# BoardSchem.net
KiCad netlist of a schematic drawn in EAGLE
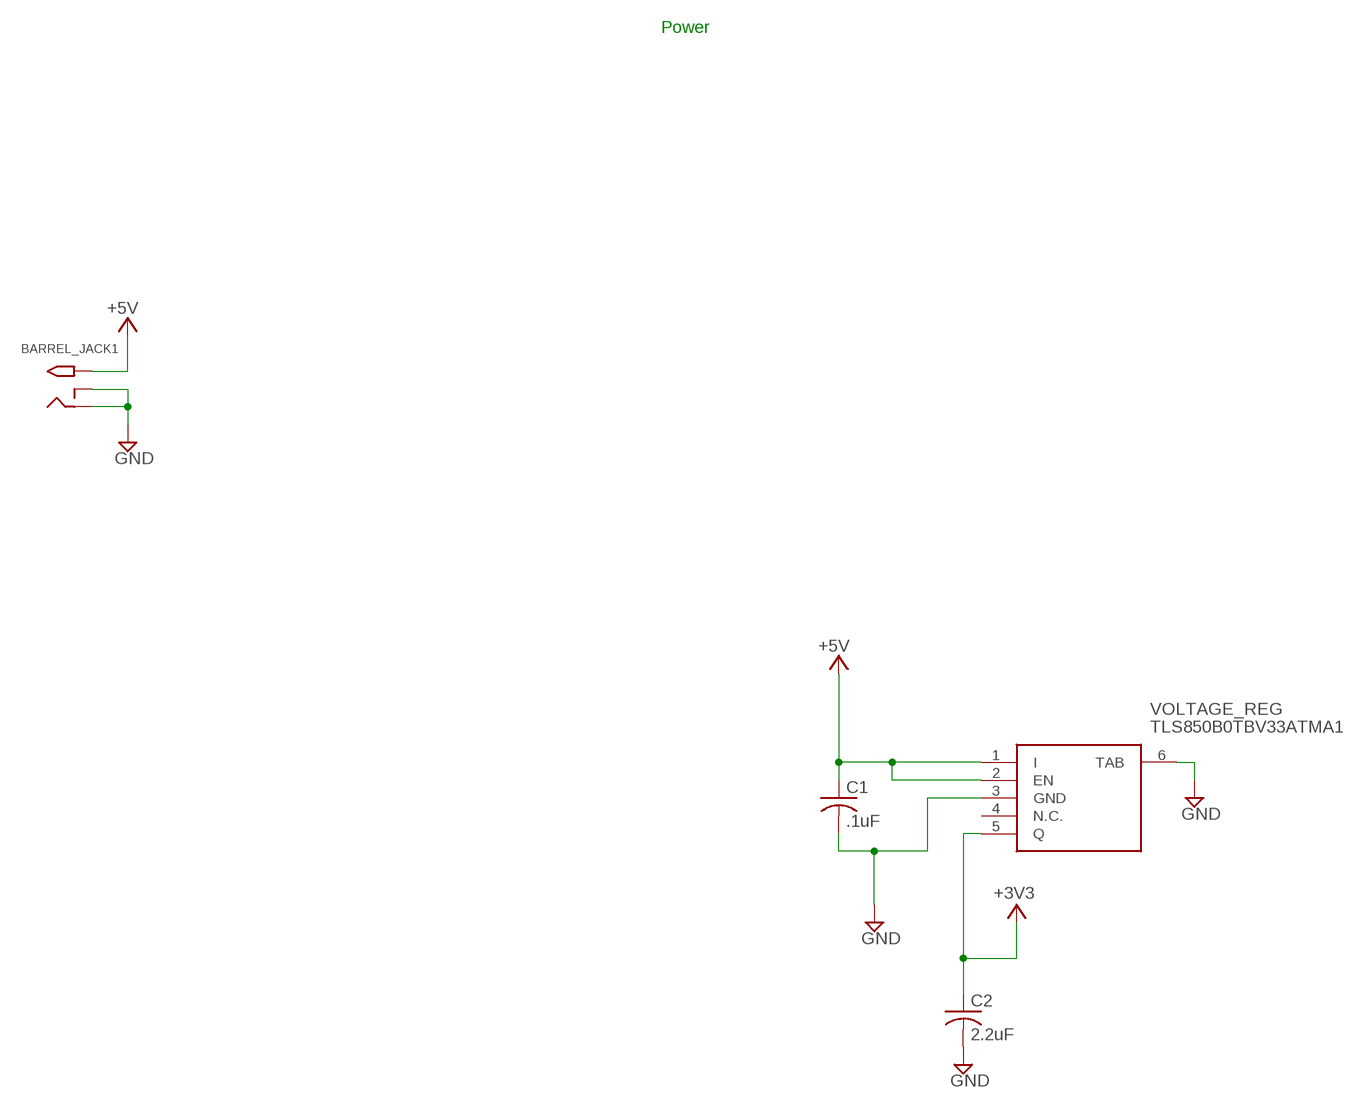
[diagram p0: schematic, sheet 1]
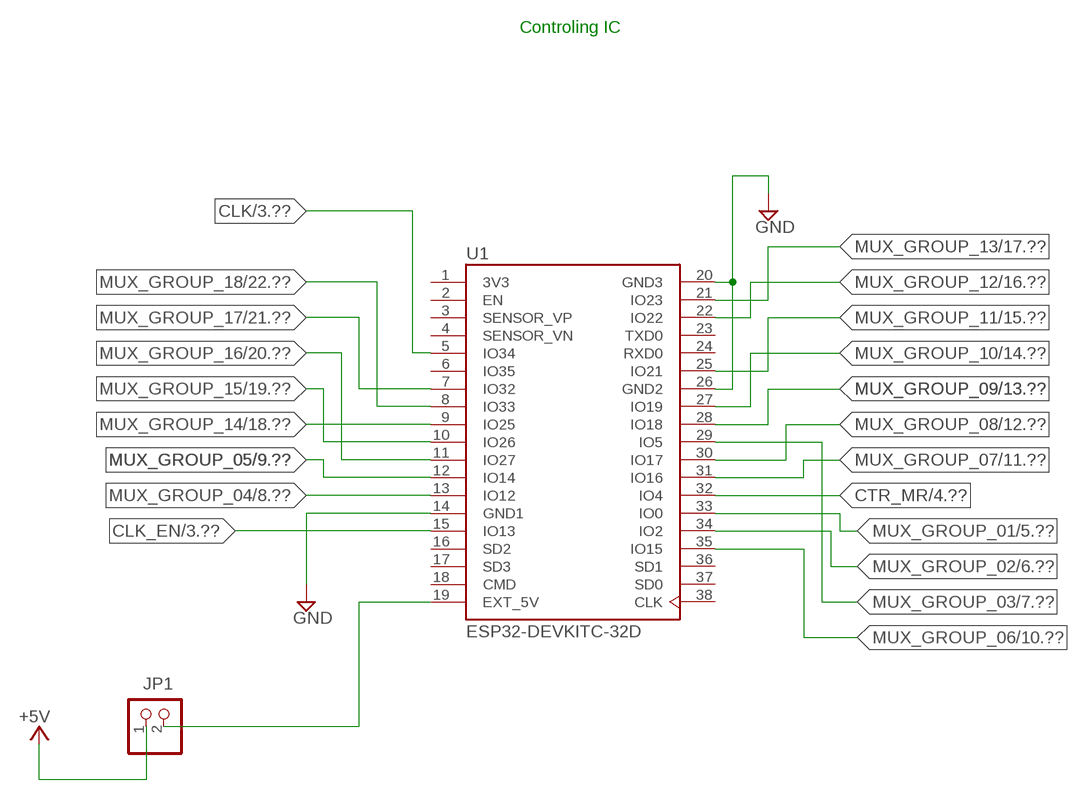
[diagram p1: schematic, sheet 2]
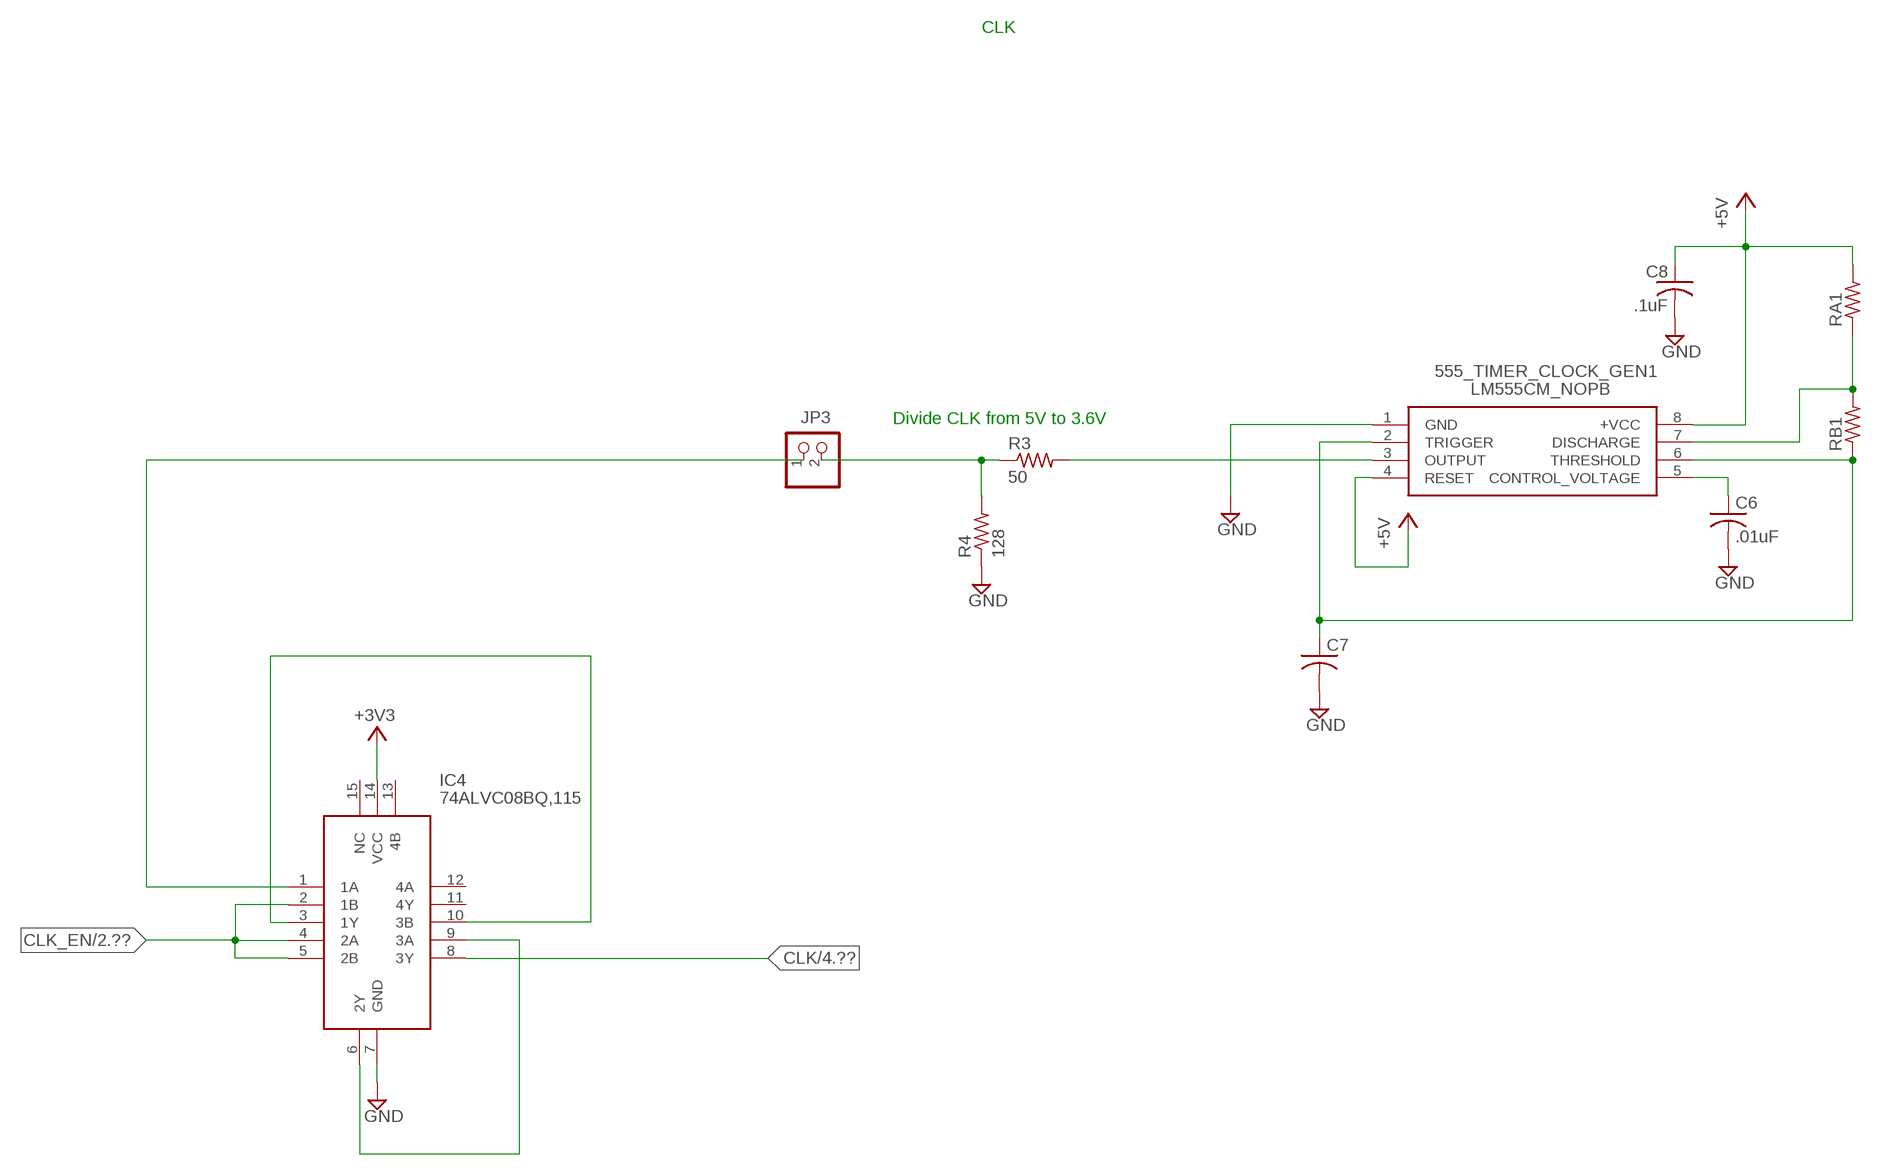
[diagram p2: schematic, sheet 3]
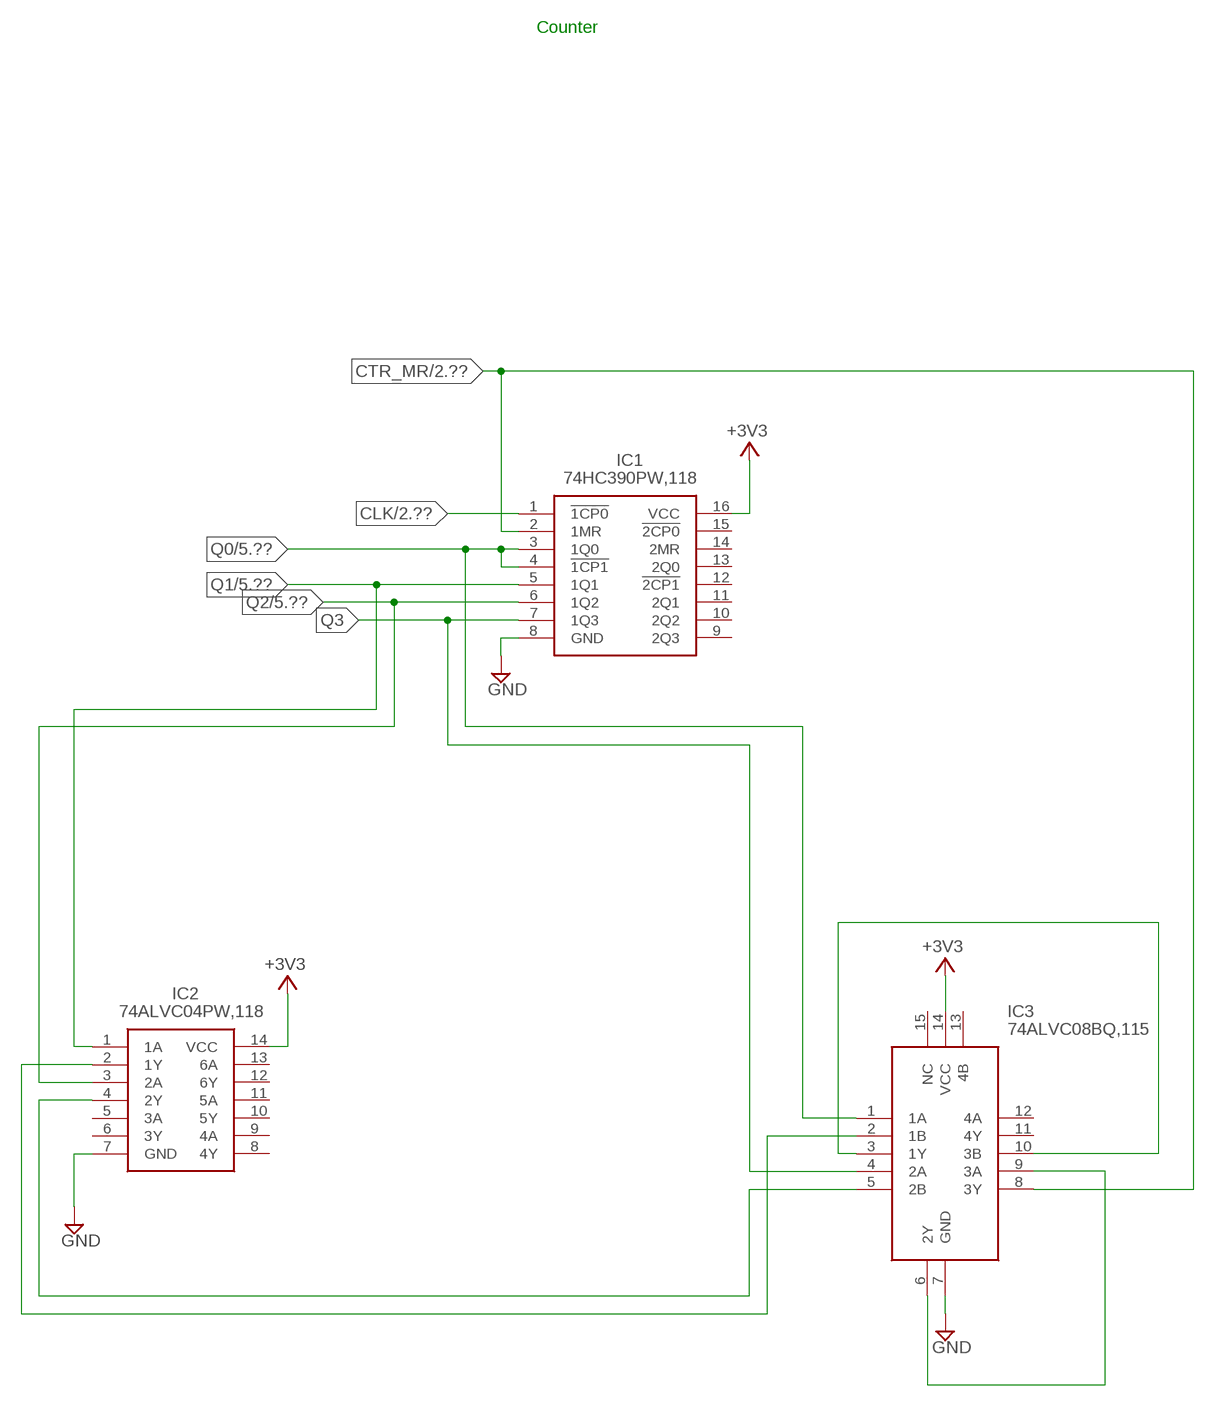
[diagram p3: schematic, sheet 4]
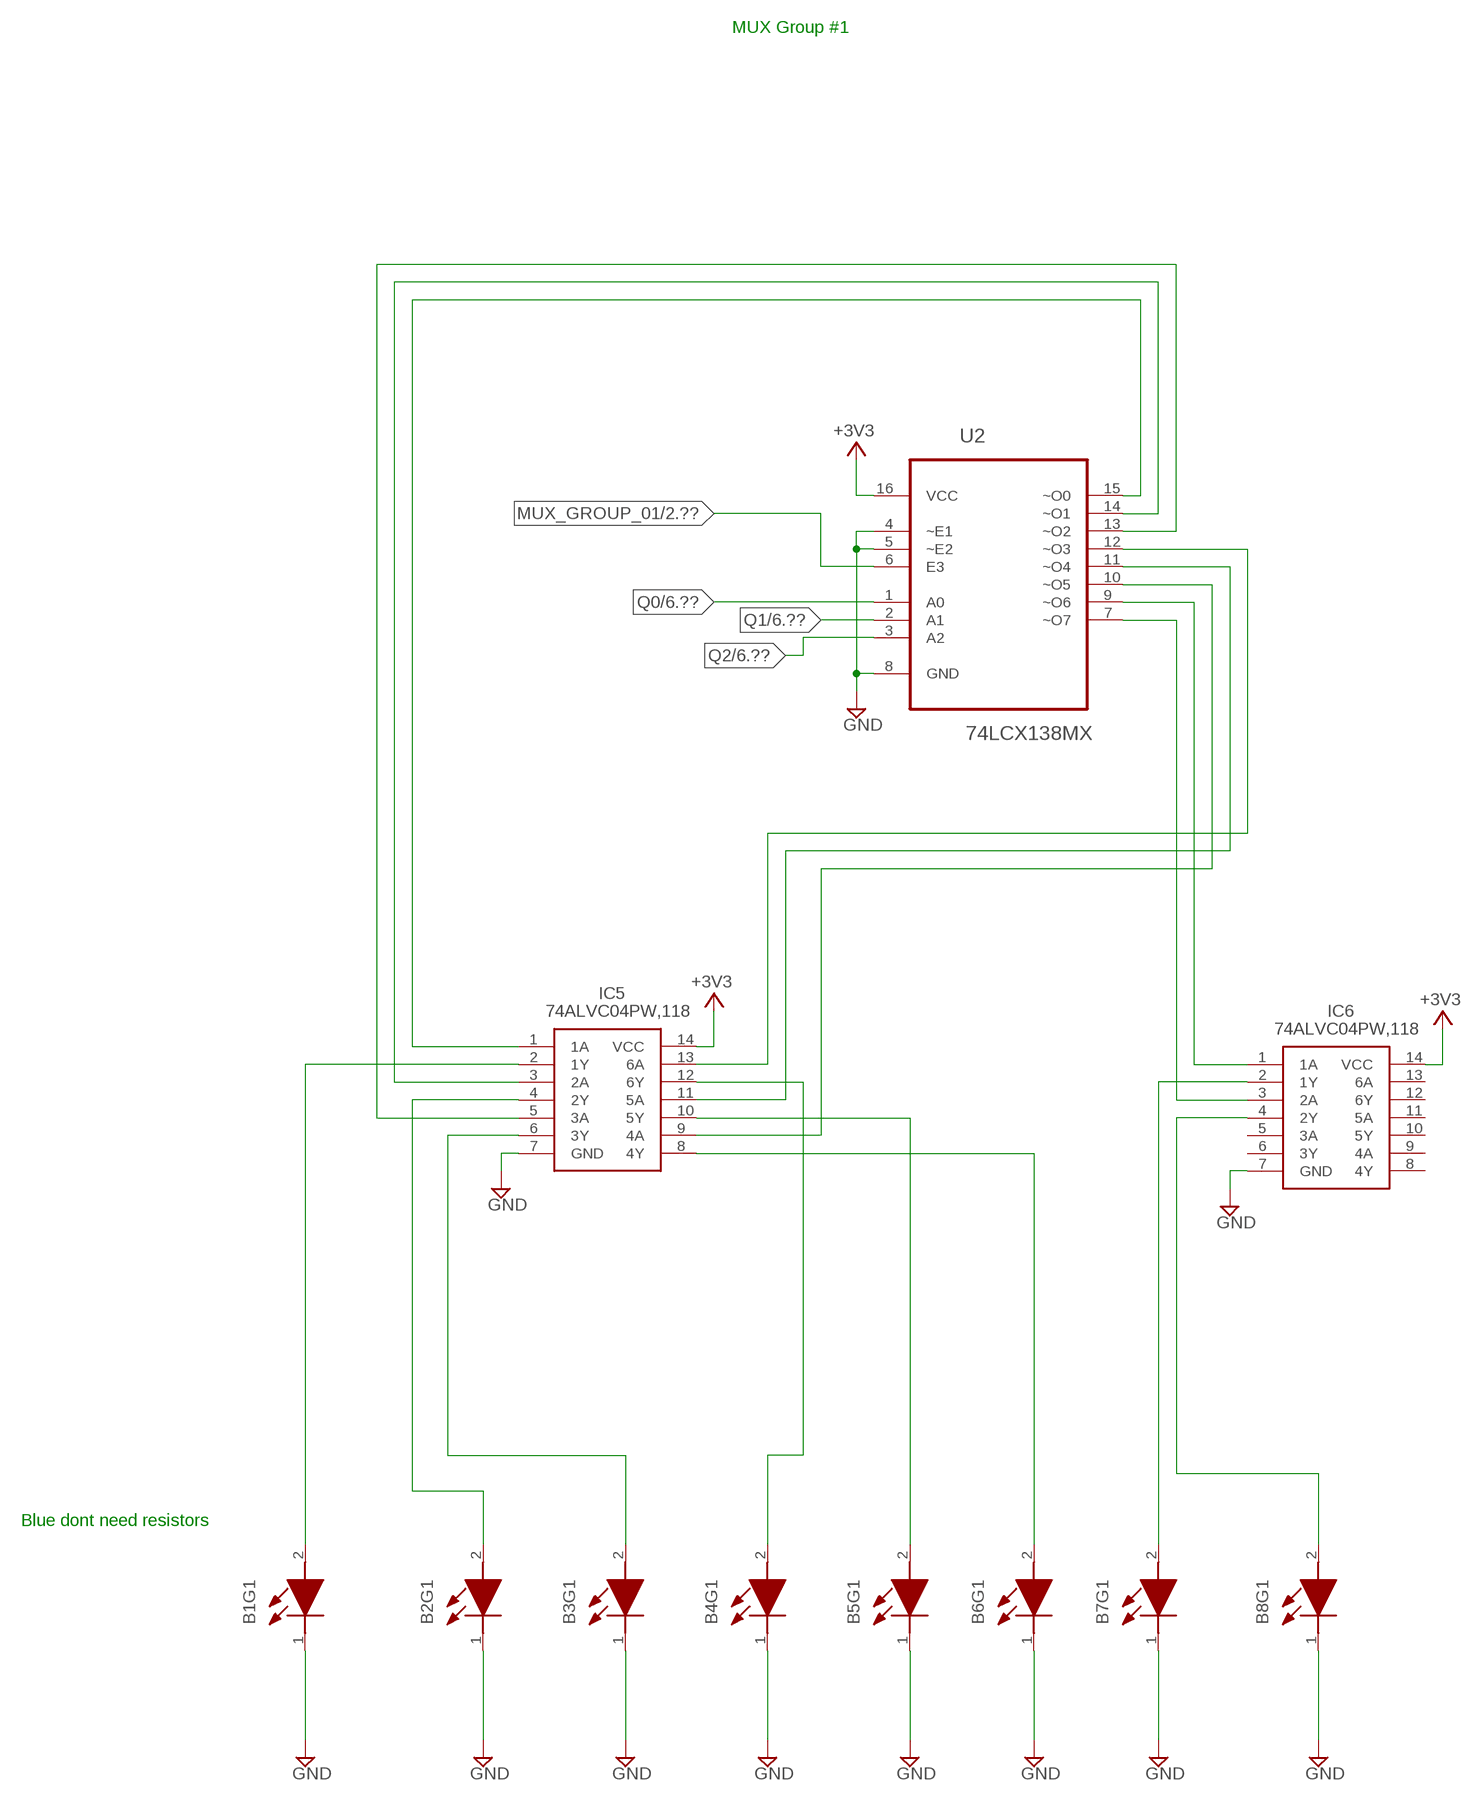
[diagram p4: schematic, sheet 5]
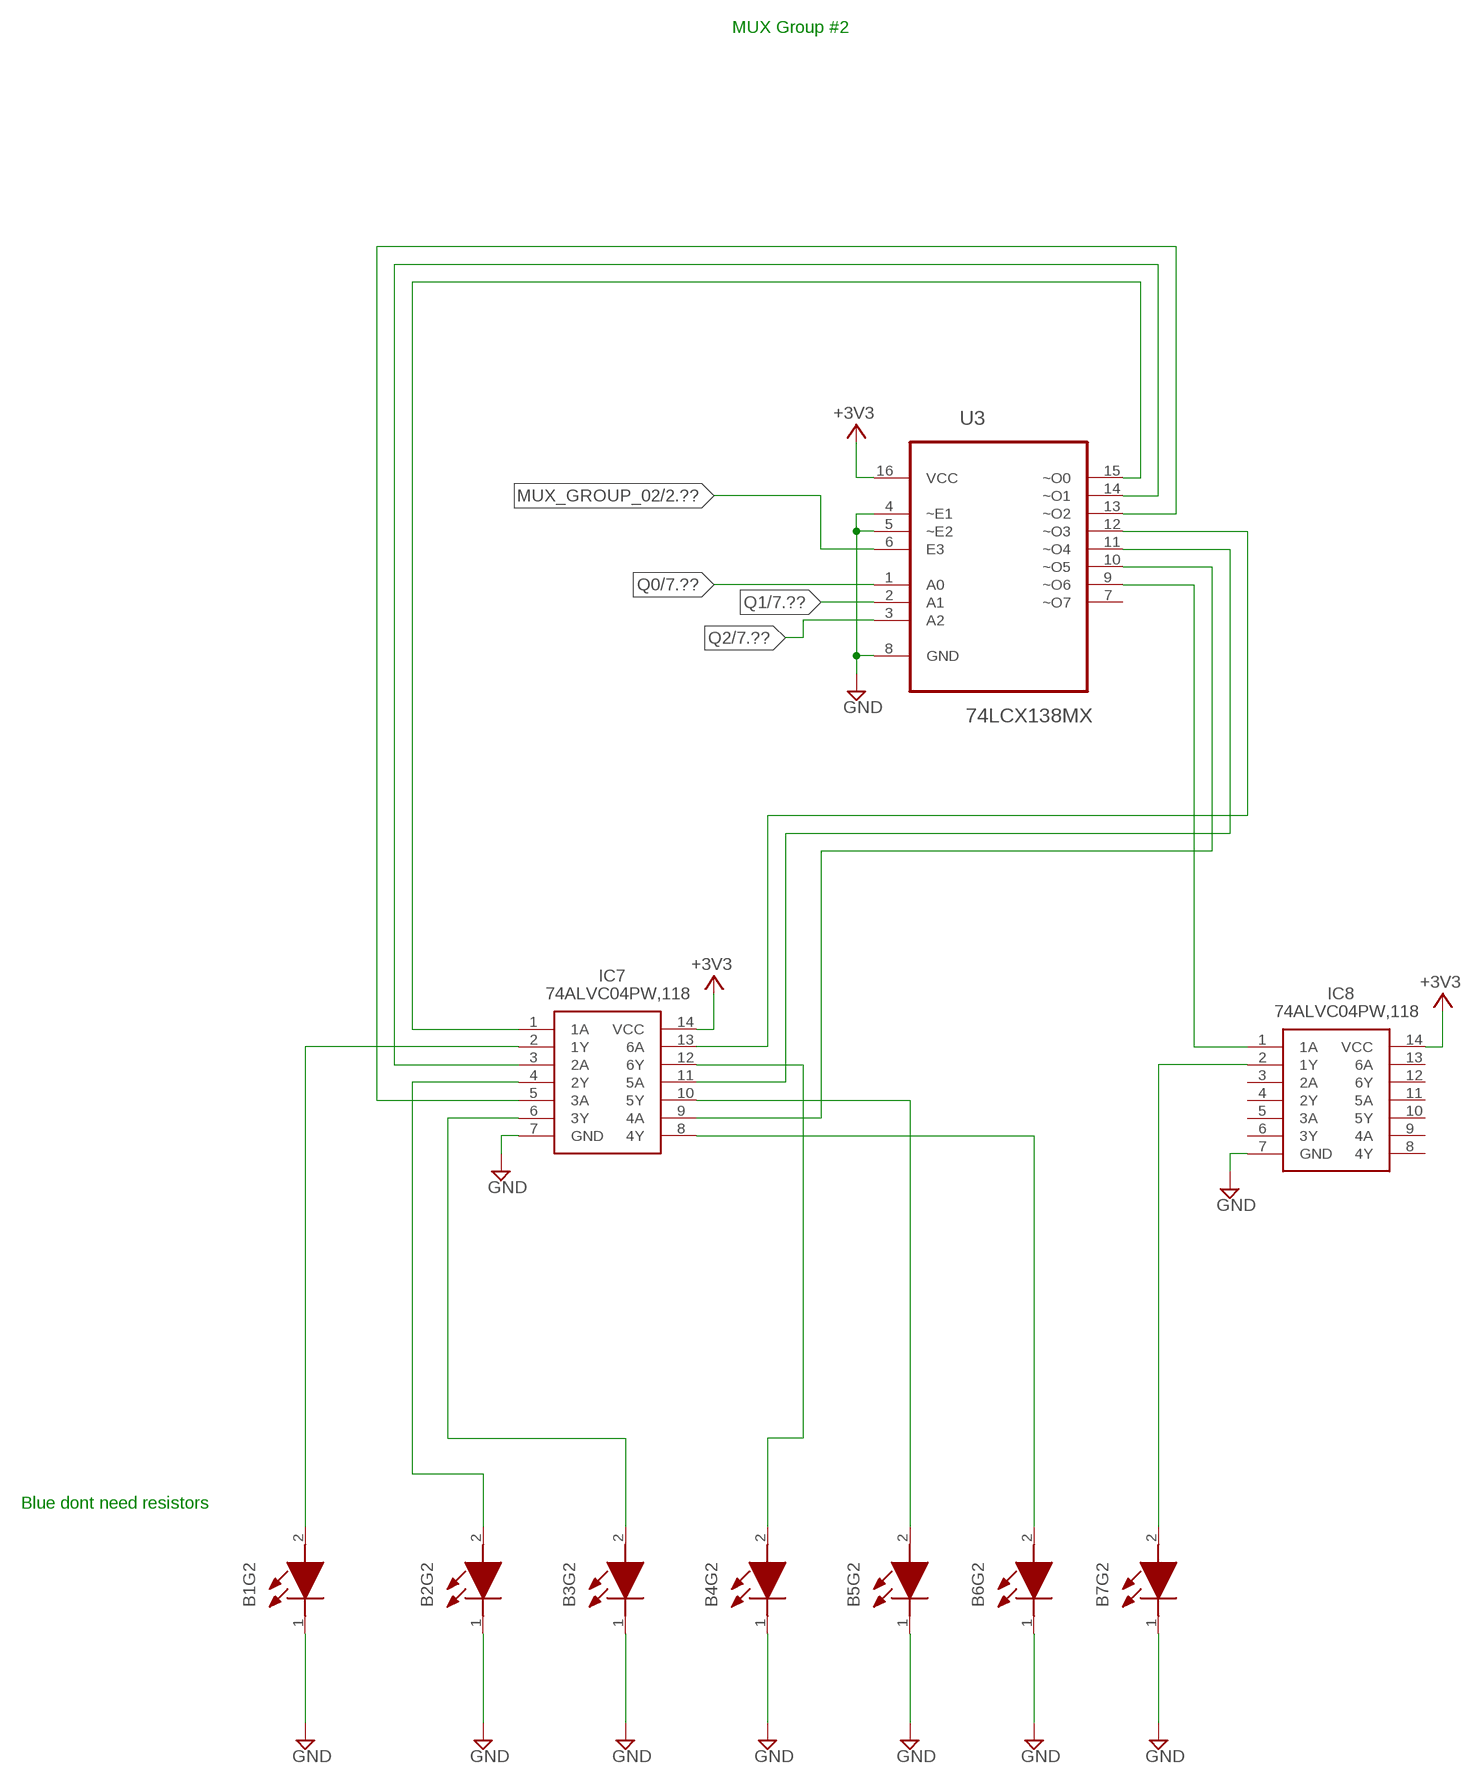
[diagram p5: schematic, sheet 6]
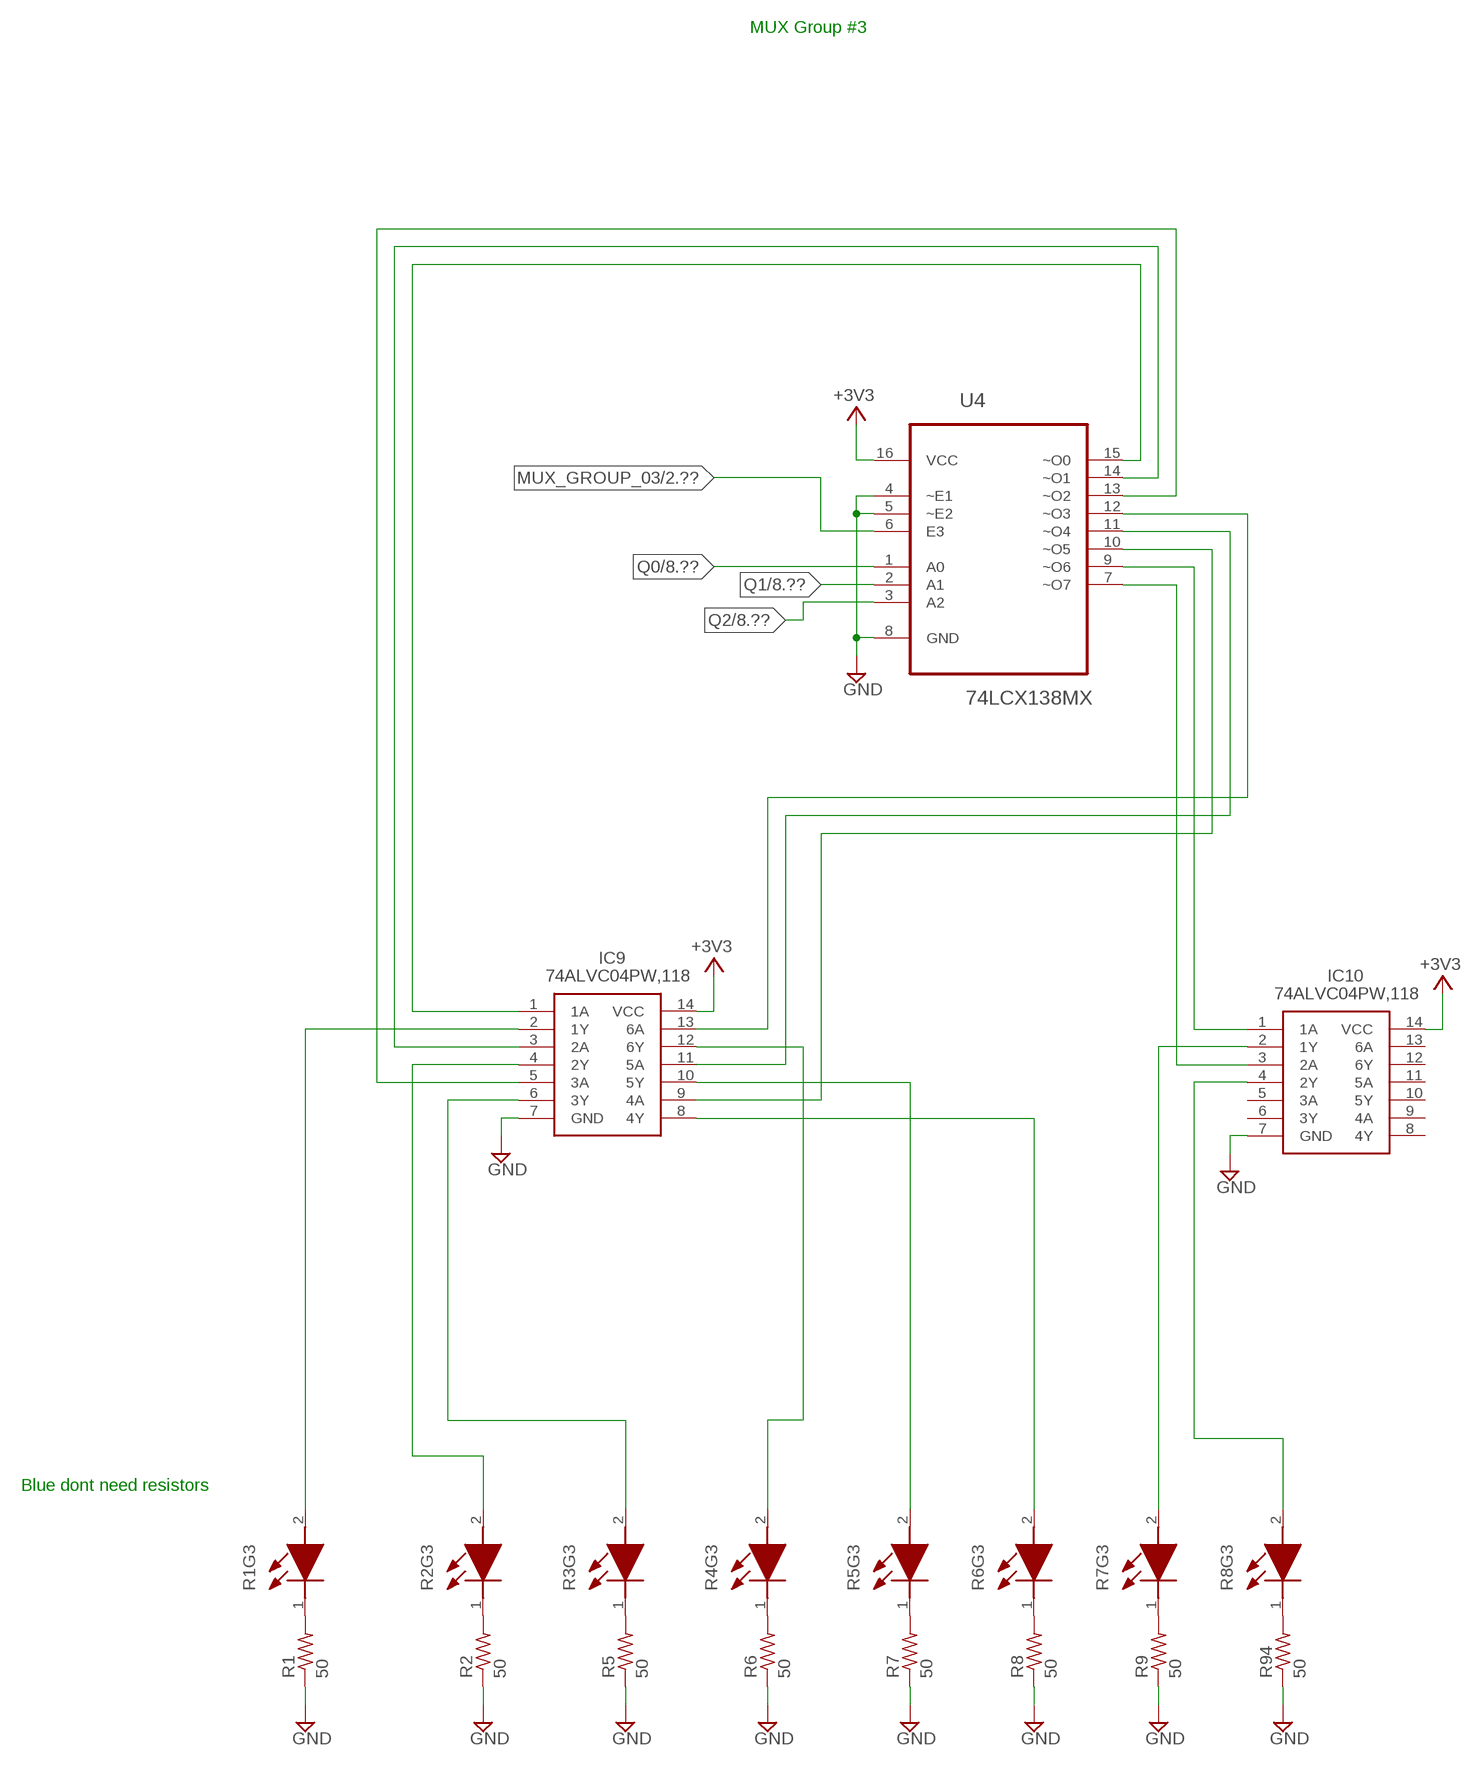
[diagram p6: schematic, sheet 7]
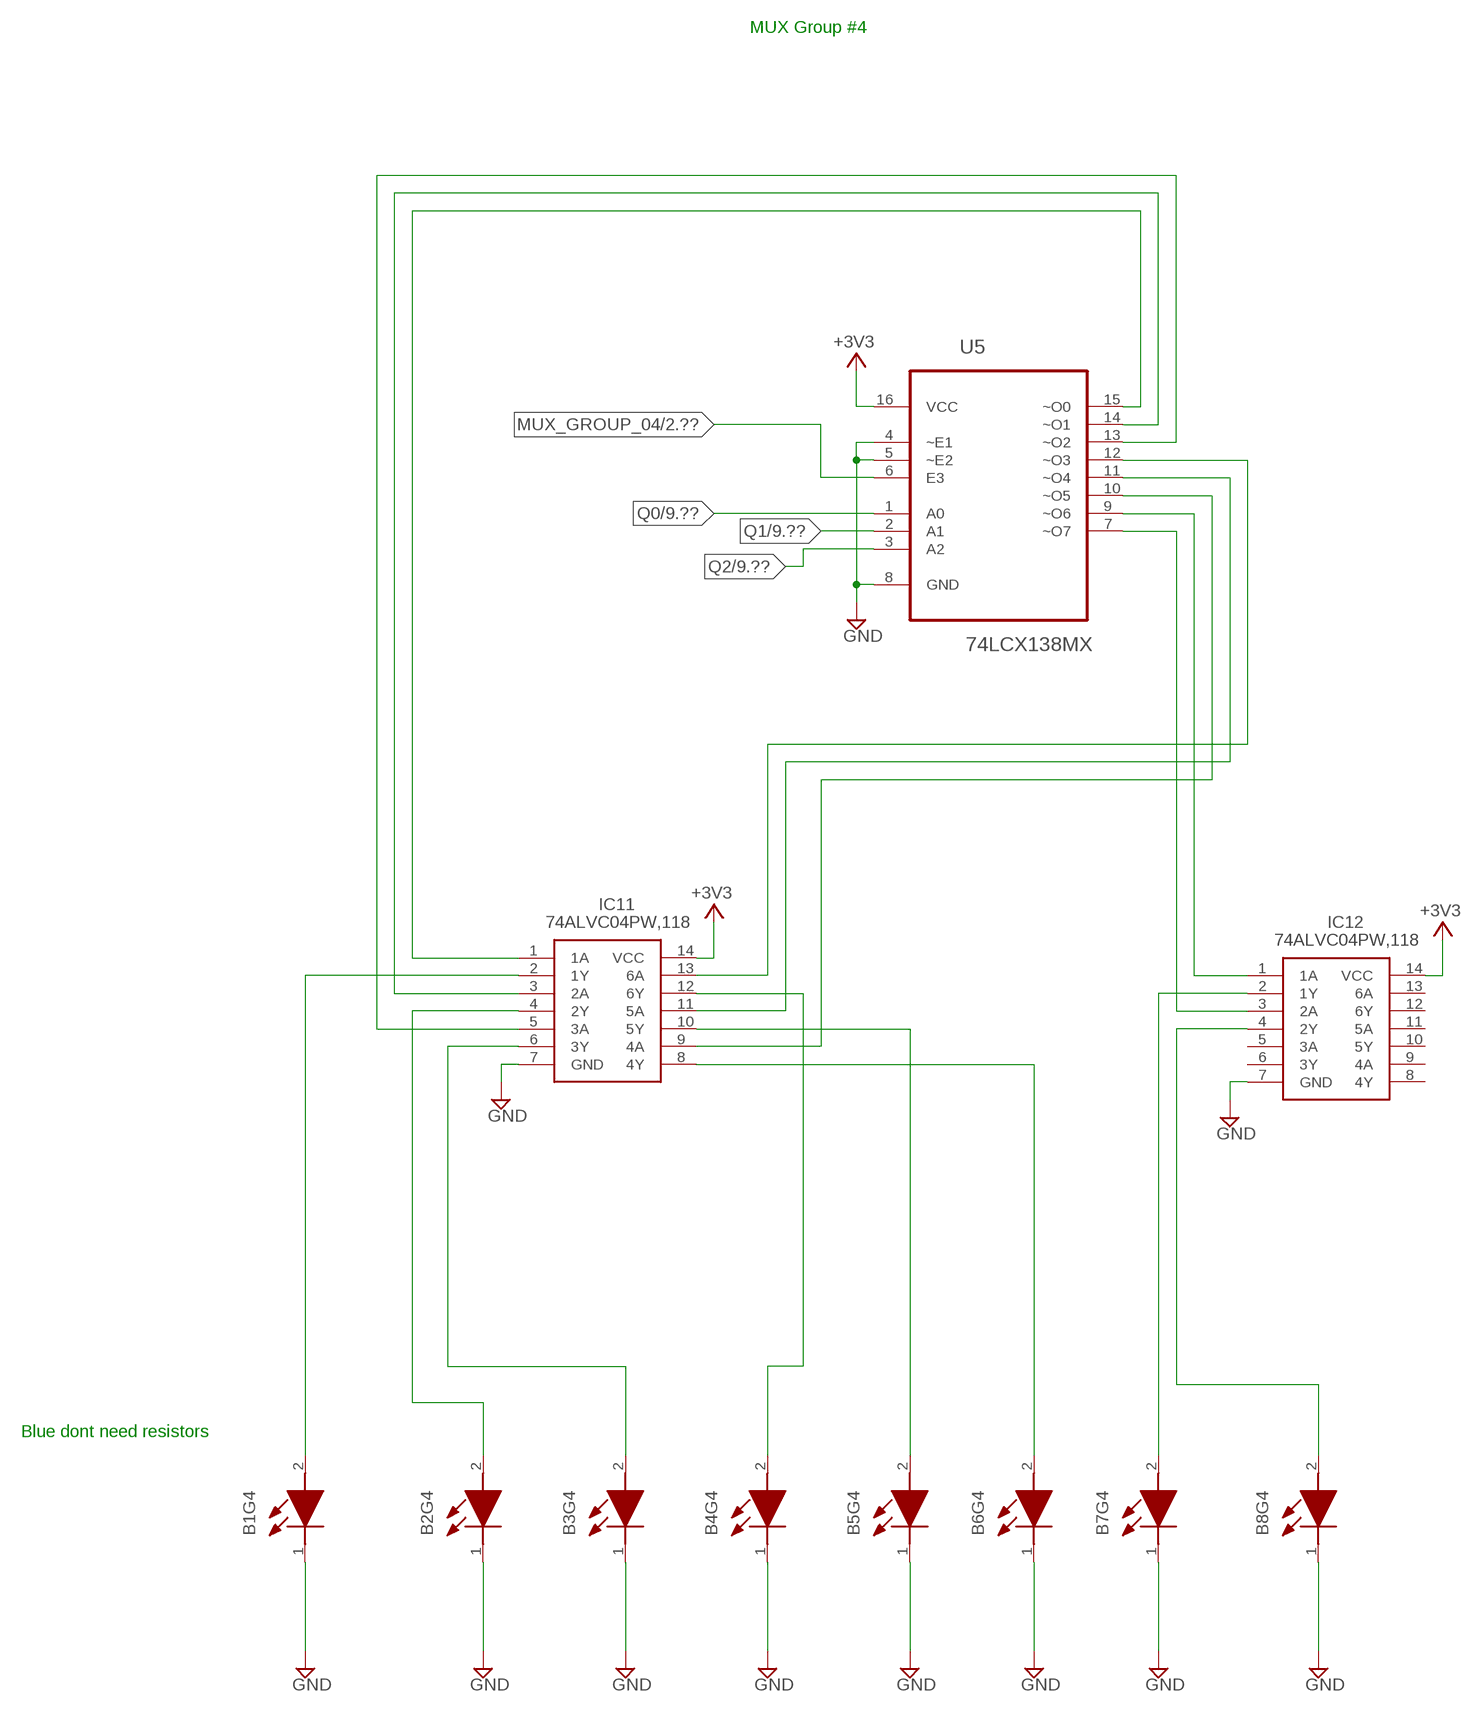
[diagram p7: schematic, sheet 8]
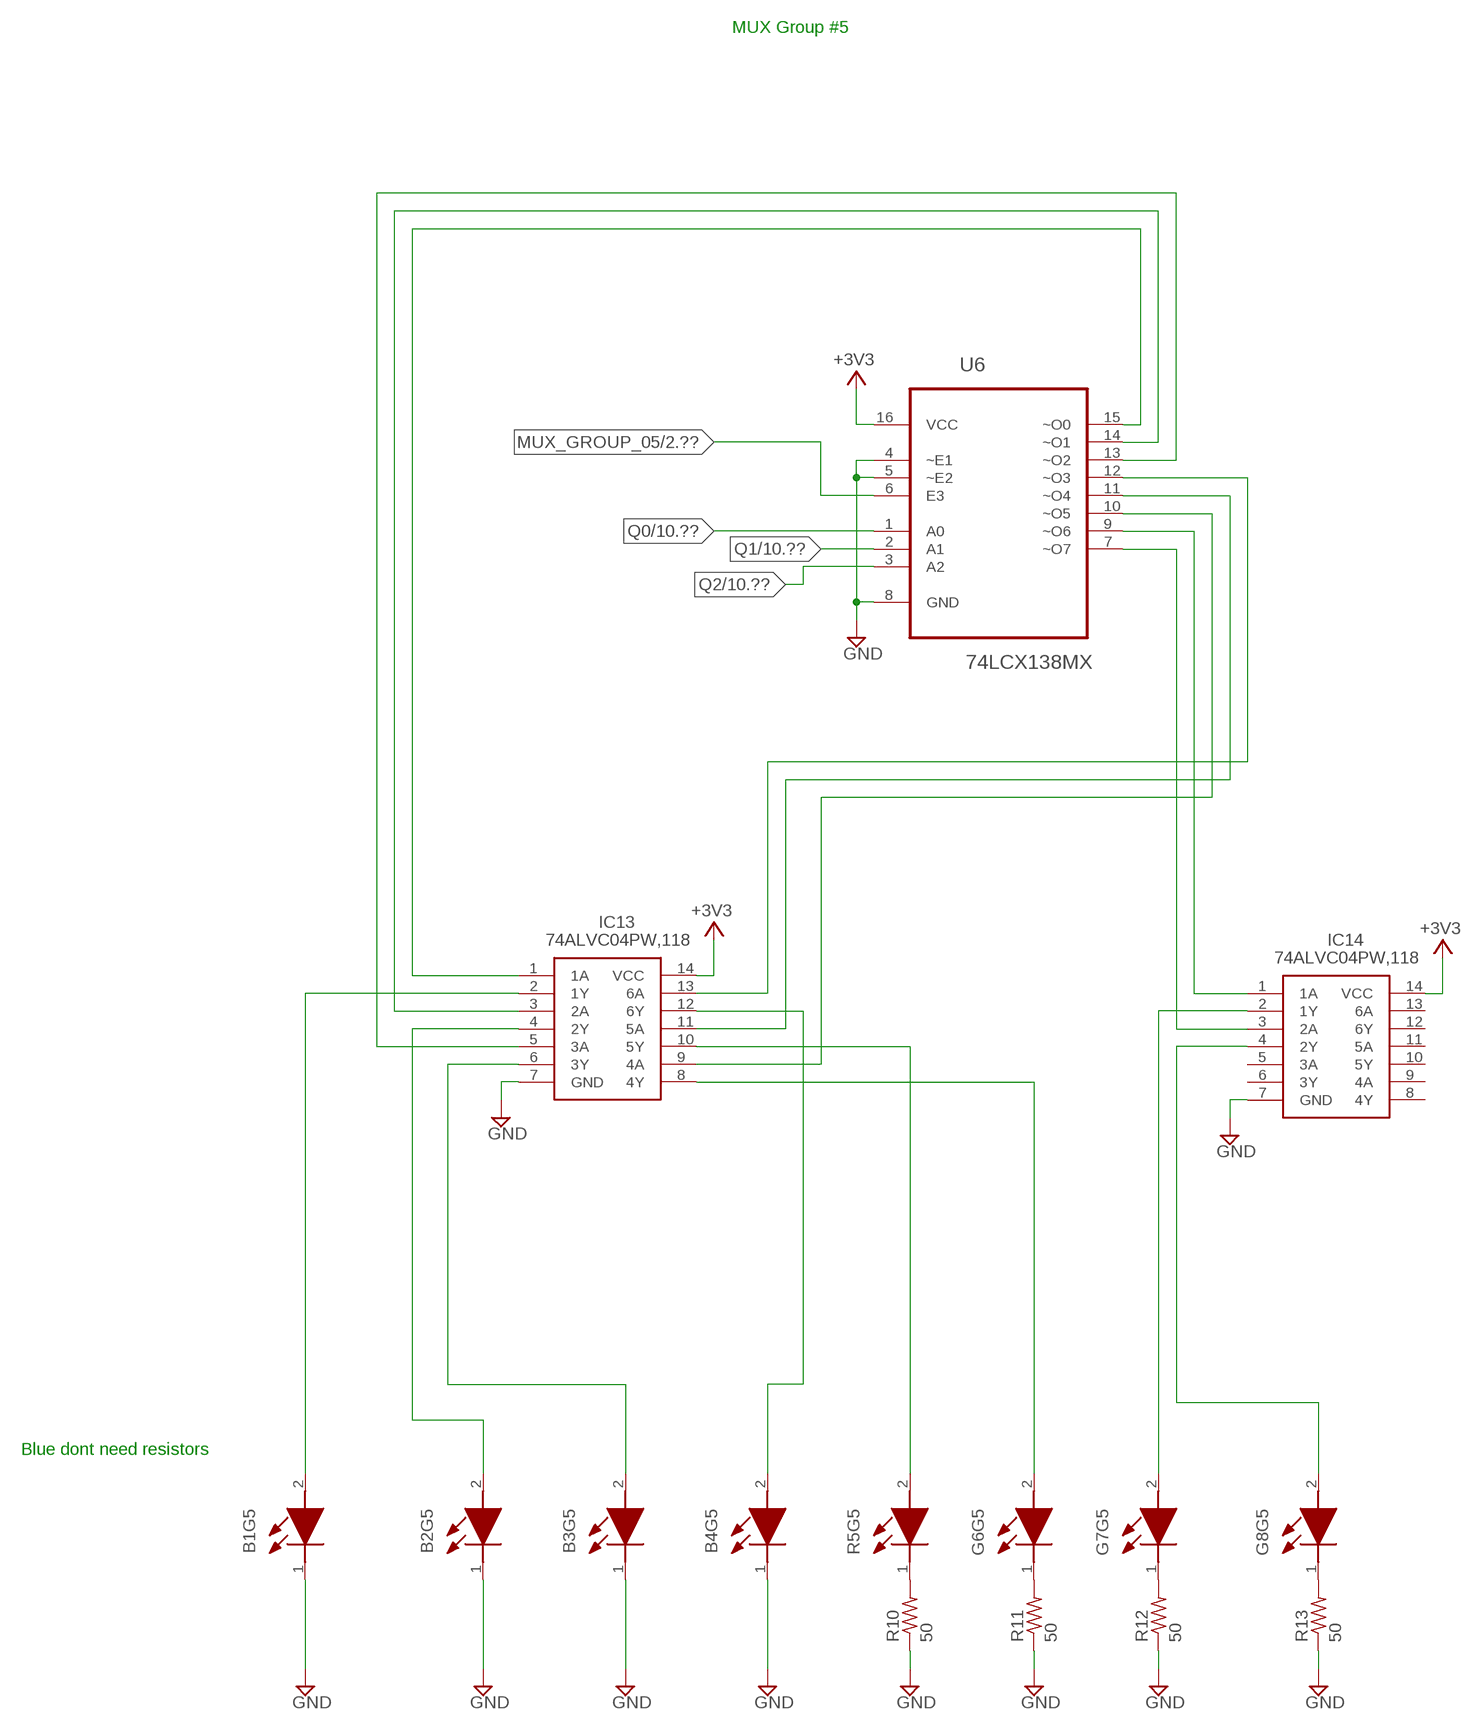
[diagram p8: schematic, sheet 9]
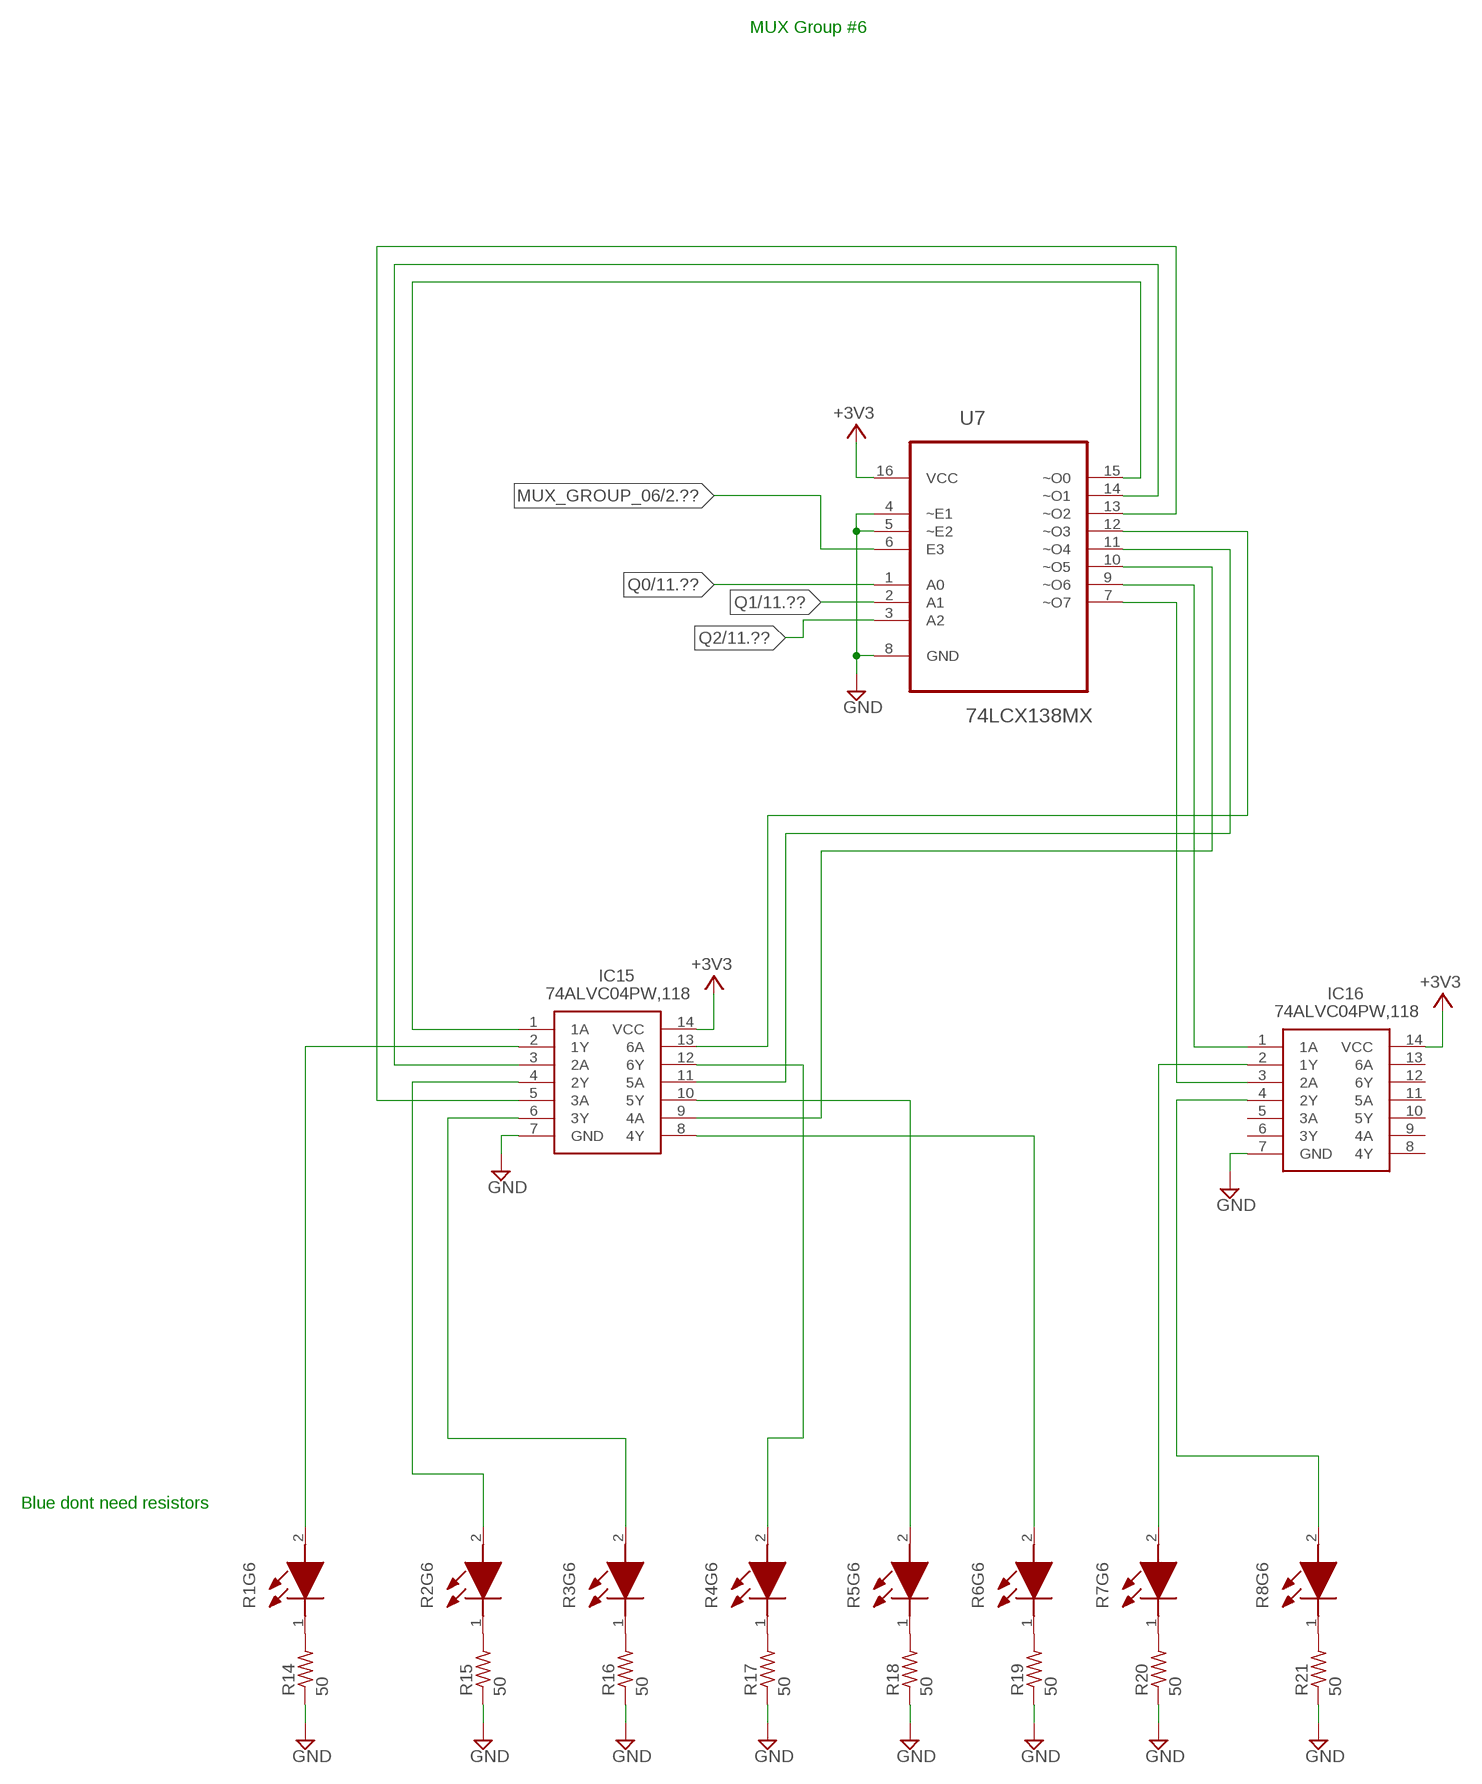
[diagram p9: schematic, sheet 10]
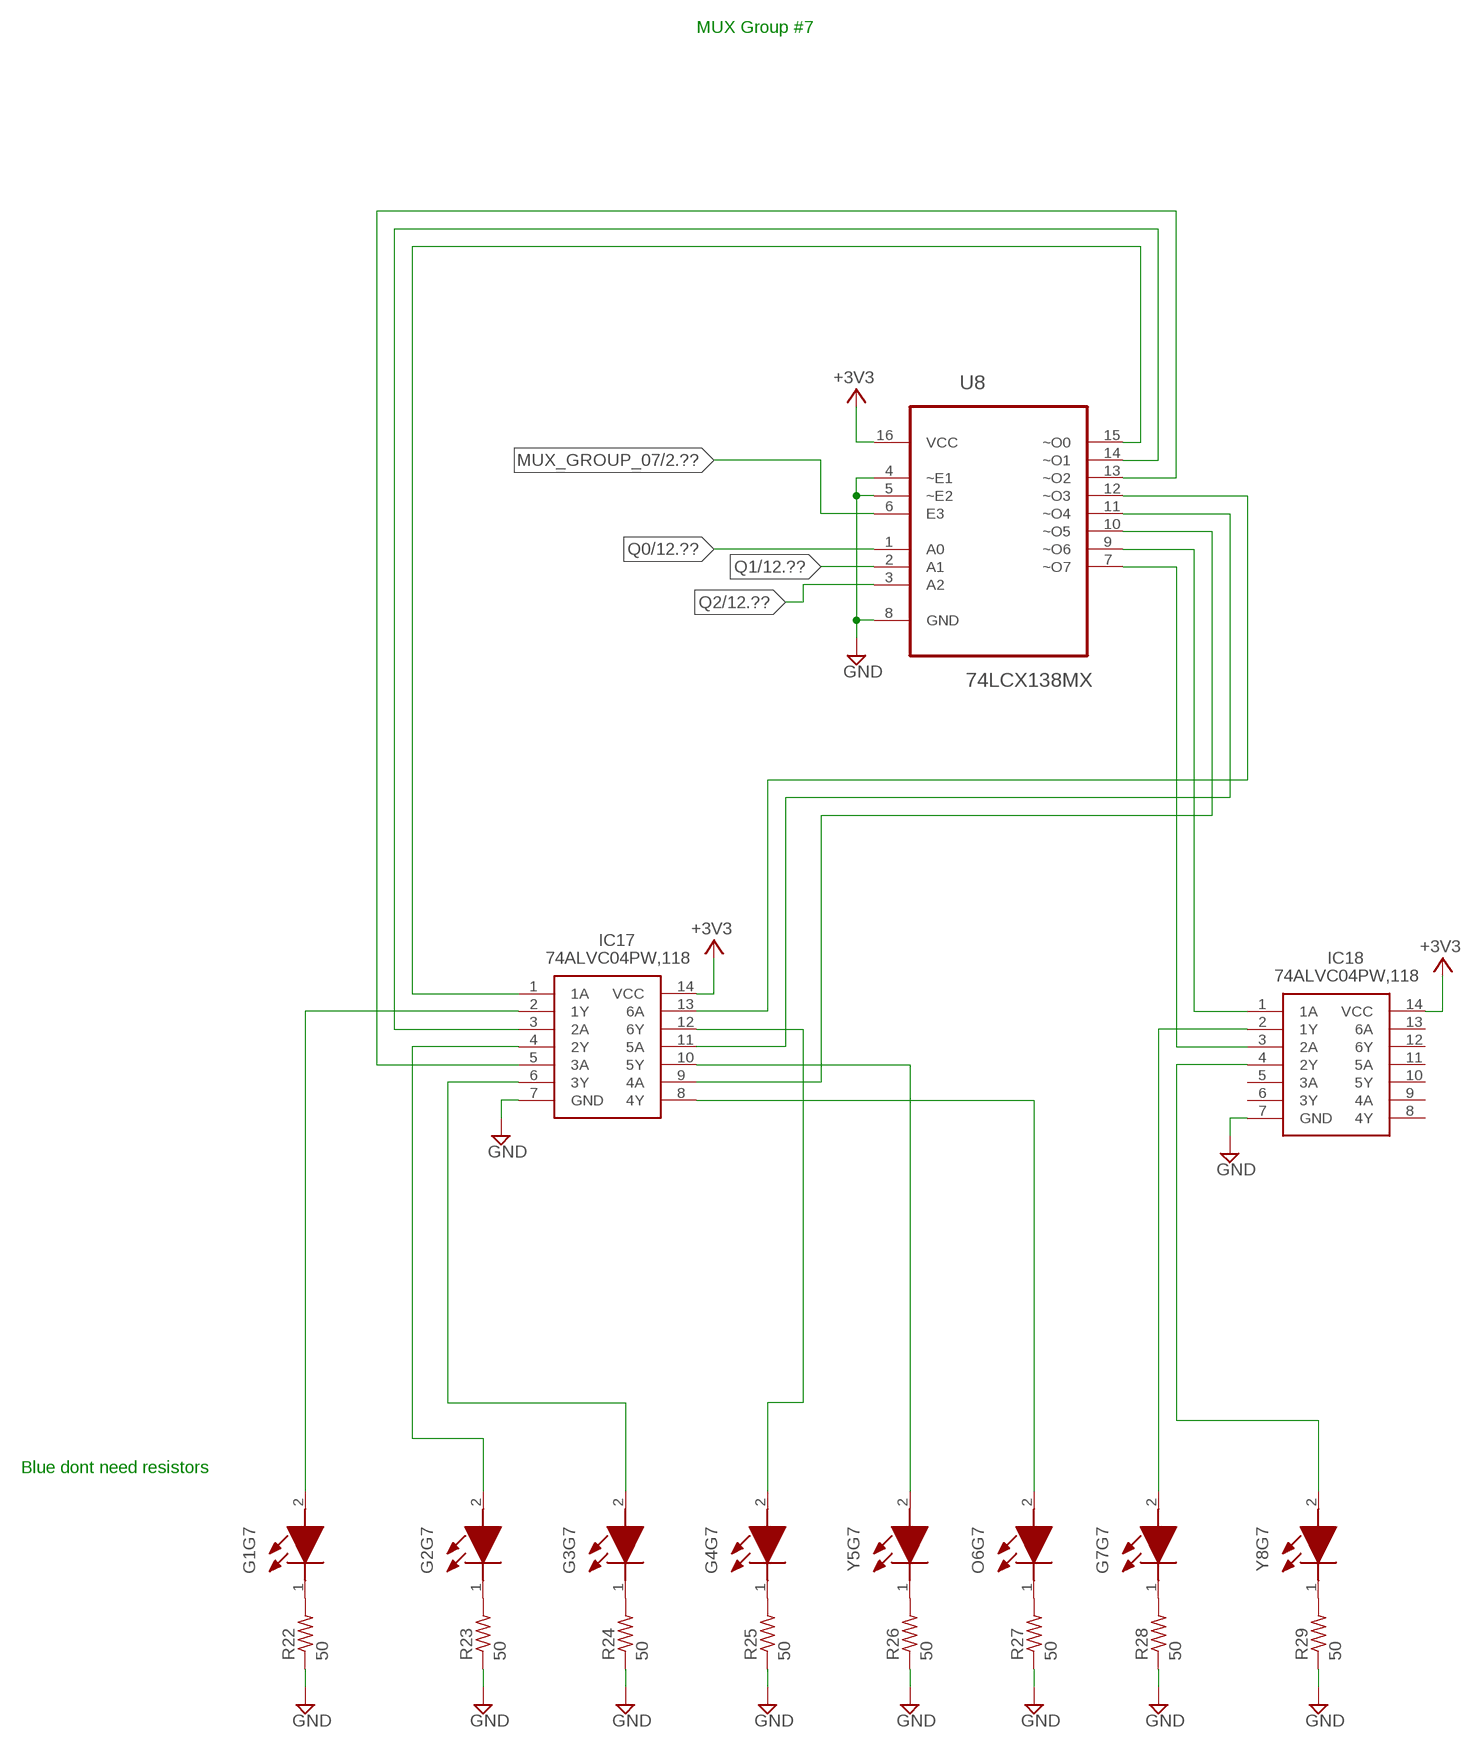
[diagram p10: schematic, sheet 11]
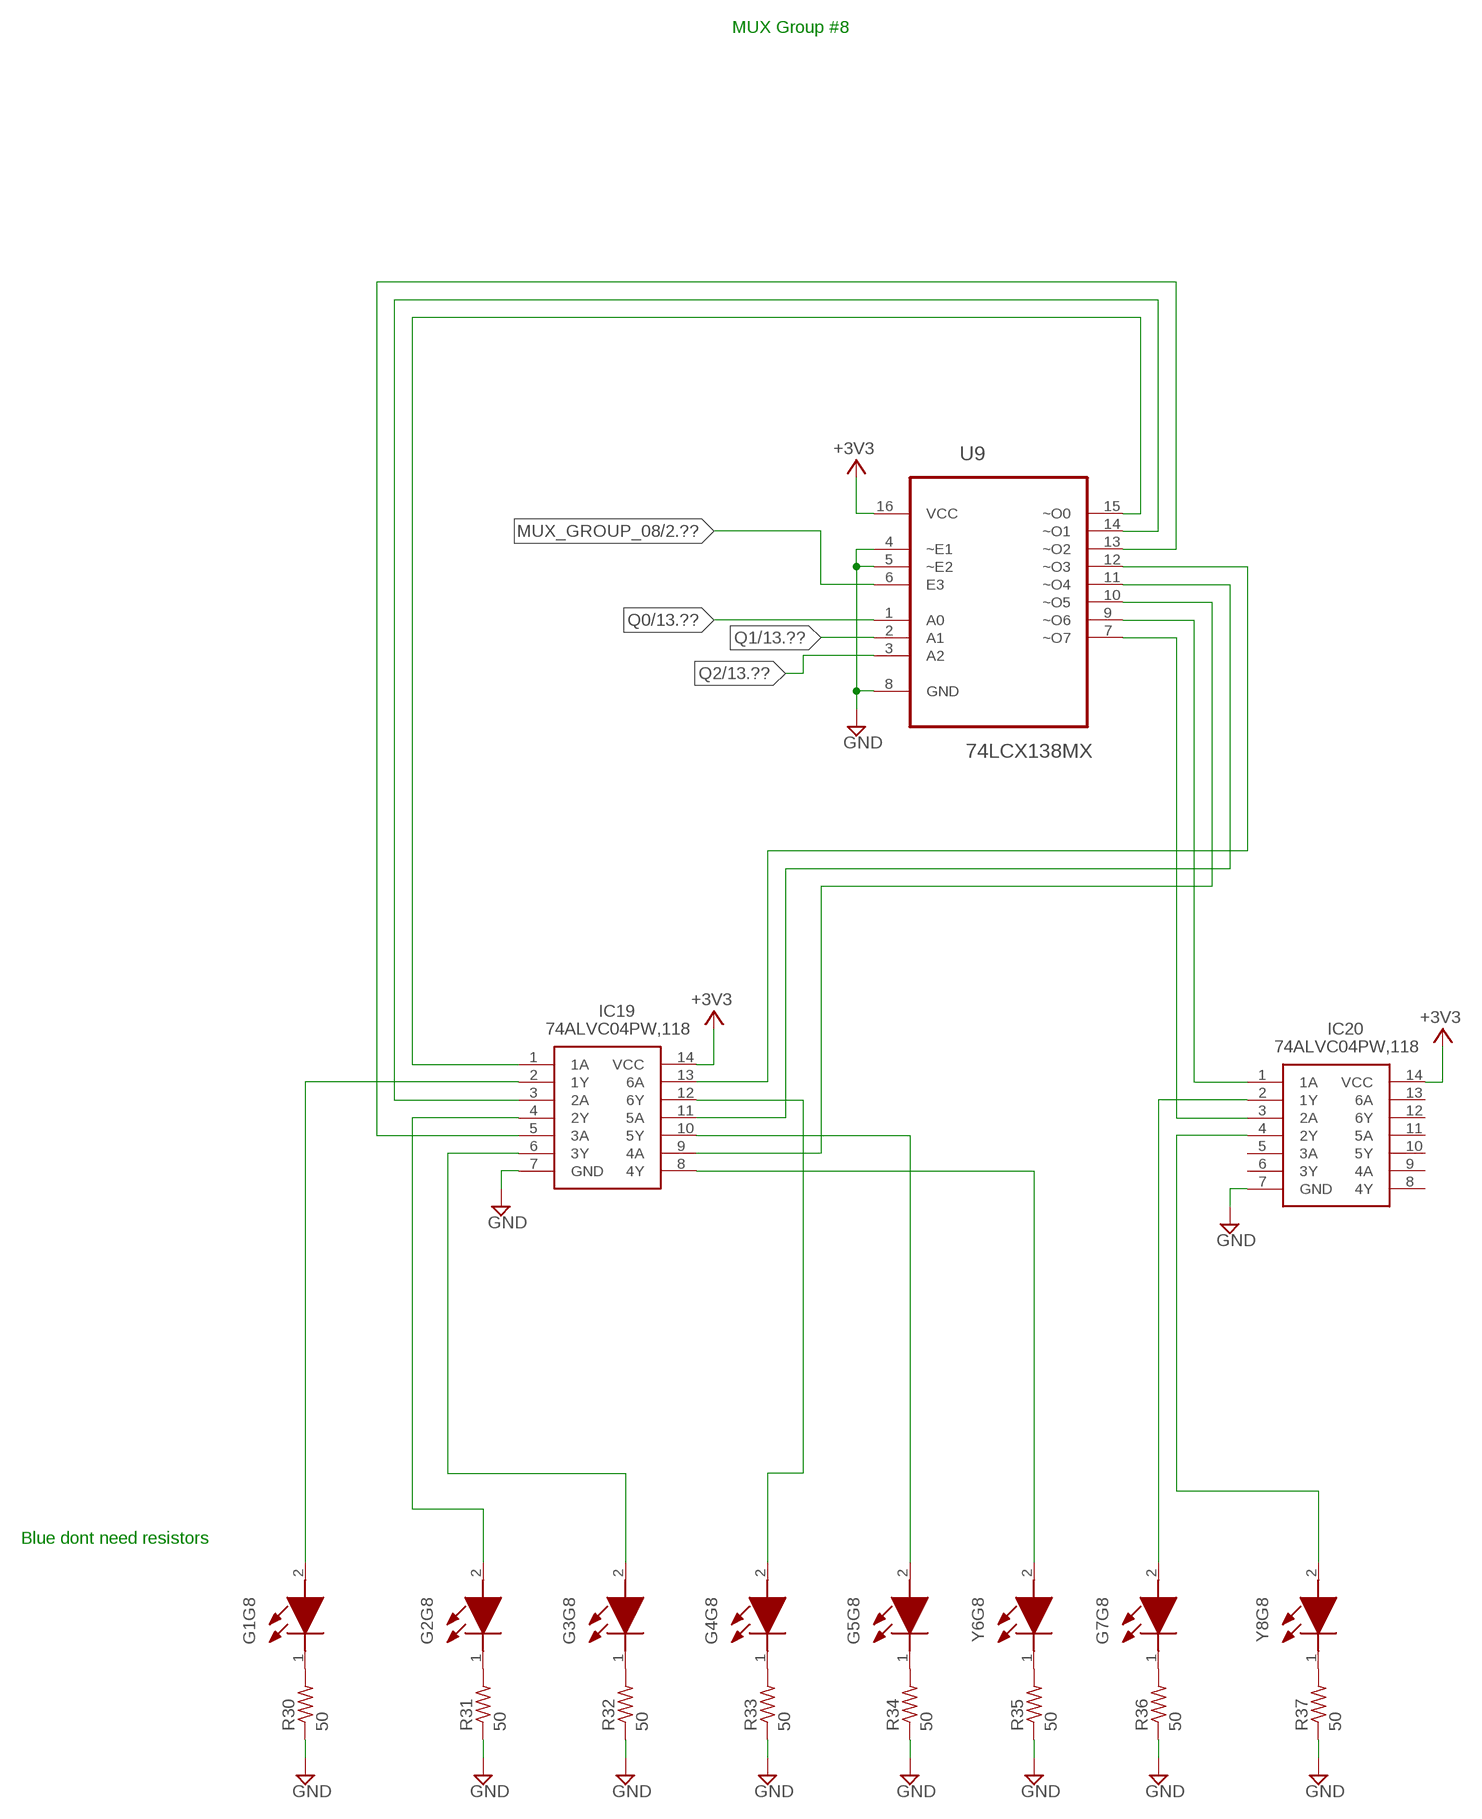
[diagram p11: schematic, sheet 12]
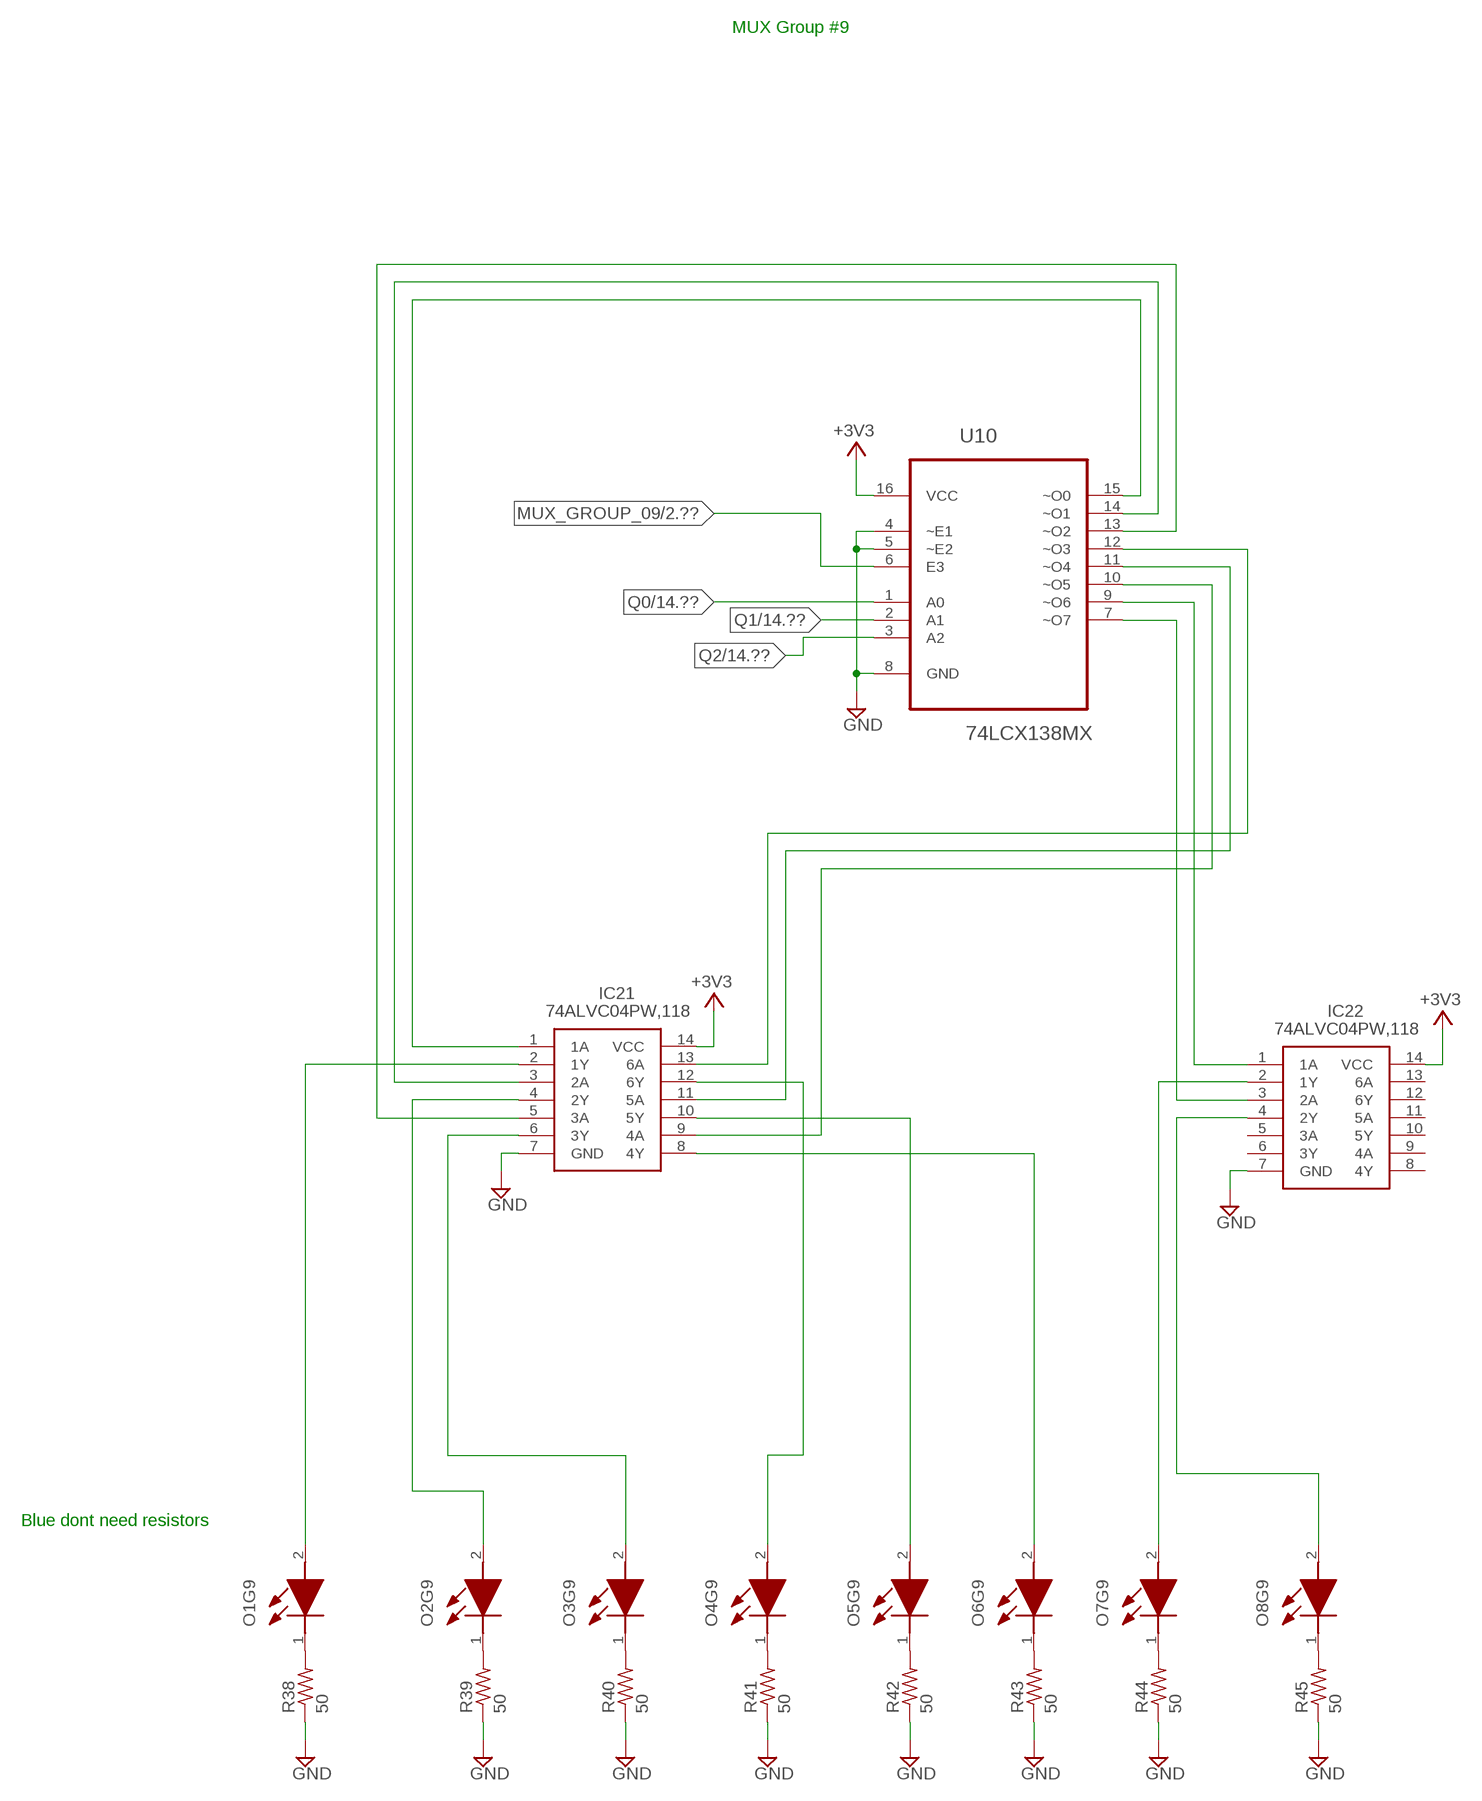
[diagram p12: schematic, sheet 13]
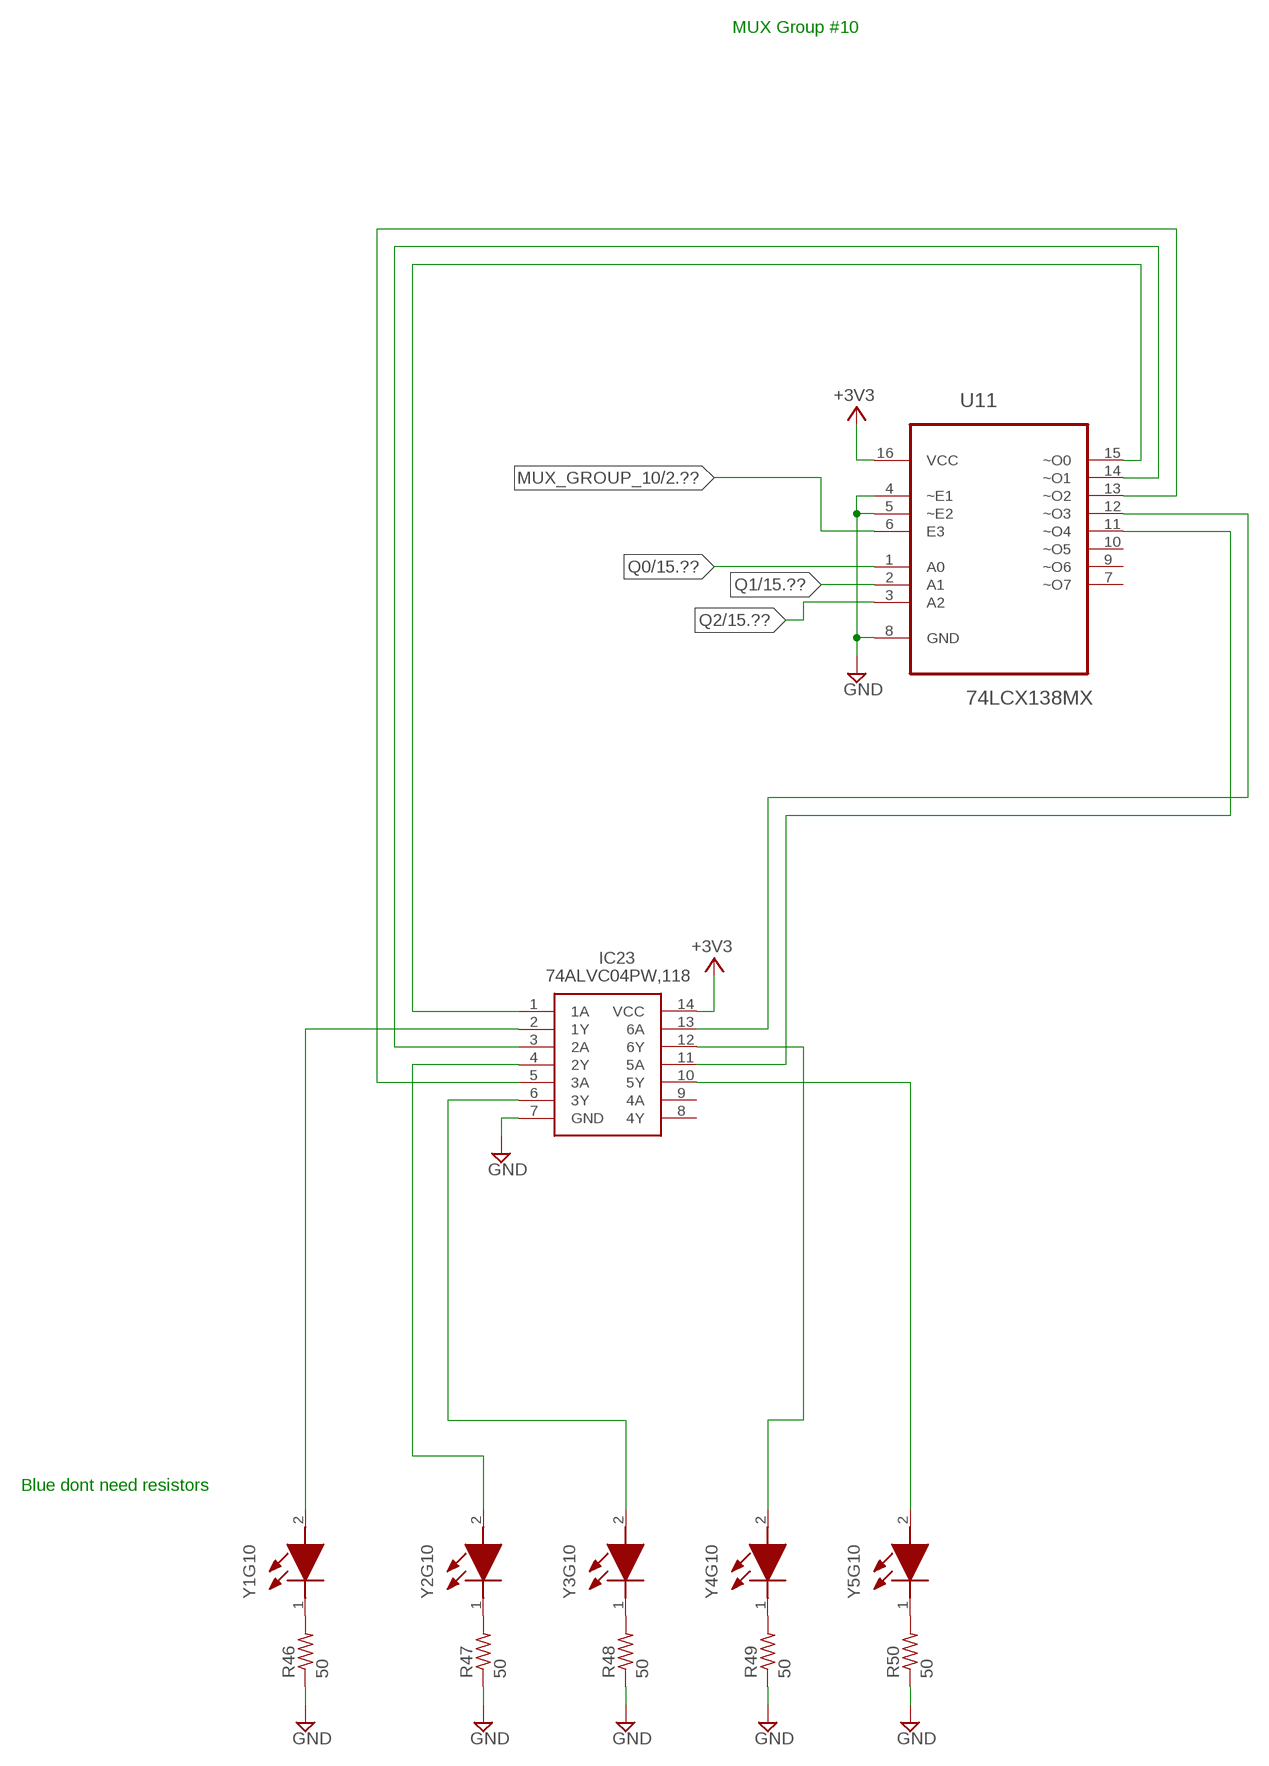
[diagram p13: schematic, sheet 14]
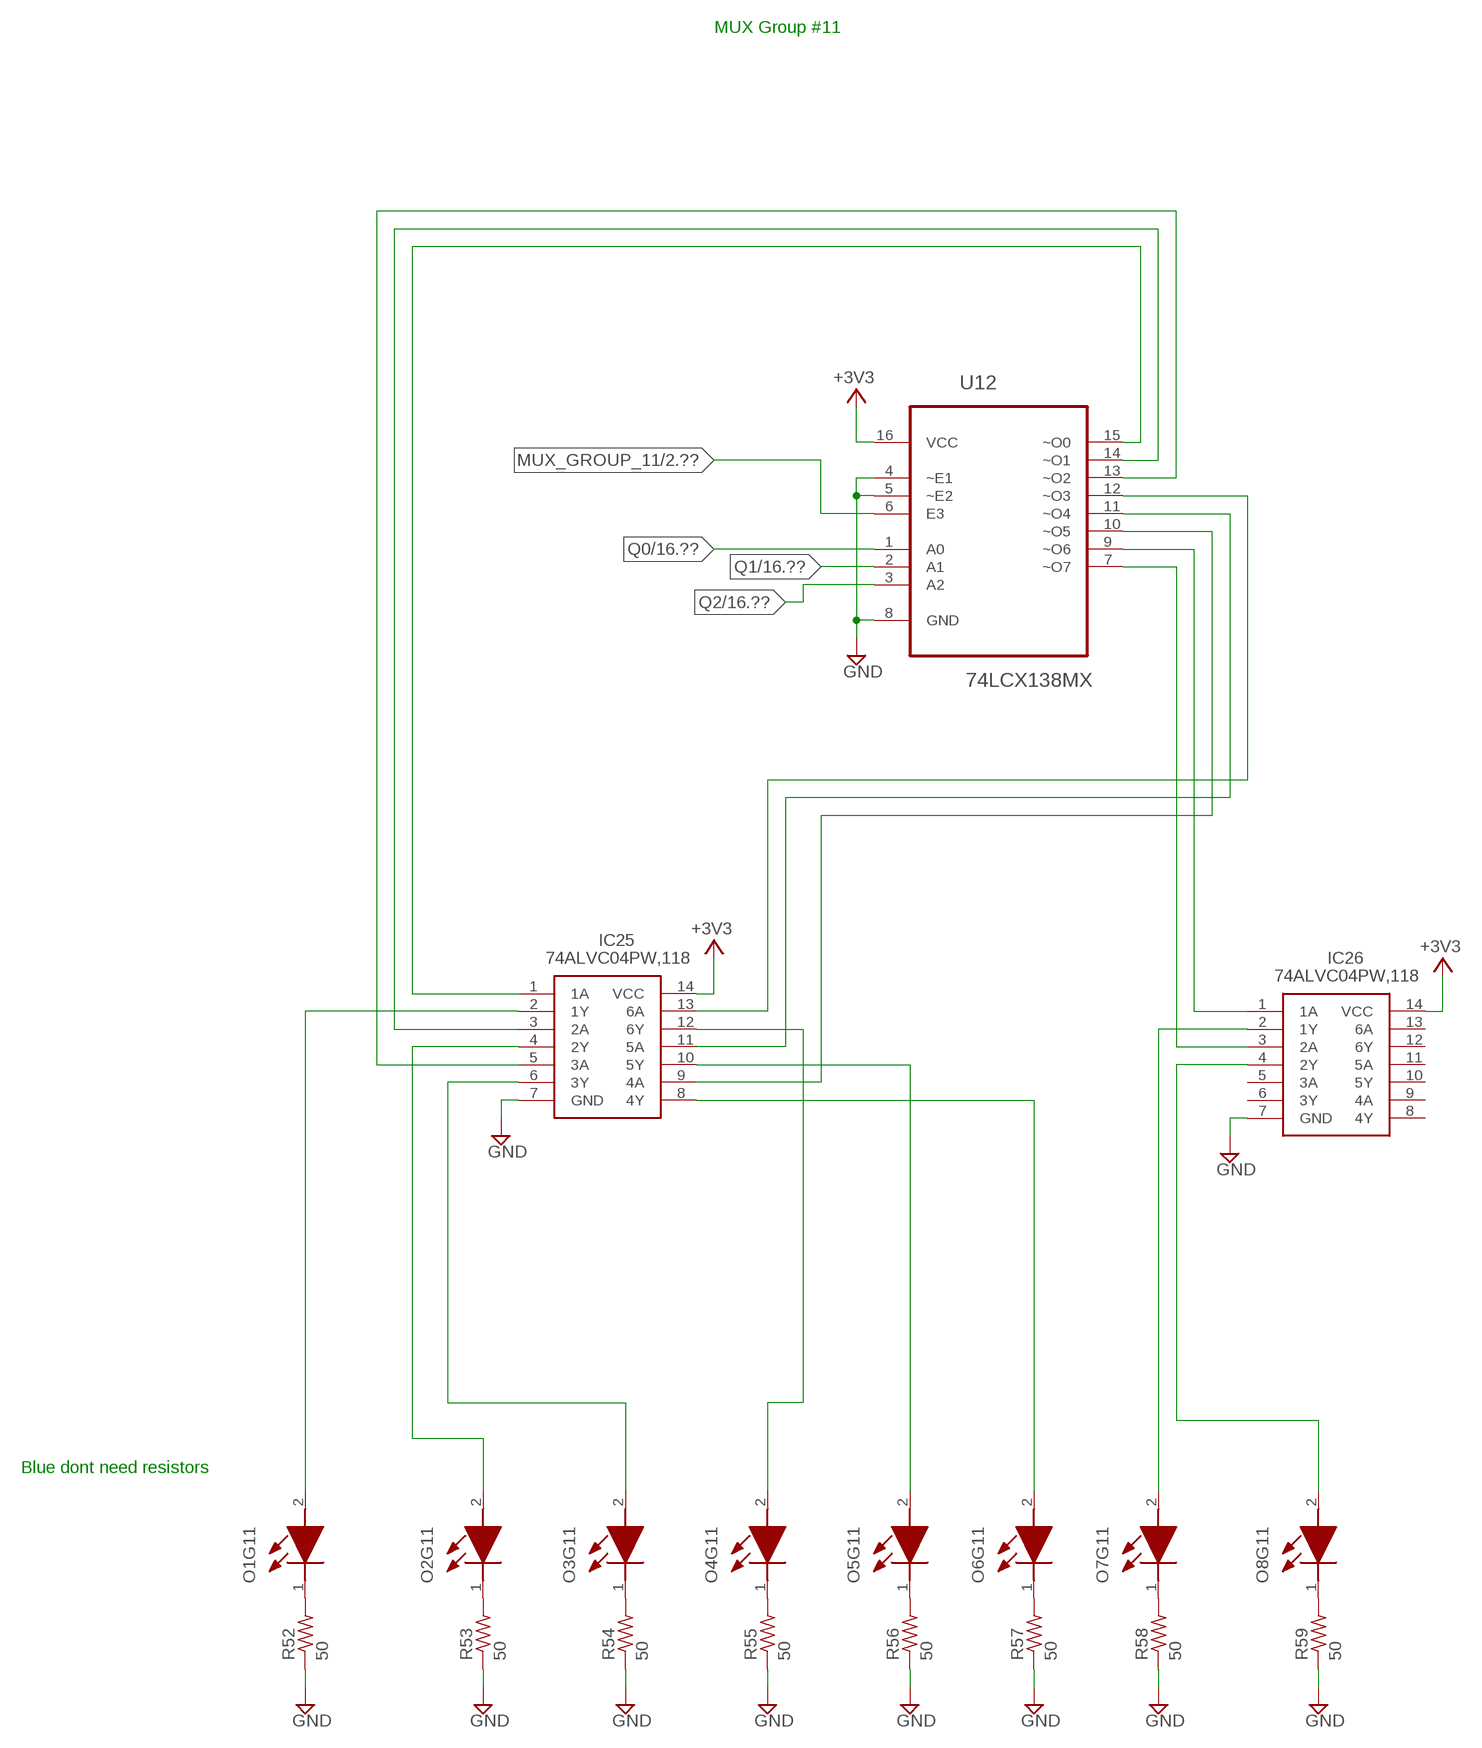
[diagram p14: schematic, sheet 15]
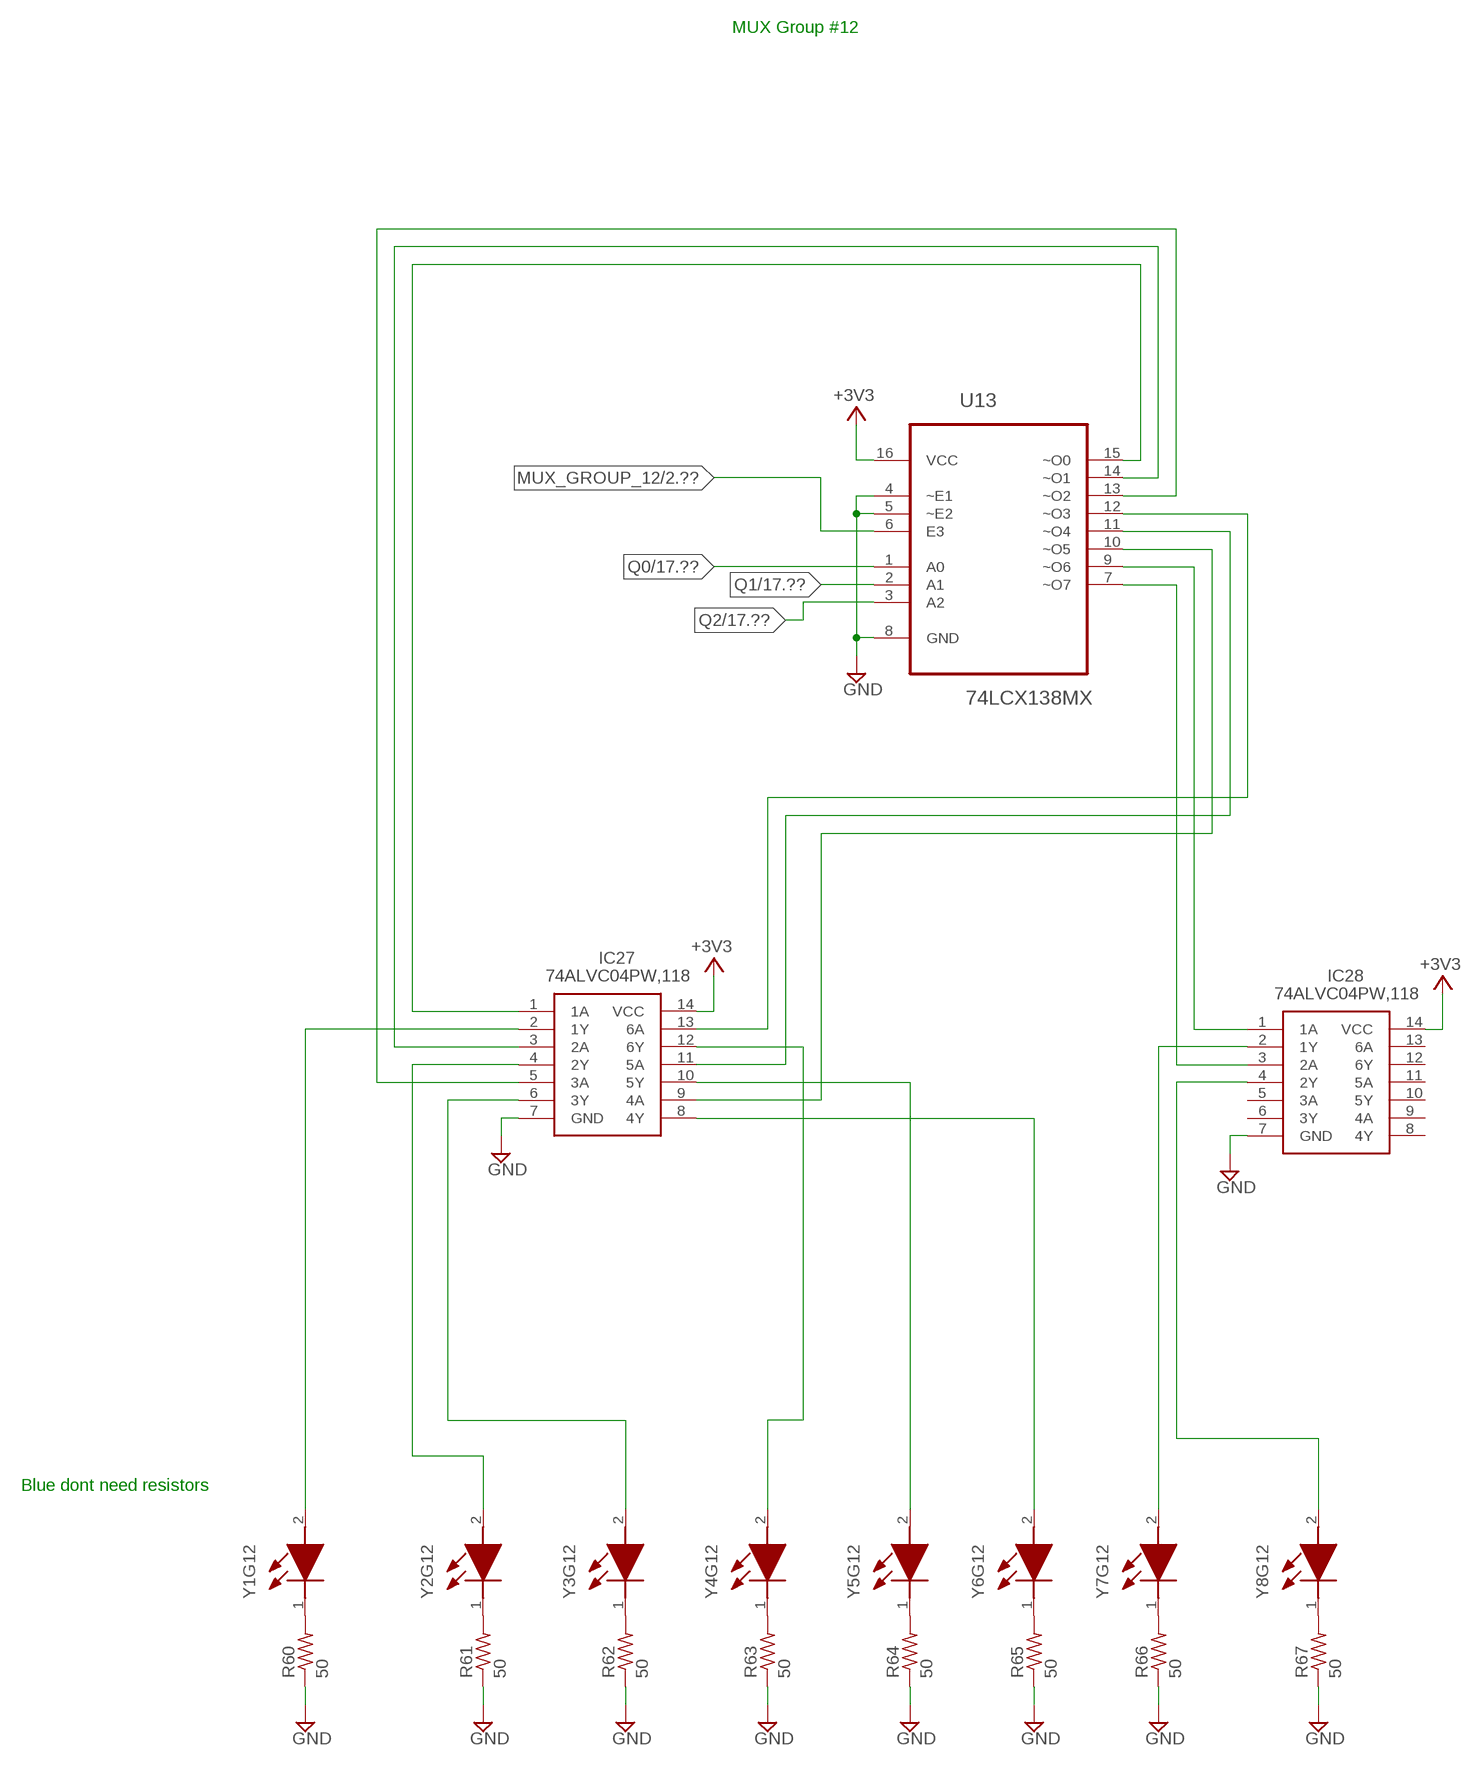
[diagram p15: schematic, sheet 16]
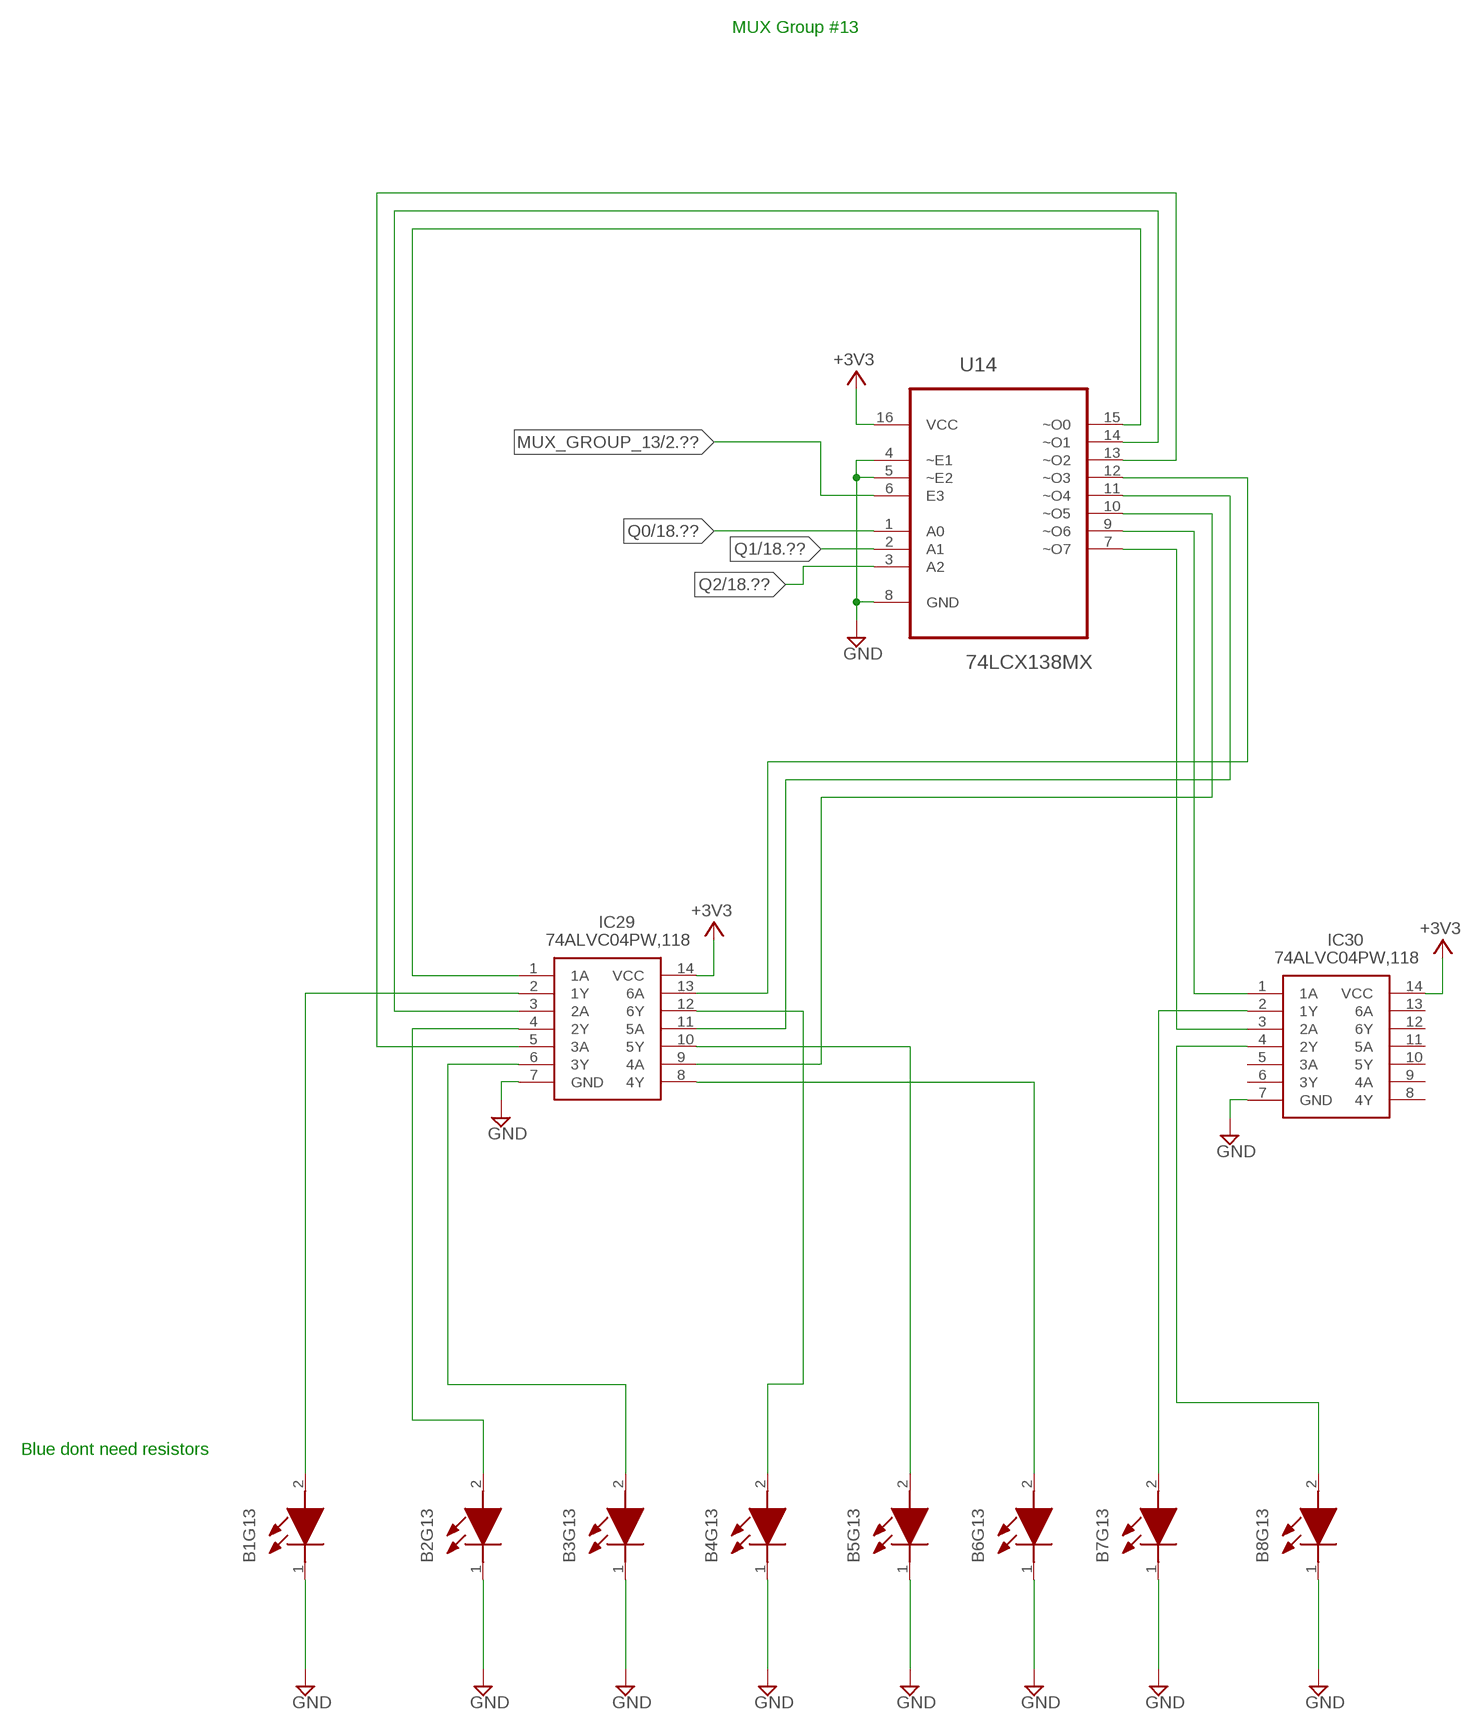
[diagram p16: schematic, sheet 17]
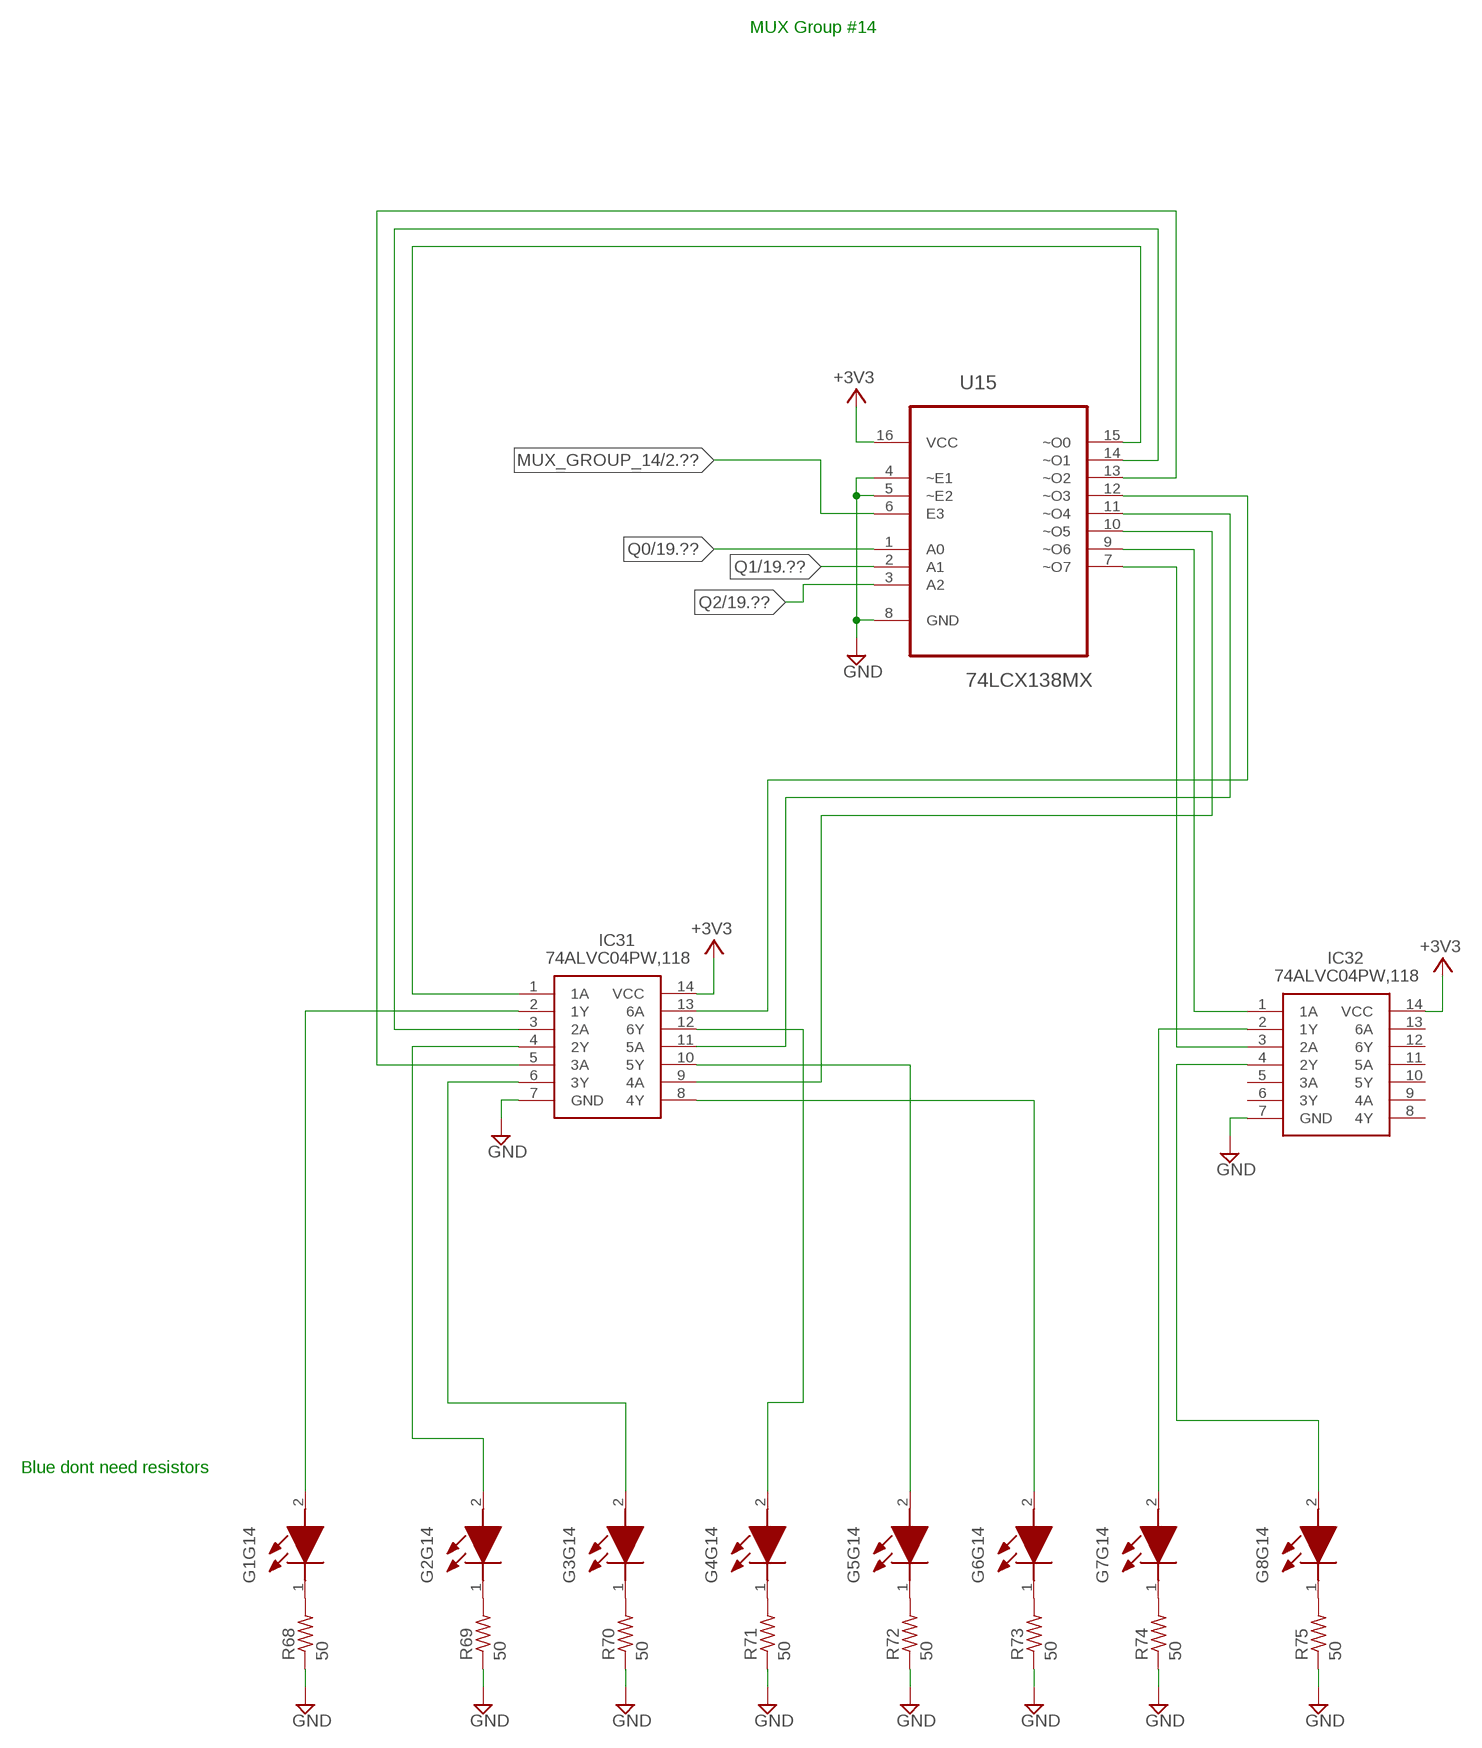
[diagram p17: schematic, sheet 18]
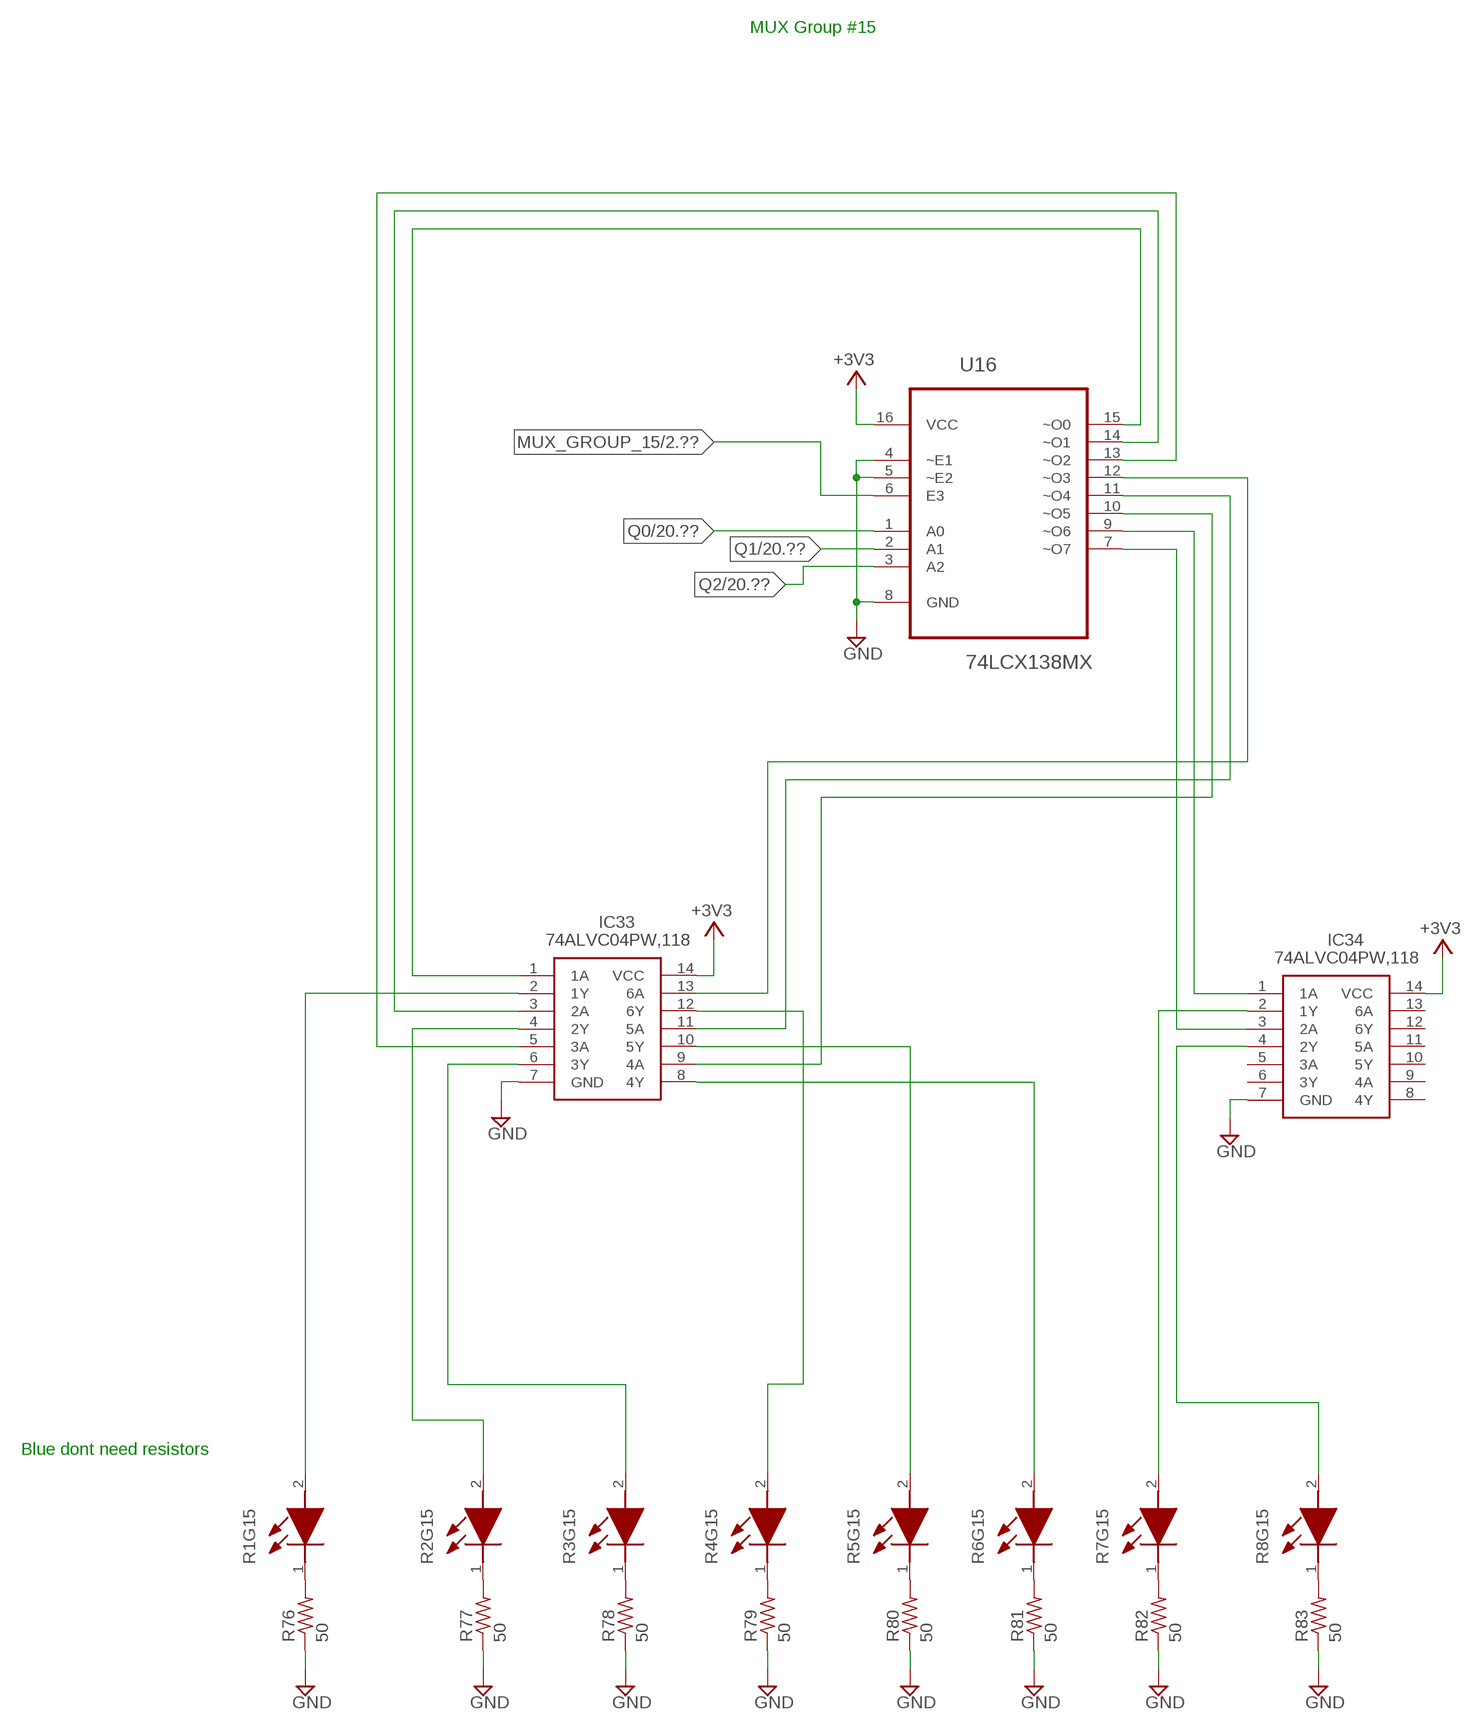
[diagram p18: schematic, sheet 19]
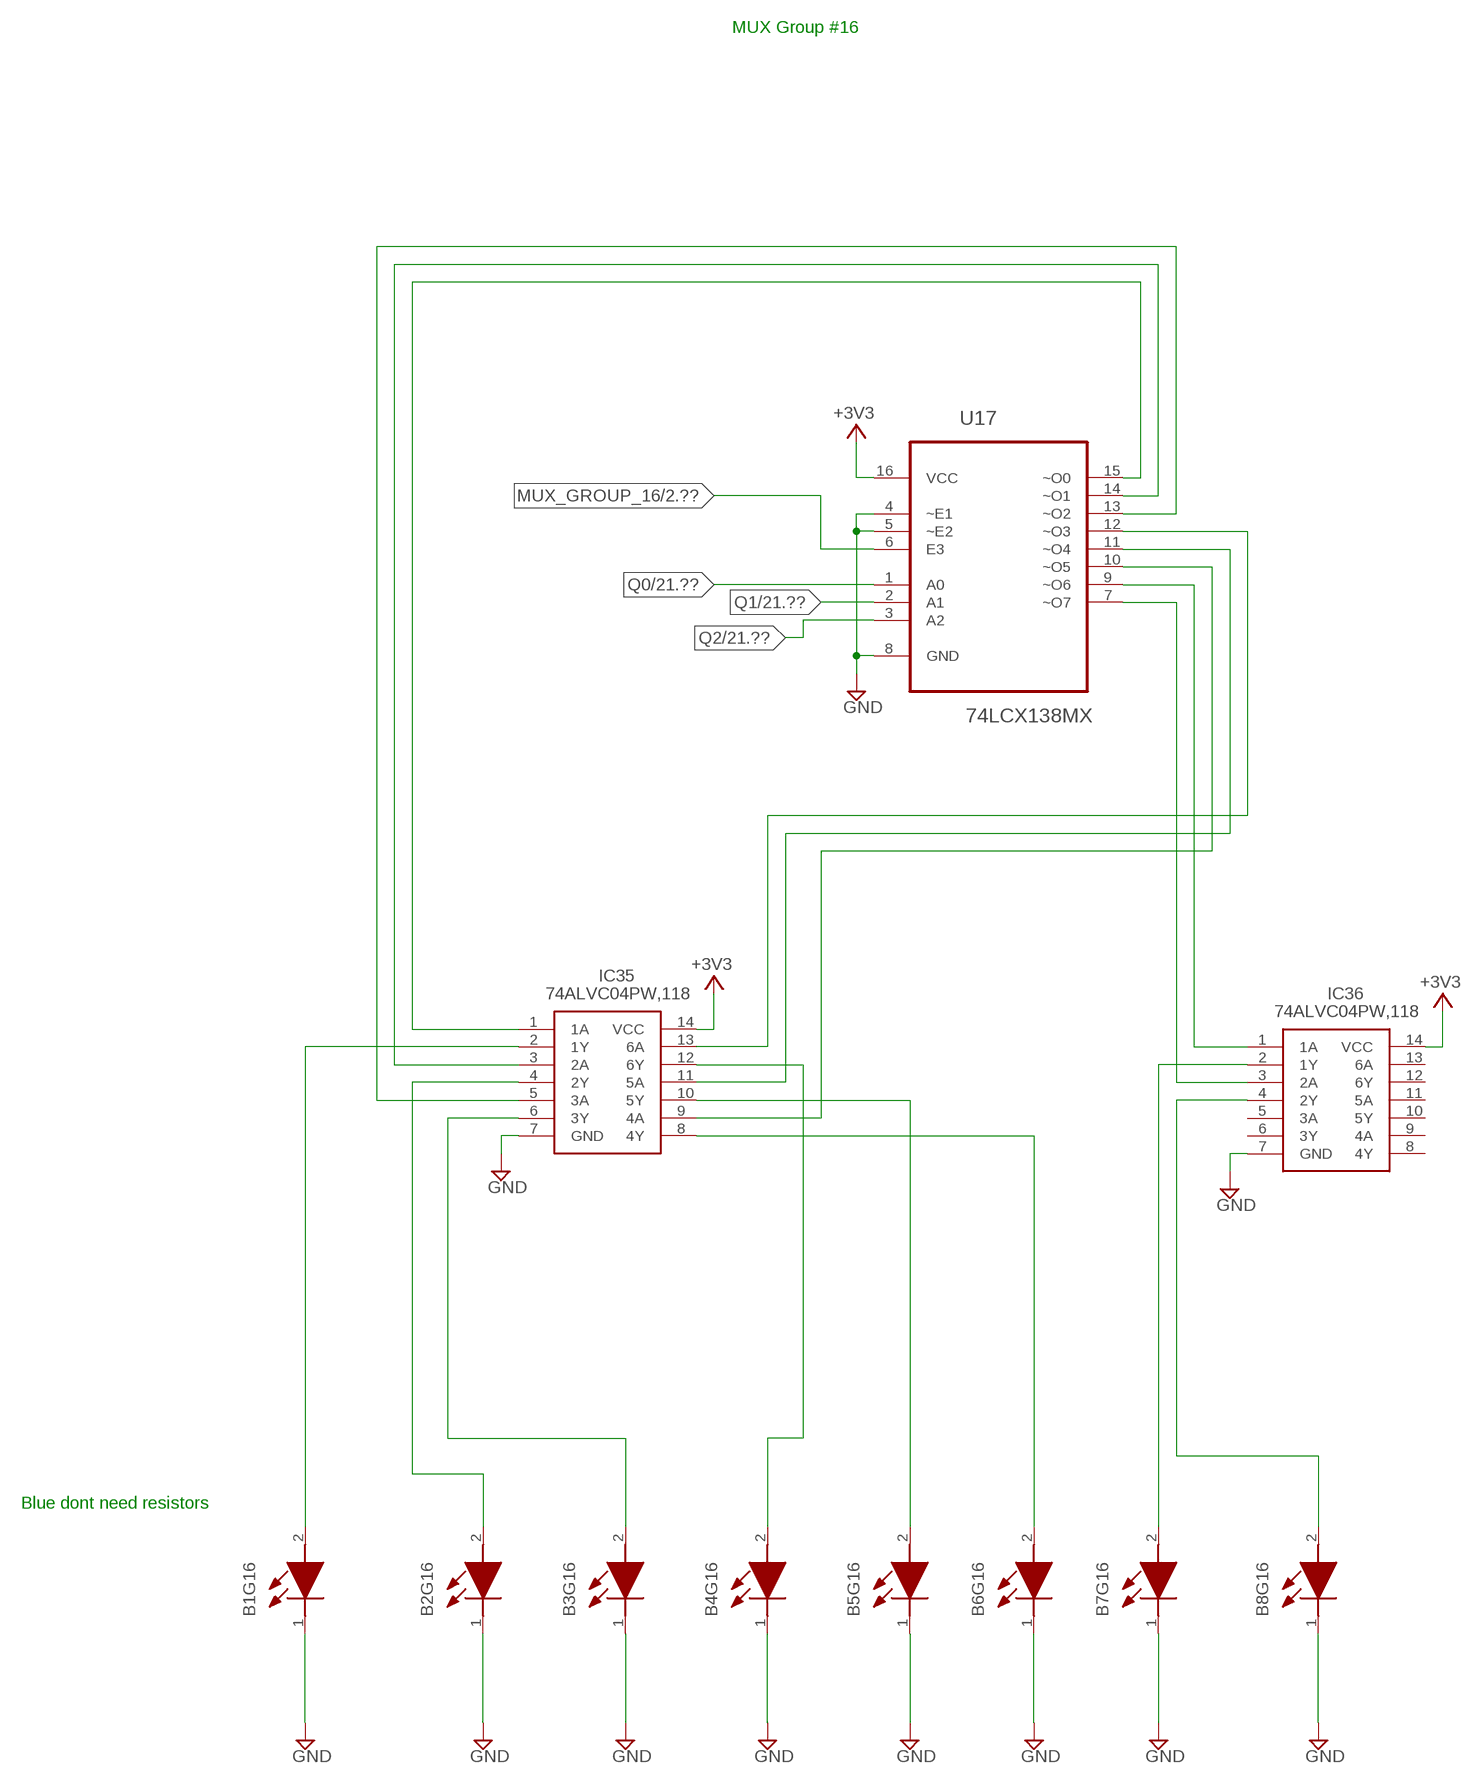
[diagram p19: schematic, sheet 20]
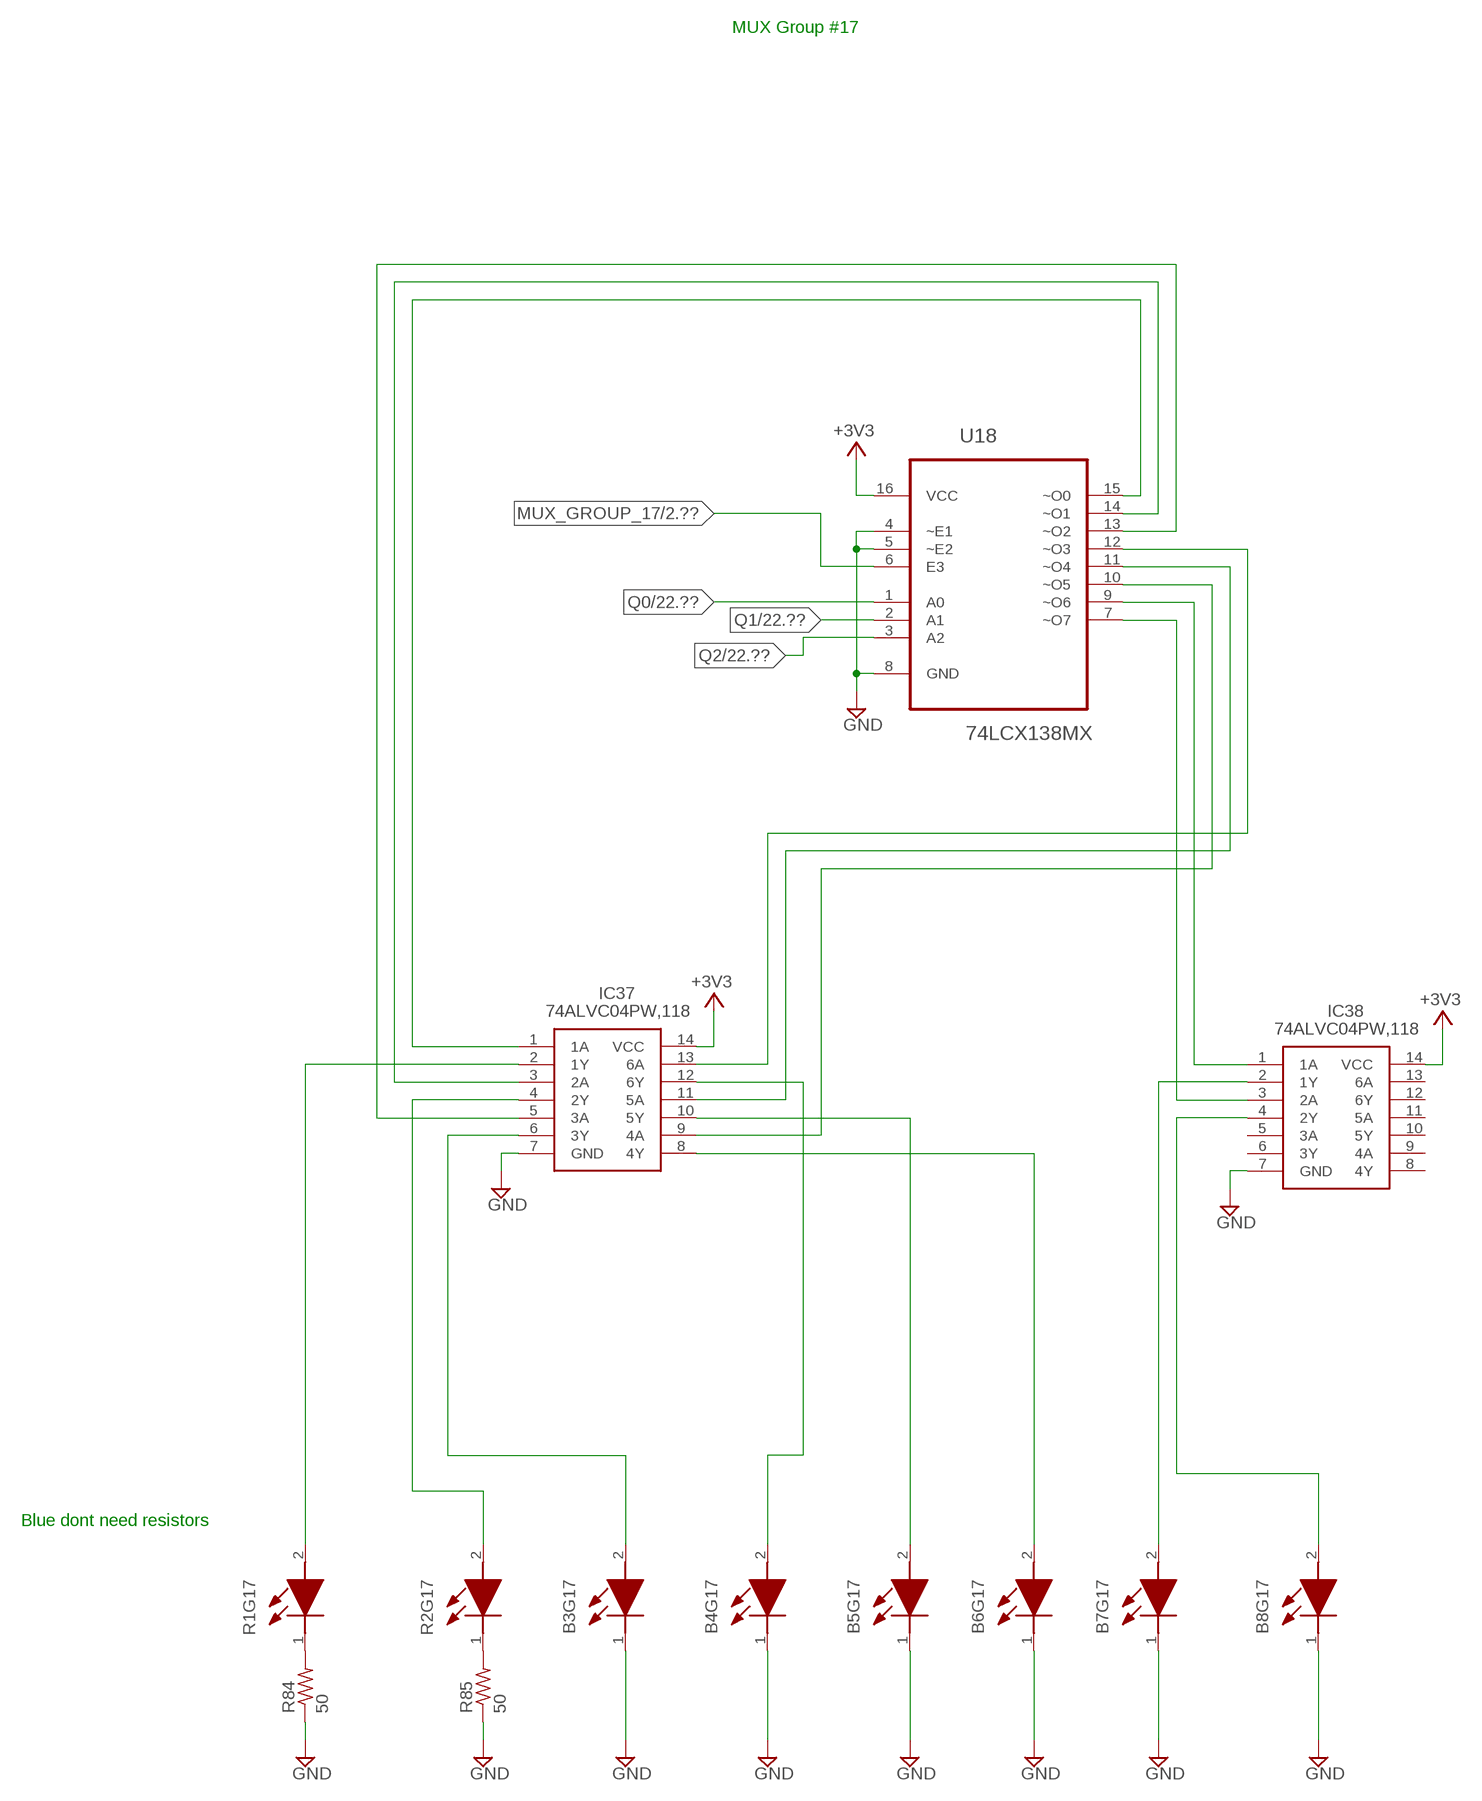
[diagram p20: schematic, sheet 21]
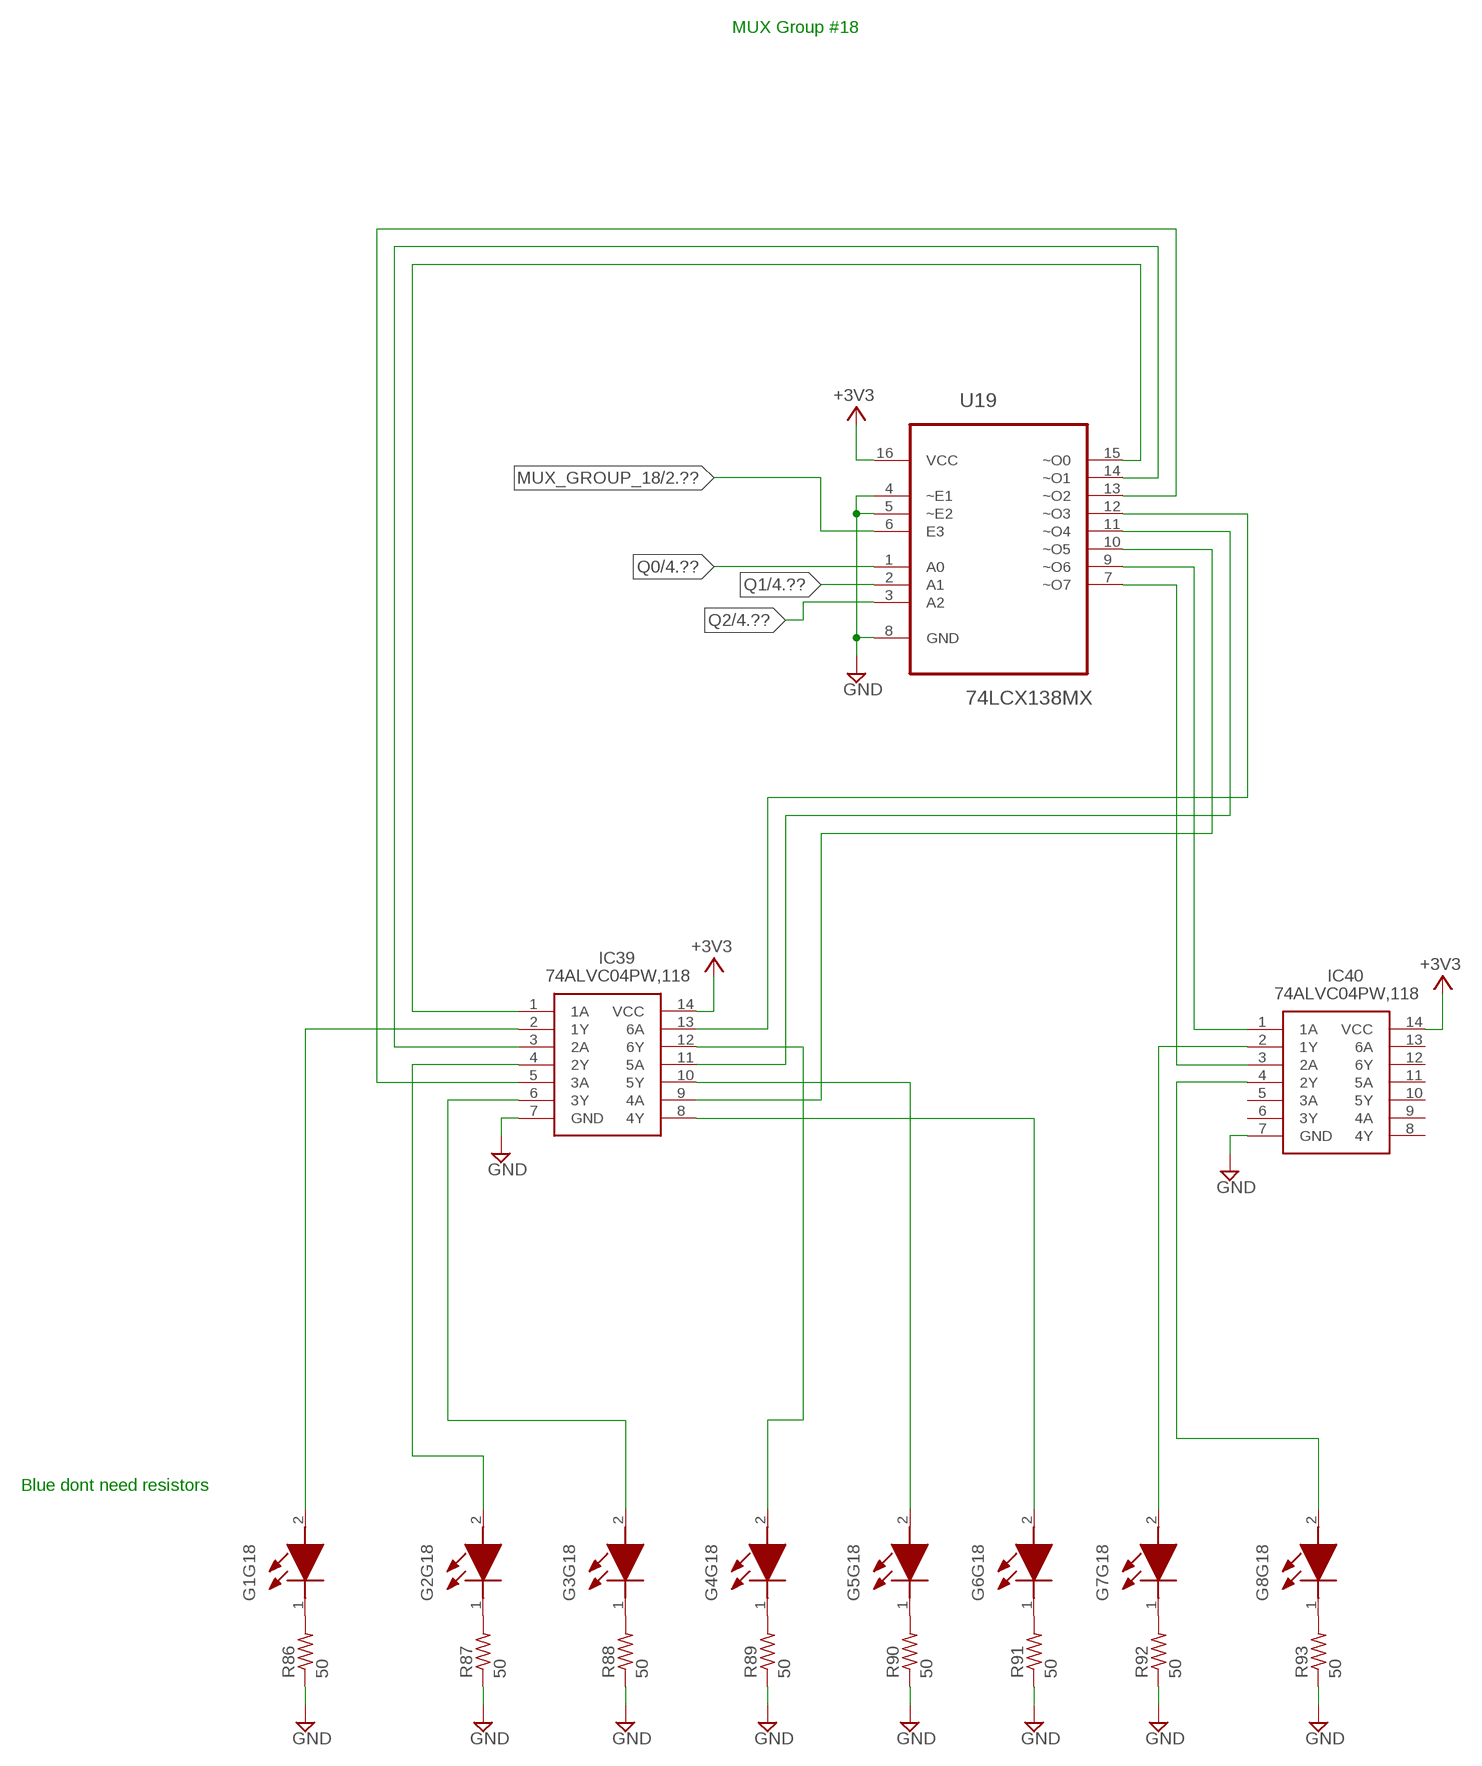
[diagram p21: schematic, sheet 22]

(export (version "E")
  (design (tool "Eeschema 10.0.6"))
  (components
    (comp (ref "B3G17")
      (value "LTST-C170TBKT")
      (footprint "eagle-import:LEDC2012X120N")
      (fields (field (name "MOUSER_PART_NUMBER") "859-LTST-C170TBKT"))
      (libsource (lib "eagle-import") (part "LTST-C170TBKT"))
    )
    (comp (ref "B4G17")
      (value "LTST-C170TBKT")
      (footprint "eagle-import:LEDC2012X120N")
      (fields (field (name "MOUSER_PART_NUMBER") "859-LTST-C170TBKT"))
      (libsource (lib "eagle-import") (part "LTST-C170TBKT"))
    )
    (comp (ref "B5G17")
      (value "LTST-C170TBKT")
      (footprint "eagle-import:LEDC2012X120N")
      (fields (field (name "MOUSER_PART_NUMBER") "859-LTST-C170TBKT"))
      (libsource (lib "eagle-import") (part "LTST-C170TBKT"))
    )
    (comp (ref "B6G17")
      (value "LTST-C170TBKT")
      (footprint "eagle-import:LEDC2012X120N")
      (fields (field (name "MOUSER_PART_NUMBER") "859-LTST-C170TBKT"))
      (libsource (lib "eagle-import") (part "LTST-C170TBKT"))
    )
    (comp (ref "B7G17")
      (value "LTST-C170TBKT")
      (footprint "eagle-import:LEDC2012X120N")
      (fields (field (name "MOUSER_PART_NUMBER") "859-LTST-C170TBKT"))
      (libsource (lib "eagle-import") (part "LTST-C170TBKT"))
    )
    (comp (ref "B8G17")
      (value "LTST-C170TBKT")
      (footprint "eagle-import:LEDC2012X120N")
      (fields (field (name "MOUSER_PART_NUMBER") "859-LTST-C170TBKT"))
      (libsource (lib "eagle-import") (part "LTST-C170TBKT"))
    )
    (comp (ref "IC37")
      (value "74ALVC04PW,118")
      (footprint "eagle-import:SOP65P640X110-14N")
      (fields (field (name "MOUSER_PART_NUMBER") "771-ALVC04PW118"))
      (libsource (lib "eagle-import") (part "74ALVC04PW,118"))
    )
    (comp (ref "IC38")
      (value "74ALVC04PW,118")
      (footprint "eagle-import:SOP65P640X110-14N")
      (fields (field (name "MOUSER_PART_NUMBER") "771-ALVC04PW118"))
      (libsource (lib "eagle-import") (part "74ALVC04PW,118"))
    )
    (comp (ref "R1G17")
      (value "LTST-C170TBKT")
      (footprint "eagle-import:LEDC2012X120N")
      (fields (field (name "MOUSER_PART_NUMBER") "859-LTST-C170TBKT"))
      (libsource (lib "eagle-import") (part "LTST-C170TBKT"))
    )
    (comp (ref "R2G17")
      (value "LTST-C170TBKT")
      (footprint "eagle-import:LEDC2012X120N")
      (fields (field (name "MOUSER_PART_NUMBER") "859-LTST-C170TBKT"))
      (libsource (lib "eagle-import") (part "LTST-C170TBKT"))
    )
    (comp (ref "R84")
      (value "50")
      (footprint "eagle-import:R0805")
      (libsource (lib "eagle-import") (part "R-US_R0805"))
    )
    (comp (ref "R85")
      (value "50")
      (footprint "eagle-import:R0805")
      (libsource (lib "eagle-import") (part "R-US_R0805"))
    )
    (comp (ref "U18")
      (value "74LCX138MX")
      (footprint "eagle-import:SOIC127P600X175-16N")
      (fields (field (name "DIGI-KEY_PART_NUMBER") "74LCX138MXCT-ND") (field (name "MF") "ON"))
      (libsource (lib "eagle-import") (part "74LCX138MX"))
    )
    (comp (ref "B1G2")
      (value "LTST-C170TBKT")
      (footprint "eagle-import:LEDC2012X120N")
      (fields (field (name "MOUSER_PART_NUMBER") "859-LTST-C170TBKT"))
      (libsource (lib "eagle-import") (part "LTST-C170TBKT"))
    )
    (comp (ref "B2G2")
      (value "LTST-C170TBKT")
      (footprint "eagle-import:LEDC2012X120N")
      (fields (field (name "MOUSER_PART_NUMBER") "859-LTST-C170TBKT"))
      (libsource (lib "eagle-import") (part "LTST-C170TBKT"))
    )
    (comp (ref "B3G2")
      (value "LTST-C170TBKT")
      (footprint "eagle-import:LEDC2012X120N")
      (fields (field (name "MOUSER_PART_NUMBER") "859-LTST-C170TBKT"))
      (libsource (lib "eagle-import") (part "LTST-C170TBKT"))
    )
    (comp (ref "B4G2")
      (value "LTST-C170TBKT")
      (footprint "eagle-import:LEDC2012X120N")
      (fields (field (name "MOUSER_PART_NUMBER") "859-LTST-C170TBKT"))
      (libsource (lib "eagle-import") (part "LTST-C170TBKT"))
    )
    (comp (ref "B5G2")
      (value "LTST-C170TBKT")
      (footprint "eagle-import:LEDC2012X120N")
      (fields (field (name "MOUSER_PART_NUMBER") "859-LTST-C170TBKT"))
      (libsource (lib "eagle-import") (part "LTST-C170TBKT"))
    )
    (comp (ref "B6G2")
      (value "LTST-C170TBKT")
      (footprint "eagle-import:LEDC2012X120N")
      (fields (field (name "MOUSER_PART_NUMBER") "859-LTST-C170TBKT"))
      (libsource (lib "eagle-import") (part "LTST-C170TBKT"))
    )
    (comp (ref "B7G2")
      (value "LTST-C170TBKT")
      (footprint "eagle-import:LEDC2012X120N")
      (fields (field (name "MOUSER_PART_NUMBER") "859-LTST-C170TBKT"))
      (libsource (lib "eagle-import") (part "LTST-C170TBKT"))
    )
    (comp (ref "IC7")
      (value "74ALVC04PW,118")
      (footprint "eagle-import:SOP65P640X110-14N")
      (fields (field (name "MOUSER_PART_NUMBER") "771-ALVC04PW118"))
      (libsource (lib "eagle-import") (part "74ALVC04PW,118"))
    )
    (comp (ref "IC8")
      (value "74ALVC04PW,118")
      (footprint "eagle-import:SOP65P640X110-14N")
      (fields (field (name "MOUSER_PART_NUMBER") "771-ALVC04PW118"))
      (libsource (lib "eagle-import") (part "74ALVC04PW,118"))
    )
    (comp (ref "U3")
      (value "74LCX138MX")
      (footprint "eagle-import:SOIC127P600X175-16N")
      (fields (field (name "DIGI-KEY_PART_NUMBER") "74LCX138MXCT-ND") (field (name "MF") "ON"))
      (libsource (lib "eagle-import") (part "74LCX138MX"))
    )
    (comp (ref "IC23")
      (value "74ALVC04PW,118")
      (footprint "eagle-import:SOP65P640X110-14N")
      (fields (field (name "MOUSER_PART_NUMBER") "771-ALVC04PW118"))
      (libsource (lib "eagle-import") (part "74ALVC04PW,118"))
    )
    (comp (ref "R46")
      (value "50")
      (footprint "eagle-import:R0805")
      (libsource (lib "eagle-import") (part "R-US_R0805"))
    )
    (comp (ref "R47")
      (value "50")
      (footprint "eagle-import:R0805")
      (libsource (lib "eagle-import") (part "R-US_R0805"))
    )
    (comp (ref "R48")
      (value "50")
      (footprint "eagle-import:R0805")
      (libsource (lib "eagle-import") (part "R-US_R0805"))
    )
    (comp (ref "R49")
      (value "50")
      (footprint "eagle-import:R0805")
      (libsource (lib "eagle-import") (part "R-US_R0805"))
    )
    (comp (ref "R50")
      (value "50")
      (footprint "eagle-import:R0805")
      (libsource (lib "eagle-import") (part "R-US_R0805"))
    )
    (comp (ref "U11")
      (value "74LCX138MX")
      (footprint "eagle-import:SOIC127P600X175-16N")
      (fields (field (name "DIGI-KEY_PART_NUMBER") "74LCX138MXCT-ND") (field (name "MF") "ON"))
      (libsource (lib "eagle-import") (part "74LCX138MX"))
    )
    (comp (ref "Y1G10")
      (value "LTST-C170TBKT")
      (footprint "eagle-import:LEDC2012X120N")
      (fields (field (name "MOUSER_PART_NUMBER") "859-LTST-C170TBKT"))
      (libsource (lib "eagle-import") (part "LTST-C170TBKT"))
    )
    (comp (ref "Y2G10")
      (value "LTST-C170TBKT")
      (footprint "eagle-import:LEDC2012X120N")
      (fields (field (name "MOUSER_PART_NUMBER") "859-LTST-C170TBKT"))
      (libsource (lib "eagle-import") (part "LTST-C170TBKT"))
    )
    (comp (ref "Y3G10")
      (value "LTST-C170TBKT")
      (footprint "eagle-import:LEDC2012X120N")
      (fields (field (name "MOUSER_PART_NUMBER") "859-LTST-C170TBKT"))
      (libsource (lib "eagle-import") (part "LTST-C170TBKT"))
    )
    (comp (ref "Y4G10")
      (value "LTST-C170TBKT")
      (footprint "eagle-import:LEDC2012X120N")
      (fields (field (name "MOUSER_PART_NUMBER") "859-LTST-C170TBKT"))
      (libsource (lib "eagle-import") (part "LTST-C170TBKT"))
    )
    (comp (ref "Y5G10")
      (value "LTST-C170TBKT")
      (footprint "eagle-import:LEDC2012X120N")
      (fields (field (name "MOUSER_PART_NUMBER") "859-LTST-C170TBKT"))
      (libsource (lib "eagle-import") (part "LTST-C170TBKT"))
    )
    (comp (ref "B1G4")
      (value "LTST-C170TBKT")
      (footprint "eagle-import:LEDC2012X120N")
      (fields (field (name "MOUSER_PART_NUMBER") "859-LTST-C170TBKT"))
      (libsource (lib "eagle-import") (part "LTST-C170TBKT"))
    )
    (comp (ref "B2G4")
      (value "LTST-C170TBKT")
      (footprint "eagle-import:LEDC2012X120N")
      (fields (field (name "MOUSER_PART_NUMBER") "859-LTST-C170TBKT"))
      (libsource (lib "eagle-import") (part "LTST-C170TBKT"))
    )
    (comp (ref "B3G4")
      (value "LTST-C170TBKT")
      (footprint "eagle-import:LEDC2012X120N")
      (fields (field (name "MOUSER_PART_NUMBER") "859-LTST-C170TBKT"))
      (libsource (lib "eagle-import") (part "LTST-C170TBKT"))
    )
    (comp (ref "B4G4")
      (value "LTST-C170TBKT")
      (footprint "eagle-import:LEDC2012X120N")
      (fields (field (name "MOUSER_PART_NUMBER") "859-LTST-C170TBKT"))
      (libsource (lib "eagle-import") (part "LTST-C170TBKT"))
    )
    (comp (ref "B5G4")
      (value "LTST-C170TBKT")
      (footprint "eagle-import:LEDC2012X120N")
      (fields (field (name "MOUSER_PART_NUMBER") "859-LTST-C170TBKT"))
      (libsource (lib "eagle-import") (part "LTST-C170TBKT"))
    )
    (comp (ref "B6G4")
      (value "LTST-C170TBKT")
      (footprint "eagle-import:LEDC2012X120N")
      (fields (field (name "MOUSER_PART_NUMBER") "859-LTST-C170TBKT"))
      (libsource (lib "eagle-import") (part "LTST-C170TBKT"))
    )
    (comp (ref "B7G4")
      (value "LTST-C170TBKT")
      (footprint "eagle-import:LEDC2012X120N")
      (fields (field (name "MOUSER_PART_NUMBER") "859-LTST-C170TBKT"))
      (libsource (lib "eagle-import") (part "LTST-C170TBKT"))
    )
    (comp (ref "B8G4")
      (value "LTST-C170TBKT")
      (footprint "eagle-import:LEDC2012X120N")
      (fields (field (name "MOUSER_PART_NUMBER") "859-LTST-C170TBKT"))
      (libsource (lib "eagle-import") (part "LTST-C170TBKT"))
    )
    (comp (ref "IC11")
      (value "74ALVC04PW,118")
      (footprint "eagle-import:SOP65P640X110-14N")
      (fields (field (name "MOUSER_PART_NUMBER") "771-ALVC04PW118"))
      (libsource (lib "eagle-import") (part "74ALVC04PW,118"))
    )
    (comp (ref "IC12")
      (value "74ALVC04PW,118")
      (footprint "eagle-import:SOP65P640X110-14N")
      (fields (field (name "MOUSER_PART_NUMBER") "771-ALVC04PW118"))
      (libsource (lib "eagle-import") (part "74ALVC04PW,118"))
    )
    (comp (ref "U5")
      (value "74LCX138MX")
      (footprint "eagle-import:SOIC127P600X175-16N")
      (fields (field (name "DIGI-KEY_PART_NUMBER") "74LCX138MXCT-ND") (field (name "MF") "ON"))
      (libsource (lib "eagle-import") (part "74LCX138MX"))
    )
    (comp (ref "G1G18")
      (value "LTST-C170TBKT")
      (footprint "eagle-import:LEDC2012X120N")
      (fields (field (name "MOUSER_PART_NUMBER") "859-LTST-C170TBKT"))
      (libsource (lib "eagle-import") (part "LTST-C170TBKT"))
    )
    (comp (ref "G2G18")
      (value "LTST-C170TBKT")
      (footprint "eagle-import:LEDC2012X120N")
      (fields (field (name "MOUSER_PART_NUMBER") "859-LTST-C170TBKT"))
      (libsource (lib "eagle-import") (part "LTST-C170TBKT"))
    )
    (comp (ref "G3G18")
      (value "LTST-C170TBKT")
      (footprint "eagle-import:LEDC2012X120N")
      (fields (field (name "MOUSER_PART_NUMBER") "859-LTST-C170TBKT"))
      (libsource (lib "eagle-import") (part "LTST-C170TBKT"))
    )
    (comp (ref "G4G18")
      (value "LTST-C170TBKT")
      (footprint "eagle-import:LEDC2012X120N")
      (fields (field (name "MOUSER_PART_NUMBER") "859-LTST-C170TBKT"))
      (libsource (lib "eagle-import") (part "LTST-C170TBKT"))
    )
    (comp (ref "G5G18")
      (value "LTST-C170TBKT")
      (footprint "eagle-import:LEDC2012X120N")
      (fields (field (name "MOUSER_PART_NUMBER") "859-LTST-C170TBKT"))
      (libsource (lib "eagle-import") (part "LTST-C170TBKT"))
    )
    (comp (ref "G6G18")
      (value "LTST-C170TBKT")
      (footprint "eagle-import:LEDC2012X120N")
      (fields (field (name "MOUSER_PART_NUMBER") "859-LTST-C170TBKT"))
      (libsource (lib "eagle-import") (part "LTST-C170TBKT"))
    )
    (comp (ref "G7G18")
      (value "LTST-C170TBKT")
      (footprint "eagle-import:LEDC2012X120N")
      (fields (field (name "MOUSER_PART_NUMBER") "859-LTST-C170TBKT"))
      (libsource (lib "eagle-import") (part "LTST-C170TBKT"))
    )
    (comp (ref "G8G18")
      (value "LTST-C170TBKT")
      (footprint "eagle-import:LEDC2012X120N")
      (fields (field (name "MOUSER_PART_NUMBER") "859-LTST-C170TBKT"))
      (libsource (lib "eagle-import") (part "LTST-C170TBKT"))
    )
    (comp (ref "IC39")
      (value "74ALVC04PW,118")
      (footprint "eagle-import:SOP65P640X110-14N")
      (fields (field (name "MOUSER_PART_NUMBER") "771-ALVC04PW118"))
      (libsource (lib "eagle-import") (part "74ALVC04PW,118"))
    )
    (comp (ref "IC40")
      (value "74ALVC04PW,118")
      (footprint "eagle-import:SOP65P640X110-14N")
      (fields (field (name "MOUSER_PART_NUMBER") "771-ALVC04PW118"))
      (libsource (lib "eagle-import") (part "74ALVC04PW,118"))
    )
    (comp (ref "R86")
      (value "50")
      (footprint "eagle-import:R0805")
      (libsource (lib "eagle-import") (part "R-US_R0805"))
    )
    (comp (ref "R87")
      (value "50")
      (footprint "eagle-import:R0805")
      (libsource (lib "eagle-import") (part "R-US_R0805"))
    )
    (comp (ref "R88")
      (value "50")
      (footprint "eagle-import:R0805")
      (libsource (lib "eagle-import") (part "R-US_R0805"))
    )
    (comp (ref "R89")
      (value "50")
      (footprint "eagle-import:R0805")
      (libsource (lib "eagle-import") (part "R-US_R0805"))
    )
    (comp (ref "R90")
      (value "50")
      (footprint "eagle-import:R0805")
      (libsource (lib "eagle-import") (part "R-US_R0805"))
    )
    (comp (ref "R91")
      (value "50")
      (footprint "eagle-import:R0805")
      (libsource (lib "eagle-import") (part "R-US_R0805"))
    )
    (comp (ref "R92")
      (value "50")
      (footprint "eagle-import:R0805")
      (libsource (lib "eagle-import") (part "R-US_R0805"))
    )
    (comp (ref "R93")
      (value "50")
      (footprint "eagle-import:R0805")
      (libsource (lib "eagle-import") (part "R-US_R0805"))
    )
    (comp (ref "U19")
      (value "74LCX138MX")
      (footprint "eagle-import:SOIC127P600X175-16N")
      (fields (field (name "DIGI-KEY_PART_NUMBER") "74LCX138MXCT-ND") (field (name "MF") "ON"))
      (libsource (lib "eagle-import") (part "74LCX138MX"))
    )
    (comp (ref "G1G7")
      (value "LTST-C170TBKT")
      (footprint "eagle-import:LEDC2012X120N")
      (fields (field (name "MOUSER_PART_NUMBER") "859-LTST-C170TBKT"))
      (libsource (lib "eagle-import") (part "LTST-C170TBKT"))
    )
    (comp (ref "G2G7")
      (value "LTST-C170TBKT")
      (footprint "eagle-import:LEDC2012X120N")
      (fields (field (name "MOUSER_PART_NUMBER") "859-LTST-C170TBKT"))
      (libsource (lib "eagle-import") (part "LTST-C170TBKT"))
    )
    (comp (ref "G3G7")
      (value "LTST-C170TBKT")
      (footprint "eagle-import:LEDC2012X120N")
      (fields (field (name "MOUSER_PART_NUMBER") "859-LTST-C170TBKT"))
      (libsource (lib "eagle-import") (part "LTST-C170TBKT"))
    )
    (comp (ref "G4G7")
      (value "LTST-C170TBKT")
      (footprint "eagle-import:LEDC2012X120N")
      (fields (field (name "MOUSER_PART_NUMBER") "859-LTST-C170TBKT"))
      (libsource (lib "eagle-import") (part "LTST-C170TBKT"))
    )
    (comp (ref "G7G7")
      (value "LTST-C170TBKT")
      (footprint "eagle-import:LEDC2012X120N")
      (fields (field (name "MOUSER_PART_NUMBER") "859-LTST-C170TBKT"))
      (libsource (lib "eagle-import") (part "LTST-C170TBKT"))
    )
    (comp (ref "IC17")
      (value "74ALVC04PW,118")
      (footprint "eagle-import:SOP65P640X110-14N")
      (fields (field (name "MOUSER_PART_NUMBER") "771-ALVC04PW118"))
      (libsource (lib "eagle-import") (part "74ALVC04PW,118"))
    )
    (comp (ref "IC18")
      (value "74ALVC04PW,118")
      (footprint "eagle-import:SOP65P640X110-14N")
      (fields (field (name "MOUSER_PART_NUMBER") "771-ALVC04PW118"))
      (libsource (lib "eagle-import") (part "74ALVC04PW,118"))
    )
    (comp (ref "O6G7")
      (value "LTST-C170TBKT")
      (footprint "eagle-import:LEDC2012X120N")
      (fields (field (name "MOUSER_PART_NUMBER") "859-LTST-C170TBKT"))
      (libsource (lib "eagle-import") (part "LTST-C170TBKT"))
    )
    (comp (ref "R22")
      (value "50")
      (footprint "eagle-import:R0805")
      (libsource (lib "eagle-import") (part "R-US_R0805"))
    )
    (comp (ref "R23")
      (value "50")
      (footprint "eagle-import:R0805")
      (libsource (lib "eagle-import") (part "R-US_R0805"))
    )
    (comp (ref "R24")
      (value "50")
      (footprint "eagle-import:R0805")
      (libsource (lib "eagle-import") (part "R-US_R0805"))
    )
    (comp (ref "R25")
      (value "50")
      (footprint "eagle-import:R0805")
      (libsource (lib "eagle-import") (part "R-US_R0805"))
    )
    (comp (ref "R26")
      (value "50")
      (footprint "eagle-import:R0805")
      (libsource (lib "eagle-import") (part "R-US_R0805"))
    )
    (comp (ref "R27")
      (value "50")
      (footprint "eagle-import:R0805")
      (libsource (lib "eagle-import") (part "R-US_R0805"))
    )
    (comp (ref "R28")
      (value "50")
      (footprint "eagle-import:R0805")
      (libsource (lib "eagle-import") (part "R-US_R0805"))
    )
    (comp (ref "R29")
      (value "50")
      (footprint "eagle-import:R0805")
      (libsource (lib "eagle-import") (part "R-US_R0805"))
    )
    (comp (ref "U8")
      (value "74LCX138MX")
      (footprint "eagle-import:SOIC127P600X175-16N")
      (fields (field (name "DIGI-KEY_PART_NUMBER") "74LCX138MXCT-ND") (field (name "MF") "ON"))
      (libsource (lib "eagle-import") (part "74LCX138MX"))
    )
    (comp (ref "Y5G7")
      (value "LTST-C170TBKT")
      (footprint "eagle-import:LEDC2012X120N")
      (fields (field (name "MOUSER_PART_NUMBER") "859-LTST-C170TBKT"))
      (libsource (lib "eagle-import") (part "LTST-C170TBKT"))
    )
    (comp (ref "Y8G7")
      (value "LTST-C170TBKT")
      (footprint "eagle-import:LEDC2012X120N")
      (fields (field (name "MOUSER_PART_NUMBER") "859-LTST-C170TBKT"))
      (libsource (lib "eagle-import") (part "LTST-C170TBKT"))
    )
    (comp (ref "IC27")
      (value "74ALVC04PW,118")
      (footprint "eagle-import:SOP65P640X110-14N")
      (fields (field (name "MOUSER_PART_NUMBER") "771-ALVC04PW118"))
      (libsource (lib "eagle-import") (part "74ALVC04PW,118"))
    )
    (comp (ref "IC28")
      (value "74ALVC04PW,118")
      (footprint "eagle-import:SOP65P640X110-14N")
      (fields (field (name "MOUSER_PART_NUMBER") "771-ALVC04PW118"))
      (libsource (lib "eagle-import") (part "74ALVC04PW,118"))
    )
    (comp (ref "R60")
      (value "50")
      (footprint "eagle-import:R0805")
      (libsource (lib "eagle-import") (part "R-US_R0805"))
    )
    (comp (ref "R61")
      (value "50")
      (footprint "eagle-import:R0805")
      (libsource (lib "eagle-import") (part "R-US_R0805"))
    )
    (comp (ref "R62")
      (value "50")
      (footprint "eagle-import:R0805")
      (libsource (lib "eagle-import") (part "R-US_R0805"))
    )
    (comp (ref "R63")
      (value "50")
      (footprint "eagle-import:R0805")
      (libsource (lib "eagle-import") (part "R-US_R0805"))
    )
    (comp (ref "R64")
      (value "50")
      (footprint "eagle-import:R0805")
      (libsource (lib "eagle-import") (part "R-US_R0805"))
    )
    (comp (ref "R65")
      (value "50")
      (footprint "eagle-import:R0805")
      (libsource (lib "eagle-import") (part "R-US_R0805"))
    )
    (comp (ref "R66")
      (value "50")
      (footprint "eagle-import:R0805")
      (libsource (lib "eagle-import") (part "R-US_R0805"))
    )
    (comp (ref "R67")
      (value "50")
      (footprint "eagle-import:R0805")
      (libsource (lib "eagle-import") (part "R-US_R0805"))
    )
    (comp (ref "U13")
      (value "74LCX138MX")
      (footprint "eagle-import:SOIC127P600X175-16N")
      (fields (field (name "DIGI-KEY_PART_NUMBER") "74LCX138MXCT-ND") (field (name "MF") "ON"))
      (libsource (lib "eagle-import") (part "74LCX138MX"))
    )
    (comp (ref "Y1G12")
      (value "LTST-C170TBKT")
      (footprint "eagle-import:LEDC2012X120N")
      (fields (field (name "MOUSER_PART_NUMBER") "859-LTST-C170TBKT"))
      (libsource (lib "eagle-import") (part "LTST-C170TBKT"))
    )
    (comp (ref "Y2G12")
      (value "LTST-C170TBKT")
      (footprint "eagle-import:LEDC2012X120N")
      (fields (field (name "MOUSER_PART_NUMBER") "859-LTST-C170TBKT"))
      (libsource (lib "eagle-import") (part "LTST-C170TBKT"))
    )
    (comp (ref "Y3G12")
      (value "LTST-C170TBKT")
      (footprint "eagle-import:LEDC2012X120N")
      (fields (field (name "MOUSER_PART_NUMBER") "859-LTST-C170TBKT"))
      (libsource (lib "eagle-import") (part "LTST-C170TBKT"))
    )
    (comp (ref "Y4G12")
      (value "LTST-C170TBKT")
      (footprint "eagle-import:LEDC2012X120N")
      (fields (field (name "MOUSER_PART_NUMBER") "859-LTST-C170TBKT"))
      (libsource (lib "eagle-import") (part "LTST-C170TBKT"))
    )
    (comp (ref "Y5G12")
      (value "LTST-C170TBKT")
      (footprint "eagle-import:LEDC2012X120N")
      (fields (field (name "MOUSER_PART_NUMBER") "859-LTST-C170TBKT"))
      (libsource (lib "eagle-import") (part "LTST-C170TBKT"))
    )
    (comp (ref "Y6G12")
      (value "LTST-C170TBKT")
      (footprint "eagle-import:LEDC2012X120N")
      (fields (field (name "MOUSER_PART_NUMBER") "859-LTST-C170TBKT"))
      (libsource (lib "eagle-import") (part "LTST-C170TBKT"))
    )
    (comp (ref "Y7G12")
      (value "LTST-C170TBKT")
      (footprint "eagle-import:LEDC2012X120N")
      (fields (field (name "MOUSER_PART_NUMBER") "859-LTST-C170TBKT"))
      (libsource (lib "eagle-import") (part "LTST-C170TBKT"))
    )
    (comp (ref "Y8G12")
      (value "LTST-C170TBKT")
      (footprint "eagle-import:LEDC2012X120N")
      (fields (field (name "MOUSER_PART_NUMBER") "859-LTST-C170TBKT"))
      (libsource (lib "eagle-import") (part "LTST-C170TBKT"))
    )
    (comp (ref "B1G1")
      (value "LTST-C170TBKT")
      (footprint "eagle-import:LEDC2012X120N")
      (fields (field (name "MOUSER_PART_NUMBER") "859-LTST-C170TBKT"))
      (libsource (lib "eagle-import") (part "LTST-C170TBKT"))
    )
    (comp (ref "B2G1")
      (value "LTST-C170TBKT")
      (footprint "eagle-import:LEDC2012X120N")
      (fields (field (name "MOUSER_PART_NUMBER") "859-LTST-C170TBKT"))
      (libsource (lib "eagle-import") (part "LTST-C170TBKT"))
    )
    (comp (ref "B3G1")
      (value "LTST-C170TBKT")
      (footprint "eagle-import:LEDC2012X120N")
      (fields (field (name "MOUSER_PART_NUMBER") "859-LTST-C170TBKT"))
      (libsource (lib "eagle-import") (part "LTST-C170TBKT"))
    )
    (comp (ref "B4G1")
      (value "LTST-C170TBKT")
      (footprint "eagle-import:LEDC2012X120N")
      (fields (field (name "MOUSER_PART_NUMBER") "859-LTST-C170TBKT"))
      (libsource (lib "eagle-import") (part "LTST-C170TBKT"))
    )
    (comp (ref "B5G1")
      (value "LTST-C170TBKT")
      (footprint "eagle-import:LEDC2012X120N")
      (fields (field (name "MOUSER_PART_NUMBER") "859-LTST-C170TBKT"))
      (libsource (lib "eagle-import") (part "LTST-C170TBKT"))
    )
    (comp (ref "B6G1")
      (value "LTST-C170TBKT")
      (footprint "eagle-import:LEDC2012X120N")
      (fields (field (name "MOUSER_PART_NUMBER") "859-LTST-C170TBKT"))
      (libsource (lib "eagle-import") (part "LTST-C170TBKT"))
    )
    (comp (ref "B7G1")
      (value "LTST-C170TBKT")
      (footprint "eagle-import:LEDC2012X120N")
      (fields (field (name "MOUSER_PART_NUMBER") "859-LTST-C170TBKT"))
      (libsource (lib "eagle-import") (part "LTST-C170TBKT"))
    )
    (comp (ref "B8G1")
      (value "LTST-C170TBKT")
      (footprint "eagle-import:LEDC2012X120N")
      (fields (field (name "MOUSER_PART_NUMBER") "859-LTST-C170TBKT"))
      (libsource (lib "eagle-import") (part "LTST-C170TBKT"))
    )
    (comp (ref "IC5")
      (value "74ALVC04PW,118")
      (footprint "eagle-import:SOP65P640X110-14N")
      (fields (field (name "MOUSER_PART_NUMBER") "771-ALVC04PW118"))
      (libsource (lib "eagle-import") (part "74ALVC04PW,118"))
    )
    (comp (ref "IC6")
      (value "74ALVC04PW,118")
      (footprint "eagle-import:SOP65P640X110-14N")
      (fields (field (name "MOUSER_PART_NUMBER") "771-ALVC04PW118"))
      (libsource (lib "eagle-import") (part "74ALVC04PW,118"))
    )
    (comp (ref "U2")
      (value "74LCX138MX")
      (footprint "eagle-import:SOIC127P600X175-16N")
      (fields (field (name "DIGI-KEY_PART_NUMBER") "74LCX138MXCT-ND") (field (name "MF") "ON"))
      (libsource (lib "eagle-import") (part "74LCX138MX"))
    )
    (comp (ref "B1G16")
      (value "LTST-C170TBKT")
      (footprint "eagle-import:LEDC2012X120N")
      (fields (field (name "MOUSER_PART_NUMBER") "859-LTST-C170TBKT"))
      (libsource (lib "eagle-import") (part "LTST-C170TBKT"))
    )
    (comp (ref "B2G16")
      (value "LTST-C170TBKT")
      (footprint "eagle-import:LEDC2012X120N")
      (fields (field (name "MOUSER_PART_NUMBER") "859-LTST-C170TBKT"))
      (libsource (lib "eagle-import") (part "LTST-C170TBKT"))
    )
    (comp (ref "B3G16")
      (value "LTST-C170TBKT")
      (footprint "eagle-import:LEDC2012X120N")
      (fields (field (name "MOUSER_PART_NUMBER") "859-LTST-C170TBKT"))
      (libsource (lib "eagle-import") (part "LTST-C170TBKT"))
    )
    (comp (ref "B4G16")
      (value "LTST-C170TBKT")
      (footprint "eagle-import:LEDC2012X120N")
      (fields (field (name "MOUSER_PART_NUMBER") "859-LTST-C170TBKT"))
      (libsource (lib "eagle-import") (part "LTST-C170TBKT"))
    )
    (comp (ref "B5G16")
      (value "LTST-C170TBKT")
      (footprint "eagle-import:LEDC2012X120N")
      (fields (field (name "MOUSER_PART_NUMBER") "859-LTST-C170TBKT"))
      (libsource (lib "eagle-import") (part "LTST-C170TBKT"))
    )
    (comp (ref "B6G16")
      (value "LTST-C170TBKT")
      (footprint "eagle-import:LEDC2012X120N")
      (fields (field (name "MOUSER_PART_NUMBER") "859-LTST-C170TBKT"))
      (libsource (lib "eagle-import") (part "LTST-C170TBKT"))
    )
    (comp (ref "B7G16")
      (value "LTST-C170TBKT")
      (footprint "eagle-import:LEDC2012X120N")
      (fields (field (name "MOUSER_PART_NUMBER") "859-LTST-C170TBKT"))
      (libsource (lib "eagle-import") (part "LTST-C170TBKT"))
    )
    (comp (ref "B8G16")
      (value "LTST-C170TBKT")
      (footprint "eagle-import:LEDC2012X120N")
      (fields (field (name "MOUSER_PART_NUMBER") "859-LTST-C170TBKT"))
      (libsource (lib "eagle-import") (part "LTST-C170TBKT"))
    )
    (comp (ref "IC35")
      (value "74ALVC04PW,118")
      (footprint "eagle-import:SOP65P640X110-14N")
      (fields (field (name "MOUSER_PART_NUMBER") "771-ALVC04PW118"))
      (libsource (lib "eagle-import") (part "74ALVC04PW,118"))
    )
    (comp (ref "IC36")
      (value "74ALVC04PW,118")
      (footprint "eagle-import:SOP65P640X110-14N")
      (fields (field (name "MOUSER_PART_NUMBER") "771-ALVC04PW118"))
      (libsource (lib "eagle-import") (part "74ALVC04PW,118"))
    )
    (comp (ref "U17")
      (value "74LCX138MX")
      (footprint "eagle-import:SOIC127P600X175-16N")
      (fields (field (name "DIGI-KEY_PART_NUMBER") "74LCX138MXCT-ND") (field (name "MF") "ON"))
      (libsource (lib "eagle-import") (part "74LCX138MX"))
    )
    (comp (ref "G1G8")
      (value "LTST-C170TBKT")
      (footprint "eagle-import:LEDC2012X120N")
      (fields (field (name "MOUSER_PART_NUMBER") "859-LTST-C170TBKT"))
      (libsource (lib "eagle-import") (part "LTST-C170TBKT"))
    )
    (comp (ref "G2G8")
      (value "LTST-C170TBKT")
      (footprint "eagle-import:LEDC2012X120N")
      (fields (field (name "MOUSER_PART_NUMBER") "859-LTST-C170TBKT"))
      (libsource (lib "eagle-import") (part "LTST-C170TBKT"))
    )
    (comp (ref "G3G8")
      (value "LTST-C170TBKT")
      (footprint "eagle-import:LEDC2012X120N")
      (fields (field (name "MOUSER_PART_NUMBER") "859-LTST-C170TBKT"))
      (libsource (lib "eagle-import") (part "LTST-C170TBKT"))
    )
    (comp (ref "G4G8")
      (value "LTST-C170TBKT")
      (footprint "eagle-import:LEDC2012X120N")
      (fields (field (name "MOUSER_PART_NUMBER") "859-LTST-C170TBKT"))
      (libsource (lib "eagle-import") (part "LTST-C170TBKT"))
    )
    (comp (ref "G5G8")
      (value "LTST-C170TBKT")
      (footprint "eagle-import:LEDC2012X120N")
      (fields (field (name "MOUSER_PART_NUMBER") "859-LTST-C170TBKT"))
      (libsource (lib "eagle-import") (part "LTST-C170TBKT"))
    )
    (comp (ref "G7G8")
      (value "LTST-C170TBKT")
      (footprint "eagle-import:LEDC2012X120N")
      (fields (field (name "MOUSER_PART_NUMBER") "859-LTST-C170TBKT"))
      (libsource (lib "eagle-import") (part "LTST-C170TBKT"))
    )
    (comp (ref "IC19")
      (value "74ALVC04PW,118")
      (footprint "eagle-import:SOP65P640X110-14N")
      (fields (field (name "MOUSER_PART_NUMBER") "771-ALVC04PW118"))
      (libsource (lib "eagle-import") (part "74ALVC04PW,118"))
    )
    (comp (ref "IC20")
      (value "74ALVC04PW,118")
      (footprint "eagle-import:SOP65P640X110-14N")
      (fields (field (name "MOUSER_PART_NUMBER") "771-ALVC04PW118"))
      (libsource (lib "eagle-import") (part "74ALVC04PW,118"))
    )
    (comp (ref "R30")
      (value "50")
      (footprint "eagle-import:R0805")
      (libsource (lib "eagle-import") (part "R-US_R0805"))
    )
    (comp (ref "R31")
      (value "50")
      (footprint "eagle-import:R0805")
      (libsource (lib "eagle-import") (part "R-US_R0805"))
    )
    (comp (ref "R32")
      (value "50")
      (footprint "eagle-import:R0805")
      (libsource (lib "eagle-import") (part "R-US_R0805"))
    )
    (comp (ref "R33")
      (value "50")
      (footprint "eagle-import:R0805")
      (libsource (lib "eagle-import") (part "R-US_R0805"))
    )
    (comp (ref "R34")
      (value "50")
      (footprint "eagle-import:R0805")
      (libsource (lib "eagle-import") (part "R-US_R0805"))
    )
    (comp (ref "R35")
      (value "50")
      (footprint "eagle-import:R0805")
      (libsource (lib "eagle-import") (part "R-US_R0805"))
    )
    (comp (ref "R36")
      (value "50")
      (footprint "eagle-import:R0805")
      (libsource (lib "eagle-import") (part "R-US_R0805"))
    )
    (comp (ref "R37")
      (value "50")
      (footprint "eagle-import:R0805")
      (libsource (lib "eagle-import") (part "R-US_R0805"))
    )
    (comp (ref "U9")
      (value "74LCX138MX")
      (footprint "eagle-import:SOIC127P600X175-16N")
      (fields (field (name "DIGI-KEY_PART_NUMBER") "74LCX138MXCT-ND") (field (name "MF") "ON"))
      (libsource (lib "eagle-import") (part "74LCX138MX"))
    )
    (comp (ref "Y6G8")
      (value "LTST-C170TBKT")
      (footprint "eagle-import:LEDC2012X120N")
      (fields (field (name "MOUSER_PART_NUMBER") "859-LTST-C170TBKT"))
      (libsource (lib "eagle-import") (part "LTST-C170TBKT"))
    )
    (comp (ref "Y8G8")
      (value "LTST-C170TBKT")
      (footprint "eagle-import:LEDC2012X120N")
      (fields (field (name "MOUSER_PART_NUMBER") "859-LTST-C170TBKT"))
      (libsource (lib "eagle-import") (part "LTST-C170TBKT"))
    )
    (comp (ref "B1G5")
      (value "LTST-C170TBKT")
      (footprint "eagle-import:LEDC2012X120N")
      (fields (field (name "MOUSER_PART_NUMBER") "859-LTST-C170TBKT"))
      (libsource (lib "eagle-import") (part "LTST-C170TBKT"))
    )
    (comp (ref "B2G5")
      (value "LTST-C170TBKT")
      (footprint "eagle-import:LEDC2012X120N")
      (fields (field (name "MOUSER_PART_NUMBER") "859-LTST-C170TBKT"))
      (libsource (lib "eagle-import") (part "LTST-C170TBKT"))
    )
    (comp (ref "B3G5")
      (value "LTST-C170TBKT")
      (footprint "eagle-import:LEDC2012X120N")
      (fields (field (name "MOUSER_PART_NUMBER") "859-LTST-C170TBKT"))
      (libsource (lib "eagle-import") (part "LTST-C170TBKT"))
    )
    (comp (ref "B4G5")
      (value "LTST-C170TBKT")
      (footprint "eagle-import:LEDC2012X120N")
      (fields (field (name "MOUSER_PART_NUMBER") "859-LTST-C170TBKT"))
      (libsource (lib "eagle-import") (part "LTST-C170TBKT"))
    )
    (comp (ref "G6G5")
      (value "LTST-C170TBKT")
      (footprint "eagle-import:LEDC2012X120N")
      (fields (field (name "MOUSER_PART_NUMBER") "859-LTST-C170TBKT"))
      (libsource (lib "eagle-import") (part "LTST-C170TBKT"))
    )
    (comp (ref "G7G5")
      (value "LTST-C170TBKT")
      (footprint "eagle-import:LEDC2012X120N")
      (fields (field (name "MOUSER_PART_NUMBER") "859-LTST-C170TBKT"))
      (libsource (lib "eagle-import") (part "LTST-C170TBKT"))
    )
    (comp (ref "G8G5")
      (value "LTST-C170TBKT")
      (footprint "eagle-import:LEDC2012X120N")
      (fields (field (name "MOUSER_PART_NUMBER") "859-LTST-C170TBKT"))
      (libsource (lib "eagle-import") (part "LTST-C170TBKT"))
    )
    (comp (ref "IC13")
      (value "74ALVC04PW,118")
      (footprint "eagle-import:SOP65P640X110-14N")
      (fields (field (name "MOUSER_PART_NUMBER") "771-ALVC04PW118"))
      (libsource (lib "eagle-import") (part "74ALVC04PW,118"))
    )
    (comp (ref "IC14")
      (value "74ALVC04PW,118")
      (footprint "eagle-import:SOP65P640X110-14N")
      (fields (field (name "MOUSER_PART_NUMBER") "771-ALVC04PW118"))
      (libsource (lib "eagle-import") (part "74ALVC04PW,118"))
    )
    (comp (ref "R5G5")
      (value "LTST-C170TBKT")
      (footprint "eagle-import:LEDC2012X120N")
      (fields (field (name "MOUSER_PART_NUMBER") "859-LTST-C170TBKT"))
      (libsource (lib "eagle-import") (part "LTST-C170TBKT"))
    )
    (comp (ref "R10")
      (value "50")
      (footprint "eagle-import:R0805")
      (libsource (lib "eagle-import") (part "R-US_R0805"))
    )
    (comp (ref "R11")
      (value "50")
      (footprint "eagle-import:R0805")
      (libsource (lib "eagle-import") (part "R-US_R0805"))
    )
    (comp (ref "R12")
      (value "50")
      (footprint "eagle-import:R0805")
      (libsource (lib "eagle-import") (part "R-US_R0805"))
    )
    (comp (ref "R13")
      (value "50")
      (footprint "eagle-import:R0805")
      (libsource (lib "eagle-import") (part "R-US_R0805"))
    )
    (comp (ref "U6")
      (value "74LCX138MX")
      (footprint "eagle-import:SOIC127P600X175-16N")
      (fields (field (name "DIGI-KEY_PART_NUMBER") "74LCX138MXCT-ND") (field (name "MF") "ON"))
      (libsource (lib "eagle-import") (part "74LCX138MX"))
    )
    (comp (ref "BARREL_JACK1")
      (value "2.1MMJACKTHM")
      (footprint "eagle-import:PJ-102A")
      (libsource (lib "eagle-import") (part "2.1MMJACKTHM"))
    )
    (comp (ref "C1")
      (value ".1uF")
      (footprint "eagle-import:C0805")
      (libsource (lib "eagle-import") (part "C-USC0805"))
    )
    (comp (ref "C2")
      (value "2.2uF")
      (footprint "eagle-import:C0805")
      (libsource (lib "eagle-import") (part "C-USC0805"))
    )
    (comp (ref "VOLTAGE_REG")
      (value "TLS850B0TBV33ATMA1")
      (footprint "eagle-import:TLS850B0TBV33ATMA1")
      (fields (field (name "MOUSER_PART_NUMBER") "726-TLS850B0TBV33ATM"))
      (libsource (lib "eagle-import") (part "TLS850B0TBV33ATMA1"))
    )
    (comp (ref "IC9")
      (value "74ALVC04PW,118")
      (footprint "eagle-import:SOP65P640X110-14N")
      (fields (field (name "MOUSER_PART_NUMBER") "771-ALVC04PW118"))
      (libsource (lib "eagle-import") (part "74ALVC04PW,118"))
    )
    (comp (ref "IC10")
      (value "74ALVC04PW,118")
      (footprint "eagle-import:SOP65P640X110-14N")
      (fields (field (name "MOUSER_PART_NUMBER") "771-ALVC04PW118"))
      (libsource (lib "eagle-import") (part "74ALVC04PW,118"))
    )
    (comp (ref "R1")
      (value "50")
      (footprint "eagle-import:R0805")
      (libsource (lib "eagle-import") (part "R-US_R0805"))
    )
    (comp (ref "R1G3")
      (value "LTST-C170TBKT")
      (footprint "eagle-import:LEDC2012X120N")
      (fields (field (name "MOUSER_PART_NUMBER") "859-LTST-C170TBKT"))
      (libsource (lib "eagle-import") (part "LTST-C170TBKT"))
    )
    (comp (ref "R2")
      (value "50")
      (footprint "eagle-import:R0805")
      (libsource (lib "eagle-import") (part "R-US_R0805"))
    )
    (comp (ref "R2G3")
      (value "LTST-C170TBKT")
      (footprint "eagle-import:LEDC2012X120N")
      (fields (field (name "MOUSER_PART_NUMBER") "859-LTST-C170TBKT"))
      (libsource (lib "eagle-import") (part "LTST-C170TBKT"))
    )
    (comp (ref "R3G3")
      (value "LTST-C170TBKT")
      (footprint "eagle-import:LEDC2012X120N")
      (fields (field (name "MOUSER_PART_NUMBER") "859-LTST-C170TBKT"))
      (libsource (lib "eagle-import") (part "LTST-C170TBKT"))
    )
    (comp (ref "R4G3")
      (value "LTST-C170TBKT")
      (footprint "eagle-import:LEDC2012X120N")
      (fields (field (name "MOUSER_PART_NUMBER") "859-LTST-C170TBKT"))
      (libsource (lib "eagle-import") (part "LTST-C170TBKT"))
    )
    (comp (ref "R5")
      (value "50")
      (footprint "eagle-import:R0805")
      (libsource (lib "eagle-import") (part "R-US_R0805"))
    )
    (comp (ref "R5G3")
      (value "LTST-C170TBKT")
      (footprint "eagle-import:LEDC2012X120N")
      (fields (field (name "MOUSER_PART_NUMBER") "859-LTST-C170TBKT"))
      (libsource (lib "eagle-import") (part "LTST-C170TBKT"))
    )
    (comp (ref "R6")
      (value "50")
      (footprint "eagle-import:R0805")
      (libsource (lib "eagle-import") (part "R-US_R0805"))
    )
    (comp (ref "R6G3")
      (value "LTST-C170TBKT")
      (footprint "eagle-import:LEDC2012X120N")
      (fields (field (name "MOUSER_PART_NUMBER") "859-LTST-C170TBKT"))
      (libsource (lib "eagle-import") (part "LTST-C170TBKT"))
    )
    (comp (ref "R7")
      (value "50")
      (footprint "eagle-import:R0805")
      (libsource (lib "eagle-import") (part "R-US_R0805"))
    )
    (comp (ref "R7G3")
      (value "LTST-C170TBKT")
      (footprint "eagle-import:LEDC2012X120N")
      (fields (field (name "MOUSER_PART_NUMBER") "859-LTST-C170TBKT"))
      (libsource (lib "eagle-import") (part "LTST-C170TBKT"))
    )
    (comp (ref "R8")
      (value "50")
      (footprint "eagle-import:R0805")
      (libsource (lib "eagle-import") (part "R-US_R0805"))
    )
    (comp (ref "R8G3")
      (value "LTST-C170TBKT")
      (footprint "eagle-import:LEDC2012X120N")
      (fields (field (name "MOUSER_PART_NUMBER") "859-LTST-C170TBKT"))
      (libsource (lib "eagle-import") (part "LTST-C170TBKT"))
    )
    (comp (ref "R9")
      (value "50")
      (footprint "eagle-import:R0805")
      (libsource (lib "eagle-import") (part "R-US_R0805"))
    )
    (comp (ref "R94")
      (value "50")
      (footprint "eagle-import:R0805")
      (libsource (lib "eagle-import") (part "R-US_R0805"))
    )
    (comp (ref "U4")
      (value "74LCX138MX")
      (footprint "eagle-import:SOIC127P600X175-16N")
      (fields (field (name "DIGI-KEY_PART_NUMBER") "74LCX138MXCT-ND") (field (name "MF") "ON"))
      (libsource (lib "eagle-import") (part "74LCX138MX"))
    )
    (comp (ref "IC1")
      (value "74HC390PW,118")
      (footprint "eagle-import:SOP65P640X110-16N")
      (fields (field (name "MOUSER_PART_NUMBER") "771-HC390PW118"))
      (libsource (lib "eagle-import") (part "74HC390PW,118"))
    )
    (comp (ref "IC2")
      (value "74ALVC04PW,118")
      (footprint "eagle-import:SOP65P640X110-14N")
      (fields (field (name "MOUSER_PART_NUMBER") "771-ALVC04PW118"))
      (libsource (lib "eagle-import") (part "74ALVC04PW,118"))
    )
    (comp (ref "IC3")
      (value "74ALVC08BQ,115")
      (footprint "eagle-import:QFN50P250X300X100-15N")
      (fields (field (name "MOUSER_PART_NUMBER") "771-ALVC08BQ115"))
      (libsource (lib "eagle-import") (part "74ALVC08BQ,115"))
    )
    (comp (ref "555_TIMER_CLOCK_GEN1")
      (value "LM555CM_NOPB")
      (footprint "eagle-import:SOIC127P600X175-8N")
      (fields
        (field (name "MANUFACTURER_PART_NUMBER") "LM555CM/NOPB")
        (field (name "MOUSER_PART_NUMBER") "926-LM555CM/NOPB")
      )
      (libsource (lib "eagle-import") (part "LM555CM_NOPB"))
    )
    (comp (ref "C6")
      (value ".01uF")
      (footprint "eagle-import:C0805")
      (libsource (lib "eagle-import") (part "C-USC0805"))
    )
    (comp (ref "C7")
      (value "C-USC0805")
      (footprint "eagle-import:C0805")
      (libsource (lib "eagle-import") (part "C-USC0805"))
    )
    (comp (ref "C8")
      (value ".1uF")
      (footprint "eagle-import:C0805")
      (libsource (lib "eagle-import") (part "C-USC0805"))
    )
    (comp (ref "IC4")
      (value "74ALVC08BQ,115")
      (footprint "eagle-import:QFN50P250X300X100-15N")
      (fields (field (name "MOUSER_PART_NUMBER") "771-ALVC08BQ115"))
      (libsource (lib "eagle-import") (part "74ALVC08BQ,115"))
    )
    (comp (ref "JP3")
      (value "PINHD-1X2")
      (footprint "eagle-import:1X02")
      (libsource (lib "eagle-import") (part "PINHD-1X2"))
    )
    (comp (ref "R3")
      (value "50")
      (footprint "eagle-import:R0805")
      (libsource (lib "eagle-import") (part "R-US_R0805"))
    )
    (comp (ref "R4")
      (value "128")
      (footprint "eagle-import:R0805")
      (libsource (lib "eagle-import") (part "R-US_R0805"))
    )
    (comp (ref "RA1")
      (value "R-US_R0805")
      (footprint "eagle-import:R0805")
      (libsource (lib "eagle-import") (part "R-US_R0805"))
    )
    (comp (ref "RB1")
      (value "R-US_R0805")
      (footprint "eagle-import:R0805")
      (libsource (lib "eagle-import") (part "R-US_R0805"))
    )
    (comp (ref "JP1")
      (value "PINHD-1X2")
      (footprint "eagle-import:1X02")
      (libsource (lib "eagle-import") (part "PINHD-1X2"))
    )
    (comp (ref "U1")
      (value "ESP32-DEVKITC-32D")
      (footprint "eagle-import:MODULE_ESP32-DEVKITC-32D")
      (fields (field (name "MF") "Espressif Systems"))
      (libsource (lib "eagle-import") (part "ESP32-DEVKITC-32D"))
    )
    (comp (ref "IC21")
      (value "74ALVC04PW,118")
      (footprint "eagle-import:SOP65P640X110-14N")
      (fields (field (name "MOUSER_PART_NUMBER") "771-ALVC04PW118"))
      (libsource (lib "eagle-import") (part "74ALVC04PW,118"))
    )
    (comp (ref "IC22")
      (value "74ALVC04PW,118")
      (footprint "eagle-import:SOP65P640X110-14N")
      (fields (field (name "MOUSER_PART_NUMBER") "771-ALVC04PW118"))
      (libsource (lib "eagle-import") (part "74ALVC04PW,118"))
    )
    (comp (ref "O1G9")
      (value "LTST-C170TBKT")
      (footprint "eagle-import:LEDC2012X120N")
      (fields (field (name "MOUSER_PART_NUMBER") "859-LTST-C170TBKT"))
      (libsource (lib "eagle-import") (part "LTST-C170TBKT"))
    )
    (comp (ref "O2G9")
      (value "LTST-C170TBKT")
      (footprint "eagle-import:LEDC2012X120N")
      (fields (field (name "MOUSER_PART_NUMBER") "859-LTST-C170TBKT"))
      (libsource (lib "eagle-import") (part "LTST-C170TBKT"))
    )
    (comp (ref "O3G9")
      (value "LTST-C170TBKT")
      (footprint "eagle-import:LEDC2012X120N")
      (fields (field (name "MOUSER_PART_NUMBER") "859-LTST-C170TBKT"))
      (libsource (lib "eagle-import") (part "LTST-C170TBKT"))
    )
    (comp (ref "O4G9")
      (value "LTST-C170TBKT")
      (footprint "eagle-import:LEDC2012X120N")
      (fields (field (name "MOUSER_PART_NUMBER") "859-LTST-C170TBKT"))
      (libsource (lib "eagle-import") (part "LTST-C170TBKT"))
    )
    (comp (ref "O5G9")
      (value "LTST-C170TBKT")
      (footprint "eagle-import:LEDC2012X120N")
      (fields (field (name "MOUSER_PART_NUMBER") "859-LTST-C170TBKT"))
      (libsource (lib "eagle-import") (part "LTST-C170TBKT"))
    )
    (comp (ref "O6G9")
      (value "LTST-C170TBKT")
      (footprint "eagle-import:LEDC2012X120N")
      (fields (field (name "MOUSER_PART_NUMBER") "859-LTST-C170TBKT"))
      (libsource (lib "eagle-import") (part "LTST-C170TBKT"))
    )
    (comp (ref "O7G9")
      (value "LTST-C170TBKT")
      (footprint "eagle-import:LEDC2012X120N")
      (fields (field (name "MOUSER_PART_NUMBER") "859-LTST-C170TBKT"))
      (libsource (lib "eagle-import") (part "LTST-C170TBKT"))
    )
    (comp (ref "O8G9")
      (value "LTST-C170TBKT")
      (footprint "eagle-import:LEDC2012X120N")
      (fields (field (name "MOUSER_PART_NUMBER") "859-LTST-C170TBKT"))
      (libsource (lib "eagle-import") (part "LTST-C170TBKT"))
    )
    (comp (ref "R38")
      (value "50")
      (footprint "eagle-import:R0805")
      (libsource (lib "eagle-import") (part "R-US_R0805"))
    )
    (comp (ref "R39")
      (value "50")
      (footprint "eagle-import:R0805")
      (libsource (lib "eagle-import") (part "R-US_R0805"))
    )
    (comp (ref "R40")
      (value "50")
      (footprint "eagle-import:R0805")
      (libsource (lib "eagle-import") (part "R-US_R0805"))
    )
    (comp (ref "R41")
      (value "50")
      (footprint "eagle-import:R0805")
      (libsource (lib "eagle-import") (part "R-US_R0805"))
    )
    (comp (ref "R42")
      (value "50")
      (footprint "eagle-import:R0805")
      (libsource (lib "eagle-import") (part "R-US_R0805"))
    )
    (comp (ref "R43")
      (value "50")
      (footprint "eagle-import:R0805")
      (libsource (lib "eagle-import") (part "R-US_R0805"))
    )
    (comp (ref "R44")
      (value "50")
      (footprint "eagle-import:R0805")
      (libsource (lib "eagle-import") (part "R-US_R0805"))
    )
    (comp (ref "R45")
      (value "50")
      (footprint "eagle-import:R0805")
      (libsource (lib "eagle-import") (part "R-US_R0805"))
    )
    (comp (ref "U10")
      (value "74LCX138MX")
      (footprint "eagle-import:SOIC127P600X175-16N")
      (fields (field (name "DIGI-KEY_PART_NUMBER") "74LCX138MXCT-ND") (field (name "MF") "ON"))
      (libsource (lib "eagle-import") (part "74LCX138MX"))
    )
    (comp (ref "B1G13")
      (value "LTST-C170TBKT")
      (footprint "eagle-import:LEDC2012X120N")
      (fields (field (name "MOUSER_PART_NUMBER") "859-LTST-C170TBKT"))
      (libsource (lib "eagle-import") (part "LTST-C170TBKT"))
    )
    (comp (ref "B2G13")
      (value "LTST-C170TBKT")
      (footprint "eagle-import:LEDC2012X120N")
      (fields (field (name "MOUSER_PART_NUMBER") "859-LTST-C170TBKT"))
      (libsource (lib "eagle-import") (part "LTST-C170TBKT"))
    )
    (comp (ref "B3G13")
      (value "LTST-C170TBKT")
      (footprint "eagle-import:LEDC2012X120N")
      (fields (field (name "MOUSER_PART_NUMBER") "859-LTST-C170TBKT"))
      (libsource (lib "eagle-import") (part "LTST-C170TBKT"))
    )
    (comp (ref "B4G13")
      (value "LTST-C170TBKT")
      (footprint "eagle-import:LEDC2012X120N")
      (fields (field (name "MOUSER_PART_NUMBER") "859-LTST-C170TBKT"))
      (libsource (lib "eagle-import") (part "LTST-C170TBKT"))
    )
    (comp (ref "B5G13")
      (value "LTST-C170TBKT")
      (footprint "eagle-import:LEDC2012X120N")
      (fields (field (name "MOUSER_PART_NUMBER") "859-LTST-C170TBKT"))
      (libsource (lib "eagle-import") (part "LTST-C170TBKT"))
    )
    (comp (ref "B6G13")
      (value "LTST-C170TBKT")
      (footprint "eagle-import:LEDC2012X120N")
      (fields (field (name "MOUSER_PART_NUMBER") "859-LTST-C170TBKT"))
      (libsource (lib "eagle-import") (part "LTST-C170TBKT"))
    )
    (comp (ref "B7G13")
      (value "LTST-C170TBKT")
      (footprint "eagle-import:LEDC2012X120N")
      (fields (field (name "MOUSER_PART_NUMBER") "859-LTST-C170TBKT"))
      (libsource (lib "eagle-import") (part "LTST-C170TBKT"))
    )
    (comp (ref "B8G13")
      (value "LTST-C170TBKT")
      (footprint "eagle-import:LEDC2012X120N")
      (fields (field (name "MOUSER_PART_NUMBER") "859-LTST-C170TBKT"))
      (libsource (lib "eagle-import") (part "LTST-C170TBKT"))
    )
    (comp (ref "IC29")
      (value "74ALVC04PW,118")
      (footprint "eagle-import:SOP65P640X110-14N")
      (fields (field (name "MOUSER_PART_NUMBER") "771-ALVC04PW118"))
      (libsource (lib "eagle-import") (part "74ALVC04PW,118"))
    )
    (comp (ref "IC30")
      (value "74ALVC04PW,118")
      (footprint "eagle-import:SOP65P640X110-14N")
      (fields (field (name "MOUSER_PART_NUMBER") "771-ALVC04PW118"))
      (libsource (lib "eagle-import") (part "74ALVC04PW,118"))
    )
    (comp (ref "U14")
      (value "74LCX138MX")
      (footprint "eagle-import:SOIC127P600X175-16N")
      (fields (field (name "DIGI-KEY_PART_NUMBER") "74LCX138MXCT-ND") (field (name "MF") "ON"))
      (libsource (lib "eagle-import") (part "74LCX138MX"))
    )
    (comp (ref "G1G14")
      (value "LTST-C170TBKT")
      (footprint "eagle-import:LEDC2012X120N")
      (fields (field (name "MOUSER_PART_NUMBER") "859-LTST-C170TBKT"))
      (libsource (lib "eagle-import") (part "LTST-C170TBKT"))
    )
    (comp (ref "G2G14")
      (value "LTST-C170TBKT")
      (footprint "eagle-import:LEDC2012X120N")
      (fields (field (name "MOUSER_PART_NUMBER") "859-LTST-C170TBKT"))
      (libsource (lib "eagle-import") (part "LTST-C170TBKT"))
    )
    (comp (ref "G3G14")
      (value "LTST-C170TBKT")
      (footprint "eagle-import:LEDC2012X120N")
      (fields (field (name "MOUSER_PART_NUMBER") "859-LTST-C170TBKT"))
      (libsource (lib "eagle-import") (part "LTST-C170TBKT"))
    )
    (comp (ref "G4G14")
      (value "LTST-C170TBKT")
      (footprint "eagle-import:LEDC2012X120N")
      (fields (field (name "MOUSER_PART_NUMBER") "859-LTST-C170TBKT"))
      (libsource (lib "eagle-import") (part "LTST-C170TBKT"))
    )
    (comp (ref "G5G14")
      (value "LTST-C170TBKT")
      (footprint "eagle-import:LEDC2012X120N")
      (fields (field (name "MOUSER_PART_NUMBER") "859-LTST-C170TBKT"))
      (libsource (lib "eagle-import") (part "LTST-C170TBKT"))
    )
    (comp (ref "G6G14")
      (value "LTST-C170TBKT")
      (footprint "eagle-import:LEDC2012X120N")
      (fields (field (name "MOUSER_PART_NUMBER") "859-LTST-C170TBKT"))
      (libsource (lib "eagle-import") (part "LTST-C170TBKT"))
    )
    (comp (ref "G7G14")
      (value "LTST-C170TBKT")
      (footprint "eagle-import:LEDC2012X120N")
      (fields (field (name "MOUSER_PART_NUMBER") "859-LTST-C170TBKT"))
      (libsource (lib "eagle-import") (part "LTST-C170TBKT"))
    )
    (comp (ref "G8G14")
      (value "LTST-C170TBKT")
      (footprint "eagle-import:LEDC2012X120N")
      (fields (field (name "MOUSER_PART_NUMBER") "859-LTST-C170TBKT"))
      (libsource (lib "eagle-import") (part "LTST-C170TBKT"))
    )
    (comp (ref "IC31")
      (value "74ALVC04PW,118")
      (footprint "eagle-import:SOP65P640X110-14N")
      (fields (field (name "MOUSER_PART_NUMBER") "771-ALVC04PW118"))
      (libsource (lib "eagle-import") (part "74ALVC04PW,118"))
    )
    (comp (ref "IC32")
      (value "74ALVC04PW,118")
      (footprint "eagle-import:SOP65P640X110-14N")
      (fields (field (name "MOUSER_PART_NUMBER") "771-ALVC04PW118"))
      (libsource (lib "eagle-import") (part "74ALVC04PW,118"))
    )
    (comp (ref "R68")
      (value "50")
      (footprint "eagle-import:R0805")
      (libsource (lib "eagle-import") (part "R-US_R0805"))
    )
    (comp (ref "R69")
      (value "50")
      (footprint "eagle-import:R0805")
      (libsource (lib "eagle-import") (part "R-US_R0805"))
    )
    (comp (ref "R70")
      (value "50")
      (footprint "eagle-import:R0805")
      (libsource (lib "eagle-import") (part "R-US_R0805"))
    )
    (comp (ref "R71")
      (value "50")
      (footprint "eagle-import:R0805")
      (libsource (lib "eagle-import") (part "R-US_R0805"))
    )
    (comp (ref "R72")
      (value "50")
      (footprint "eagle-import:R0805")
      (libsource (lib "eagle-import") (part "R-US_R0805"))
    )
    (comp (ref "R73")
      (value "50")
      (footprint "eagle-import:R0805")
      (libsource (lib "eagle-import") (part "R-US_R0805"))
    )
    (comp (ref "R74")
      (value "50")
      (footprint "eagle-import:R0805")
      (libsource (lib "eagle-import") (part "R-US_R0805"))
    )
    (comp (ref "R75")
      (value "50")
      (footprint "eagle-import:R0805")
      (libsource (lib "eagle-import") (part "R-US_R0805"))
    )
    (comp (ref "U15")
      (value "74LCX138MX")
      (footprint "eagle-import:SOIC127P600X175-16N")
      (fields (field (name "DIGI-KEY_PART_NUMBER") "74LCX138MXCT-ND") (field (name "MF") "ON"))
      (libsource (lib "eagle-import") (part "74LCX138MX"))
    )
    (comp (ref "IC33")
      (value "74ALVC04PW,118")
      (footprint "eagle-import:SOP65P640X110-14N")
      (fields (field (name "MOUSER_PART_NUMBER") "771-ALVC04PW118"))
      (libsource (lib "eagle-import") (part "74ALVC04PW,118"))
    )
    (comp (ref "IC34")
      (value "74ALVC04PW,118")
      (footprint "eagle-import:SOP65P640X110-14N")
      (fields (field (name "MOUSER_PART_NUMBER") "771-ALVC04PW118"))
      (libsource (lib "eagle-import") (part "74ALVC04PW,118"))
    )
    (comp (ref "R1G15")
      (value "LTST-C170TBKT")
      (footprint "eagle-import:LEDC2012X120N")
      (fields (field (name "MOUSER_PART_NUMBER") "859-LTST-C170TBKT"))
      (libsource (lib "eagle-import") (part "LTST-C170TBKT"))
    )
    (comp (ref "R2G15")
      (value "LTST-C170TBKT")
      (footprint "eagle-import:LEDC2012X120N")
      (fields (field (name "MOUSER_PART_NUMBER") "859-LTST-C170TBKT"))
      (libsource (lib "eagle-import") (part "LTST-C170TBKT"))
    )
    (comp (ref "R3G15")
      (value "LTST-C170TBKT")
      (footprint "eagle-import:LEDC2012X120N")
      (fields (field (name "MOUSER_PART_NUMBER") "859-LTST-C170TBKT"))
      (libsource (lib "eagle-import") (part "LTST-C170TBKT"))
    )
    (comp (ref "R4G15")
      (value "LTST-C170TBKT")
      (footprint "eagle-import:LEDC2012X120N")
      (fields (field (name "MOUSER_PART_NUMBER") "859-LTST-C170TBKT"))
      (libsource (lib "eagle-import") (part "LTST-C170TBKT"))
    )
    (comp (ref "R5G15")
      (value "LTST-C170TBKT")
      (footprint "eagle-import:LEDC2012X120N")
      (fields (field (name "MOUSER_PART_NUMBER") "859-LTST-C170TBKT"))
      (libsource (lib "eagle-import") (part "LTST-C170TBKT"))
    )
    (comp (ref "R6G15")
      (value "LTST-C170TBKT")
      (footprint "eagle-import:LEDC2012X120N")
      (fields (field (name "MOUSER_PART_NUMBER") "859-LTST-C170TBKT"))
      (libsource (lib "eagle-import") (part "LTST-C170TBKT"))
    )
    (comp (ref "R7G15")
      (value "LTST-C170TBKT")
      (footprint "eagle-import:LEDC2012X120N")
      (fields (field (name "MOUSER_PART_NUMBER") "859-LTST-C170TBKT"))
      (libsource (lib "eagle-import") (part "LTST-C170TBKT"))
    )
    (comp (ref "R8G15")
      (value "LTST-C170TBKT")
      (footprint "eagle-import:LEDC2012X120N")
      (fields (field (name "MOUSER_PART_NUMBER") "859-LTST-C170TBKT"))
      (libsource (lib "eagle-import") (part "LTST-C170TBKT"))
    )
    (comp (ref "R76")
      (value "50")
      (footprint "eagle-import:R0805")
      (libsource (lib "eagle-import") (part "R-US_R0805"))
    )
    (comp (ref "R77")
      (value "50")
      (footprint "eagle-import:R0805")
      (libsource (lib "eagle-import") (part "R-US_R0805"))
    )
    (comp (ref "R78")
      (value "50")
      (footprint "eagle-import:R0805")
      (libsource (lib "eagle-import") (part "R-US_R0805"))
    )
    (comp (ref "R79")
      (value "50")
      (footprint "eagle-import:R0805")
      (libsource (lib "eagle-import") (part "R-US_R0805"))
    )
    (comp (ref "R80")
      (value "50")
      (footprint "eagle-import:R0805")
      (libsource (lib "eagle-import") (part "R-US_R0805"))
    )
    (comp (ref "R81")
      (value "50")
      (footprint "eagle-import:R0805")
      (libsource (lib "eagle-import") (part "R-US_R0805"))
    )
    (comp (ref "R82")
      (value "50")
      (footprint "eagle-import:R0805")
      (libsource (lib "eagle-import") (part "R-US_R0805"))
    )
    (comp (ref "R83")
      (value "50")
      (footprint "eagle-import:R0805")
      (libsource (lib "eagle-import") (part "R-US_R0805"))
    )
    (comp (ref "U16")
      (value "74LCX138MX")
      (footprint "eagle-import:SOIC127P600X175-16N")
      (fields (field (name "DIGI-KEY_PART_NUMBER") "74LCX138MXCT-ND") (field (name "MF") "ON"))
      (libsource (lib "eagle-import") (part "74LCX138MX"))
    )
    (comp (ref "IC15")
      (value "74ALVC04PW,118")
      (footprint "eagle-import:SOP65P640X110-14N")
      (fields (field (name "MOUSER_PART_NUMBER") "771-ALVC04PW118"))
      (libsource (lib "eagle-import") (part "74ALVC04PW,118"))
    )
    (comp (ref "IC16")
      (value "74ALVC04PW,118")
      (footprint "eagle-import:SOP65P640X110-14N")
      (fields (field (name "MOUSER_PART_NUMBER") "771-ALVC04PW118"))
      (libsource (lib "eagle-import") (part "74ALVC04PW,118"))
    )
    (comp (ref "R1G6")
      (value "LTST-C170TBKT")
      (footprint "eagle-import:LEDC2012X120N")
      (fields (field (name "MOUSER_PART_NUMBER") "859-LTST-C170TBKT"))
      (libsource (lib "eagle-import") (part "LTST-C170TBKT"))
    )
    (comp (ref "R2G6")
      (value "LTST-C170TBKT")
      (footprint "eagle-import:LEDC2012X120N")
      (fields (field (name "MOUSER_PART_NUMBER") "859-LTST-C170TBKT"))
      (libsource (lib "eagle-import") (part "LTST-C170TBKT"))
    )
    (comp (ref "R3G6")
      (value "LTST-C170TBKT")
      (footprint "eagle-import:LEDC2012X120N")
      (fields (field (name "MOUSER_PART_NUMBER") "859-LTST-C170TBKT"))
      (libsource (lib "eagle-import") (part "LTST-C170TBKT"))
    )
    (comp (ref "R4G6")
      (value "LTST-C170TBKT")
      (footprint "eagle-import:LEDC2012X120N")
      (fields (field (name "MOUSER_PART_NUMBER") "859-LTST-C170TBKT"))
      (libsource (lib "eagle-import") (part "LTST-C170TBKT"))
    )
    (comp (ref "R5G6")
      (value "LTST-C170TBKT")
      (footprint "eagle-import:LEDC2012X120N")
      (fields (field (name "MOUSER_PART_NUMBER") "859-LTST-C170TBKT"))
      (libsource (lib "eagle-import") (part "LTST-C170TBKT"))
    )
    (comp (ref "R6G6")
      (value "LTST-C170TBKT")
      (footprint "eagle-import:LEDC2012X120N")
      (fields (field (name "MOUSER_PART_NUMBER") "859-LTST-C170TBKT"))
      (libsource (lib "eagle-import") (part "LTST-C170TBKT"))
    )
    (comp (ref "R7G6")
      (value "LTST-C170TBKT")
      (footprint "eagle-import:LEDC2012X120N")
      (fields (field (name "MOUSER_PART_NUMBER") "859-LTST-C170TBKT"))
      (libsource (lib "eagle-import") (part "LTST-C170TBKT"))
    )
    (comp (ref "R8G6")
      (value "LTST-C170TBKT")
      (footprint "eagle-import:LEDC2012X120N")
      (fields (field (name "MOUSER_PART_NUMBER") "859-LTST-C170TBKT"))
      (libsource (lib "eagle-import") (part "LTST-C170TBKT"))
    )
    (comp (ref "R14")
      (value "50")
      (footprint "eagle-import:R0805")
      (libsource (lib "eagle-import") (part "R-US_R0805"))
    )
    (comp (ref "R15")
      (value "50")
      (footprint "eagle-import:R0805")
      (libsource (lib "eagle-import") (part "R-US_R0805"))
    )
    (comp (ref "R16")
      (value "50")
      (footprint "eagle-import:R0805")
      (libsource (lib "eagle-import") (part "R-US_R0805"))
    )
    (comp (ref "R17")
      (value "50")
      (footprint "eagle-import:R0805")
      (libsource (lib "eagle-import") (part "R-US_R0805"))
    )
    (comp (ref "R18")
      (value "50")
      (footprint "eagle-import:R0805")
      (libsource (lib "eagle-import") (part "R-US_R0805"))
    )
    (comp (ref "R19")
      (value "50")
      (footprint "eagle-import:R0805")
      (libsource (lib "eagle-import") (part "R-US_R0805"))
    )
    (comp (ref "R20")
      (value "50")
      (footprint "eagle-import:R0805")
      (libsource (lib "eagle-import") (part "R-US_R0805"))
    )
    (comp (ref "R21")
      (value "50")
      (footprint "eagle-import:R0805")
      (libsource (lib "eagle-import") (part "R-US_R0805"))
    )
    (comp (ref "U7")
      (value "74LCX138MX")
      (footprint "eagle-import:SOIC127P600X175-16N")
      (fields (field (name "DIGI-KEY_PART_NUMBER") "74LCX138MXCT-ND") (field (name "MF") "ON"))
      (libsource (lib "eagle-import") (part "74LCX138MX"))
    )
    (comp (ref "IC25")
      (value "74ALVC04PW,118")
      (footprint "eagle-import:SOP65P640X110-14N")
      (fields (field (name "MOUSER_PART_NUMBER") "771-ALVC04PW118"))
      (libsource (lib "eagle-import") (part "74ALVC04PW,118"))
    )
    (comp (ref "IC26")
      (value "74ALVC04PW,118")
      (footprint "eagle-import:SOP65P640X110-14N")
      (fields (field (name "MOUSER_PART_NUMBER") "771-ALVC04PW118"))
      (libsource (lib "eagle-import") (part "74ALVC04PW,118"))
    )
    (comp (ref "O1G11")
      (value "LTST-C170TBKT")
      (footprint "eagle-import:LEDC2012X120N")
      (fields (field (name "MOUSER_PART_NUMBER") "859-LTST-C170TBKT"))
      (libsource (lib "eagle-import") (part "LTST-C170TBKT"))
    )
    (comp (ref "O2G11")
      (value "LTST-C170TBKT")
      (footprint "eagle-import:LEDC2012X120N")
      (fields (field (name "MOUSER_PART_NUMBER") "859-LTST-C170TBKT"))
      (libsource (lib "eagle-import") (part "LTST-C170TBKT"))
    )
    (comp (ref "O3G11")
      (value "LTST-C170TBKT")
      (footprint "eagle-import:LEDC2012X120N")
      (fields (field (name "MOUSER_PART_NUMBER") "859-LTST-C170TBKT"))
      (libsource (lib "eagle-import") (part "LTST-C170TBKT"))
    )
    (comp (ref "O4G11")
      (value "LTST-C170TBKT")
      (footprint "eagle-import:LEDC2012X120N")
      (fields (field (name "MOUSER_PART_NUMBER") "859-LTST-C170TBKT"))
      (libsource (lib "eagle-import") (part "LTST-C170TBKT"))
    )
    (comp (ref "O5G11")
      (value "LTST-C170TBKT")
      (footprint "eagle-import:LEDC2012X120N")
      (fields (field (name "MOUSER_PART_NUMBER") "859-LTST-C170TBKT"))
      (libsource (lib "eagle-import") (part "LTST-C170TBKT"))
    )
    (comp (ref "O6G11")
      (value "LTST-C170TBKT")
      (footprint "eagle-import:LEDC2012X120N")
      (fields (field (name "MOUSER_PART_NUMBER") "859-LTST-C170TBKT"))
      (libsource (lib "eagle-import") (part "LTST-C170TBKT"))
    )
    (comp (ref "O7G11")
      (value "LTST-C170TBKT")
      (footprint "eagle-import:LEDC2012X120N")
      (fields (field (name "MOUSER_PART_NUMBER") "859-LTST-C170TBKT"))
      (libsource (lib "eagle-import") (part "LTST-C170TBKT"))
    )
    (comp (ref "O8G11")
      (value "LTST-C170TBKT")
      (footprint "eagle-import:LEDC2012X120N")
      (fields (field (name "MOUSER_PART_NUMBER") "859-LTST-C170TBKT"))
      (libsource (lib "eagle-import") (part "LTST-C170TBKT"))
    )
    (comp (ref "R52")
      (value "50")
      (footprint "eagle-import:R0805")
      (libsource (lib "eagle-import") (part "R-US_R0805"))
    )
    (comp (ref "R53")
      (value "50")
      (footprint "eagle-import:R0805")
      (libsource (lib "eagle-import") (part "R-US_R0805"))
    )
    (comp (ref "R54")
      (value "50")
      (footprint "eagle-import:R0805")
      (libsource (lib "eagle-import") (part "R-US_R0805"))
    )
    (comp (ref "R55")
      (value "50")
      (footprint "eagle-import:R0805")
      (libsource (lib "eagle-import") (part "R-US_R0805"))
    )
    (comp (ref "R56")
      (value "50")
      (footprint "eagle-import:R0805")
      (libsource (lib "eagle-import") (part "R-US_R0805"))
    )
    (comp (ref "R57")
      (value "50")
      (footprint "eagle-import:R0805")
      (libsource (lib "eagle-import") (part "R-US_R0805"))
    )
    (comp (ref "R58")
      (value "50")
      (footprint "eagle-import:R0805")
      (libsource (lib "eagle-import") (part "R-US_R0805"))
    )
    (comp (ref "R59")
      (value "50")
      (footprint "eagle-import:R0805")
      (libsource (lib "eagle-import") (part "R-US_R0805"))
    )
    (comp (ref "U12")
      (value "74LCX138MX")
      (footprint "eagle-import:SOIC127P600X175-16N")
      (fields (field (name "DIGI-KEY_PART_NUMBER") "74LCX138MXCT-ND") (field (name "MF") "ON"))
      (libsource (lib "eagle-import") (part "74LCX138MX"))
    )
  )
  (nets
    (net (code "1") (name "+3V3") (class "Default")
      (node (ref "C2") (pin "1") (pinfunction "1_1") (pintype "passive"))
      (node (ref "IC1") (pin "16") (pinfunction "VCC_16") (pintype "bidirectional"))
      (node (ref "IC10") (pin "14") (pinfunction "VCC_14") (pintype "bidirectional"))
      (node (ref "IC11") (pin "14") (pinfunction "VCC_14") (pintype "bidirectional"))
      (node (ref "IC12") (pin "14") (pinfunction "VCC_14") (pintype "bidirectional"))
      (node (ref "IC13") (pin "14") (pinfunction "VCC_14") (pintype "bidirectional"))
      (node (ref "IC14") (pin "14") (pinfunction "VCC_14") (pintype "bidirectional"))
      (node (ref "IC15") (pin "14") (pinfunction "VCC_14") (pintype "bidirectional"))
      (node (ref "IC16") (pin "14") (pinfunction "VCC_14") (pintype "bidirectional"))
      (node (ref "IC17") (pin "14") (pinfunction "VCC_14") (pintype "bidirectional"))
      (node (ref "IC18") (pin "14") (pinfunction "VCC_14") (pintype "bidirectional"))
      (node (ref "IC19") (pin "14") (pinfunction "VCC_14") (pintype "bidirectional"))
      (node (ref "IC2") (pin "14") (pinfunction "VCC_14") (pintype "bidirectional"))
      (node (ref "IC20") (pin "14") (pinfunction "VCC_14") (pintype "bidirectional"))
      (node (ref "IC21") (pin "14") (pinfunction "VCC_14") (pintype "bidirectional"))
      (node (ref "IC22") (pin "14") (pinfunction "VCC_14") (pintype "bidirectional"))
      (node (ref "IC23") (pin "14") (pinfunction "VCC_14") (pintype "bidirectional"))
      (node (ref "IC25") (pin "14") (pinfunction "VCC_14") (pintype "bidirectional"))
      (node (ref "IC26") (pin "14") (pinfunction "VCC_14") (pintype "bidirectional"))
      (node (ref "IC27") (pin "14") (pinfunction "VCC_14") (pintype "bidirectional"))
      (node (ref "IC28") (pin "14") (pinfunction "VCC_14") (pintype "bidirectional"))
      (node (ref "IC29") (pin "14") (pinfunction "VCC_14") (pintype "bidirectional"))
      (node (ref "IC3") (pin "14") (pinfunction "VCC_14") (pintype "bidirectional"))
      (node (ref "IC30") (pin "14") (pinfunction "VCC_14") (pintype "bidirectional"))
      (node (ref "IC31") (pin "14") (pinfunction "VCC_14") (pintype "bidirectional"))
      (node (ref "IC32") (pin "14") (pinfunction "VCC_14") (pintype "bidirectional"))
      (node (ref "IC33") (pin "14") (pinfunction "VCC_14") (pintype "bidirectional"))
      (node (ref "IC34") (pin "14") (pinfunction "VCC_14") (pintype "bidirectional"))
      (node (ref "IC35") (pin "14") (pinfunction "VCC_14") (pintype "bidirectional"))
      (node (ref "IC36") (pin "14") (pinfunction "VCC_14") (pintype "bidirectional"))
      (node (ref "IC37") (pin "14") (pinfunction "VCC_14") (pintype "bidirectional"))
      (node (ref "IC38") (pin "14") (pinfunction "VCC_14") (pintype "bidirectional"))
      (node (ref "IC39") (pin "14") (pinfunction "VCC_14") (pintype "bidirectional"))
      (node (ref "IC4") (pin "14") (pinfunction "VCC_14") (pintype "bidirectional"))
      (node (ref "IC40") (pin "14") (pinfunction "VCC_14") (pintype "bidirectional"))
      (node (ref "IC5") (pin "14") (pinfunction "VCC_14") (pintype "bidirectional"))
      (node (ref "IC6") (pin "14") (pinfunction "VCC_14") (pintype "bidirectional"))
      (node (ref "IC7") (pin "14") (pinfunction "VCC_14") (pintype "bidirectional"))
      (node (ref "IC8") (pin "14") (pinfunction "VCC_14") (pintype "bidirectional"))
      (node (ref "IC9") (pin "14") (pinfunction "VCC_14") (pintype "bidirectional"))
      (node (ref "U10") (pin "16") (pinfunction "VCC_16") (pintype "power_in"))
      (node (ref "U11") (pin "16") (pinfunction "VCC_16") (pintype "power_in"))
      (node (ref "U12") (pin "16") (pinfunction "VCC_16") (pintype "power_in"))
      (node (ref "U13") (pin "16") (pinfunction "VCC_16") (pintype "power_in"))
      (node (ref "U14") (pin "16") (pinfunction "VCC_16") (pintype "power_in"))
      (node (ref "U15") (pin "16") (pinfunction "VCC_16") (pintype "power_in"))
      (node (ref "U16") (pin "16") (pinfunction "VCC_16") (pintype "power_in"))
      (node (ref "U17") (pin "16") (pinfunction "VCC_16") (pintype "power_in"))
      (node (ref "U18") (pin "16") (pinfunction "VCC_16") (pintype "power_in"))
      (node (ref "U19") (pin "16") (pinfunction "VCC_16") (pintype "power_in"))
      (node (ref "U2") (pin "16") (pinfunction "VCC_16") (pintype "power_in"))
      (node (ref "U3") (pin "16") (pinfunction "VCC_16") (pintype "power_in"))
      (node (ref "U4") (pin "16") (pinfunction "VCC_16") (pintype "power_in"))
      (node (ref "U5") (pin "16") (pinfunction "VCC_16") (pintype "power_in"))
      (node (ref "U6") (pin "16") (pinfunction "VCC_16") (pintype "power_in"))
      (node (ref "U7") (pin "16") (pinfunction "VCC_16") (pintype "power_in"))
      (node (ref "U8") (pin "16") (pinfunction "VCC_16") (pintype "power_in"))
      (node (ref "U9") (pin "16") (pinfunction "VCC_16") (pintype "power_in"))
      (node (ref "VOLTAGE_REG") (pin "5") (pinfunction "Q_5") (pintype "bidirectional"))
    )
    (net (code "2") (name "+5V") (class "Default")
      (node (ref "555_TIMER_CLOCK_GEN1") (pin "4") (pinfunction "RESET_4") (pintype "bidirectional"))
      (node (ref "555_TIMER_CLOCK_GEN1") (pin "8") (pinfunction "+VCC_8") (pintype "bidirectional"))
      (node (ref "BARREL_JACK1") (pin "TIP") (pinfunction "TIP_TIP") (pintype "bidirectional"))
      (node (ref "C1") (pin "1") (pinfunction "1_1") (pintype "passive"))
      (node (ref "C8") (pin "1") (pinfunction "1_1") (pintype "passive"))
      (node (ref "JP1") (pin "1") (pinfunction "1_1") (pintype "passive"))
      (node (ref "RA1") (pin "2") (pinfunction "2_2") (pintype "passive"))
      (node (ref "VOLTAGE_REG") (pin "1") (pinfunction "I_1") (pintype "bidirectional"))
      (node (ref "VOLTAGE_REG") (pin "2") (pinfunction "EN_2") (pintype "bidirectional"))
    )
    (net (code "3") (name "3V3") (class "Default")
      (node (ref "U1") (pin "1") (pinfunction "3V3_1") (pintype "power_in"))
    )
    (net (code "4") (name "CLK") (class "Default")
      (node (ref "IC1") (pin "1") (pinfunction "~{1CP0}_1") (pintype "bidirectional"))
      (node (ref "IC4") (pin "8") (pinfunction "3Y_8") (pintype "bidirectional"))
      (node (ref "U1") (pin "5") (pinfunction "IO34_5") (pintype "bidirectional"))
    )
    (net (code "5") (name "CLK_EN") (class "Default")
      (node (ref "IC4") (pin "2") (pinfunction "1B_2") (pintype "bidirectional"))
      (node (ref "IC4") (pin "4") (pinfunction "2A_4") (pintype "bidirectional"))
      (node (ref "IC4") (pin "5") (pinfunction "2B_5") (pintype "bidirectional"))
      (node (ref "U1") (pin "15") (pinfunction "IO13_15") (pintype "bidirectional"))
    )
    (net (code "6") (name "CTR_MR") (class "Default")
      (node (ref "IC1") (pin "2") (pinfunction "1MR_2") (pintype "bidirectional"))
      (node (ref "IC3") (pin "8") (pinfunction "3Y_8") (pintype "bidirectional"))
      (node (ref "U1") (pin "32") (pinfunction "IO4_32") (pintype "bidirectional"))
    )
    (net (code "7") (name "GND") (class "Default")
      (node (ref "555_TIMER_CLOCK_GEN1") (pin "1") (pinfunction "GND_1") (pintype "bidirectional"))
      (node (ref "B1G1") (pin "1") (pinfunction "K_1") (pintype "bidirectional"))
      (node (ref "B1G13") (pin "1") (pinfunction "K_1") (pintype "bidirectional"))
      (node (ref "B1G16") (pin "1") (pinfunction "K_1") (pintype "bidirectional"))
      (node (ref "B1G2") (pin "1") (pinfunction "K_1") (pintype "bidirectional"))
      (node (ref "B1G4") (pin "1") (pinfunction "K_1") (pintype "bidirectional"))
      (node (ref "B1G5") (pin "1") (pinfunction "K_1") (pintype "bidirectional"))
      (node (ref "B2G1") (pin "1") (pinfunction "K_1") (pintype "bidirectional"))
      (node (ref "B2G13") (pin "1") (pinfunction "K_1") (pintype "bidirectional"))
      (node (ref "B2G16") (pin "1") (pinfunction "K_1") (pintype "bidirectional"))
      (node (ref "B2G2") (pin "1") (pinfunction "K_1") (pintype "bidirectional"))
      (node (ref "B2G4") (pin "1") (pinfunction "K_1") (pintype "bidirectional"))
      (node (ref "B2G5") (pin "1") (pinfunction "K_1") (pintype "bidirectional"))
      (node (ref "B3G1") (pin "1") (pinfunction "K_1") (pintype "bidirectional"))
      (node (ref "B3G13") (pin "1") (pinfunction "K_1") (pintype "bidirectional"))
      (node (ref "B3G16") (pin "1") (pinfunction "K_1") (pintype "bidirectional"))
      (node (ref "B3G17") (pin "1") (pinfunction "K_1") (pintype "bidirectional"))
      (node (ref "B3G2") (pin "1") (pinfunction "K_1") (pintype "bidirectional"))
      (node (ref "B3G4") (pin "1") (pinfunction "K_1") (pintype "bidirectional"))
      (node (ref "B3G5") (pin "1") (pinfunction "K_1") (pintype "bidirectional"))
      (node (ref "B4G1") (pin "1") (pinfunction "K_1") (pintype "bidirectional"))
      (node (ref "B4G13") (pin "1") (pinfunction "K_1") (pintype "bidirectional"))
      (node (ref "B4G16") (pin "1") (pinfunction "K_1") (pintype "bidirectional"))
      (node (ref "B4G17") (pin "1") (pinfunction "K_1") (pintype "bidirectional"))
      (node (ref "B4G2") (pin "1") (pinfunction "K_1") (pintype "bidirectional"))
      (node (ref "B4G4") (pin "1") (pinfunction "K_1") (pintype "bidirectional"))
      (node (ref "B4G5") (pin "1") (pinfunction "K_1") (pintype "bidirectional"))
      (node (ref "B5G1") (pin "1") (pinfunction "K_1") (pintype "bidirectional"))
      (node (ref "B5G13") (pin "1") (pinfunction "K_1") (pintype "bidirectional"))
      (node (ref "B5G16") (pin "1") (pinfunction "K_1") (pintype "bidirectional"))
      (node (ref "B5G17") (pin "1") (pinfunction "K_1") (pintype "bidirectional"))
      (node (ref "B5G2") (pin "1") (pinfunction "K_1") (pintype "bidirectional"))
      (node (ref "B5G4") (pin "1") (pinfunction "K_1") (pintype "bidirectional"))
      (node (ref "B6G1") (pin "1") (pinfunction "K_1") (pintype "bidirectional"))
      (node (ref "B6G13") (pin "1") (pinfunction "K_1") (pintype "bidirectional"))
      (node (ref "B6G16") (pin "1") (pinfunction "K_1") (pintype "bidirectional"))
      (node (ref "B6G17") (pin "1") (pinfunction "K_1") (pintype "bidirectional"))
      (node (ref "B6G2") (pin "1") (pinfunction "K_1") (pintype "bidirectional"))
      (node (ref "B6G4") (pin "1") (pinfunction "K_1") (pintype "bidirectional"))
      (node (ref "B7G1") (pin "1") (pinfunction "K_1") (pintype "bidirectional"))
      (node (ref "B7G13") (pin "1") (pinfunction "K_1") (pintype "bidirectional"))
      (node (ref "B7G16") (pin "1") (pinfunction "K_1") (pintype "bidirectional"))
      (node (ref "B7G17") (pin "1") (pinfunction "K_1") (pintype "bidirectional"))
      (node (ref "B7G2") (pin "1") (pinfunction "K_1") (pintype "bidirectional"))
      (node (ref "B7G4") (pin "1") (pinfunction "K_1") (pintype "bidirectional"))
      (node (ref "B8G1") (pin "1") (pinfunction "K_1") (pintype "bidirectional"))
      (node (ref "B8G13") (pin "1") (pinfunction "K_1") (pintype "bidirectional"))
      (node (ref "B8G16") (pin "1") (pinfunction "K_1") (pintype "bidirectional"))
      (node (ref "B8G17") (pin "1") (pinfunction "K_1") (pintype "bidirectional"))
      (node (ref "B8G4") (pin "1") (pinfunction "K_1") (pintype "bidirectional"))
      (node (ref "BARREL_JACK1") (pin "RING") (pinfunction "RING_RING") (pintype "bidirectional"))
      (node (ref "BARREL_JACK1") (pin "RING_SW") (pinfunction "RING_SW_RING_SW") (pintype "bidirectional"))
      (node (ref "C1") (pin "2") (pinfunction "2_2") (pintype "passive"))
      (node (ref "C2") (pin "2") (pinfunction "2_2") (pintype "passive"))
      (node (ref "C6") (pin "2") (pinfunction "2_2") (pintype "passive"))
      (node (ref "C7") (pin "2") (pinfunction "2_2") (pintype "passive"))
      (node (ref "C8") (pin "2") (pinfunction "2_2") (pintype "passive"))
      (node (ref "IC1") (pin "8") (pinfunction "GND_8") (pintype "bidirectional"))
      (node (ref "IC10") (pin "7") (pinfunction "GND_7") (pintype "bidirectional"))
      (node (ref "IC11") (pin "7") (pinfunction "GND_7") (pintype "bidirectional"))
      (node (ref "IC12") (pin "7") (pinfunction "GND_7") (pintype "bidirectional"))
      (node (ref "IC13") (pin "7") (pinfunction "GND_7") (pintype "bidirectional"))
      (node (ref "IC14") (pin "7") (pinfunction "GND_7") (pintype "bidirectional"))
      (node (ref "IC15") (pin "7") (pinfunction "GND_7") (pintype "bidirectional"))
      (node (ref "IC16") (pin "7") (pinfunction "GND_7") (pintype "bidirectional"))
      (node (ref "IC17") (pin "7") (pinfunction "GND_7") (pintype "bidirectional"))
      (node (ref "IC18") (pin "7") (pinfunction "GND_7") (pintype "bidirectional"))
      (node (ref "IC19") (pin "7") (pinfunction "GND_7") (pintype "bidirectional"))
      (node (ref "IC2") (pin "7") (pinfunction "GND_7") (pintype "bidirectional"))
      (node (ref "IC20") (pin "7") (pinfunction "GND_7") (pintype "bidirectional"))
      (node (ref "IC21") (pin "7") (pinfunction "GND_7") (pintype "bidirectional"))
      (node (ref "IC22") (pin "7") (pinfunction "GND_7") (pintype "bidirectional"))
      (node (ref "IC23") (pin "7") (pinfunction "GND_7") (pintype "bidirectional"))
      (node (ref "IC25") (pin "7") (pinfunction "GND_7") (pintype "bidirectional"))
      (node (ref "IC26") (pin "7") (pinfunction "GND_7") (pintype "bidirectional"))
      (node (ref "IC27") (pin "7") (pinfunction "GND_7") (pintype "bidirectional"))
      (node (ref "IC28") (pin "7") (pinfunction "GND_7") (pintype "bidirectional"))
      (node (ref "IC29") (pin "7") (pinfunction "GND_7") (pintype "bidirectional"))
      (node (ref "IC3") (pin "7") (pinfunction "GND_7") (pintype "bidirectional"))
      (node (ref "IC30") (pin "7") (pinfunction "GND_7") (pintype "bidirectional"))
      (node (ref "IC31") (pin "7") (pinfunction "GND_7") (pintype "bidirectional"))
      (node (ref "IC32") (pin "7") (pinfunction "GND_7") (pintype "bidirectional"))
      (node (ref "IC33") (pin "7") (pinfunction "GND_7") (pintype "bidirectional"))
      (node (ref "IC34") (pin "7") (pinfunction "GND_7") (pintype "bidirectional"))
      (node (ref "IC35") (pin "7") (pinfunction "GND_7") (pintype "bidirectional"))
      (node (ref "IC36") (pin "7") (pinfunction "GND_7") (pintype "bidirectional"))
      (node (ref "IC37") (pin "7") (pinfunction "GND_7") (pintype "bidirectional"))
      (node (ref "IC38") (pin "7") (pinfunction "GND_7") (pintype "bidirectional"))
      (node (ref "IC39") (pin "7") (pinfunction "GND_7") (pintype "bidirectional"))
      (node (ref "IC4") (pin "7") (pinfunction "GND_7") (pintype "bidirectional"))
      (node (ref "IC40") (pin "7") (pinfunction "GND_7") (pintype "bidirectional"))
      (node (ref "IC5") (pin "7") (pinfunction "GND_7") (pintype "bidirectional"))
      (node (ref "IC6") (pin "7") (pinfunction "GND_7") (pintype "bidirectional"))
      (node (ref "IC7") (pin "7") (pinfunction "GND_7") (pintype "bidirectional"))
      (node (ref "IC8") (pin "7") (pinfunction "GND_7") (pintype "bidirectional"))
      (node (ref "IC9") (pin "7") (pinfunction "GND_7") (pintype "bidirectional"))
      (node (ref "R1") (pin "1") (pinfunction "1_1") (pintype "passive"))
      (node (ref "R10") (pin "1") (pinfunction "1_1") (pintype "passive"))
      (node (ref "R11") (pin "1") (pinfunction "1_1") (pintype "passive"))
      (node (ref "R12") (pin "1") (pinfunction "1_1") (pintype "passive"))
      (node (ref "R13") (pin "1") (pinfunction "1_1") (pintype "passive"))
      (node (ref "R14") (pin "1") (pinfunction "1_1") (pintype "passive"))
      (node (ref "R15") (pin "1") (pinfunction "1_1") (pintype "passive"))
      (node (ref "R16") (pin "1") (pinfunction "1_1") (pintype "passive"))
      (node (ref "R17") (pin "1") (pinfunction "1_1") (pintype "passive"))
      (node (ref "R18") (pin "1") (pinfunction "1_1") (pintype "passive"))
      (node (ref "R19") (pin "1") (pinfunction "1_1") (pintype "passive"))
      (node (ref "R2") (pin "1") (pinfunction "1_1") (pintype "passive"))
      (node (ref "R20") (pin "1") (pinfunction "1_1") (pintype "passive"))
      (node (ref "R21") (pin "1") (pinfunction "1_1") (pintype "passive"))
      (node (ref "R22") (pin "1") (pinfunction "1_1") (pintype "passive"))
      (node (ref "R23") (pin "1") (pinfunction "1_1") (pintype "passive"))
      (node (ref "R24") (pin "1") (pinfunction "1_1") (pintype "passive"))
      (node (ref "R25") (pin "1") (pinfunction "1_1") (pintype "passive"))
      (node (ref "R26") (pin "1") (pinfunction "1_1") (pintype "passive"))
      (node (ref "R27") (pin "1") (pinfunction "1_1") (pintype "passive"))
      (node (ref "R28") (pin "1") (pinfunction "1_1") (pintype "passive"))
      (node (ref "R29") (pin "1") (pinfunction "1_1") (pintype "passive"))
      (node (ref "R30") (pin "1") (pinfunction "1_1") (pintype "passive"))
      (node (ref "R31") (pin "1") (pinfunction "1_1") (pintype "passive"))
      (node (ref "R32") (pin "1") (pinfunction "1_1") (pintype "passive"))
      (node (ref "R33") (pin "1") (pinfunction "1_1") (pintype "passive"))
      (node (ref "R34") (pin "1") (pinfunction "1_1") (pintype "passive"))
      (node (ref "R35") (pin "1") (pinfunction "1_1") (pintype "passive"))
      (node (ref "R36") (pin "1") (pinfunction "1_1") (pintype "passive"))
      (node (ref "R37") (pin "1") (pinfunction "1_1") (pintype "passive"))
      (node (ref "R38") (pin "1") (pinfunction "1_1") (pintype "passive"))
      (node (ref "R39") (pin "1") (pinfunction "1_1") (pintype "passive"))
      (node (ref "R4") (pin "1") (pinfunction "1_1") (pintype "passive"))
      (node (ref "R40") (pin "1") (pinfunction "1_1") (pintype "passive"))
      (node (ref "R41") (pin "1") (pinfunction "1_1") (pintype "passive"))
      (node (ref "R42") (pin "1") (pinfunction "1_1") (pintype "passive"))
      (node (ref "R43") (pin "1") (pinfunction "1_1") (pintype "passive"))
      (node (ref "R44") (pin "1") (pinfunction "1_1") (pintype "passive"))
      (node (ref "R45") (pin "1") (pinfunction "1_1") (pintype "passive"))
      (node (ref "R46") (pin "1") (pinfunction "1_1") (pintype "passive"))
      (node (ref "R47") (pin "1") (pinfunction "1_1") (pintype "passive"))
      (node (ref "R48") (pin "1") (pinfunction "1_1") (pintype "passive"))
      (node (ref "R49") (pin "1") (pinfunction "1_1") (pintype "passive"))
      (node (ref "R5") (pin "1") (pinfunction "1_1") (pintype "passive"))
      (node (ref "R50") (pin "1") (pinfunction "1_1") (pintype "passive"))
      (node (ref "R52") (pin "1") (pinfunction "1_1") (pintype "passive"))
      (node (ref "R53") (pin "1") (pinfunction "1_1") (pintype "passive"))
      (node (ref "R54") (pin "1") (pinfunction "1_1") (pintype "passive"))
      (node (ref "R55") (pin "1") (pinfunction "1_1") (pintype "passive"))
      (node (ref "R56") (pin "1") (pinfunction "1_1") (pintype "passive"))
      (node (ref "R57") (pin "1") (pinfunction "1_1") (pintype "passive"))
      (node (ref "R58") (pin "1") (pinfunction "1_1") (pintype "passive"))
      (node (ref "R59") (pin "1") (pinfunction "1_1") (pintype "passive"))
      (node (ref "R6") (pin "1") (pinfunction "1_1") (pintype "passive"))
      (node (ref "R60") (pin "1") (pinfunction "1_1") (pintype "passive"))
      (node (ref "R61") (pin "1") (pinfunction "1_1") (pintype "passive"))
      (node (ref "R62") (pin "1") (pinfunction "1_1") (pintype "passive"))
      (node (ref "R63") (pin "1") (pinfunction "1_1") (pintype "passive"))
      (node (ref "R64") (pin "1") (pinfunction "1_1") (pintype "passive"))
      (node (ref "R65") (pin "1") (pinfunction "1_1") (pintype "passive"))
      (node (ref "R66") (pin "1") (pinfunction "1_1") (pintype "passive"))
      (node (ref "R67") (pin "1") (pinfunction "1_1") (pintype "passive"))
      (node (ref "R68") (pin "1") (pinfunction "1_1") (pintype "passive"))
      (node (ref "R69") (pin "1") (pinfunction "1_1") (pintype "passive"))
      (node (ref "R7") (pin "1") (pinfunction "1_1") (pintype "passive"))
      (node (ref "R70") (pin "1") (pinfunction "1_1") (pintype "passive"))
      (node (ref "R71") (pin "1") (pinfunction "1_1") (pintype "passive"))
      (node (ref "R72") (pin "1") (pinfunction "1_1") (pintype "passive"))
      (node (ref "R73") (pin "1") (pinfunction "1_1") (pintype "passive"))
      (node (ref "R74") (pin "1") (pinfunction "1_1") (pintype "passive"))
      (node (ref "R75") (pin "1") (pinfunction "1_1") (pintype "passive"))
      (node (ref "R76") (pin "1") (pinfunction "1_1") (pintype "passive"))
      (node (ref "R77") (pin "1") (pinfunction "1_1") (pintype "passive"))
      (node (ref "R78") (pin "1") (pinfunction "1_1") (pintype "passive"))
      (node (ref "R79") (pin "1") (pinfunction "1_1") (pintype "passive"))
      (node (ref "R8") (pin "1") (pinfunction "1_1") (pintype "passive"))
      (node (ref "R80") (pin "1") (pinfunction "1_1") (pintype "passive"))
      (node (ref "R81") (pin "1") (pinfunction "1_1") (pintype "passive"))
      (node (ref "R82") (pin "1") (pinfunction "1_1") (pintype "passive"))
      (node (ref "R83") (pin "1") (pinfunction "1_1") (pintype "passive"))
      (node (ref "R84") (pin "1") (pinfunction "1_1") (pintype "passive"))
      (node (ref "R85") (pin "1") (pinfunction "1_1") (pintype "passive"))
      (node (ref "R86") (pin "1") (pinfunction "1_1") (pintype "passive"))
      (node (ref "R87") (pin "1") (pinfunction "1_1") (pintype "passive"))
      (node (ref "R88") (pin "1") (pinfunction "1_1") (pintype "passive"))
      (node (ref "R89") (pin "1") (pinfunction "1_1") (pintype "passive"))
      (node (ref "R9") (pin "1") (pinfunction "1_1") (pintype "passive"))
      (node (ref "R90") (pin "1") (pinfunction "1_1") (pintype "passive"))
      (node (ref "R91") (pin "1") (pinfunction "1_1") (pintype "passive"))
      (node (ref "R92") (pin "1") (pinfunction "1_1") (pintype "passive"))
      (node (ref "R93") (pin "1") (pinfunction "1_1") (pintype "passive"))
      (node (ref "R94") (pin "1") (pinfunction "1_1") (pintype "passive"))
      (node (ref "U1") (pin "14") (pinfunction "GND1_14") (pintype "power_in"))
      (node (ref "U1") (pin "20") (pinfunction "GND3_20") (pintype "power_in"))
      (node (ref "U1") (pin "26") (pinfunction "GND2_26") (pintype "power_in"))
      (node (ref "U10") (pin "4") (pinfunction "~{E1}_4") (pintype "input"))
      (node (ref "U10") (pin "5") (pinfunction "~{E2}_5") (pintype "input"))
      (node (ref "U10") (pin "8") (pinfunction "GND_8") (pintype "passive"))
      (node (ref "U11") (pin "4") (pinfunction "~{E1}_4") (pintype "input"))
      (node (ref "U11") (pin "5") (pinfunction "~{E2}_5") (pintype "input"))
      (node (ref "U11") (pin "8") (pinfunction "GND_8") (pintype "passive"))
      (node (ref "U12") (pin "4") (pinfunction "~{E1}_4") (pintype "input"))
      (node (ref "U12") (pin "5") (pinfunction "~{E2}_5") (pintype "input"))
      (node (ref "U12") (pin "8") (pinfunction "GND_8") (pintype "passive"))
      (node (ref "U13") (pin "4") (pinfunction "~{E1}_4") (pintype "input"))
      (node (ref "U13") (pin "5") (pinfunction "~{E2}_5") (pintype "input"))
      (node (ref "U13") (pin "8") (pinfunction "GND_8") (pintype "passive"))
      (node (ref "U14") (pin "4") (pinfunction "~{E1}_4") (pintype "input"))
      (node (ref "U14") (pin "5") (pinfunction "~{E2}_5") (pintype "input"))
      (node (ref "U14") (pin "8") (pinfunction "GND_8") (pintype "passive"))
      (node (ref "U15") (pin "4") (pinfunction "~{E1}_4") (pintype "input"))
      (node (ref "U15") (pin "5") (pinfunction "~{E2}_5") (pintype "input"))
      (node (ref "U15") (pin "8") (pinfunction "GND_8") (pintype "passive"))
      (node (ref "U16") (pin "4") (pinfunction "~{E1}_4") (pintype "input"))
      (node (ref "U16") (pin "5") (pinfunction "~{E2}_5") (pintype "input"))
      (node (ref "U16") (pin "8") (pinfunction "GND_8") (pintype "passive"))
      (node (ref "U17") (pin "4") (pinfunction "~{E1}_4") (pintype "input"))
      (node (ref "U17") (pin "5") (pinfunction "~{E2}_5") (pintype "input"))
      (node (ref "U17") (pin "8") (pinfunction "GND_8") (pintype "passive"))
      (node (ref "U18") (pin "4") (pinfunction "~{E1}_4") (pintype "input"))
      (node (ref "U18") (pin "5") (pinfunction "~{E2}_5") (pintype "input"))
      (node (ref "U18") (pin "8") (pinfunction "GND_8") (pintype "passive"))
      (node (ref "U19") (pin "4") (pinfunction "~{E1}_4") (pintype "input"))
      (node (ref "U19") (pin "5") (pinfunction "~{E2}_5") (pintype "input"))
      (node (ref "U19") (pin "8") (pinfunction "GND_8") (pintype "passive"))
      (node (ref "U2") (pin "4") (pinfunction "~{E1}_4") (pintype "input"))
      (node (ref "U2") (pin "5") (pinfunction "~{E2}_5") (pintype "input"))
      (node (ref "U2") (pin "8") (pinfunction "GND_8") (pintype "passive"))
      (node (ref "U3") (pin "4") (pinfunction "~{E1}_4") (pintype "input"))
      (node (ref "U3") (pin "5") (pinfunction "~{E2}_5") (pintype "input"))
      (node (ref "U3") (pin "8") (pinfunction "GND_8") (pintype "passive"))
      (node (ref "U4") (pin "4") (pinfunction "~{E1}_4") (pintype "input"))
      (node (ref "U4") (pin "5") (pinfunction "~{E2}_5") (pintype "input"))
      (node (ref "U4") (pin "8") (pinfunction "GND_8") (pintype "passive"))
      (node (ref "U5") (pin "4") (pinfunction "~{E1}_4") (pintype "input"))
      (node (ref "U5") (pin "5") (pinfunction "~{E2}_5") (pintype "input"))
      (node (ref "U5") (pin "8") (pinfunction "GND_8") (pintype "passive"))
      (node (ref "U6") (pin "4") (pinfunction "~{E1}_4") (pintype "input"))
      (node (ref "U6") (pin "5") (pinfunction "~{E2}_5") (pintype "input"))
      (node (ref "U6") (pin "8") (pinfunction "GND_8") (pintype "passive"))
      (node (ref "U7") (pin "4") (pinfunction "~{E1}_4") (pintype "input"))
      (node (ref "U7") (pin "5") (pinfunction "~{E2}_5") (pintype "input"))
      (node (ref "U7") (pin "8") (pinfunction "GND_8") (pintype "passive"))
      (node (ref "U8") (pin "4") (pinfunction "~{E1}_4") (pintype "input"))
      (node (ref "U8") (pin "5") (pinfunction "~{E2}_5") (pintype "input"))
      (node (ref "U8") (pin "8") (pinfunction "GND_8") (pintype "passive"))
      (node (ref "U9") (pin "4") (pinfunction "~{E1}_4") (pintype "input"))
      (node (ref "U9") (pin "5") (pinfunction "~{E2}_5") (pintype "input"))
      (node (ref "U9") (pin "8") (pinfunction "GND_8") (pintype "passive"))
      (node (ref "VOLTAGE_REG") (pin "3") (pinfunction "GND_3") (pintype "bidirectional"))
      (node (ref "VOLTAGE_REG") (pin "6") (pinfunction "TAB_6") (pintype "bidirectional"))
    )
    (net (code "8") (name "MUX_GROUP_01") (class "Default")
      (node (ref "U1") (pin "33") (pinfunction "IO0_33") (pintype "bidirectional"))
      (node (ref "U2") (pin "6") (pinfunction "E3_6") (pintype "input"))
    )
    (net (code "9") (name "MUX_GROUP_02") (class "Default")
      (node (ref "U1") (pin "34") (pinfunction "IO2_34") (pintype "bidirectional"))
      (node (ref "U3") (pin "6") (pinfunction "E3_6") (pintype "input"))
    )
    (net (code "10") (name "MUX_GROUP_03") (class "Default")
      (node (ref "U1") (pin "29") (pinfunction "IO5_29") (pintype "bidirectional"))
      (node (ref "U4") (pin "6") (pinfunction "E3_6") (pintype "input"))
    )
    (net (code "11") (name "MUX_GROUP_04") (class "Default")
      (node (ref "U1") (pin "13") (pinfunction "IO12_13") (pintype "bidirectional"))
      (node (ref "U5") (pin "6") (pinfunction "E3_6") (pintype "input"))
    )
    (net (code "12") (name "MUX_GROUP_05") (class "Default")
      (node (ref "U1") (pin "12") (pinfunction "IO14_12") (pintype "bidirectional"))
      (node (ref "U6") (pin "6") (pinfunction "E3_6") (pintype "input"))
    )
    (net (code "13") (name "MUX_GROUP_06") (class "Default")
      (node (ref "U1") (pin "35") (pinfunction "IO15_35") (pintype "bidirectional"))
      (node (ref "U7") (pin "6") (pinfunction "E3_6") (pintype "input"))
    )
    (net (code "14") (name "MUX_GROUP_07") (class "Default")
      (node (ref "U1") (pin "31") (pinfunction "IO16_31") (pintype "bidirectional"))
      (node (ref "U8") (pin "6") (pinfunction "E3_6") (pintype "input"))
    )
    (net (code "15") (name "MUX_GROUP_08") (class "Default")
      (node (ref "U1") (pin "30") (pinfunction "IO17_30") (pintype "bidirectional"))
      (node (ref "U9") (pin "6") (pinfunction "E3_6") (pintype "input"))
    )
    (net (code "16") (name "MUX_GROUP_09") (class "Default")
      (node (ref "U1") (pin "28") (pinfunction "IO18_28") (pintype "bidirectional"))
      (node (ref "U10") (pin "6") (pinfunction "E3_6") (pintype "input"))
    )
    (net (code "17") (name "MUX_GROUP_10") (class "Default")
      (node (ref "U1") (pin "27") (pinfunction "IO19_27") (pintype "bidirectional"))
      (node (ref "U11") (pin "6") (pinfunction "E3_6") (pintype "input"))
    )
    (net (code "18") (name "MUX_GROUP_11") (class "Default")
      (node (ref "U1") (pin "25") (pinfunction "IO21_25") (pintype "bidirectional"))
      (node (ref "U12") (pin "6") (pinfunction "E3_6") (pintype "input"))
    )
    (net (code "19") (name "MUX_GROUP_12") (class "Default")
      (node (ref "U1") (pin "22") (pinfunction "IO22_22") (pintype "bidirectional"))
      (node (ref "U13") (pin "6") (pinfunction "E3_6") (pintype "input"))
    )
    (net (code "20") (name "MUX_GROUP_13") (class "Default")
      (node (ref "U1") (pin "21") (pinfunction "IO23_21") (pintype "bidirectional"))
      (node (ref "U14") (pin "6") (pinfunction "E3_6") (pintype "input"))
    )
    (net (code "21") (name "MUX_GROUP_14") (class "Default")
      (node (ref "U1") (pin "9") (pinfunction "IO25_9") (pintype "bidirectional"))
      (node (ref "U15") (pin "6") (pinfunction "E3_6") (pintype "input"))
    )
    (net (code "22") (name "MUX_GROUP_15") (class "Default")
      (node (ref "U1") (pin "10") (pinfunction "IO26_10") (pintype "bidirectional"))
      (node (ref "U16") (pin "6") (pinfunction "E3_6") (pintype "input"))
    )
    (net (code "23") (name "MUX_GROUP_16") (class "Default")
      (node (ref "U1") (pin "11") (pinfunction "IO27_11") (pintype "bidirectional"))
      (node (ref "U17") (pin "6") (pinfunction "E3_6") (pintype "input"))
    )
    (net (code "24") (name "MUX_GROUP_17") (class "Default")
      (node (ref "U1") (pin "7") (pinfunction "IO32_7") (pintype "bidirectional"))
      (node (ref "U18") (pin "6") (pinfunction "E3_6") (pintype "input"))
    )
    (net (code "25") (name "MUX_GROUP_18") (class "Default")
      (node (ref "U1") (pin "8") (pinfunction "IO33_8") (pintype "bidirectional"))
      (node (ref "U19") (pin "6") (pinfunction "E3_6") (pintype "input"))
    )
    (net (code "26") (name "Net-(555_TIMER_CLOCK_GEN1-CONTROL_VOLTAGE)") (class "Default")
      (node (ref "555_TIMER_CLOCK_GEN1") (pin "5") (pinfunction "CONTROL_VOLTAGE_5") (pintype "bidirectional"))
      (node (ref "C6") (pin "1") (pinfunction "1_1") (pintype "passive"))
    )
    (net (code "27") (name "Net-(555_TIMER_CLOCK_GEN1-DISCHARGE)") (class "Default")
      (node (ref "555_TIMER_CLOCK_GEN1") (pin "7") (pinfunction "DISCHARGE_7") (pintype "bidirectional"))
      (node (ref "RA1") (pin "1") (pinfunction "1_1") (pintype "passive"))
      (node (ref "RB1") (pin "2") (pinfunction "2_2") (pintype "passive"))
    )
    (net (code "28") (name "Net-(555_TIMER_CLOCK_GEN1-OUTPUT)") (class "Default")
      (node (ref "555_TIMER_CLOCK_GEN1") (pin "3") (pinfunction "OUTPUT_3") (pintype "bidirectional"))
      (node (ref "R3") (pin "2") (pinfunction "2_2") (pintype "passive"))
    )
    (net (code "29") (name "Net-(555_TIMER_CLOCK_GEN1-THRESHOLD)") (class "Default")
      (node (ref "555_TIMER_CLOCK_GEN1") (pin "2") (pinfunction "TRIGGER_2") (pintype "bidirectional"))
      (node (ref "555_TIMER_CLOCK_GEN1") (pin "6") (pinfunction "THRESHOLD_6") (pintype "bidirectional"))
      (node (ref "C7") (pin "1") (pinfunction "1_1") (pintype "passive"))
      (node (ref "RB1") (pin "1") (pinfunction "1_1") (pintype "passive"))
    )
    (net (code "30") (name "Net-(B1G1-A)") (class "Default")
      (node (ref "B1G1") (pin "2") (pinfunction "A_2") (pintype "bidirectional"))
      (node (ref "IC5") (pin "2") (pinfunction "1Y_2") (pintype "bidirectional"))
    )
    (net (code "31") (name "Net-(B1G2-A)") (class "Default")
      (node (ref "B1G2") (pin "2") (pinfunction "A_2") (pintype "bidirectional"))
      (node (ref "IC7") (pin "2") (pinfunction "1Y_2") (pintype "bidirectional"))
    )
    (net (code "32") (name "Net-(B1G4-A)") (class "Default")
      (node (ref "B1G4") (pin "2") (pinfunction "A_2") (pintype "bidirectional"))
      (node (ref "IC11") (pin "2") (pinfunction "1Y_2") (pintype "bidirectional"))
    )
    (net (code "33") (name "Net-(B1G5-A)") (class "Default")
      (node (ref "B1G5") (pin "2") (pinfunction "A_2") (pintype "bidirectional"))
      (node (ref "IC13") (pin "2") (pinfunction "1Y_2") (pintype "bidirectional"))
    )
    (net (code "34") (name "Net-(B1G13-A)") (class "Default")
      (node (ref "B1G13") (pin "2") (pinfunction "A_2") (pintype "bidirectional"))
      (node (ref "IC29") (pin "2") (pinfunction "1Y_2") (pintype "bidirectional"))
    )
    (net (code "35") (name "Net-(B1G16-A)") (class "Default")
      (node (ref "B1G16") (pin "2") (pinfunction "A_2") (pintype "bidirectional"))
      (node (ref "IC35") (pin "2") (pinfunction "1Y_2") (pintype "bidirectional"))
    )
    (net (code "36") (name "Net-(B2G1-A)") (class "Default")
      (node (ref "B2G1") (pin "2") (pinfunction "A_2") (pintype "bidirectional"))
      (node (ref "IC5") (pin "4") (pinfunction "2Y_4") (pintype "bidirectional"))
    )
    (net (code "37") (name "Net-(B2G2-A)") (class "Default")
      (node (ref "B2G2") (pin "2") (pinfunction "A_2") (pintype "bidirectional"))
      (node (ref "IC7") (pin "4") (pinfunction "2Y_4") (pintype "bidirectional"))
    )
    (net (code "38") (name "Net-(B2G4-A)") (class "Default")
      (node (ref "B2G4") (pin "2") (pinfunction "A_2") (pintype "bidirectional"))
      (node (ref "IC11") (pin "4") (pinfunction "2Y_4") (pintype "bidirectional"))
    )
    (net (code "39") (name "Net-(B2G5-A)") (class "Default")
      (node (ref "B2G5") (pin "2") (pinfunction "A_2") (pintype "bidirectional"))
      (node (ref "IC13") (pin "4") (pinfunction "2Y_4") (pintype "bidirectional"))
    )
    (net (code "40") (name "Net-(B2G13-A)") (class "Default")
      (node (ref "B2G13") (pin "2") (pinfunction "A_2") (pintype "bidirectional"))
      (node (ref "IC29") (pin "4") (pinfunction "2Y_4") (pintype "bidirectional"))
    )
    (net (code "41") (name "Net-(B2G16-A)") (class "Default")
      (node (ref "B2G16") (pin "2") (pinfunction "A_2") (pintype "bidirectional"))
      (node (ref "IC35") (pin "4") (pinfunction "2Y_4") (pintype "bidirectional"))
    )
    (net (code "42") (name "Net-(B3G1-A)") (class "Default")
      (node (ref "B3G1") (pin "2") (pinfunction "A_2") (pintype "bidirectional"))
      (node (ref "IC5") (pin "6") (pinfunction "3Y_6") (pintype "bidirectional"))
    )
    (net (code "43") (name "Net-(B3G2-A)") (class "Default")
      (node (ref "B3G2") (pin "2") (pinfunction "A_2") (pintype "bidirectional"))
      (node (ref "IC7") (pin "6") (pinfunction "3Y_6") (pintype "bidirectional"))
    )
    (net (code "44") (name "Net-(B3G4-A)") (class "Default")
      (node (ref "B3G4") (pin "2") (pinfunction "A_2") (pintype "bidirectional"))
      (node (ref "IC11") (pin "6") (pinfunction "3Y_6") (pintype "bidirectional"))
    )
    (net (code "45") (name "Net-(B3G5-A)") (class "Default")
      (node (ref "B3G5") (pin "2") (pinfunction "A_2") (pintype "bidirectional"))
      (node (ref "IC13") (pin "6") (pinfunction "3Y_6") (pintype "bidirectional"))
    )
    (net (code "46") (name "Net-(B3G13-A)") (class "Default")
      (node (ref "B3G13") (pin "2") (pinfunction "A_2") (pintype "bidirectional"))
      (node (ref "IC29") (pin "6") (pinfunction "3Y_6") (pintype "bidirectional"))
    )
    (net (code "47") (name "Net-(B3G16-A)") (class "Default")
      (node (ref "B3G16") (pin "2") (pinfunction "A_2") (pintype "bidirectional"))
      (node (ref "IC35") (pin "6") (pinfunction "3Y_6") (pintype "bidirectional"))
    )
    (net (code "48") (name "Net-(B3G17-A)") (class "Default")
      (node (ref "B3G17") (pin "2") (pinfunction "A_2") (pintype "bidirectional"))
      (node (ref "IC37") (pin "6") (pinfunction "3Y_6") (pintype "bidirectional"))
    )
    (net (code "49") (name "Net-(B4G1-A)") (class "Default")
      (node (ref "B4G1") (pin "2") (pinfunction "A_2") (pintype "bidirectional"))
      (node (ref "IC5") (pin "12") (pinfunction "6Y_12") (pintype "bidirectional"))
    )
    (net (code "50") (name "Net-(B4G2-A)") (class "Default")
      (node (ref "B4G2") (pin "2") (pinfunction "A_2") (pintype "bidirectional"))
      (node (ref "IC7") (pin "12") (pinfunction "6Y_12") (pintype "bidirectional"))
    )
    (net (code "51") (name "Net-(B4G4-A)") (class "Default")
      (node (ref "B4G4") (pin "2") (pinfunction "A_2") (pintype "bidirectional"))
      (node (ref "IC11") (pin "12") (pinfunction "6Y_12") (pintype "bidirectional"))
    )
    (net (code "52") (name "Net-(B4G5-A)") (class "Default")
      (node (ref "B4G5") (pin "2") (pinfunction "A_2") (pintype "bidirectional"))
      (node (ref "IC13") (pin "12") (pinfunction "6Y_12") (pintype "bidirectional"))
    )
    (net (code "53") (name "Net-(B4G13-A)") (class "Default")
      (node (ref "B4G13") (pin "2") (pinfunction "A_2") (pintype "bidirectional"))
      (node (ref "IC29") (pin "12") (pinfunction "6Y_12") (pintype "bidirectional"))
    )
    (net (code "54") (name "Net-(B4G16-A)") (class "Default")
      (node (ref "B4G16") (pin "2") (pinfunction "A_2") (pintype "bidirectional"))
      (node (ref "IC35") (pin "12") (pinfunction "6Y_12") (pintype "bidirectional"))
    )
    (net (code "55") (name "Net-(B4G17-A)") (class "Default")
      (node (ref "B4G17") (pin "2") (pinfunction "A_2") (pintype "bidirectional"))
      (node (ref "IC37") (pin "12") (pinfunction "6Y_12") (pintype "bidirectional"))
    )
    (net (code "56") (name "Net-(B5G1-A)") (class "Default")
      (node (ref "B5G1") (pin "2") (pinfunction "A_2") (pintype "bidirectional"))
      (node (ref "IC5") (pin "10") (pinfunction "5Y_10") (pintype "bidirectional"))
    )
    (net (code "57") (name "Net-(B5G2-A)") (class "Default")
      (node (ref "B5G2") (pin "2") (pinfunction "A_2") (pintype "bidirectional"))
      (node (ref "IC7") (pin "10") (pinfunction "5Y_10") (pintype "bidirectional"))
    )
    (net (code "58") (name "Net-(B5G4-A)") (class "Default")
      (node (ref "B5G4") (pin "2") (pinfunction "A_2") (pintype "bidirectional"))
      (node (ref "IC11") (pin "10") (pinfunction "5Y_10") (pintype "bidirectional"))
    )
    (net (code "59") (name "Net-(B5G13-A)") (class "Default")
      (node (ref "B5G13") (pin "2") (pinfunction "A_2") (pintype "bidirectional"))
      (node (ref "IC29") (pin "10") (pinfunction "5Y_10") (pintype "bidirectional"))
    )
    (net (code "60") (name "Net-(B5G16-A)") (class "Default")
      (node (ref "B5G16") (pin "2") (pinfunction "A_2") (pintype "bidirectional"))
      (node (ref "IC35") (pin "10") (pinfunction "5Y_10") (pintype "bidirectional"))
    )
    (net (code "61") (name "Net-(B5G17-A)") (class "Default")
      (node (ref "B5G17") (pin "2") (pinfunction "A_2") (pintype "bidirectional"))
      (node (ref "IC37") (pin "10") (pinfunction "5Y_10") (pintype "bidirectional"))
    )
    (net (code "62") (name "Net-(B6G1-A)") (class "Default")
      (node (ref "B6G1") (pin "2") (pinfunction "A_2") (pintype "bidirectional"))
      (node (ref "IC5") (pin "8") (pinfunction "4Y_8") (pintype "bidirectional"))
    )
    (net (code "63") (name "Net-(B6G2-A)") (class "Default")
      (node (ref "B6G2") (pin "2") (pinfunction "A_2") (pintype "bidirectional"))
      (node (ref "IC7") (pin "8") (pinfunction "4Y_8") (pintype "bidirectional"))
    )
    (net (code "64") (name "Net-(B6G4-A)") (class "Default")
      (node (ref "B6G4") (pin "2") (pinfunction "A_2") (pintype "bidirectional"))
      (node (ref "IC11") (pin "8") (pinfunction "4Y_8") (pintype "bidirectional"))
    )
    (net (code "65") (name "Net-(B6G13-A)") (class "Default")
      (node (ref "B6G13") (pin "2") (pinfunction "A_2") (pintype "bidirectional"))
      (node (ref "IC29") (pin "8") (pinfunction "4Y_8") (pintype "bidirectional"))
    )
    (net (code "66") (name "Net-(B6G16-A)") (class "Default")
      (node (ref "B6G16") (pin "2") (pinfunction "A_2") (pintype "bidirectional"))
      (node (ref "IC35") (pin "8") (pinfunction "4Y_8") (pintype "bidirectional"))
    )
    (net (code "67") (name "Net-(B6G17-A)") (class "Default")
      (node (ref "B6G17") (pin "2") (pinfunction "A_2") (pintype "bidirectional"))
      (node (ref "IC37") (pin "8") (pinfunction "4Y_8") (pintype "bidirectional"))
    )
    (net (code "68") (name "Net-(B7G1-A)") (class "Default")
      (node (ref "B7G1") (pin "2") (pinfunction "A_2") (pintype "bidirectional"))
      (node (ref "IC6") (pin "2") (pinfunction "1Y_2") (pintype "bidirectional"))
    )
    (net (code "69") (name "Net-(B7G2-A)") (class "Default")
      (node (ref "B7G2") (pin "2") (pinfunction "A_2") (pintype "bidirectional"))
      (node (ref "IC8") (pin "2") (pinfunction "1Y_2") (pintype "bidirectional"))
    )
    (net (code "70") (name "Net-(B7G4-A)") (class "Default")
      (node (ref "B7G4") (pin "2") (pinfunction "A_2") (pintype "bidirectional"))
      (node (ref "IC12") (pin "2") (pinfunction "1Y_2") (pintype "bidirectional"))
    )
    (net (code "71") (name "Net-(B7G13-A)") (class "Default")
      (node (ref "B7G13") (pin "2") (pinfunction "A_2") (pintype "bidirectional"))
      (node (ref "IC30") (pin "2") (pinfunction "1Y_2") (pintype "bidirectional"))
    )
    (net (code "72") (name "Net-(B7G16-A)") (class "Default")
      (node (ref "B7G16") (pin "2") (pinfunction "A_2") (pintype "bidirectional"))
      (node (ref "IC36") (pin "2") (pinfunction "1Y_2") (pintype "bidirectional"))
    )
    (net (code "73") (name "Net-(B7G17-A)") (class "Default")
      (node (ref "B7G17") (pin "2") (pinfunction "A_2") (pintype "bidirectional"))
      (node (ref "IC38") (pin "2") (pinfunction "1Y_2") (pintype "bidirectional"))
    )
    (net (code "74") (name "Net-(B8G1-A)") (class "Default")
      (node (ref "B8G1") (pin "2") (pinfunction "A_2") (pintype "bidirectional"))
      (node (ref "IC6") (pin "4") (pinfunction "2Y_4") (pintype "bidirectional"))
    )
    (net (code "75") (name "Net-(B8G4-A)") (class "Default")
      (node (ref "B8G4") (pin "2") (pinfunction "A_2") (pintype "bidirectional"))
      (node (ref "IC12") (pin "4") (pinfunction "2Y_4") (pintype "bidirectional"))
    )
    (net (code "76") (name "Net-(B8G13-A)") (class "Default")
      (node (ref "B8G13") (pin "2") (pinfunction "A_2") (pintype "bidirectional"))
      (node (ref "IC30") (pin "4") (pinfunction "2Y_4") (pintype "bidirectional"))
    )
    (net (code "77") (name "Net-(B8G16-A)") (class "Default")
      (node (ref "B8G16") (pin "2") (pinfunction "A_2") (pintype "bidirectional"))
      (node (ref "IC36") (pin "4") (pinfunction "2Y_4") (pintype "bidirectional"))
    )
    (net (code "78") (name "Net-(B8G17-A)") (class "Default")
      (node (ref "B8G17") (pin "2") (pinfunction "A_2") (pintype "bidirectional"))
      (node (ref "IC38") (pin "4") (pinfunction "2Y_4") (pintype "bidirectional"))
    )
    (net (code "79") (name "Net-(G1G7-A)") (class "Default")
      (node (ref "G1G7") (pin "2") (pinfunction "A_2") (pintype "bidirectional"))
      (node (ref "IC17") (pin "2") (pinfunction "1Y_2") (pintype "bidirectional"))
    )
    (net (code "80") (name "Net-(G1G7-K)") (class "Default")
      (node (ref "G1G7") (pin "1") (pinfunction "K_1") (pintype "bidirectional"))
      (node (ref "R22") (pin "2") (pinfunction "2_2") (pintype "passive"))
    )
    (net (code "81") (name "Net-(G1G8-A)") (class "Default")
      (node (ref "G1G8") (pin "2") (pinfunction "A_2") (pintype "bidirectional"))
      (node (ref "IC19") (pin "2") (pinfunction "1Y_2") (pintype "bidirectional"))
    )
    (net (code "82") (name "Net-(G1G8-K)") (class "Default")
      (node (ref "G1G8") (pin "1") (pinfunction "K_1") (pintype "bidirectional"))
      (node (ref "R30") (pin "2") (pinfunction "2_2") (pintype "passive"))
    )
    (net (code "83") (name "Net-(G1G14-A)") (class "Default")
      (node (ref "G1G14") (pin "2") (pinfunction "A_2") (pintype "bidirectional"))
      (node (ref "IC31") (pin "2") (pinfunction "1Y_2") (pintype "bidirectional"))
    )
    (net (code "84") (name "Net-(G1G14-K)") (class "Default")
      (node (ref "G1G14") (pin "1") (pinfunction "K_1") (pintype "bidirectional"))
      (node (ref "R68") (pin "2") (pinfunction "2_2") (pintype "passive"))
    )
    (net (code "85") (name "Net-(G1G18-A)") (class "Default")
      (node (ref "G1G18") (pin "2") (pinfunction "A_2") (pintype "bidirectional"))
      (node (ref "IC39") (pin "2") (pinfunction "1Y_2") (pintype "bidirectional"))
    )
    (net (code "86") (name "Net-(G1G18-K)") (class "Default")
      (node (ref "G1G18") (pin "1") (pinfunction "K_1") (pintype "bidirectional"))
      (node (ref "R86") (pin "2") (pinfunction "2_2") (pintype "passive"))
    )
    (net (code "87") (name "Net-(G2G7-A)") (class "Default")
      (node (ref "G2G7") (pin "2") (pinfunction "A_2") (pintype "bidirectional"))
      (node (ref "IC17") (pin "4") (pinfunction "2Y_4") (pintype "bidirectional"))
    )
    (net (code "88") (name "Net-(G2G7-K)") (class "Default")
      (node (ref "G2G7") (pin "1") (pinfunction "K_1") (pintype "bidirectional"))
      (node (ref "R23") (pin "2") (pinfunction "2_2") (pintype "passive"))
    )
    (net (code "89") (name "Net-(G2G8-A)") (class "Default")
      (node (ref "G2G8") (pin "2") (pinfunction "A_2") (pintype "bidirectional"))
      (node (ref "IC19") (pin "4") (pinfunction "2Y_4") (pintype "bidirectional"))
    )
    (net (code "90") (name "Net-(G2G8-K)") (class "Default")
      (node (ref "G2G8") (pin "1") (pinfunction "K_1") (pintype "bidirectional"))
      (node (ref "R31") (pin "2") (pinfunction "2_2") (pintype "passive"))
    )
    (net (code "91") (name "Net-(G2G14-A)") (class "Default")
      (node (ref "G2G14") (pin "2") (pinfunction "A_2") (pintype "bidirectional"))
      (node (ref "IC31") (pin "4") (pinfunction "2Y_4") (pintype "bidirectional"))
    )
    (net (code "92") (name "Net-(G2G14-K)") (class "Default")
      (node (ref "G2G14") (pin "1") (pinfunction "K_1") (pintype "bidirectional"))
      (node (ref "R69") (pin "2") (pinfunction "2_2") (pintype "passive"))
    )
    (net (code "93") (name "Net-(G2G18-A)") (class "Default")
      (node (ref "G2G18") (pin "2") (pinfunction "A_2") (pintype "bidirectional"))
      (node (ref "IC39") (pin "4") (pinfunction "2Y_4") (pintype "bidirectional"))
    )
    (net (code "94") (name "Net-(G2G18-K)") (class "Default")
      (node (ref "G2G18") (pin "1") (pinfunction "K_1") (pintype "bidirectional"))
      (node (ref "R87") (pin "2") (pinfunction "2_2") (pintype "passive"))
    )
    (net (code "95") (name "Net-(G3G7-A)") (class "Default")
      (node (ref "G3G7") (pin "2") (pinfunction "A_2") (pintype "bidirectional"))
      (node (ref "IC17") (pin "6") (pinfunction "3Y_6") (pintype "bidirectional"))
    )
    (net (code "96") (name "Net-(G3G7-K)") (class "Default")
      (node (ref "G3G7") (pin "1") (pinfunction "K_1") (pintype "bidirectional"))
      (node (ref "R24") (pin "2") (pinfunction "2_2") (pintype "passive"))
    )
    (net (code "97") (name "Net-(G3G8-A)") (class "Default")
      (node (ref "G3G8") (pin "2") (pinfunction "A_2") (pintype "bidirectional"))
      (node (ref "IC19") (pin "6") (pinfunction "3Y_6") (pintype "bidirectional"))
    )
    (net (code "98") (name "Net-(G3G8-K)") (class "Default")
      (node (ref "G3G8") (pin "1") (pinfunction "K_1") (pintype "bidirectional"))
      (node (ref "R32") (pin "2") (pinfunction "2_2") (pintype "passive"))
    )
    (net (code "99") (name "Net-(G3G14-A)") (class "Default")
      (node (ref "G3G14") (pin "2") (pinfunction "A_2") (pintype "bidirectional"))
      (node (ref "IC31") (pin "6") (pinfunction "3Y_6") (pintype "bidirectional"))
    )
    (net (code "100") (name "Net-(G3G14-K)") (class "Default")
      (node (ref "G3G14") (pin "1") (pinfunction "K_1") (pintype "bidirectional"))
      (node (ref "R70") (pin "2") (pinfunction "2_2") (pintype "passive"))
    )
    (net (code "101") (name "Net-(G3G18-A)") (class "Default")
      (node (ref "G3G18") (pin "2") (pinfunction "A_2") (pintype "bidirectional"))
      (node (ref "IC39") (pin "6") (pinfunction "3Y_6") (pintype "bidirectional"))
    )
    (net (code "102") (name "Net-(G3G18-K)") (class "Default")
      (node (ref "G3G18") (pin "1") (pinfunction "K_1") (pintype "bidirectional"))
      (node (ref "R88") (pin "2") (pinfunction "2_2") (pintype "passive"))
    )
    (net (code "103") (name "Net-(G4G7-A)") (class "Default")
      (node (ref "G4G7") (pin "2") (pinfunction "A_2") (pintype "bidirectional"))
      (node (ref "IC17") (pin "12") (pinfunction "6Y_12") (pintype "bidirectional"))
    )
    (net (code "104") (name "Net-(G4G7-K)") (class "Default")
      (node (ref "G4G7") (pin "1") (pinfunction "K_1") (pintype "bidirectional"))
      (node (ref "R25") (pin "2") (pinfunction "2_2") (pintype "passive"))
    )
    (net (code "105") (name "Net-(G4G8-A)") (class "Default")
      (node (ref "G4G8") (pin "2") (pinfunction "A_2") (pintype "bidirectional"))
      (node (ref "IC19") (pin "12") (pinfunction "6Y_12") (pintype "bidirectional"))
    )
    (net (code "106") (name "Net-(G4G8-K)") (class "Default")
      (node (ref "G4G8") (pin "1") (pinfunction "K_1") (pintype "bidirectional"))
      (node (ref "R33") (pin "2") (pinfunction "2_2") (pintype "passive"))
    )
    (net (code "107") (name "Net-(G4G14-A)") (class "Default")
      (node (ref "G4G14") (pin "2") (pinfunction "A_2") (pintype "bidirectional"))
      (node (ref "IC31") (pin "12") (pinfunction "6Y_12") (pintype "bidirectional"))
    )
    (net (code "108") (name "Net-(G4G14-K)") (class "Default")
      (node (ref "G4G14") (pin "1") (pinfunction "K_1") (pintype "bidirectional"))
      (node (ref "R71") (pin "2") (pinfunction "2_2") (pintype "passive"))
    )
    (net (code "109") (name "Net-(G4G18-A)") (class "Default")
      (node (ref "G4G18") (pin "2") (pinfunction "A_2") (pintype "bidirectional"))
      (node (ref "IC39") (pin "12") (pinfunction "6Y_12") (pintype "bidirectional"))
    )
    (net (code "110") (name "Net-(G4G18-K)") (class "Default")
      (node (ref "G4G18") (pin "1") (pinfunction "K_1") (pintype "bidirectional"))
      (node (ref "R89") (pin "2") (pinfunction "2_2") (pintype "passive"))
    )
    (net (code "111") (name "Net-(G5G8-A)") (class "Default")
      (node (ref "G5G8") (pin "2") (pinfunction "A_2") (pintype "bidirectional"))
      (node (ref "IC19") (pin "10") (pinfunction "5Y_10") (pintype "bidirectional"))
    )
    (net (code "112") (name "Net-(G5G8-K)") (class "Default")
      (node (ref "G5G8") (pin "1") (pinfunction "K_1") (pintype "bidirectional"))
      (node (ref "R34") (pin "2") (pinfunction "2_2") (pintype "passive"))
    )
    (net (code "113") (name "Net-(G5G14-A)") (class "Default")
      (node (ref "G5G14") (pin "2") (pinfunction "A_2") (pintype "bidirectional"))
      (node (ref "IC31") (pin "10") (pinfunction "5Y_10") (pintype "bidirectional"))
    )
    (net (code "114") (name "Net-(G5G14-K)") (class "Default")
      (node (ref "G5G14") (pin "1") (pinfunction "K_1") (pintype "bidirectional"))
      (node (ref "R72") (pin "2") (pinfunction "2_2") (pintype "passive"))
    )
    (net (code "115") (name "Net-(G5G18-A)") (class "Default")
      (node (ref "G5G18") (pin "2") (pinfunction "A_2") (pintype "bidirectional"))
      (node (ref "IC39") (pin "10") (pinfunction "5Y_10") (pintype "bidirectional"))
    )
    (net (code "116") (name "Net-(G5G18-K)") (class "Default")
      (node (ref "G5G18") (pin "1") (pinfunction "K_1") (pintype "bidirectional"))
      (node (ref "R90") (pin "2") (pinfunction "2_2") (pintype "passive"))
    )
    (net (code "117") (name "Net-(G6G5-A)") (class "Default")
      (node (ref "G6G5") (pin "2") (pinfunction "A_2") (pintype "bidirectional"))
      (node (ref "IC13") (pin "8") (pinfunction "4Y_8") (pintype "bidirectional"))
    )
    (net (code "118") (name "Net-(G6G5-K)") (class "Default")
      (node (ref "G6G5") (pin "1") (pinfunction "K_1") (pintype "bidirectional"))
      (node (ref "R11") (pin "2") (pinfunction "2_2") (pintype "passive"))
    )
    (net (code "119") (name "Net-(G6G14-A)") (class "Default")
      (node (ref "G6G14") (pin "2") (pinfunction "A_2") (pintype "bidirectional"))
      (node (ref "IC31") (pin "8") (pinfunction "4Y_8") (pintype "bidirectional"))
    )
    (net (code "120") (name "Net-(G6G14-K)") (class "Default")
      (node (ref "G6G14") (pin "1") (pinfunction "K_1") (pintype "bidirectional"))
      (node (ref "R73") (pin "2") (pinfunction "2_2") (pintype "passive"))
    )
    (net (code "121") (name "Net-(G6G18-A)") (class "Default")
      (node (ref "G6G18") (pin "2") (pinfunction "A_2") (pintype "bidirectional"))
      (node (ref "IC39") (pin "8") (pinfunction "4Y_8") (pintype "bidirectional"))
    )
    (net (code "122") (name "Net-(G6G18-K)") (class "Default")
      (node (ref "G6G18") (pin "1") (pinfunction "K_1") (pintype "bidirectional"))
      (node (ref "R91") (pin "2") (pinfunction "2_2") (pintype "passive"))
    )
    (net (code "123") (name "Net-(G7G5-A)") (class "Default")
      (node (ref "G7G5") (pin "2") (pinfunction "A_2") (pintype "bidirectional"))
      (node (ref "IC14") (pin "2") (pinfunction "1Y_2") (pintype "bidirectional"))
    )
    (net (code "124") (name "Net-(G7G5-K)") (class "Default")
      (node (ref "G7G5") (pin "1") (pinfunction "K_1") (pintype "bidirectional"))
      (node (ref "R12") (pin "2") (pinfunction "2_2") (pintype "passive"))
    )
    (net (code "125") (name "Net-(G7G7-A)") (class "Default")
      (node (ref "G7G7") (pin "2") (pinfunction "A_2") (pintype "bidirectional"))
      (node (ref "IC18") (pin "2") (pinfunction "1Y_2") (pintype "bidirectional"))
    )
    (net (code "126") (name "Net-(G7G7-K)") (class "Default")
      (node (ref "G7G7") (pin "1") (pinfunction "K_1") (pintype "bidirectional"))
      (node (ref "R28") (pin "2") (pinfunction "2_2") (pintype "passive"))
    )
    (net (code "127") (name "Net-(G7G8-A)") (class "Default")
      (node (ref "G7G8") (pin "2") (pinfunction "A_2") (pintype "bidirectional"))
      (node (ref "IC20") (pin "2") (pinfunction "1Y_2") (pintype "bidirectional"))
    )
    (net (code "128") (name "Net-(G7G8-K)") (class "Default")
      (node (ref "G7G8") (pin "1") (pinfunction "K_1") (pintype "bidirectional"))
      (node (ref "R36") (pin "2") (pinfunction "2_2") (pintype "passive"))
    )
    (net (code "129") (name "Net-(G7G14-A)") (class "Default")
      (node (ref "G7G14") (pin "2") (pinfunction "A_2") (pintype "bidirectional"))
      (node (ref "IC32") (pin "2") (pinfunction "1Y_2") (pintype "bidirectional"))
    )
    (net (code "130") (name "Net-(G7G14-K)") (class "Default")
      (node (ref "G7G14") (pin "1") (pinfunction "K_1") (pintype "bidirectional"))
      (node (ref "R74") (pin "2") (pinfunction "2_2") (pintype "passive"))
    )
    (net (code "131") (name "Net-(G7G18-A)") (class "Default")
      (node (ref "G7G18") (pin "2") (pinfunction "A_2") (pintype "bidirectional"))
      (node (ref "IC40") (pin "2") (pinfunction "1Y_2") (pintype "bidirectional"))
    )
    (net (code "132") (name "Net-(G7G18-K)") (class "Default")
      (node (ref "G7G18") (pin "1") (pinfunction "K_1") (pintype "bidirectional"))
      (node (ref "R92") (pin "2") (pinfunction "2_2") (pintype "passive"))
    )
    (net (code "133") (name "Net-(G8G5-A)") (class "Default")
      (node (ref "G8G5") (pin "2") (pinfunction "A_2") (pintype "bidirectional"))
      (node (ref "IC14") (pin "4") (pinfunction "2Y_4") (pintype "bidirectional"))
    )
    (net (code "134") (name "Net-(G8G5-K)") (class "Default")
      (node (ref "G8G5") (pin "1") (pinfunction "K_1") (pintype "bidirectional"))
      (node (ref "R13") (pin "2") (pinfunction "2_2") (pintype "passive"))
    )
    (net (code "135") (name "Net-(G8G14-A)") (class "Default")
      (node (ref "G8G14") (pin "2") (pinfunction "A_2") (pintype "bidirectional"))
      (node (ref "IC32") (pin "4") (pinfunction "2Y_4") (pintype "bidirectional"))
    )
    (net (code "136") (name "Net-(G8G14-K)") (class "Default")
      (node (ref "G8G14") (pin "1") (pinfunction "K_1") (pintype "bidirectional"))
      (node (ref "R75") (pin "2") (pinfunction "2_2") (pintype "passive"))
    )
    (net (code "137") (name "Net-(G8G18-A)") (class "Default")
      (node (ref "G8G18") (pin "2") (pinfunction "A_2") (pintype "bidirectional"))
      (node (ref "IC40") (pin "4") (pinfunction "2Y_4") (pintype "bidirectional"))
    )
    (net (code "138") (name "Net-(G8G18-K)") (class "Default")
      (node (ref "G8G18") (pin "1") (pinfunction "K_1") (pintype "bidirectional"))
      (node (ref "R93") (pin "2") (pinfunction "2_2") (pintype "passive"))
    )
    (net (code "139") (name "Net-(IC2-1Y)") (class "Default")
      (node (ref "IC2") (pin "2") (pinfunction "1Y_2") (pintype "bidirectional"))
      (node (ref "IC3") (pin "2") (pinfunction "1B_2") (pintype "bidirectional"))
    )
    (net (code "140") (name "Net-(IC2-2Y)") (class "Default")
      (node (ref "IC2") (pin "4") (pinfunction "2Y_4") (pintype "bidirectional"))
      (node (ref "IC3") (pin "5") (pinfunction "2B_5") (pintype "bidirectional"))
    )
    (net (code "141") (name "Net-(IC3-1Y)") (class "Default")
      (node (ref "IC3") (pin "10") (pinfunction "3B_10") (pintype "bidirectional"))
      (node (ref "IC3") (pin "3") (pinfunction "1Y_3") (pintype "bidirectional"))
    )
    (net (code "142") (name "Net-(IC3-2Y)") (class "Default")
      (node (ref "IC3") (pin "6") (pinfunction "2Y_6") (pintype "bidirectional"))
      (node (ref "IC3") (pin "9") (pinfunction "3A_9") (pintype "bidirectional"))
    )
    (net (code "143") (name "Net-(IC4-1A)") (class "Default")
      (node (ref "IC4") (pin "1") (pinfunction "1A_1") (pintype "bidirectional"))
      (node (ref "JP3") (pin "1") (pinfunction "1_1") (pintype "passive"))
    )
    (net (code "144") (name "Net-(IC4-1Y)") (class "Default")
      (node (ref "IC4") (pin "10") (pinfunction "3B_10") (pintype "bidirectional"))
      (node (ref "IC4") (pin "3") (pinfunction "1Y_3") (pintype "bidirectional"))
    )
    (net (code "145") (name "Net-(IC4-2Y)") (class "Default")
      (node (ref "IC4") (pin "6") (pinfunction "2Y_6") (pintype "bidirectional"))
      (node (ref "IC4") (pin "9") (pinfunction "3A_9") (pintype "bidirectional"))
    )
    (net (code "146") (name "Net-(IC5-1A)") (class "Default")
      (node (ref "IC5") (pin "1") (pinfunction "1A_1") (pintype "bidirectional"))
      (node (ref "U2") (pin "15") (pinfunction "~{O0}_15") (pintype "output"))
    )
    (net (code "147") (name "Net-(IC5-2A)") (class "Default")
      (node (ref "IC5") (pin "3") (pinfunction "2A_3") (pintype "bidirectional"))
      (node (ref "U2") (pin "14") (pinfunction "~{O1}_14") (pintype "output"))
    )
    (net (code "148") (name "Net-(IC5-3A)") (class "Default")
      (node (ref "IC5") (pin "5") (pinfunction "3A_5") (pintype "bidirectional"))
      (node (ref "U2") (pin "13") (pinfunction "~{O2}_13") (pintype "output"))
    )
    (net (code "149") (name "Net-(IC5-4A)") (class "Default")
      (node (ref "IC5") (pin "9") (pinfunction "4A_9") (pintype "bidirectional"))
      (node (ref "U2") (pin "10") (pinfunction "~{O5}_10") (pintype "output"))
    )
    (net (code "150") (name "Net-(IC5-5A)") (class "Default")
      (node (ref "IC5") (pin "11") (pinfunction "5A_11") (pintype "bidirectional"))
      (node (ref "U2") (pin "11") (pinfunction "~{O4}_11") (pintype "output"))
    )
    (net (code "151") (name "Net-(IC5-6A)") (class "Default")
      (node (ref "IC5") (pin "13") (pinfunction "6A_13") (pintype "bidirectional"))
      (node (ref "U2") (pin "12") (pinfunction "~{O3}_12") (pintype "output"))
    )
    (net (code "152") (name "Net-(IC6-1A)") (class "Default")
      (node (ref "IC6") (pin "1") (pinfunction "1A_1") (pintype "bidirectional"))
      (node (ref "U2") (pin "9") (pinfunction "~{O6}_9") (pintype "output"))
    )
    (net (code "153") (name "Net-(IC6-2A)") (class "Default")
      (node (ref "IC6") (pin "3") (pinfunction "2A_3") (pintype "bidirectional"))
      (node (ref "U2") (pin "7") (pinfunction "~{O7}_7") (pintype "output"))
    )
    (net (code "154") (name "Net-(IC7-1A)") (class "Default")
      (node (ref "IC7") (pin "1") (pinfunction "1A_1") (pintype "bidirectional"))
      (node (ref "U3") (pin "15") (pinfunction "~{O0}_15") (pintype "output"))
    )
    (net (code "155") (name "Net-(IC7-2A)") (class "Default")
      (node (ref "IC7") (pin "3") (pinfunction "2A_3") (pintype "bidirectional"))
      (node (ref "U3") (pin "14") (pinfunction "~{O1}_14") (pintype "output"))
    )
    (net (code "156") (name "Net-(IC7-3A)") (class "Default")
      (node (ref "IC7") (pin "5") (pinfunction "3A_5") (pintype "bidirectional"))
      (node (ref "U3") (pin "13") (pinfunction "~{O2}_13") (pintype "output"))
    )
    (net (code "157") (name "Net-(IC7-4A)") (class "Default")
      (node (ref "IC7") (pin "9") (pinfunction "4A_9") (pintype "bidirectional"))
      (node (ref "U3") (pin "10") (pinfunction "~{O5}_10") (pintype "output"))
    )
    (net (code "158") (name "Net-(IC7-5A)") (class "Default")
      (node (ref "IC7") (pin "11") (pinfunction "5A_11") (pintype "bidirectional"))
      (node (ref "U3") (pin "11") (pinfunction "~{O4}_11") (pintype "output"))
    )
    (net (code "159") (name "Net-(IC7-6A)") (class "Default")
      (node (ref "IC7") (pin "13") (pinfunction "6A_13") (pintype "bidirectional"))
      (node (ref "U3") (pin "12") (pinfunction "~{O3}_12") (pintype "output"))
    )
    (net (code "160") (name "Net-(IC8-1A)") (class "Default")
      (node (ref "IC8") (pin "1") (pinfunction "1A_1") (pintype "bidirectional"))
      (node (ref "U3") (pin "9") (pinfunction "~{O6}_9") (pintype "output"))
    )
    (net (code "161") (name "Net-(IC9-1A)") (class "Default")
      (node (ref "IC9") (pin "1") (pinfunction "1A_1") (pintype "bidirectional"))
      (node (ref "U4") (pin "15") (pinfunction "~{O0}_15") (pintype "output"))
    )
    (net (code "162") (name "Net-(IC9-1Y)") (class "Default")
      (node (ref "IC9") (pin "2") (pinfunction "1Y_2") (pintype "bidirectional"))
      (node (ref "R1G3") (pin "2") (pinfunction "A_2") (pintype "bidirectional"))
    )
    (net (code "163") (name "Net-(IC9-2A)") (class "Default")
      (node (ref "IC9") (pin "3") (pinfunction "2A_3") (pintype "bidirectional"))
      (node (ref "U4") (pin "14") (pinfunction "~{O1}_14") (pintype "output"))
    )
    (net (code "164") (name "Net-(IC9-2Y)") (class "Default")
      (node (ref "IC9") (pin "4") (pinfunction "2Y_4") (pintype "bidirectional"))
      (node (ref "R2G3") (pin "2") (pinfunction "A_2") (pintype "bidirectional"))
    )
    (net (code "165") (name "Net-(IC9-3A)") (class "Default")
      (node (ref "IC9") (pin "5") (pinfunction "3A_5") (pintype "bidirectional"))
      (node (ref "U4") (pin "13") (pinfunction "~{O2}_13") (pintype "output"))
    )
    (net (code "166") (name "Net-(IC9-3Y)") (class "Default")
      (node (ref "IC9") (pin "6") (pinfunction "3Y_6") (pintype "bidirectional"))
      (node (ref "R3G3") (pin "2") (pinfunction "A_2") (pintype "bidirectional"))
    )
    (net (code "167") (name "Net-(IC9-4A)") (class "Default")
      (node (ref "IC9") (pin "9") (pinfunction "4A_9") (pintype "bidirectional"))
      (node (ref "U4") (pin "10") (pinfunction "~{O5}_10") (pintype "output"))
    )
    (net (code "168") (name "Net-(IC9-4Y)") (class "Default")
      (node (ref "IC9") (pin "8") (pinfunction "4Y_8") (pintype "bidirectional"))
      (node (ref "R6G3") (pin "2") (pinfunction "A_2") (pintype "bidirectional"))
    )
    (net (code "169") (name "Net-(IC9-5A)") (class "Default")
      (node (ref "IC9") (pin "11") (pinfunction "5A_11") (pintype "bidirectional"))
      (node (ref "U4") (pin "11") (pinfunction "~{O4}_11") (pintype "output"))
    )
    (net (code "170") (name "Net-(IC9-5Y)") (class "Default")
      (node (ref "IC9") (pin "10") (pinfunction "5Y_10") (pintype "bidirectional"))
      (node (ref "R5G3") (pin "2") (pinfunction "A_2") (pintype "bidirectional"))
    )
    (net (code "171") (name "Net-(IC9-6A)") (class "Default")
      (node (ref "IC9") (pin "13") (pinfunction "6A_13") (pintype "bidirectional"))
      (node (ref "U4") (pin "12") (pinfunction "~{O3}_12") (pintype "output"))
    )
    (net (code "172") (name "Net-(IC9-6Y)") (class "Default")
      (node (ref "IC9") (pin "12") (pinfunction "6Y_12") (pintype "bidirectional"))
      (node (ref "R4G3") (pin "2") (pinfunction "A_2") (pintype "bidirectional"))
    )
    (net (code "173") (name "Net-(IC10-1A)") (class "Default")
      (node (ref "IC10") (pin "1") (pinfunction "1A_1") (pintype "bidirectional"))
      (node (ref "U4") (pin "9") (pinfunction "~{O6}_9") (pintype "output"))
    )
    (net (code "174") (name "Net-(IC10-1Y)") (class "Default")
      (node (ref "IC10") (pin "2") (pinfunction "1Y_2") (pintype "bidirectional"))
      (node (ref "R7G3") (pin "2") (pinfunction "A_2") (pintype "bidirectional"))
    )
    (net (code "175") (name "Net-(IC10-2A)") (class "Default")
      (node (ref "IC10") (pin "3") (pinfunction "2A_3") (pintype "bidirectional"))
      (node (ref "U4") (pin "7") (pinfunction "~{O7}_7") (pintype "output"))
    )
    (net (code "176") (name "Net-(IC10-2Y)") (class "Default")
      (node (ref "IC10") (pin "4") (pinfunction "2Y_4") (pintype "bidirectional"))
      (node (ref "R8G3") (pin "2") (pinfunction "A_2") (pintype "bidirectional"))
    )
    (net (code "177") (name "Net-(IC11-1A)") (class "Default")
      (node (ref "IC11") (pin "1") (pinfunction "1A_1") (pintype "bidirectional"))
      (node (ref "U5") (pin "15") (pinfunction "~{O0}_15") (pintype "output"))
    )
    (net (code "178") (name "Net-(IC11-2A)") (class "Default")
      (node (ref "IC11") (pin "3") (pinfunction "2A_3") (pintype "bidirectional"))
      (node (ref "U5") (pin "14") (pinfunction "~{O1}_14") (pintype "output"))
    )
    (net (code "179") (name "Net-(IC11-3A)") (class "Default")
      (node (ref "IC11") (pin "5") (pinfunction "3A_5") (pintype "bidirectional"))
      (node (ref "U5") (pin "13") (pinfunction "~{O2}_13") (pintype "output"))
    )
    (net (code "180") (name "Net-(IC11-4A)") (class "Default")
      (node (ref "IC11") (pin "9") (pinfunction "4A_9") (pintype "bidirectional"))
      (node (ref "U5") (pin "10") (pinfunction "~{O5}_10") (pintype "output"))
    )
    (net (code "181") (name "Net-(IC11-5A)") (class "Default")
      (node (ref "IC11") (pin "11") (pinfunction "5A_11") (pintype "bidirectional"))
      (node (ref "U5") (pin "11") (pinfunction "~{O4}_11") (pintype "output"))
    )
    (net (code "182") (name "Net-(IC11-6A)") (class "Default")
      (node (ref "IC11") (pin "13") (pinfunction "6A_13") (pintype "bidirectional"))
      (node (ref "U5") (pin "12") (pinfunction "~{O3}_12") (pintype "output"))
    )
    (net (code "183") (name "Net-(IC12-1A)") (class "Default")
      (node (ref "IC12") (pin "1") (pinfunction "1A_1") (pintype "bidirectional"))
      (node (ref "U5") (pin "9") (pinfunction "~{O6}_9") (pintype "output"))
    )
    (net (code "184") (name "Net-(IC12-2A)") (class "Default")
      (node (ref "IC12") (pin "3") (pinfunction "2A_3") (pintype "bidirectional"))
      (node (ref "U5") (pin "7") (pinfunction "~{O7}_7") (pintype "output"))
    )
    (net (code "185") (name "Net-(IC13-1A)") (class "Default")
      (node (ref "IC13") (pin "1") (pinfunction "1A_1") (pintype "bidirectional"))
      (node (ref "U6") (pin "15") (pinfunction "~{O0}_15") (pintype "output"))
    )
    (net (code "186") (name "Net-(IC13-2A)") (class "Default")
      (node (ref "IC13") (pin "3") (pinfunction "2A_3") (pintype "bidirectional"))
      (node (ref "U6") (pin "14") (pinfunction "~{O1}_14") (pintype "output"))
    )
    (net (code "187") (name "Net-(IC13-3A)") (class "Default")
      (node (ref "IC13") (pin "5") (pinfunction "3A_5") (pintype "bidirectional"))
      (node (ref "U6") (pin "13") (pinfunction "~{O2}_13") (pintype "output"))
    )
    (net (code "188") (name "Net-(IC13-4A)") (class "Default")
      (node (ref "IC13") (pin "9") (pinfunction "4A_9") (pintype "bidirectional"))
      (node (ref "U6") (pin "10") (pinfunction "~{O5}_10") (pintype "output"))
    )
    (net (code "189") (name "Net-(IC13-5A)") (class "Default")
      (node (ref "IC13") (pin "11") (pinfunction "5A_11") (pintype "bidirectional"))
      (node (ref "U6") (pin "11") (pinfunction "~{O4}_11") (pintype "output"))
    )
    (net (code "190") (name "Net-(IC13-5Y)") (class "Default")
      (node (ref "IC13") (pin "10") (pinfunction "5Y_10") (pintype "bidirectional"))
      (node (ref "R5G5") (pin "2") (pinfunction "A_2") (pintype "bidirectional"))
    )
    (net (code "191") (name "Net-(IC13-6A)") (class "Default")
      (node (ref "IC13") (pin "13") (pinfunction "6A_13") (pintype "bidirectional"))
      (node (ref "U6") (pin "12") (pinfunction "~{O3}_12") (pintype "output"))
    )
    (net (code "192") (name "Net-(IC14-1A)") (class "Default")
      (node (ref "IC14") (pin "1") (pinfunction "1A_1") (pintype "bidirectional"))
      (node (ref "U6") (pin "9") (pinfunction "~{O6}_9") (pintype "output"))
    )
    (net (code "193") (name "Net-(IC14-2A)") (class "Default")
      (node (ref "IC14") (pin "3") (pinfunction "2A_3") (pintype "bidirectional"))
      (node (ref "U6") (pin "7") (pinfunction "~{O7}_7") (pintype "output"))
    )
    (net (code "194") (name "Net-(IC15-1A)") (class "Default")
      (node (ref "IC15") (pin "1") (pinfunction "1A_1") (pintype "bidirectional"))
      (node (ref "U7") (pin "15") (pinfunction "~{O0}_15") (pintype "output"))
    )
    (net (code "195") (name "Net-(IC15-1Y)") (class "Default")
      (node (ref "IC15") (pin "2") (pinfunction "1Y_2") (pintype "bidirectional"))
      (node (ref "R1G6") (pin "2") (pinfunction "A_2") (pintype "bidirectional"))
    )
    (net (code "196") (name "Net-(IC15-2A)") (class "Default")
      (node (ref "IC15") (pin "3") (pinfunction "2A_3") (pintype "bidirectional"))
      (node (ref "U7") (pin "14") (pinfunction "~{O1}_14") (pintype "output"))
    )
    (net (code "197") (name "Net-(IC15-2Y)") (class "Default")
      (node (ref "IC15") (pin "4") (pinfunction "2Y_4") (pintype "bidirectional"))
      (node (ref "R2G6") (pin "2") (pinfunction "A_2") (pintype "bidirectional"))
    )
    (net (code "198") (name "Net-(IC15-3A)") (class "Default")
      (node (ref "IC15") (pin "5") (pinfunction "3A_5") (pintype "bidirectional"))
      (node (ref "U7") (pin "13") (pinfunction "~{O2}_13") (pintype "output"))
    )
    (net (code "199") (name "Net-(IC15-3Y)") (class "Default")
      (node (ref "IC15") (pin "6") (pinfunction "3Y_6") (pintype "bidirectional"))
      (node (ref "R3G6") (pin "2") (pinfunction "A_2") (pintype "bidirectional"))
    )
    (net (code "200") (name "Net-(IC15-4A)") (class "Default")
      (node (ref "IC15") (pin "9") (pinfunction "4A_9") (pintype "bidirectional"))
      (node (ref "U7") (pin "10") (pinfunction "~{O5}_10") (pintype "output"))
    )
    (net (code "201") (name "Net-(IC15-4Y)") (class "Default")
      (node (ref "IC15") (pin "8") (pinfunction "4Y_8") (pintype "bidirectional"))
      (node (ref "R6G6") (pin "2") (pinfunction "A_2") (pintype "bidirectional"))
    )
    (net (code "202") (name "Net-(IC15-5A)") (class "Default")
      (node (ref "IC15") (pin "11") (pinfunction "5A_11") (pintype "bidirectional"))
      (node (ref "U7") (pin "11") (pinfunction "~{O4}_11") (pintype "output"))
    )
    (net (code "203") (name "Net-(IC15-5Y)") (class "Default")
      (node (ref "IC15") (pin "10") (pinfunction "5Y_10") (pintype "bidirectional"))
      (node (ref "R5G6") (pin "2") (pinfunction "A_2") (pintype "bidirectional"))
    )
    (net (code "204") (name "Net-(IC15-6A)") (class "Default")
      (node (ref "IC15") (pin "13") (pinfunction "6A_13") (pintype "bidirectional"))
      (node (ref "U7") (pin "12") (pinfunction "~{O3}_12") (pintype "output"))
    )
    (net (code "205") (name "Net-(IC15-6Y)") (class "Default")
      (node (ref "IC15") (pin "12") (pinfunction "6Y_12") (pintype "bidirectional"))
      (node (ref "R4G6") (pin "2") (pinfunction "A_2") (pintype "bidirectional"))
    )
    (net (code "206") (name "Net-(IC16-1A)") (class "Default")
      (node (ref "IC16") (pin "1") (pinfunction "1A_1") (pintype "bidirectional"))
      (node (ref "U7") (pin "9") (pinfunction "~{O6}_9") (pintype "output"))
    )
    (net (code "207") (name "Net-(IC16-1Y)") (class "Default")
      (node (ref "IC16") (pin "2") (pinfunction "1Y_2") (pintype "bidirectional"))
      (node (ref "R7G6") (pin "2") (pinfunction "A_2") (pintype "bidirectional"))
    )
    (net (code "208") (name "Net-(IC16-2A)") (class "Default")
      (node (ref "IC16") (pin "3") (pinfunction "2A_3") (pintype "bidirectional"))
      (node (ref "U7") (pin "7") (pinfunction "~{O7}_7") (pintype "output"))
    )
    (net (code "209") (name "Net-(IC16-2Y)") (class "Default")
      (node (ref "IC16") (pin "4") (pinfunction "2Y_4") (pintype "bidirectional"))
      (node (ref "R8G6") (pin "2") (pinfunction "A_2") (pintype "bidirectional"))
    )
    (net (code "210") (name "Net-(IC17-1A)") (class "Default")
      (node (ref "IC17") (pin "1") (pinfunction "1A_1") (pintype "bidirectional"))
      (node (ref "U8") (pin "15") (pinfunction "~{O0}_15") (pintype "output"))
    )
    (net (code "211") (name "Net-(IC17-2A)") (class "Default")
      (node (ref "IC17") (pin "3") (pinfunction "2A_3") (pintype "bidirectional"))
      (node (ref "U8") (pin "14") (pinfunction "~{O1}_14") (pintype "output"))
    )
    (net (code "212") (name "Net-(IC17-3A)") (class "Default")
      (node (ref "IC17") (pin "5") (pinfunction "3A_5") (pintype "bidirectional"))
      (node (ref "U8") (pin "13") (pinfunction "~{O2}_13") (pintype "output"))
    )
    (net (code "213") (name "Net-(IC17-4A)") (class "Default")
      (node (ref "IC17") (pin "9") (pinfunction "4A_9") (pintype "bidirectional"))
      (node (ref "U8") (pin "10") (pinfunction "~{O5}_10") (pintype "output"))
    )
    (net (code "214") (name "Net-(IC17-4Y)") (class "Default")
      (node (ref "IC17") (pin "8") (pinfunction "4Y_8") (pintype "bidirectional"))
      (node (ref "O6G7") (pin "2") (pinfunction "A_2") (pintype "bidirectional"))
    )
    (net (code "215") (name "Net-(IC17-5A)") (class "Default")
      (node (ref "IC17") (pin "11") (pinfunction "5A_11") (pintype "bidirectional"))
      (node (ref "U8") (pin "11") (pinfunction "~{O4}_11") (pintype "output"))
    )
    (net (code "216") (name "Net-(IC17-5Y)") (class "Default")
      (node (ref "IC17") (pin "10") (pinfunction "5Y_10") (pintype "bidirectional"))
      (node (ref "Y5G7") (pin "2") (pinfunction "A_2") (pintype "bidirectional"))
    )
    (net (code "217") (name "Net-(IC17-6A)") (class "Default")
      (node (ref "IC17") (pin "13") (pinfunction "6A_13") (pintype "bidirectional"))
      (node (ref "U8") (pin "12") (pinfunction "~{O3}_12") (pintype "output"))
    )
    (net (code "218") (name "Net-(IC18-1A)") (class "Default")
      (node (ref "IC18") (pin "1") (pinfunction "1A_1") (pintype "bidirectional"))
      (node (ref "U8") (pin "9") (pinfunction "~{O6}_9") (pintype "output"))
    )
    (net (code "219") (name "Net-(IC18-2A)") (class "Default")
      (node (ref "IC18") (pin "3") (pinfunction "2A_3") (pintype "bidirectional"))
      (node (ref "U8") (pin "7") (pinfunction "~{O7}_7") (pintype "output"))
    )
    (net (code "220") (name "Net-(IC18-2Y)") (class "Default")
      (node (ref "IC18") (pin "4") (pinfunction "2Y_4") (pintype "bidirectional"))
      (node (ref "Y8G7") (pin "2") (pinfunction "A_2") (pintype "bidirectional"))
    )
    (net (code "221") (name "Net-(IC19-1A)") (class "Default")
      (node (ref "IC19") (pin "1") (pinfunction "1A_1") (pintype "bidirectional"))
      (node (ref "U9") (pin "15") (pinfunction "~{O0}_15") (pintype "output"))
    )
    (net (code "222") (name "Net-(IC19-2A)") (class "Default")
      (node (ref "IC19") (pin "3") (pinfunction "2A_3") (pintype "bidirectional"))
      (node (ref "U9") (pin "14") (pinfunction "~{O1}_14") (pintype "output"))
    )
    (net (code "223") (name "Net-(IC19-3A)") (class "Default")
      (node (ref "IC19") (pin "5") (pinfunction "3A_5") (pintype "bidirectional"))
      (node (ref "U9") (pin "13") (pinfunction "~{O2}_13") (pintype "output"))
    )
    (net (code "224") (name "Net-(IC19-4A)") (class "Default")
      (node (ref "IC19") (pin "9") (pinfunction "4A_9") (pintype "bidirectional"))
      (node (ref "U9") (pin "10") (pinfunction "~{O5}_10") (pintype "output"))
    )
    (net (code "225") (name "Net-(IC19-4Y)") (class "Default")
      (node (ref "IC19") (pin "8") (pinfunction "4Y_8") (pintype "bidirectional"))
      (node (ref "Y6G8") (pin "2") (pinfunction "A_2") (pintype "bidirectional"))
    )
    (net (code "226") (name "Net-(IC19-5A)") (class "Default")
      (node (ref "IC19") (pin "11") (pinfunction "5A_11") (pintype "bidirectional"))
      (node (ref "U9") (pin "11") (pinfunction "~{O4}_11") (pintype "output"))
    )
    (net (code "227") (name "Net-(IC19-6A)") (class "Default")
      (node (ref "IC19") (pin "13") (pinfunction "6A_13") (pintype "bidirectional"))
      (node (ref "U9") (pin "12") (pinfunction "~{O3}_12") (pintype "output"))
    )
    (net (code "228") (name "Net-(IC20-1A)") (class "Default")
      (node (ref "IC20") (pin "1") (pinfunction "1A_1") (pintype "bidirectional"))
      (node (ref "U9") (pin "9") (pinfunction "~{O6}_9") (pintype "output"))
    )
    (net (code "229") (name "Net-(IC20-2A)") (class "Default")
      (node (ref "IC20") (pin "3") (pinfunction "2A_3") (pintype "bidirectional"))
      (node (ref "U9") (pin "7") (pinfunction "~{O7}_7") (pintype "output"))
    )
    (net (code "230") (name "Net-(IC20-2Y)") (class "Default")
      (node (ref "IC20") (pin "4") (pinfunction "2Y_4") (pintype "bidirectional"))
      (node (ref "Y8G8") (pin "2") (pinfunction "A_2") (pintype "bidirectional"))
    )
    (net (code "231") (name "Net-(IC21-1A)") (class "Default")
      (node (ref "IC21") (pin "1") (pinfunction "1A_1") (pintype "bidirectional"))
      (node (ref "U10") (pin "15") (pinfunction "~{O0}_15") (pintype "output"))
    )
    (net (code "232") (name "Net-(IC21-1Y)") (class "Default")
      (node (ref "IC21") (pin "2") (pinfunction "1Y_2") (pintype "bidirectional"))
      (node (ref "O1G9") (pin "2") (pinfunction "A_2") (pintype "bidirectional"))
    )
    (net (code "233") (name "Net-(IC21-2A)") (class "Default")
      (node (ref "IC21") (pin "3") (pinfunction "2A_3") (pintype "bidirectional"))
      (node (ref "U10") (pin "14") (pinfunction "~{O1}_14") (pintype "output"))
    )
    (net (code "234") (name "Net-(IC21-2Y)") (class "Default")
      (node (ref "IC21") (pin "4") (pinfunction "2Y_4") (pintype "bidirectional"))
      (node (ref "O2G9") (pin "2") (pinfunction "A_2") (pintype "bidirectional"))
    )
    (net (code "235") (name "Net-(IC21-3A)") (class "Default")
      (node (ref "IC21") (pin "5") (pinfunction "3A_5") (pintype "bidirectional"))
      (node (ref "U10") (pin "13") (pinfunction "~{O2}_13") (pintype "output"))
    )
    (net (code "236") (name "Net-(IC21-3Y)") (class "Default")
      (node (ref "IC21") (pin "6") (pinfunction "3Y_6") (pintype "bidirectional"))
      (node (ref "O3G9") (pin "2") (pinfunction "A_2") (pintype "bidirectional"))
    )
    (net (code "237") (name "Net-(IC21-4A)") (class "Default")
      (node (ref "IC21") (pin "9") (pinfunction "4A_9") (pintype "bidirectional"))
      (node (ref "U10") (pin "10") (pinfunction "~{O5}_10") (pintype "output"))
    )
    (net (code "238") (name "Net-(IC21-4Y)") (class "Default")
      (node (ref "IC21") (pin "8") (pinfunction "4Y_8") (pintype "bidirectional"))
      (node (ref "O6G9") (pin "2") (pinfunction "A_2") (pintype "bidirectional"))
    )
    (net (code "239") (name "Net-(IC21-5A)") (class "Default")
      (node (ref "IC21") (pin "11") (pinfunction "5A_11") (pintype "bidirectional"))
      (node (ref "U10") (pin "11") (pinfunction "~{O4}_11") (pintype "output"))
    )
    (net (code "240") (name "Net-(IC21-5Y)") (class "Default")
      (node (ref "IC21") (pin "10") (pinfunction "5Y_10") (pintype "bidirectional"))
      (node (ref "O5G9") (pin "2") (pinfunction "A_2") (pintype "bidirectional"))
    )
    (net (code "241") (name "Net-(IC21-6A)") (class "Default")
      (node (ref "IC21") (pin "13") (pinfunction "6A_13") (pintype "bidirectional"))
      (node (ref "U10") (pin "12") (pinfunction "~{O3}_12") (pintype "output"))
    )
    (net (code "242") (name "Net-(IC21-6Y)") (class "Default")
      (node (ref "IC21") (pin "12") (pinfunction "6Y_12") (pintype "bidirectional"))
      (node (ref "O4G9") (pin "2") (pinfunction "A_2") (pintype "bidirectional"))
    )
    (net (code "243") (name "Net-(IC22-1A)") (class "Default")
      (node (ref "IC22") (pin "1") (pinfunction "1A_1") (pintype "bidirectional"))
      (node (ref "U10") (pin "9") (pinfunction "~{O6}_9") (pintype "output"))
    )
    (net (code "244") (name "Net-(IC22-1Y)") (class "Default")
      (node (ref "IC22") (pin "2") (pinfunction "1Y_2") (pintype "bidirectional"))
      (node (ref "O7G9") (pin "2") (pinfunction "A_2") (pintype "bidirectional"))
    )
    (net (code "245") (name "Net-(IC22-2A)") (class "Default")
      (node (ref "IC22") (pin "3") (pinfunction "2A_3") (pintype "bidirectional"))
      (node (ref "U10") (pin "7") (pinfunction "~{O7}_7") (pintype "output"))
    )
    (net (code "246") (name "Net-(IC22-2Y)") (class "Default")
      (node (ref "IC22") (pin "4") (pinfunction "2Y_4") (pintype "bidirectional"))
      (node (ref "O8G9") (pin "2") (pinfunction "A_2") (pintype "bidirectional"))
    )
    (net (code "247") (name "Net-(IC23-1A)") (class "Default")
      (node (ref "IC23") (pin "1") (pinfunction "1A_1") (pintype "bidirectional"))
      (node (ref "U11") (pin "15") (pinfunction "~{O0}_15") (pintype "output"))
    )
    (net (code "248") (name "Net-(IC23-1Y)") (class "Default")
      (node (ref "IC23") (pin "2") (pinfunction "1Y_2") (pintype "bidirectional"))
      (node (ref "Y1G10") (pin "2") (pinfunction "A_2") (pintype "bidirectional"))
    )
    (net (code "249") (name "Net-(IC23-2A)") (class "Default")
      (node (ref "IC23") (pin "3") (pinfunction "2A_3") (pintype "bidirectional"))
      (node (ref "U11") (pin "14") (pinfunction "~{O1}_14") (pintype "output"))
    )
    (net (code "250") (name "Net-(IC23-2Y)") (class "Default")
      (node (ref "IC23") (pin "4") (pinfunction "2Y_4") (pintype "bidirectional"))
      (node (ref "Y2G10") (pin "2") (pinfunction "A_2") (pintype "bidirectional"))
    )
    (net (code "251") (name "Net-(IC23-3A)") (class "Default")
      (node (ref "IC23") (pin "5") (pinfunction "3A_5") (pintype "bidirectional"))
      (node (ref "U11") (pin "13") (pinfunction "~{O2}_13") (pintype "output"))
    )
    (net (code "252") (name "Net-(IC23-3Y)") (class "Default")
      (node (ref "IC23") (pin "6") (pinfunction "3Y_6") (pintype "bidirectional"))
      (node (ref "Y3G10") (pin "2") (pinfunction "A_2") (pintype "bidirectional"))
    )
    (net (code "253") (name "Net-(IC23-5A)") (class "Default")
      (node (ref "IC23") (pin "11") (pinfunction "5A_11") (pintype "bidirectional"))
      (node (ref "U11") (pin "11") (pinfunction "~{O4}_11") (pintype "output"))
    )
    (net (code "254") (name "Net-(IC23-5Y)") (class "Default")
      (node (ref "IC23") (pin "10") (pinfunction "5Y_10") (pintype "bidirectional"))
      (node (ref "Y5G10") (pin "2") (pinfunction "A_2") (pintype "bidirectional"))
    )
    (net (code "255") (name "Net-(IC23-6A)") (class "Default")
      (node (ref "IC23") (pin "13") (pinfunction "6A_13") (pintype "bidirectional"))
      (node (ref "U11") (pin "12") (pinfunction "~{O3}_12") (pintype "output"))
    )
    (net (code "256") (name "Net-(IC23-6Y)") (class "Default")
      (node (ref "IC23") (pin "12") (pinfunction "6Y_12") (pintype "bidirectional"))
      (node (ref "Y4G10") (pin "2") (pinfunction "A_2") (pintype "bidirectional"))
    )
    (net (code "257") (name "Net-(IC25-1A)") (class "Default")
      (node (ref "IC25") (pin "1") (pinfunction "1A_1") (pintype "bidirectional"))
      (node (ref "U12") (pin "15") (pinfunction "~{O0}_15") (pintype "output"))
    )
    (net (code "258") (name "Net-(IC25-1Y)") (class "Default")
      (node (ref "IC25") (pin "2") (pinfunction "1Y_2") (pintype "bidirectional"))
      (node (ref "O1G11") (pin "2") (pinfunction "A_2") (pintype "bidirectional"))
    )
    (net (code "259") (name "Net-(IC25-2A)") (class "Default")
      (node (ref "IC25") (pin "3") (pinfunction "2A_3") (pintype "bidirectional"))
      (node (ref "U12") (pin "14") (pinfunction "~{O1}_14") (pintype "output"))
    )
    (net (code "260") (name "Net-(IC25-2Y)") (class "Default")
      (node (ref "IC25") (pin "4") (pinfunction "2Y_4") (pintype "bidirectional"))
      (node (ref "O2G11") (pin "2") (pinfunction "A_2") (pintype "bidirectional"))
    )
    (net (code "261") (name "Net-(IC25-3A)") (class "Default")
      (node (ref "IC25") (pin "5") (pinfunction "3A_5") (pintype "bidirectional"))
      (node (ref "U12") (pin "13") (pinfunction "~{O2}_13") (pintype "output"))
    )
    (net (code "262") (name "Net-(IC25-3Y)") (class "Default")
      (node (ref "IC25") (pin "6") (pinfunction "3Y_6") (pintype "bidirectional"))
      (node (ref "O3G11") (pin "2") (pinfunction "A_2") (pintype "bidirectional"))
    )
    (net (code "263") (name "Net-(IC25-4A)") (class "Default")
      (node (ref "IC25") (pin "9") (pinfunction "4A_9") (pintype "bidirectional"))
      (node (ref "U12") (pin "10") (pinfunction "~{O5}_10") (pintype "output"))
    )
    (net (code "264") (name "Net-(IC25-4Y)") (class "Default")
      (node (ref "IC25") (pin "8") (pinfunction "4Y_8") (pintype "bidirectional"))
      (node (ref "O6G11") (pin "2") (pinfunction "A_2") (pintype "bidirectional"))
    )
    (net (code "265") (name "Net-(IC25-5A)") (class "Default")
      (node (ref "IC25") (pin "11") (pinfunction "5A_11") (pintype "bidirectional"))
      (node (ref "U12") (pin "11") (pinfunction "~{O4}_11") (pintype "output"))
    )
    (net (code "266") (name "Net-(IC25-5Y)") (class "Default")
      (node (ref "IC25") (pin "10") (pinfunction "5Y_10") (pintype "bidirectional"))
      (node (ref "O5G11") (pin "2") (pinfunction "A_2") (pintype "bidirectional"))
    )
    (net (code "267") (name "Net-(IC25-6A)") (class "Default")
      (node (ref "IC25") (pin "13") (pinfunction "6A_13") (pintype "bidirectional"))
      (node (ref "U12") (pin "12") (pinfunction "~{O3}_12") (pintype "output"))
    )
    (net (code "268") (name "Net-(IC25-6Y)") (class "Default")
      (node (ref "IC25") (pin "12") (pinfunction "6Y_12") (pintype "bidirectional"))
      (node (ref "O4G11") (pin "2") (pinfunction "A_2") (pintype "bidirectional"))
    )
    (net (code "269") (name "Net-(IC26-1A)") (class "Default")
      (node (ref "IC26") (pin "1") (pinfunction "1A_1") (pintype "bidirectional"))
      (node (ref "U12") (pin "9") (pinfunction "~{O6}_9") (pintype "output"))
    )
    (net (code "270") (name "Net-(IC26-1Y)") (class "Default")
      (node (ref "IC26") (pin "2") (pinfunction "1Y_2") (pintype "bidirectional"))
      (node (ref "O7G11") (pin "2") (pinfunction "A_2") (pintype "bidirectional"))
    )
    (net (code "271") (name "Net-(IC26-2A)") (class "Default")
      (node (ref "IC26") (pin "3") (pinfunction "2A_3") (pintype "bidirectional"))
      (node (ref "U12") (pin "7") (pinfunction "~{O7}_7") (pintype "output"))
    )
    (net (code "272") (name "Net-(IC26-2Y)") (class "Default")
      (node (ref "IC26") (pin "4") (pinfunction "2Y_4") (pintype "bidirectional"))
      (node (ref "O8G11") (pin "2") (pinfunction "A_2") (pintype "bidirectional"))
    )
    (net (code "273") (name "Net-(IC27-1A)") (class "Default")
      (node (ref "IC27") (pin "1") (pinfunction "1A_1") (pintype "bidirectional"))
      (node (ref "U13") (pin "15") (pinfunction "~{O0}_15") (pintype "output"))
    )
    (net (code "274") (name "Net-(IC27-1Y)") (class "Default")
      (node (ref "IC27") (pin "2") (pinfunction "1Y_2") (pintype "bidirectional"))
      (node (ref "Y1G12") (pin "2") (pinfunction "A_2") (pintype "bidirectional"))
    )
    (net (code "275") (name "Net-(IC27-2A)") (class "Default")
      (node (ref "IC27") (pin "3") (pinfunction "2A_3") (pintype "bidirectional"))
      (node (ref "U13") (pin "14") (pinfunction "~{O1}_14") (pintype "output"))
    )
    (net (code "276") (name "Net-(IC27-2Y)") (class "Default")
      (node (ref "IC27") (pin "4") (pinfunction "2Y_4") (pintype "bidirectional"))
      (node (ref "Y2G12") (pin "2") (pinfunction "A_2") (pintype "bidirectional"))
    )
    (net (code "277") (name "Net-(IC27-3A)") (class "Default")
      (node (ref "IC27") (pin "5") (pinfunction "3A_5") (pintype "bidirectional"))
      (node (ref "U13") (pin "13") (pinfunction "~{O2}_13") (pintype "output"))
    )
    (net (code "278") (name "Net-(IC27-3Y)") (class "Default")
      (node (ref "IC27") (pin "6") (pinfunction "3Y_6") (pintype "bidirectional"))
      (node (ref "Y3G12") (pin "2") (pinfunction "A_2") (pintype "bidirectional"))
    )
    (net (code "279") (name "Net-(IC27-4A)") (class "Default")
      (node (ref "IC27") (pin "9") (pinfunction "4A_9") (pintype "bidirectional"))
      (node (ref "U13") (pin "10") (pinfunction "~{O5}_10") (pintype "output"))
    )
    (net (code "280") (name "Net-(IC27-4Y)") (class "Default")
      (node (ref "IC27") (pin "8") (pinfunction "4Y_8") (pintype "bidirectional"))
      (node (ref "Y6G12") (pin "2") (pinfunction "A_2") (pintype "bidirectional"))
    )
    (net (code "281") (name "Net-(IC27-5A)") (class "Default")
      (node (ref "IC27") (pin "11") (pinfunction "5A_11") (pintype "bidirectional"))
      (node (ref "U13") (pin "11") (pinfunction "~{O4}_11") (pintype "output"))
    )
    (net (code "282") (name "Net-(IC27-5Y)") (class "Default")
      (node (ref "IC27") (pin "10") (pinfunction "5Y_10") (pintype "bidirectional"))
      (node (ref "Y5G12") (pin "2") (pinfunction "A_2") (pintype "bidirectional"))
    )
    (net (code "283") (name "Net-(IC27-6A)") (class "Default")
      (node (ref "IC27") (pin "13") (pinfunction "6A_13") (pintype "bidirectional"))
      (node (ref "U13") (pin "12") (pinfunction "~{O3}_12") (pintype "output"))
    )
    (net (code "284") (name "Net-(IC27-6Y)") (class "Default")
      (node (ref "IC27") (pin "12") (pinfunction "6Y_12") (pintype "bidirectional"))
      (node (ref "Y4G12") (pin "2") (pinfunction "A_2") (pintype "bidirectional"))
    )
    (net (code "285") (name "Net-(IC28-1A)") (class "Default")
      (node (ref "IC28") (pin "1") (pinfunction "1A_1") (pintype "bidirectional"))
      (node (ref "U13") (pin "9") (pinfunction "~{O6}_9") (pintype "output"))
    )
    (net (code "286") (name "Net-(IC28-1Y)") (class "Default")
      (node (ref "IC28") (pin "2") (pinfunction "1Y_2") (pintype "bidirectional"))
      (node (ref "Y7G12") (pin "2") (pinfunction "A_2") (pintype "bidirectional"))
    )
    (net (code "287") (name "Net-(IC28-2A)") (class "Default")
      (node (ref "IC28") (pin "3") (pinfunction "2A_3") (pintype "bidirectional"))
      (node (ref "U13") (pin "7") (pinfunction "~{O7}_7") (pintype "output"))
    )
    (net (code "288") (name "Net-(IC28-2Y)") (class "Default")
      (node (ref "IC28") (pin "4") (pinfunction "2Y_4") (pintype "bidirectional"))
      (node (ref "Y8G12") (pin "2") (pinfunction "A_2") (pintype "bidirectional"))
    )
    (net (code "289") (name "Net-(IC29-1A)") (class "Default")
      (node (ref "IC29") (pin "1") (pinfunction "1A_1") (pintype "bidirectional"))
      (node (ref "U14") (pin "15") (pinfunction "~{O0}_15") (pintype "output"))
    )
    (net (code "290") (name "Net-(IC29-2A)") (class "Default")
      (node (ref "IC29") (pin "3") (pinfunction "2A_3") (pintype "bidirectional"))
      (node (ref "U14") (pin "14") (pinfunction "~{O1}_14") (pintype "output"))
    )
    (net (code "291") (name "Net-(IC29-3A)") (class "Default")
      (node (ref "IC29") (pin "5") (pinfunction "3A_5") (pintype "bidirectional"))
      (node (ref "U14") (pin "13") (pinfunction "~{O2}_13") (pintype "output"))
    )
    (net (code "292") (name "Net-(IC29-4A)") (class "Default")
      (node (ref "IC29") (pin "9") (pinfunction "4A_9") (pintype "bidirectional"))
      (node (ref "U14") (pin "10") (pinfunction "~{O5}_10") (pintype "output"))
    )
    (net (code "293") (name "Net-(IC29-5A)") (class "Default")
      (node (ref "IC29") (pin "11") (pinfunction "5A_11") (pintype "bidirectional"))
      (node (ref "U14") (pin "11") (pinfunction "~{O4}_11") (pintype "output"))
    )
    (net (code "294") (name "Net-(IC29-6A)") (class "Default")
      (node (ref "IC29") (pin "13") (pinfunction "6A_13") (pintype "bidirectional"))
      (node (ref "U14") (pin "12") (pinfunction "~{O3}_12") (pintype "output"))
    )
    (net (code "295") (name "Net-(IC30-1A)") (class "Default")
      (node (ref "IC30") (pin "1") (pinfunction "1A_1") (pintype "bidirectional"))
      (node (ref "U14") (pin "9") (pinfunction "~{O6}_9") (pintype "output"))
    )
    (net (code "296") (name "Net-(IC30-2A)") (class "Default")
      (node (ref "IC30") (pin "3") (pinfunction "2A_3") (pintype "bidirectional"))
      (node (ref "U14") (pin "7") (pinfunction "~{O7}_7") (pintype "output"))
    )
    (net (code "297") (name "Net-(IC31-1A)") (class "Default")
      (node (ref "IC31") (pin "1") (pinfunction "1A_1") (pintype "bidirectional"))
      (node (ref "U15") (pin "15") (pinfunction "~{O0}_15") (pintype "output"))
    )
    (net (code "298") (name "Net-(IC31-2A)") (class "Default")
      (node (ref "IC31") (pin "3") (pinfunction "2A_3") (pintype "bidirectional"))
      (node (ref "U15") (pin "14") (pinfunction "~{O1}_14") (pintype "output"))
    )
    (net (code "299") (name "Net-(IC31-3A)") (class "Default")
      (node (ref "IC31") (pin "5") (pinfunction "3A_5") (pintype "bidirectional"))
      (node (ref "U15") (pin "13") (pinfunction "~{O2}_13") (pintype "output"))
    )
    (net (code "300") (name "Net-(IC31-4A)") (class "Default")
      (node (ref "IC31") (pin "9") (pinfunction "4A_9") (pintype "bidirectional"))
      (node (ref "U15") (pin "10") (pinfunction "~{O5}_10") (pintype "output"))
    )
    (net (code "301") (name "Net-(IC31-5A)") (class "Default")
      (node (ref "IC31") (pin "11") (pinfunction "5A_11") (pintype "bidirectional"))
      (node (ref "U15") (pin "11") (pinfunction "~{O4}_11") (pintype "output"))
    )
    (net (code "302") (name "Net-(IC31-6A)") (class "Default")
      (node (ref "IC31") (pin "13") (pinfunction "6A_13") (pintype "bidirectional"))
      (node (ref "U15") (pin "12") (pinfunction "~{O3}_12") (pintype "output"))
    )
    (net (code "303") (name "Net-(IC32-1A)") (class "Default")
      (node (ref "IC32") (pin "1") (pinfunction "1A_1") (pintype "bidirectional"))
      (node (ref "U15") (pin "9") (pinfunction "~{O6}_9") (pintype "output"))
    )
    (net (code "304") (name "Net-(IC32-2A)") (class "Default")
      (node (ref "IC32") (pin "3") (pinfunction "2A_3") (pintype "bidirectional"))
      (node (ref "U15") (pin "7") (pinfunction "~{O7}_7") (pintype "output"))
    )
    (net (code "305") (name "Net-(IC33-1A)") (class "Default")
      (node (ref "IC33") (pin "1") (pinfunction "1A_1") (pintype "bidirectional"))
      (node (ref "U16") (pin "15") (pinfunction "~{O0}_15") (pintype "output"))
    )
    (net (code "306") (name "Net-(IC33-1Y)") (class "Default")
      (node (ref "IC33") (pin "2") (pinfunction "1Y_2") (pintype "bidirectional"))
      (node (ref "R1G15") (pin "2") (pinfunction "A_2") (pintype "bidirectional"))
    )
    (net (code "307") (name "Net-(IC33-2A)") (class "Default")
      (node (ref "IC33") (pin "3") (pinfunction "2A_3") (pintype "bidirectional"))
      (node (ref "U16") (pin "14") (pinfunction "~{O1}_14") (pintype "output"))
    )
    (net (code "308") (name "Net-(IC33-2Y)") (class "Default")
      (node (ref "IC33") (pin "4") (pinfunction "2Y_4") (pintype "bidirectional"))
      (node (ref "R2G15") (pin "2") (pinfunction "A_2") (pintype "bidirectional"))
    )
    (net (code "309") (name "Net-(IC33-3A)") (class "Default")
      (node (ref "IC33") (pin "5") (pinfunction "3A_5") (pintype "bidirectional"))
      (node (ref "U16") (pin "13") (pinfunction "~{O2}_13") (pintype "output"))
    )
    (net (code "310") (name "Net-(IC33-3Y)") (class "Default")
      (node (ref "IC33") (pin "6") (pinfunction "3Y_6") (pintype "bidirectional"))
      (node (ref "R3G15") (pin "2") (pinfunction "A_2") (pintype "bidirectional"))
    )
    (net (code "311") (name "Net-(IC33-4A)") (class "Default")
      (node (ref "IC33") (pin "9") (pinfunction "4A_9") (pintype "bidirectional"))
      (node (ref "U16") (pin "10") (pinfunction "~{O5}_10") (pintype "output"))
    )
    (net (code "312") (name "Net-(IC33-4Y)") (class "Default")
      (node (ref "IC33") (pin "8") (pinfunction "4Y_8") (pintype "bidirectional"))
      (node (ref "R6G15") (pin "2") (pinfunction "A_2") (pintype "bidirectional"))
    )
    (net (code "313") (name "Net-(IC33-5A)") (class "Default")
      (node (ref "IC33") (pin "11") (pinfunction "5A_11") (pintype "bidirectional"))
      (node (ref "U16") (pin "11") (pinfunction "~{O4}_11") (pintype "output"))
    )
    (net (code "314") (name "Net-(IC33-5Y)") (class "Default")
      (node (ref "IC33") (pin "10") (pinfunction "5Y_10") (pintype "bidirectional"))
      (node (ref "R5G15") (pin "2") (pinfunction "A_2") (pintype "bidirectional"))
    )
    (net (code "315") (name "Net-(IC33-6A)") (class "Default")
      (node (ref "IC33") (pin "13") (pinfunction "6A_13") (pintype "bidirectional"))
      (node (ref "U16") (pin "12") (pinfunction "~{O3}_12") (pintype "output"))
    )
    (net (code "316") (name "Net-(IC33-6Y)") (class "Default")
      (node (ref "IC33") (pin "12") (pinfunction "6Y_12") (pintype "bidirectional"))
      (node (ref "R4G15") (pin "2") (pinfunction "A_2") (pintype "bidirectional"))
    )
    (net (code "317") (name "Net-(IC34-1A)") (class "Default")
      (node (ref "IC34") (pin "1") (pinfunction "1A_1") (pintype "bidirectional"))
      (node (ref "U16") (pin "9") (pinfunction "~{O6}_9") (pintype "output"))
    )
    (net (code "318") (name "Net-(IC34-1Y)") (class "Default")
      (node (ref "IC34") (pin "2") (pinfunction "1Y_2") (pintype "bidirectional"))
      (node (ref "R7G15") (pin "2") (pinfunction "A_2") (pintype "bidirectional"))
    )
    (net (code "319") (name "Net-(IC34-2A)") (class "Default")
      (node (ref "IC34") (pin "3") (pinfunction "2A_3") (pintype "bidirectional"))
      (node (ref "U16") (pin "7") (pinfunction "~{O7}_7") (pintype "output"))
    )
    (net (code "320") (name "Net-(IC34-2Y)") (class "Default")
      (node (ref "IC34") (pin "4") (pinfunction "2Y_4") (pintype "bidirectional"))
      (node (ref "R8G15") (pin "2") (pinfunction "A_2") (pintype "bidirectional"))
    )
    (net (code "321") (name "Net-(IC35-1A)") (class "Default")
      (node (ref "IC35") (pin "1") (pinfunction "1A_1") (pintype "bidirectional"))
      (node (ref "U17") (pin "15") (pinfunction "~{O0}_15") (pintype "output"))
    )
    (net (code "322") (name "Net-(IC35-2A)") (class "Default")
      (node (ref "IC35") (pin "3") (pinfunction "2A_3") (pintype "bidirectional"))
      (node (ref "U17") (pin "14") (pinfunction "~{O1}_14") (pintype "output"))
    )
    (net (code "323") (name "Net-(IC35-3A)") (class "Default")
      (node (ref "IC35") (pin "5") (pinfunction "3A_5") (pintype "bidirectional"))
      (node (ref "U17") (pin "13") (pinfunction "~{O2}_13") (pintype "output"))
    )
    (net (code "324") (name "Net-(IC35-4A)") (class "Default")
      (node (ref "IC35") (pin "9") (pinfunction "4A_9") (pintype "bidirectional"))
      (node (ref "U17") (pin "10") (pinfunction "~{O5}_10") (pintype "output"))
    )
    (net (code "325") (name "Net-(IC35-5A)") (class "Default")
      (node (ref "IC35") (pin "11") (pinfunction "5A_11") (pintype "bidirectional"))
      (node (ref "U17") (pin "11") (pinfunction "~{O4}_11") (pintype "output"))
    )
    (net (code "326") (name "Net-(IC35-6A)") (class "Default")
      (node (ref "IC35") (pin "13") (pinfunction "6A_13") (pintype "bidirectional"))
      (node (ref "U17") (pin "12") (pinfunction "~{O3}_12") (pintype "output"))
    )
    (net (code "327") (name "Net-(IC36-1A)") (class "Default")
      (node (ref "IC36") (pin "1") (pinfunction "1A_1") (pintype "bidirectional"))
      (node (ref "U17") (pin "9") (pinfunction "~{O6}_9") (pintype "output"))
    )
    (net (code "328") (name "Net-(IC36-2A)") (class "Default")
      (node (ref "IC36") (pin "3") (pinfunction "2A_3") (pintype "bidirectional"))
      (node (ref "U17") (pin "7") (pinfunction "~{O7}_7") (pintype "output"))
    )
    (net (code "329") (name "Net-(IC37-1A)") (class "Default")
      (node (ref "IC37") (pin "1") (pinfunction "1A_1") (pintype "bidirectional"))
      (node (ref "U18") (pin "15") (pinfunction "~{O0}_15") (pintype "output"))
    )
    (net (code "330") (name "Net-(IC37-1Y)") (class "Default")
      (node (ref "IC37") (pin "2") (pinfunction "1Y_2") (pintype "bidirectional"))
      (node (ref "R1G17") (pin "2") (pinfunction "A_2") (pintype "bidirectional"))
    )
    (net (code "331") (name "Net-(IC37-2A)") (class "Default")
      (node (ref "IC37") (pin "3") (pinfunction "2A_3") (pintype "bidirectional"))
      (node (ref "U18") (pin "14") (pinfunction "~{O1}_14") (pintype "output"))
    )
    (net (code "332") (name "Net-(IC37-2Y)") (class "Default")
      (node (ref "IC37") (pin "4") (pinfunction "2Y_4") (pintype "bidirectional"))
      (node (ref "R2G17") (pin "2") (pinfunction "A_2") (pintype "bidirectional"))
    )
    (net (code "333") (name "Net-(IC37-3A)") (class "Default")
      (node (ref "IC37") (pin "5") (pinfunction "3A_5") (pintype "bidirectional"))
      (node (ref "U18") (pin "13") (pinfunction "~{O2}_13") (pintype "output"))
    )
    (net (code "334") (name "Net-(IC37-4A)") (class "Default")
      (node (ref "IC37") (pin "9") (pinfunction "4A_9") (pintype "bidirectional"))
      (node (ref "U18") (pin "10") (pinfunction "~{O5}_10") (pintype "output"))
    )
    (net (code "335") (name "Net-(IC37-5A)") (class "Default")
      (node (ref "IC37") (pin "11") (pinfunction "5A_11") (pintype "bidirectional"))
      (node (ref "U18") (pin "11") (pinfunction "~{O4}_11") (pintype "output"))
    )
    (net (code "336") (name "Net-(IC37-6A)") (class "Default")
      (node (ref "IC37") (pin "13") (pinfunction "6A_13") (pintype "bidirectional"))
      (node (ref "U18") (pin "12") (pinfunction "~{O3}_12") (pintype "output"))
    )
    (net (code "337") (name "Net-(IC38-1A)") (class "Default")
      (node (ref "IC38") (pin "1") (pinfunction "1A_1") (pintype "bidirectional"))
      (node (ref "U18") (pin "9") (pinfunction "~{O6}_9") (pintype "output"))
    )
    (net (code "338") (name "Net-(IC38-2A)") (class "Default")
      (node (ref "IC38") (pin "3") (pinfunction "2A_3") (pintype "bidirectional"))
      (node (ref "U18") (pin "7") (pinfunction "~{O7}_7") (pintype "output"))
    )
    (net (code "339") (name "Net-(IC39-1A)") (class "Default")
      (node (ref "IC39") (pin "1") (pinfunction "1A_1") (pintype "bidirectional"))
      (node (ref "U19") (pin "15") (pinfunction "~{O0}_15") (pintype "output"))
    )
    (net (code "340") (name "Net-(IC39-2A)") (class "Default")
      (node (ref "IC39") (pin "3") (pinfunction "2A_3") (pintype "bidirectional"))
      (node (ref "U19") (pin "14") (pinfunction "~{O1}_14") (pintype "output"))
    )
    (net (code "341") (name "Net-(IC39-3A)") (class "Default")
      (node (ref "IC39") (pin "5") (pinfunction "3A_5") (pintype "bidirectional"))
      (node (ref "U19") (pin "13") (pinfunction "~{O2}_13") (pintype "output"))
    )
    (net (code "342") (name "Net-(IC39-4A)") (class "Default")
      (node (ref "IC39") (pin "9") (pinfunction "4A_9") (pintype "bidirectional"))
      (node (ref "U19") (pin "10") (pinfunction "~{O5}_10") (pintype "output"))
    )
    (net (code "343") (name "Net-(IC39-5A)") (class "Default")
      (node (ref "IC39") (pin "11") (pinfunction "5A_11") (pintype "bidirectional"))
      (node (ref "U19") (pin "11") (pinfunction "~{O4}_11") (pintype "output"))
    )
    (net (code "344") (name "Net-(IC39-6A)") (class "Default")
      (node (ref "IC39") (pin "13") (pinfunction "6A_13") (pintype "bidirectional"))
      (node (ref "U19") (pin "12") (pinfunction "~{O3}_12") (pintype "output"))
    )
    (net (code "345") (name "Net-(IC40-1A)") (class "Default")
      (node (ref "IC40") (pin "1") (pinfunction "1A_1") (pintype "bidirectional"))
      (node (ref "U19") (pin "9") (pinfunction "~{O6}_9") (pintype "output"))
    )
    (net (code "346") (name "Net-(IC40-2A)") (class "Default")
      (node (ref "IC40") (pin "3") (pinfunction "2A_3") (pintype "bidirectional"))
      (node (ref "U19") (pin "7") (pinfunction "~{O7}_7") (pintype "output"))
    )
    (net (code "347") (name "Net-(JP3-Pad2)") (class "Default")
      (node (ref "JP3") (pin "2") (pinfunction "2_2") (pintype "passive"))
      (node (ref "R3") (pin "1") (pinfunction "1_1") (pintype "passive"))
      (node (ref "R4") (pin "2") (pinfunction "2_2") (pintype "passive"))
    )
    (net (code "348") (name "Net-(O1G9-K)") (class "Default")
      (node (ref "O1G9") (pin "1") (pinfunction "K_1") (pintype "bidirectional"))
      (node (ref "R38") (pin "2") (pinfunction "2_2") (pintype "passive"))
    )
    (net (code "349") (name "Net-(O1G11-K)") (class "Default")
      (node (ref "O1G11") (pin "1") (pinfunction "K_1") (pintype "bidirectional"))
      (node (ref "R52") (pin "2") (pinfunction "2_2") (pintype "passive"))
    )
    (net (code "350") (name "Net-(O2G9-K)") (class "Default")
      (node (ref "O2G9") (pin "1") (pinfunction "K_1") (pintype "bidirectional"))
      (node (ref "R39") (pin "2") (pinfunction "2_2") (pintype "passive"))
    )
    (net (code "351") (name "Net-(O2G11-K)") (class "Default")
      (node (ref "O2G11") (pin "1") (pinfunction "K_1") (pintype "bidirectional"))
      (node (ref "R53") (pin "2") (pinfunction "2_2") (pintype "passive"))
    )
    (net (code "352") (name "Net-(O3G9-K)") (class "Default")
      (node (ref "O3G9") (pin "1") (pinfunction "K_1") (pintype "bidirectional"))
      (node (ref "R40") (pin "2") (pinfunction "2_2") (pintype "passive"))
    )
    (net (code "353") (name "Net-(O3G11-K)") (class "Default")
      (node (ref "O3G11") (pin "1") (pinfunction "K_1") (pintype "bidirectional"))
      (node (ref "R54") (pin "2") (pinfunction "2_2") (pintype "passive"))
    )
    (net (code "354") (name "Net-(O4G9-K)") (class "Default")
      (node (ref "O4G9") (pin "1") (pinfunction "K_1") (pintype "bidirectional"))
      (node (ref "R41") (pin "2") (pinfunction "2_2") (pintype "passive"))
    )
    (net (code "355") (name "Net-(O4G11-K)") (class "Default")
      (node (ref "O4G11") (pin "1") (pinfunction "K_1") (pintype "bidirectional"))
      (node (ref "R55") (pin "2") (pinfunction "2_2") (pintype "passive"))
    )
    (net (code "356") (name "Net-(O5G9-K)") (class "Default")
      (node (ref "O5G9") (pin "1") (pinfunction "K_1") (pintype "bidirectional"))
      (node (ref "R42") (pin "2") (pinfunction "2_2") (pintype "passive"))
    )
    (net (code "357") (name "Net-(O5G11-K)") (class "Default")
      (node (ref "O5G11") (pin "1") (pinfunction "K_1") (pintype "bidirectional"))
      (node (ref "R56") (pin "2") (pinfunction "2_2") (pintype "passive"))
    )
    (net (code "358") (name "Net-(O6G7-K)") (class "Default")
      (node (ref "O6G7") (pin "1") (pinfunction "K_1") (pintype "bidirectional"))
      (node (ref "R27") (pin "2") (pinfunction "2_2") (pintype "passive"))
    )
    (net (code "359") (name "Net-(O6G9-K)") (class "Default")
      (node (ref "O6G9") (pin "1") (pinfunction "K_1") (pintype "bidirectional"))
      (node (ref "R43") (pin "2") (pinfunction "2_2") (pintype "passive"))
    )
    (net (code "360") (name "Net-(O6G11-K)") (class "Default")
      (node (ref "O6G11") (pin "1") (pinfunction "K_1") (pintype "bidirectional"))
      (node (ref "R57") (pin "2") (pinfunction "2_2") (pintype "passive"))
    )
    (net (code "361") (name "Net-(O7G9-K)") (class "Default")
      (node (ref "O7G9") (pin "1") (pinfunction "K_1") (pintype "bidirectional"))
      (node (ref "R44") (pin "2") (pinfunction "2_2") (pintype "passive"))
    )
    (net (code "362") (name "Net-(O7G11-K)") (class "Default")
      (node (ref "O7G11") (pin "1") (pinfunction "K_1") (pintype "bidirectional"))
      (node (ref "R58") (pin "2") (pinfunction "2_2") (pintype "passive"))
    )
    (net (code "363") (name "Net-(O8G9-K)") (class "Default")
      (node (ref "O8G9") (pin "1") (pinfunction "K_1") (pintype "bidirectional"))
      (node (ref "R45") (pin "2") (pinfunction "2_2") (pintype "passive"))
    )
    (net (code "364") (name "Net-(O8G11-K)") (class "Default")
      (node (ref "O8G11") (pin "1") (pinfunction "K_1") (pintype "bidirectional"))
      (node (ref "R59") (pin "2") (pinfunction "2_2") (pintype "passive"))
    )
    (net (code "365") (name "Net-(R1G3-K)") (class "Default")
      (node (ref "R1") (pin "2") (pinfunction "2_2") (pintype "passive"))
      (node (ref "R1G3") (pin "1") (pinfunction "K_1") (pintype "bidirectional"))
    )
    (net (code "366") (name "Net-(R1G6-K)") (class "Default")
      (node (ref "R14") (pin "2") (pinfunction "2_2") (pintype "passive"))
      (node (ref "R1G6") (pin "1") (pinfunction "K_1") (pintype "bidirectional"))
    )
    (net (code "367") (name "Net-(R1G15-K)") (class "Default")
      (node (ref "R1G15") (pin "1") (pinfunction "K_1") (pintype "bidirectional"))
      (node (ref "R76") (pin "2") (pinfunction "2_2") (pintype "passive"))
    )
    (net (code "368") (name "Net-(R1G17-K)") (class "Default")
      (node (ref "R1G17") (pin "1") (pinfunction "K_1") (pintype "bidirectional"))
      (node (ref "R84") (pin "2") (pinfunction "2_2") (pintype "passive"))
    )
    (net (code "369") (name "Net-(R2G3-K)") (class "Default")
      (node (ref "R2") (pin "2") (pinfunction "2_2") (pintype "passive"))
      (node (ref "R2G3") (pin "1") (pinfunction "K_1") (pintype "bidirectional"))
    )
    (net (code "370") (name "Net-(R2G6-K)") (class "Default")
      (node (ref "R15") (pin "2") (pinfunction "2_2") (pintype "passive"))
      (node (ref "R2G6") (pin "1") (pinfunction "K_1") (pintype "bidirectional"))
    )
    (net (code "371") (name "Net-(R2G15-K)") (class "Default")
      (node (ref "R2G15") (pin "1") (pinfunction "K_1") (pintype "bidirectional"))
      (node (ref "R77") (pin "2") (pinfunction "2_2") (pintype "passive"))
    )
    (net (code "372") (name "Net-(R2G17-K)") (class "Default")
      (node (ref "R2G17") (pin "1") (pinfunction "K_1") (pintype "bidirectional"))
      (node (ref "R85") (pin "2") (pinfunction "2_2") (pintype "passive"))
    )
    (net (code "373") (name "Net-(R3G3-K)") (class "Default")
      (node (ref "R3G3") (pin "1") (pinfunction "K_1") (pintype "bidirectional"))
      (node (ref "R5") (pin "2") (pinfunction "2_2") (pintype "passive"))
    )
    (net (code "374") (name "Net-(R3G6-K)") (class "Default")
      (node (ref "R16") (pin "2") (pinfunction "2_2") (pintype "passive"))
      (node (ref "R3G6") (pin "1") (pinfunction "K_1") (pintype "bidirectional"))
    )
    (net (code "375") (name "Net-(R3G15-K)") (class "Default")
      (node (ref "R3G15") (pin "1") (pinfunction "K_1") (pintype "bidirectional"))
      (node (ref "R78") (pin "2") (pinfunction "2_2") (pintype "passive"))
    )
    (net (code "376") (name "Net-(R4G3-K)") (class "Default")
      (node (ref "R4G3") (pin "1") (pinfunction "K_1") (pintype "bidirectional"))
      (node (ref "R6") (pin "2") (pinfunction "2_2") (pintype "passive"))
    )
    (net (code "377") (name "Net-(R4G6-K)") (class "Default")
      (node (ref "R17") (pin "2") (pinfunction "2_2") (pintype "passive"))
      (node (ref "R4G6") (pin "1") (pinfunction "K_1") (pintype "bidirectional"))
    )
    (net (code "378") (name "Net-(R4G15-K)") (class "Default")
      (node (ref "R4G15") (pin "1") (pinfunction "K_1") (pintype "bidirectional"))
      (node (ref "R79") (pin "2") (pinfunction "2_2") (pintype "passive"))
    )
    (net (code "379") (name "Net-(R5G3-K)") (class "Default")
      (node (ref "R5G3") (pin "1") (pinfunction "K_1") (pintype "bidirectional"))
      (node (ref "R7") (pin "2") (pinfunction "2_2") (pintype "passive"))
    )
    (net (code "380") (name "Net-(R5G5-K)") (class "Default")
      (node (ref "R10") (pin "2") (pinfunction "2_2") (pintype "passive"))
      (node (ref "R5G5") (pin "1") (pinfunction "K_1") (pintype "bidirectional"))
    )
    (net (code "381") (name "Net-(R5G6-K)") (class "Default")
      (node (ref "R18") (pin "2") (pinfunction "2_2") (pintype "passive"))
      (node (ref "R5G6") (pin "1") (pinfunction "K_1") (pintype "bidirectional"))
    )
    (net (code "382") (name "Net-(R5G15-K)") (class "Default")
      (node (ref "R5G15") (pin "1") (pinfunction "K_1") (pintype "bidirectional"))
      (node (ref "R80") (pin "2") (pinfunction "2_2") (pintype "passive"))
    )
    (net (code "383") (name "Net-(R6G3-K)") (class "Default")
      (node (ref "R6G3") (pin "1") (pinfunction "K_1") (pintype "bidirectional"))
      (node (ref "R8") (pin "2") (pinfunction "2_2") (pintype "passive"))
    )
    (net (code "384") (name "Net-(R6G6-K)") (class "Default")
      (node (ref "R19") (pin "2") (pinfunction "2_2") (pintype "passive"))
      (node (ref "R6G6") (pin "1") (pinfunction "K_1") (pintype "bidirectional"))
    )
    (net (code "385") (name "Net-(R6G15-K)") (class "Default")
      (node (ref "R6G15") (pin "1") (pinfunction "K_1") (pintype "bidirectional"))
      (node (ref "R81") (pin "2") (pinfunction "2_2") (pintype "passive"))
    )
    (net (code "386") (name "Net-(R7G3-K)") (class "Default")
      (node (ref "R7G3") (pin "1") (pinfunction "K_1") (pintype "bidirectional"))
      (node (ref "R9") (pin "2") (pinfunction "2_2") (pintype "passive"))
    )
    (net (code "387") (name "Net-(R7G6-K)") (class "Default")
      (node (ref "R20") (pin "2") (pinfunction "2_2") (pintype "passive"))
      (node (ref "R7G6") (pin "1") (pinfunction "K_1") (pintype "bidirectional"))
    )
    (net (code "388") (name "Net-(R7G15-K)") (class "Default")
      (node (ref "R7G15") (pin "1") (pinfunction "K_1") (pintype "bidirectional"))
      (node (ref "R82") (pin "2") (pinfunction "2_2") (pintype "passive"))
    )
    (net (code "389") (name "Net-(R8G3-K)") (class "Default")
      (node (ref "R8G3") (pin "1") (pinfunction "K_1") (pintype "bidirectional"))
      (node (ref "R94") (pin "2") (pinfunction "2_2") (pintype "passive"))
    )
    (net (code "390") (name "Net-(R8G6-K)") (class "Default")
      (node (ref "R21") (pin "2") (pinfunction "2_2") (pintype "passive"))
      (node (ref "R8G6") (pin "1") (pinfunction "K_1") (pintype "bidirectional"))
    )
    (net (code "391") (name "Net-(R8G15-K)") (class "Default")
      (node (ref "R83") (pin "2") (pinfunction "2_2") (pintype "passive"))
      (node (ref "R8G15") (pin "1") (pinfunction "K_1") (pintype "bidirectional"))
    )
    (net (code "392") (name "Net-(U1-EXT_5V)") (class "Default")
      (node (ref "JP1") (pin "2") (pinfunction "2_2") (pintype "passive"))
      (node (ref "U1") (pin "19") (pinfunction "EXT_5V_19") (pintype "power_in"))
    )
    (net (code "393") (name "Net-(Y1G10-K)") (class "Default")
      (node (ref "R46") (pin "2") (pinfunction "2_2") (pintype "passive"))
      (node (ref "Y1G10") (pin "1") (pinfunction "K_1") (pintype "bidirectional"))
    )
    (net (code "394") (name "Net-(Y1G12-K)") (class "Default")
      (node (ref "R60") (pin "2") (pinfunction "2_2") (pintype "passive"))
      (node (ref "Y1G12") (pin "1") (pinfunction "K_1") (pintype "bidirectional"))
    )
    (net (code "395") (name "Net-(Y2G10-K)") (class "Default")
      (node (ref "R47") (pin "2") (pinfunction "2_2") (pintype "passive"))
      (node (ref "Y2G10") (pin "1") (pinfunction "K_1") (pintype "bidirectional"))
    )
    (net (code "396") (name "Net-(Y2G12-K)") (class "Default")
      (node (ref "R61") (pin "2") (pinfunction "2_2") (pintype "passive"))
      (node (ref "Y2G12") (pin "1") (pinfunction "K_1") (pintype "bidirectional"))
    )
    (net (code "397") (name "Net-(Y3G10-K)") (class "Default")
      (node (ref "R48") (pin "2") (pinfunction "2_2") (pintype "passive"))
      (node (ref "Y3G10") (pin "1") (pinfunction "K_1") (pintype "bidirectional"))
    )
    (net (code "398") (name "Net-(Y3G12-K)") (class "Default")
      (node (ref "R62") (pin "2") (pinfunction "2_2") (pintype "passive"))
      (node (ref "Y3G12") (pin "1") (pinfunction "K_1") (pintype "bidirectional"))
    )
    (net (code "399") (name "Net-(Y4G10-K)") (class "Default")
      (node (ref "R49") (pin "2") (pinfunction "2_2") (pintype "passive"))
      (node (ref "Y4G10") (pin "1") (pinfunction "K_1") (pintype "bidirectional"))
    )
    (net (code "400") (name "Net-(Y4G12-K)") (class "Default")
      (node (ref "R63") (pin "2") (pinfunction "2_2") (pintype "passive"))
      (node (ref "Y4G12") (pin "1") (pinfunction "K_1") (pintype "bidirectional"))
    )
    (net (code "401") (name "Net-(Y5G7-K)") (class "Default")
      (node (ref "R26") (pin "2") (pinfunction "2_2") (pintype "passive"))
      (node (ref "Y5G7") (pin "1") (pinfunction "K_1") (pintype "bidirectional"))
    )
    (net (code "402") (name "Net-(Y5G10-K)") (class "Default")
      (node (ref "R50") (pin "2") (pinfunction "2_2") (pintype "passive"))
      (node (ref "Y5G10") (pin "1") (pinfunction "K_1") (pintype "bidirectional"))
    )
    (net (code "403") (name "Net-(Y5G12-K)") (class "Default")
      (node (ref "R64") (pin "2") (pinfunction "2_2") (pintype "passive"))
      (node (ref "Y5G12") (pin "1") (pinfunction "K_1") (pintype "bidirectional"))
    )
    (net (code "404") (name "Net-(Y6G8-K)") (class "Default")
      (node (ref "R35") (pin "2") (pinfunction "2_2") (pintype "passive"))
      (node (ref "Y6G8") (pin "1") (pinfunction "K_1") (pintype "bidirectional"))
    )
    (net (code "405") (name "Net-(Y6G12-K)") (class "Default")
      (node (ref "R65") (pin "2") (pinfunction "2_2") (pintype "passive"))
      (node (ref "Y6G12") (pin "1") (pinfunction "K_1") (pintype "bidirectional"))
    )
    (net (code "406") (name "Net-(Y7G12-K)") (class "Default")
      (node (ref "R66") (pin "2") (pinfunction "2_2") (pintype "passive"))
      (node (ref "Y7G12") (pin "1") (pinfunction "K_1") (pintype "bidirectional"))
    )
    (net (code "407") (name "Net-(Y8G7-K)") (class "Default")
      (node (ref "R29") (pin "2") (pinfunction "2_2") (pintype "passive"))
      (node (ref "Y8G7") (pin "1") (pinfunction "K_1") (pintype "bidirectional"))
    )
    (net (code "408") (name "Net-(Y8G8-K)") (class "Default")
      (node (ref "R37") (pin "2") (pinfunction "2_2") (pintype "passive"))
      (node (ref "Y8G8") (pin "1") (pinfunction "K_1") (pintype "bidirectional"))
    )
    (net (code "409") (name "Net-(Y8G12-K)") (class "Default")
      (node (ref "R67") (pin "2") (pinfunction "2_2") (pintype "passive"))
      (node (ref "Y8G12") (pin "1") (pinfunction "K_1") (pintype "bidirectional"))
    )
    (net (code "410") (name "Q0") (class "Default")
      (node (ref "IC1") (pin "3") (pinfunction "1Q0_3") (pintype "bidirectional"))
      (node (ref "IC1") (pin "4") (pinfunction "~{1CP1}_4") (pintype "bidirectional"))
      (node (ref "IC3") (pin "1") (pinfunction "1A_1") (pintype "bidirectional"))
      (node (ref "U10") (pin "1") (pinfunction "A0_1") (pintype "input"))
      (node (ref "U11") (pin "1") (pinfunction "A0_1") (pintype "input"))
      (node (ref "U12") (pin "1") (pinfunction "A0_1") (pintype "input"))
      (node (ref "U13") (pin "1") (pinfunction "A0_1") (pintype "input"))
      (node (ref "U14") (pin "1") (pinfunction "A0_1") (pintype "input"))
      (node (ref "U15") (pin "1") (pinfunction "A0_1") (pintype "input"))
      (node (ref "U16") (pin "1") (pinfunction "A0_1") (pintype "input"))
      (node (ref "U17") (pin "1") (pinfunction "A0_1") (pintype "input"))
      (node (ref "U18") (pin "1") (pinfunction "A0_1") (pintype "input"))
      (node (ref "U19") (pin "1") (pinfunction "A0_1") (pintype "input"))
      (node (ref "U2") (pin "1") (pinfunction "A0_1") (pintype "input"))
      (node (ref "U3") (pin "1") (pinfunction "A0_1") (pintype "input"))
      (node (ref "U4") (pin "1") (pinfunction "A0_1") (pintype "input"))
      (node (ref "U5") (pin "1") (pinfunction "A0_1") (pintype "input"))
      (node (ref "U6") (pin "1") (pinfunction "A0_1") (pintype "input"))
      (node (ref "U7") (pin "1") (pinfunction "A0_1") (pintype "input"))
      (node (ref "U8") (pin "1") (pinfunction "A0_1") (pintype "input"))
      (node (ref "U9") (pin "1") (pinfunction "A0_1") (pintype "input"))
    )
    (net (code "411") (name "Q1") (class "Default")
      (node (ref "IC1") (pin "5") (pinfunction "1Q1_5") (pintype "bidirectional"))
      (node (ref "IC2") (pin "1") (pinfunction "1A_1") (pintype "bidirectional"))
      (node (ref "U10") (pin "2") (pinfunction "A1_2") (pintype "input"))
      (node (ref "U11") (pin "2") (pinfunction "A1_2") (pintype "input"))
      (node (ref "U12") (pin "2") (pinfunction "A1_2") (pintype "input"))
      (node (ref "U13") (pin "2") (pinfunction "A1_2") (pintype "input"))
      (node (ref "U14") (pin "2") (pinfunction "A1_2") (pintype "input"))
      (node (ref "U15") (pin "2") (pinfunction "A1_2") (pintype "input"))
      (node (ref "U16") (pin "2") (pinfunction "A1_2") (pintype "input"))
      (node (ref "U17") (pin "2") (pinfunction "A1_2") (pintype "input"))
      (node (ref "U18") (pin "2") (pinfunction "A1_2") (pintype "input"))
      (node (ref "U19") (pin "2") (pinfunction "A1_2") (pintype "input"))
      (node (ref "U2") (pin "2") (pinfunction "A1_2") (pintype "input"))
      (node (ref "U3") (pin "2") (pinfunction "A1_2") (pintype "input"))
      (node (ref "U4") (pin "2") (pinfunction "A1_2") (pintype "input"))
      (node (ref "U5") (pin "2") (pinfunction "A1_2") (pintype "input"))
      (node (ref "U6") (pin "2") (pinfunction "A1_2") (pintype "input"))
      (node (ref "U7") (pin "2") (pinfunction "A1_2") (pintype "input"))
      (node (ref "U8") (pin "2") (pinfunction "A1_2") (pintype "input"))
      (node (ref "U9") (pin "2") (pinfunction "A1_2") (pintype "input"))
    )
    (net (code "412") (name "Q2") (class "Default")
      (node (ref "IC1") (pin "6") (pinfunction "1Q2_6") (pintype "bidirectional"))
      (node (ref "IC2") (pin "3") (pinfunction "2A_3") (pintype "bidirectional"))
      (node (ref "U10") (pin "3") (pinfunction "A2_3") (pintype "input"))
      (node (ref "U11") (pin "3") (pinfunction "A2_3") (pintype "input"))
      (node (ref "U12") (pin "3") (pinfunction "A2_3") (pintype "input"))
      (node (ref "U13") (pin "3") (pinfunction "A2_3") (pintype "input"))
      (node (ref "U14") (pin "3") (pinfunction "A2_3") (pintype "input"))
      (node (ref "U15") (pin "3") (pinfunction "A2_3") (pintype "input"))
      (node (ref "U16") (pin "3") (pinfunction "A2_3") (pintype "input"))
      (node (ref "U17") (pin "3") (pinfunction "A2_3") (pintype "input"))
      (node (ref "U18") (pin "3") (pinfunction "A2_3") (pintype "input"))
      (node (ref "U19") (pin "3") (pinfunction "A2_3") (pintype "input"))
      (node (ref "U2") (pin "3") (pinfunction "A2_3") (pintype "input"))
      (node (ref "U3") (pin "3") (pinfunction "A2_3") (pintype "input"))
      (node (ref "U4") (pin "3") (pinfunction "A2_3") (pintype "input"))
      (node (ref "U5") (pin "3") (pinfunction "A2_3") (pintype "input"))
      (node (ref "U6") (pin "3") (pinfunction "A2_3") (pintype "input"))
      (node (ref "U7") (pin "3") (pinfunction "A2_3") (pintype "input"))
      (node (ref "U8") (pin "3") (pinfunction "A2_3") (pintype "input"))
      (node (ref "U9") (pin "3") (pinfunction "A2_3") (pintype "input"))
    )
    (net (code "413") (name "Q3") (class "Default")
      (node (ref "IC1") (pin "7") (pinfunction "1Q3_7") (pintype "bidirectional"))
      (node (ref "IC3") (pin "4") (pinfunction "2A_4") (pintype "bidirectional"))
    )
    (net (code "414") (name "unconnected-(IC1-2MR-Pad14)") (class "Default")
      (node (ref "IC1") (pin "14") (pinfunction "2MR_14") (pintype "bidirectional"))
    )
    (net (code "415") (name "unconnected-(IC1-2Q0-Pad13)") (class "Default")
      (node (ref "IC1") (pin "13") (pinfunction "2Q0_13") (pintype "bidirectional"))
    )
    (net (code "416") (name "unconnected-(IC1-2Q1-Pad11)") (class "Default")
      (node (ref "IC1") (pin "11") (pinfunction "2Q1_11") (pintype "bidirectional"))
    )
    (net (code "417") (name "unconnected-(IC1-2Q2-Pad10)") (class "Default")
      (node (ref "IC1") (pin "10") (pinfunction "2Q2_10") (pintype "bidirectional"))
    )
    (net (code "418") (name "unconnected-(IC1-2Q3-Pad9)") (class "Default")
      (node (ref "IC1") (pin "9") (pinfunction "2Q3_9") (pintype "bidirectional"))
    )
    (net (code "419") (name "unconnected-(IC1-~{2CP0}-Pad15)") (class "Default")
      (node (ref "IC1") (pin "15") (pinfunction "~{2CP0}_15") (pintype "bidirectional"))
    )
    (net (code "420") (name "unconnected-(IC1-~{2CP1}-Pad12)") (class "Default")
      (node (ref "IC1") (pin "12") (pinfunction "~{2CP1}_12") (pintype "bidirectional"))
    )
    (net (code "421") (name "unconnected-(IC2-3A-Pad5)") (class "Default")
      (node (ref "IC2") (pin "5") (pinfunction "3A_5") (pintype "bidirectional"))
    )
    (net (code "422") (name "unconnected-(IC2-3Y-Pad6)") (class "Default")
      (node (ref "IC2") (pin "6") (pinfunction "3Y_6") (pintype "bidirectional"))
    )
    (net (code "423") (name "unconnected-(IC2-4A-Pad9)") (class "Default")
      (node (ref "IC2") (pin "9") (pinfunction "4A_9") (pintype "bidirectional"))
    )
    (net (code "424") (name "unconnected-(IC2-4Y-Pad8)") (class "Default")
      (node (ref "IC2") (pin "8") (pinfunction "4Y_8") (pintype "bidirectional"))
    )
    (net (code "425") (name "unconnected-(IC2-5A-Pad11)") (class "Default")
      (node (ref "IC2") (pin "11") (pinfunction "5A_11") (pintype "bidirectional"))
    )
    (net (code "426") (name "unconnected-(IC2-5Y-Pad10)") (class "Default")
      (node (ref "IC2") (pin "10") (pinfunction "5Y_10") (pintype "bidirectional"))
    )
    (net (code "427") (name "unconnected-(IC2-6A-Pad13)") (class "Default")
      (node (ref "IC2") (pin "13") (pinfunction "6A_13") (pintype "bidirectional"))
    )
    (net (code "428") (name "unconnected-(IC2-6Y-Pad12)") (class "Default")
      (node (ref "IC2") (pin "12") (pinfunction "6Y_12") (pintype "bidirectional"))
    )
    (net (code "429") (name "unconnected-(IC3-4A-Pad12)") (class "Default")
      (node (ref "IC3") (pin "12") (pinfunction "4A_12") (pintype "bidirectional"))
    )
    (net (code "430") (name "unconnected-(IC3-4B-Pad13)") (class "Default")
      (node (ref "IC3") (pin "13") (pinfunction "4B_13") (pintype "bidirectional"))
    )
    (net (code "431") (name "unconnected-(IC3-4Y-Pad11)") (class "Default")
      (node (ref "IC3") (pin "11") (pinfunction "4Y_11") (pintype "bidirectional"))
    )
    (net (code "432") (name "unconnected-(IC3-NC-Pad15)") (class "Default")
      (node (ref "IC3") (pin "15") (pinfunction "NC_15") (pintype "no_connect"))
    )
    (net (code "433") (name "unconnected-(IC4-4A-Pad12)") (class "Default")
      (node (ref "IC4") (pin "12") (pinfunction "4A_12") (pintype "bidirectional"))
    )
    (net (code "434") (name "unconnected-(IC4-4B-Pad13)") (class "Default")
      (node (ref "IC4") (pin "13") (pinfunction "4B_13") (pintype "bidirectional"))
    )
    (net (code "435") (name "unconnected-(IC4-4Y-Pad11)") (class "Default")
      (node (ref "IC4") (pin "11") (pinfunction "4Y_11") (pintype "bidirectional"))
    )
    (net (code "436") (name "unconnected-(IC4-NC-Pad15)") (class "Default")
      (node (ref "IC4") (pin "15") (pinfunction "NC_15") (pintype "no_connect"))
    )
    (net (code "437") (name "unconnected-(IC6-3A-Pad5)") (class "Default")
      (node (ref "IC6") (pin "5") (pinfunction "3A_5") (pintype "bidirectional"))
    )
    (net (code "438") (name "unconnected-(IC6-3Y-Pad6)") (class "Default")
      (node (ref "IC6") (pin "6") (pinfunction "3Y_6") (pintype "bidirectional"))
    )
    (net (code "439") (name "unconnected-(IC6-4A-Pad9)") (class "Default")
      (node (ref "IC6") (pin "9") (pinfunction "4A_9") (pintype "bidirectional"))
    )
    (net (code "440") (name "unconnected-(IC6-4Y-Pad8)") (class "Default")
      (node (ref "IC6") (pin "8") (pinfunction "4Y_8") (pintype "bidirectional"))
    )
    (net (code "441") (name "unconnected-(IC6-5A-Pad11)") (class "Default")
      (node (ref "IC6") (pin "11") (pinfunction "5A_11") (pintype "bidirectional"))
    )
    (net (code "442") (name "unconnected-(IC6-5Y-Pad10)") (class "Default")
      (node (ref "IC6") (pin "10") (pinfunction "5Y_10") (pintype "bidirectional"))
    )
    (net (code "443") (name "unconnected-(IC6-6A-Pad13)") (class "Default")
      (node (ref "IC6") (pin "13") (pinfunction "6A_13") (pintype "bidirectional"))
    )
    (net (code "444") (name "unconnected-(IC6-6Y-Pad12)") (class "Default")
      (node (ref "IC6") (pin "12") (pinfunction "6Y_12") (pintype "bidirectional"))
    )
    (net (code "445") (name "unconnected-(IC8-2A-Pad3)") (class "Default")
      (node (ref "IC8") (pin "3") (pinfunction "2A_3") (pintype "bidirectional"))
    )
    (net (code "446") (name "unconnected-(IC8-2Y-Pad4)") (class "Default")
      (node (ref "IC8") (pin "4") (pinfunction "2Y_4") (pintype "bidirectional"))
    )
    (net (code "447") (name "unconnected-(IC8-3A-Pad5)") (class "Default")
      (node (ref "IC8") (pin "5") (pinfunction "3A_5") (pintype "bidirectional"))
    )
    (net (code "448") (name "unconnected-(IC8-3Y-Pad6)") (class "Default")
      (node (ref "IC8") (pin "6") (pinfunction "3Y_6") (pintype "bidirectional"))
    )
    (net (code "449") (name "unconnected-(IC8-4A-Pad9)") (class "Default")
      (node (ref "IC8") (pin "9") (pinfunction "4A_9") (pintype "bidirectional"))
    )
    (net (code "450") (name "unconnected-(IC8-4Y-Pad8)") (class "Default")
      (node (ref "IC8") (pin "8") (pinfunction "4Y_8") (pintype "bidirectional"))
    )
    (net (code "451") (name "unconnected-(IC8-5A-Pad11)") (class "Default")
      (node (ref "IC8") (pin "11") (pinfunction "5A_11") (pintype "bidirectional"))
    )
    (net (code "452") (name "unconnected-(IC8-5Y-Pad10)") (class "Default")
      (node (ref "IC8") (pin "10") (pinfunction "5Y_10") (pintype "bidirectional"))
    )
    (net (code "453") (name "unconnected-(IC8-6A-Pad13)") (class "Default")
      (node (ref "IC8") (pin "13") (pinfunction "6A_13") (pintype "bidirectional"))
    )
    (net (code "454") (name "unconnected-(IC8-6Y-Pad12)") (class "Default")
      (node (ref "IC8") (pin "12") (pinfunction "6Y_12") (pintype "bidirectional"))
    )
    (net (code "455") (name "unconnected-(IC10-3A-Pad5)") (class "Default")
      (node (ref "IC10") (pin "5") (pinfunction "3A_5") (pintype "bidirectional"))
    )
    (net (code "456") (name "unconnected-(IC10-3Y-Pad6)") (class "Default")
      (node (ref "IC10") (pin "6") (pinfunction "3Y_6") (pintype "bidirectional"))
    )
    (net (code "457") (name "unconnected-(IC10-4A-Pad9)") (class "Default")
      (node (ref "IC10") (pin "9") (pinfunction "4A_9") (pintype "bidirectional"))
    )
    (net (code "458") (name "unconnected-(IC10-4Y-Pad8)") (class "Default")
      (node (ref "IC10") (pin "8") (pinfunction "4Y_8") (pintype "bidirectional"))
    )
    (net (code "459") (name "unconnected-(IC10-5A-Pad11)") (class "Default")
      (node (ref "IC10") (pin "11") (pinfunction "5A_11") (pintype "bidirectional"))
    )
    (net (code "460") (name "unconnected-(IC10-5Y-Pad10)") (class "Default")
      (node (ref "IC10") (pin "10") (pinfunction "5Y_10") (pintype "bidirectional"))
    )
    (net (code "461") (name "unconnected-(IC10-6A-Pad13)") (class "Default")
      (node (ref "IC10") (pin "13") (pinfunction "6A_13") (pintype "bidirectional"))
    )
    (net (code "462") (name "unconnected-(IC10-6Y-Pad12)") (class "Default")
      (node (ref "IC10") (pin "12") (pinfunction "6Y_12") (pintype "bidirectional"))
    )
    (net (code "463") (name "unconnected-(IC12-3A-Pad5)") (class "Default")
      (node (ref "IC12") (pin "5") (pinfunction "3A_5") (pintype "bidirectional"))
    )
    (net (code "464") (name "unconnected-(IC12-3Y-Pad6)") (class "Default")
      (node (ref "IC12") (pin "6") (pinfunction "3Y_6") (pintype "bidirectional"))
    )
    (net (code "465") (name "unconnected-(IC12-4A-Pad9)") (class "Default")
      (node (ref "IC12") (pin "9") (pinfunction "4A_9") (pintype "bidirectional"))
    )
    (net (code "466") (name "unconnected-(IC12-4Y-Pad8)") (class "Default")
      (node (ref "IC12") (pin "8") (pinfunction "4Y_8") (pintype "bidirectional"))
    )
    (net (code "467") (name "unconnected-(IC12-5A-Pad11)") (class "Default")
      (node (ref "IC12") (pin "11") (pinfunction "5A_11") (pintype "bidirectional"))
    )
    (net (code "468") (name "unconnected-(IC12-5Y-Pad10)") (class "Default")
      (node (ref "IC12") (pin "10") (pinfunction "5Y_10") (pintype "bidirectional"))
    )
    (net (code "469") (name "unconnected-(IC12-6A-Pad13)") (class "Default")
      (node (ref "IC12") (pin "13") (pinfunction "6A_13") (pintype "bidirectional"))
    )
    (net (code "470") (name "unconnected-(IC12-6Y-Pad12)") (class "Default")
      (node (ref "IC12") (pin "12") (pinfunction "6Y_12") (pintype "bidirectional"))
    )
    (net (code "471") (name "unconnected-(IC14-3A-Pad5)") (class "Default")
      (node (ref "IC14") (pin "5") (pinfunction "3A_5") (pintype "bidirectional"))
    )
    (net (code "472") (name "unconnected-(IC14-3Y-Pad6)") (class "Default")
      (node (ref "IC14") (pin "6") (pinfunction "3Y_6") (pintype "bidirectional"))
    )
    (net (code "473") (name "unconnected-(IC14-4A-Pad9)") (class "Default")
      (node (ref "IC14") (pin "9") (pinfunction "4A_9") (pintype "bidirectional"))
    )
    (net (code "474") (name "unconnected-(IC14-4Y-Pad8)") (class "Default")
      (node (ref "IC14") (pin "8") (pinfunction "4Y_8") (pintype "bidirectional"))
    )
    (net (code "475") (name "unconnected-(IC14-5A-Pad11)") (class "Default")
      (node (ref "IC14") (pin "11") (pinfunction "5A_11") (pintype "bidirectional"))
    )
    (net (code "476") (name "unconnected-(IC14-5Y-Pad10)") (class "Default")
      (node (ref "IC14") (pin "10") (pinfunction "5Y_10") (pintype "bidirectional"))
    )
    (net (code "477") (name "unconnected-(IC14-6A-Pad13)") (class "Default")
      (node (ref "IC14") (pin "13") (pinfunction "6A_13") (pintype "bidirectional"))
    )
    (net (code "478") (name "unconnected-(IC14-6Y-Pad12)") (class "Default")
      (node (ref "IC14") (pin "12") (pinfunction "6Y_12") (pintype "bidirectional"))
    )
    (net (code "479") (name "unconnected-(IC16-3A-Pad5)") (class "Default")
      (node (ref "IC16") (pin "5") (pinfunction "3A_5") (pintype "bidirectional"))
    )
    (net (code "480") (name "unconnected-(IC16-3Y-Pad6)") (class "Default")
      (node (ref "IC16") (pin "6") (pinfunction "3Y_6") (pintype "bidirectional"))
    )
    (net (code "481") (name "unconnected-(IC16-4A-Pad9)") (class "Default")
      (node (ref "IC16") (pin "9") (pinfunction "4A_9") (pintype "bidirectional"))
    )
    (net (code "482") (name "unconnected-(IC16-4Y-Pad8)") (class "Default")
      (node (ref "IC16") (pin "8") (pinfunction "4Y_8") (pintype "bidirectional"))
    )
    (net (code "483") (name "unconnected-(IC16-5A-Pad11)") (class "Default")
      (node (ref "IC16") (pin "11") (pinfunction "5A_11") (pintype "bidirectional"))
    )
    (net (code "484") (name "unconnected-(IC16-5Y-Pad10)") (class "Default")
      (node (ref "IC16") (pin "10") (pinfunction "5Y_10") (pintype "bidirectional"))
    )
    (net (code "485") (name "unconnected-(IC16-6A-Pad13)") (class "Default")
      (node (ref "IC16") (pin "13") (pinfunction "6A_13") (pintype "bidirectional"))
    )
    (net (code "486") (name "unconnected-(IC16-6Y-Pad12)") (class "Default")
      (node (ref "IC16") (pin "12") (pinfunction "6Y_12") (pintype "bidirectional"))
    )
    (net (code "487") (name "unconnected-(IC18-3A-Pad5)") (class "Default")
      (node (ref "IC18") (pin "5") (pinfunction "3A_5") (pintype "bidirectional"))
    )
    (net (code "488") (name "unconnected-(IC18-3Y-Pad6)") (class "Default")
      (node (ref "IC18") (pin "6") (pinfunction "3Y_6") (pintype "bidirectional"))
    )
    (net (code "489") (name "unconnected-(IC18-4A-Pad9)") (class "Default")
      (node (ref "IC18") (pin "9") (pinfunction "4A_9") (pintype "bidirectional"))
    )
    (net (code "490") (name "unconnected-(IC18-4Y-Pad8)") (class "Default")
      (node (ref "IC18") (pin "8") (pinfunction "4Y_8") (pintype "bidirectional"))
    )
    (net (code "491") (name "unconnected-(IC18-5A-Pad11)") (class "Default")
      (node (ref "IC18") (pin "11") (pinfunction "5A_11") (pintype "bidirectional"))
    )
    (net (code "492") (name "unconnected-(IC18-5Y-Pad10)") (class "Default")
      (node (ref "IC18") (pin "10") (pinfunction "5Y_10") (pintype "bidirectional"))
    )
    (net (code "493") (name "unconnected-(IC18-6A-Pad13)") (class "Default")
      (node (ref "IC18") (pin "13") (pinfunction "6A_13") (pintype "bidirectional"))
    )
    (net (code "494") (name "unconnected-(IC18-6Y-Pad12)") (class "Default")
      (node (ref "IC18") (pin "12") (pinfunction "6Y_12") (pintype "bidirectional"))
    )
    (net (code "495") (name "unconnected-(IC20-3A-Pad5)") (class "Default")
      (node (ref "IC20") (pin "5") (pinfunction "3A_5") (pintype "bidirectional"))
    )
    (net (code "496") (name "unconnected-(IC20-3Y-Pad6)") (class "Default")
      (node (ref "IC20") (pin "6") (pinfunction "3Y_6") (pintype "bidirectional"))
    )
    (net (code "497") (name "unconnected-(IC20-4A-Pad9)") (class "Default")
      (node (ref "IC20") (pin "9") (pinfunction "4A_9") (pintype "bidirectional"))
    )
    (net (code "498") (name "unconnected-(IC20-4Y-Pad8)") (class "Default")
      (node (ref "IC20") (pin "8") (pinfunction "4Y_8") (pintype "bidirectional"))
    )
    (net (code "499") (name "unconnected-(IC20-5A-Pad11)") (class "Default")
      (node (ref "IC20") (pin "11") (pinfunction "5A_11") (pintype "bidirectional"))
    )
    (net (code "500") (name "unconnected-(IC20-5Y-Pad10)") (class "Default")
      (node (ref "IC20") (pin "10") (pinfunction "5Y_10") (pintype "bidirectional"))
    )
    (net (code "501") (name "unconnected-(IC20-6A-Pad13)") (class "Default")
      (node (ref "IC20") (pin "13") (pinfunction "6A_13") (pintype "bidirectional"))
    )
    (net (code "502") (name "unconnected-(IC20-6Y-Pad12)") (class "Default")
      (node (ref "IC20") (pin "12") (pinfunction "6Y_12") (pintype "bidirectional"))
    )
    (net (code "503") (name "unconnected-(IC22-3A-Pad5)") (class "Default")
      (node (ref "IC22") (pin "5") (pinfunction "3A_5") (pintype "bidirectional"))
    )
    (net (code "504") (name "unconnected-(IC22-3Y-Pad6)") (class "Default")
      (node (ref "IC22") (pin "6") (pinfunction "3Y_6") (pintype "bidirectional"))
    )
    (net (code "505") (name "unconnected-(IC22-4A-Pad9)") (class "Default")
      (node (ref "IC22") (pin "9") (pinfunction "4A_9") (pintype "bidirectional"))
    )
    (net (code "506") (name "unconnected-(IC22-4Y-Pad8)") (class "Default")
      (node (ref "IC22") (pin "8") (pinfunction "4Y_8") (pintype "bidirectional"))
    )
    (net (code "507") (name "unconnected-(IC22-5A-Pad11)") (class "Default")
      (node (ref "IC22") (pin "11") (pinfunction "5A_11") (pintype "bidirectional"))
    )
    (net (code "508") (name "unconnected-(IC22-5Y-Pad10)") (class "Default")
      (node (ref "IC22") (pin "10") (pinfunction "5Y_10") (pintype "bidirectional"))
    )
    (net (code "509") (name "unconnected-(IC22-6A-Pad13)") (class "Default")
      (node (ref "IC22") (pin "13") (pinfunction "6A_13") (pintype "bidirectional"))
    )
    (net (code "510") (name "unconnected-(IC22-6Y-Pad12)") (class "Default")
      (node (ref "IC22") (pin "12") (pinfunction "6Y_12") (pintype "bidirectional"))
    )
    (net (code "511") (name "unconnected-(IC23-4A-Pad9)") (class "Default")
      (node (ref "IC23") (pin "9") (pinfunction "4A_9") (pintype "bidirectional"))
    )
    (net (code "512") (name "unconnected-(IC23-4Y-Pad8)") (class "Default")
      (node (ref "IC23") (pin "8") (pinfunction "4Y_8") (pintype "bidirectional"))
    )
    (net (code "513") (name "unconnected-(IC26-3A-Pad5)") (class "Default")
      (node (ref "IC26") (pin "5") (pinfunction "3A_5") (pintype "bidirectional"))
    )
    (net (code "514") (name "unconnected-(IC26-3Y-Pad6)") (class "Default")
      (node (ref "IC26") (pin "6") (pinfunction "3Y_6") (pintype "bidirectional"))
    )
    (net (code "515") (name "unconnected-(IC26-4A-Pad9)") (class "Default")
      (node (ref "IC26") (pin "9") (pinfunction "4A_9") (pintype "bidirectional"))
    )
    (net (code "516") (name "unconnected-(IC26-4Y-Pad8)") (class "Default")
      (node (ref "IC26") (pin "8") (pinfunction "4Y_8") (pintype "bidirectional"))
    )
    (net (code "517") (name "unconnected-(IC26-5A-Pad11)") (class "Default")
      (node (ref "IC26") (pin "11") (pinfunction "5A_11") (pintype "bidirectional"))
    )
    (net (code "518") (name "unconnected-(IC26-5Y-Pad10)") (class "Default")
      (node (ref "IC26") (pin "10") (pinfunction "5Y_10") (pintype "bidirectional"))
    )
    (net (code "519") (name "unconnected-(IC26-6A-Pad13)") (class "Default")
      (node (ref "IC26") (pin "13") (pinfunction "6A_13") (pintype "bidirectional"))
    )
    (net (code "520") (name "unconnected-(IC26-6Y-Pad12)") (class "Default")
      (node (ref "IC26") (pin "12") (pinfunction "6Y_12") (pintype "bidirectional"))
    )
    (net (code "521") (name "unconnected-(IC28-3A-Pad5)") (class "Default")
      (node (ref "IC28") (pin "5") (pinfunction "3A_5") (pintype "bidirectional"))
    )
    (net (code "522") (name "unconnected-(IC28-3Y-Pad6)") (class "Default")
      (node (ref "IC28") (pin "6") (pinfunction "3Y_6") (pintype "bidirectional"))
    )
    (net (code "523") (name "unconnected-(IC28-4A-Pad9)") (class "Default")
      (node (ref "IC28") (pin "9") (pinfunction "4A_9") (pintype "bidirectional"))
    )
    (net (code "524") (name "unconnected-(IC28-4Y-Pad8)") (class "Default")
      (node (ref "IC28") (pin "8") (pinfunction "4Y_8") (pintype "bidirectional"))
    )
    (net (code "525") (name "unconnected-(IC28-5A-Pad11)") (class "Default")
      (node (ref "IC28") (pin "11") (pinfunction "5A_11") (pintype "bidirectional"))
    )
    (net (code "526") (name "unconnected-(IC28-5Y-Pad10)") (class "Default")
      (node (ref "IC28") (pin "10") (pinfunction "5Y_10") (pintype "bidirectional"))
    )
    (net (code "527") (name "unconnected-(IC28-6A-Pad13)") (class "Default")
      (node (ref "IC28") (pin "13") (pinfunction "6A_13") (pintype "bidirectional"))
    )
    (net (code "528") (name "unconnected-(IC28-6Y-Pad12)") (class "Default")
      (node (ref "IC28") (pin "12") (pinfunction "6Y_12") (pintype "bidirectional"))
    )
    (net (code "529") (name "unconnected-(IC30-3A-Pad5)") (class "Default")
      (node (ref "IC30") (pin "5") (pinfunction "3A_5") (pintype "bidirectional"))
    )
    (net (code "530") (name "unconnected-(IC30-3Y-Pad6)") (class "Default")
      (node (ref "IC30") (pin "6") (pinfunction "3Y_6") (pintype "bidirectional"))
    )
    (net (code "531") (name "unconnected-(IC30-4A-Pad9)") (class "Default")
      (node (ref "IC30") (pin "9") (pinfunction "4A_9") (pintype "bidirectional"))
    )
    (net (code "532") (name "unconnected-(IC30-4Y-Pad8)") (class "Default")
      (node (ref "IC30") (pin "8") (pinfunction "4Y_8") (pintype "bidirectional"))
    )
    (net (code "533") (name "unconnected-(IC30-5A-Pad11)") (class "Default")
      (node (ref "IC30") (pin "11") (pinfunction "5A_11") (pintype "bidirectional"))
    )
    (net (code "534") (name "unconnected-(IC30-5Y-Pad10)") (class "Default")
      (node (ref "IC30") (pin "10") (pinfunction "5Y_10") (pintype "bidirectional"))
    )
    (net (code "535") (name "unconnected-(IC30-6A-Pad13)") (class "Default")
      (node (ref "IC30") (pin "13") (pinfunction "6A_13") (pintype "bidirectional"))
    )
    (net (code "536") (name "unconnected-(IC30-6Y-Pad12)") (class "Default")
      (node (ref "IC30") (pin "12") (pinfunction "6Y_12") (pintype "bidirectional"))
    )
    (net (code "537") (name "unconnected-(IC32-3A-Pad5)") (class "Default")
      (node (ref "IC32") (pin "5") (pinfunction "3A_5") (pintype "bidirectional"))
    )
    (net (code "538") (name "unconnected-(IC32-3Y-Pad6)") (class "Default")
      (node (ref "IC32") (pin "6") (pinfunction "3Y_6") (pintype "bidirectional"))
    )
    (net (code "539") (name "unconnected-(IC32-4A-Pad9)") (class "Default")
      (node (ref "IC32") (pin "9") (pinfunction "4A_9") (pintype "bidirectional"))
    )
    (net (code "540") (name "unconnected-(IC32-4Y-Pad8)") (class "Default")
      (node (ref "IC32") (pin "8") (pinfunction "4Y_8") (pintype "bidirectional"))
    )
    (net (code "541") (name "unconnected-(IC32-5A-Pad11)") (class "Default")
      (node (ref "IC32") (pin "11") (pinfunction "5A_11") (pintype "bidirectional"))
    )
    (net (code "542") (name "unconnected-(IC32-5Y-Pad10)") (class "Default")
      (node (ref "IC32") (pin "10") (pinfunction "5Y_10") (pintype "bidirectional"))
    )
    (net (code "543") (name "unconnected-(IC32-6A-Pad13)") (class "Default")
      (node (ref "IC32") (pin "13") (pinfunction "6A_13") (pintype "bidirectional"))
    )
    (net (code "544") (name "unconnected-(IC32-6Y-Pad12)") (class "Default")
      (node (ref "IC32") (pin "12") (pinfunction "6Y_12") (pintype "bidirectional"))
    )
    (net (code "545") (name "unconnected-(IC34-3A-Pad5)") (class "Default")
      (node (ref "IC34") (pin "5") (pinfunction "3A_5") (pintype "bidirectional"))
    )
    (net (code "546") (name "unconnected-(IC34-3Y-Pad6)") (class "Default")
      (node (ref "IC34") (pin "6") (pinfunction "3Y_6") (pintype "bidirectional"))
    )
    (net (code "547") (name "unconnected-(IC34-4A-Pad9)") (class "Default")
      (node (ref "IC34") (pin "9") (pinfunction "4A_9") (pintype "bidirectional"))
    )
    (net (code "548") (name "unconnected-(IC34-4Y-Pad8)") (class "Default")
      (node (ref "IC34") (pin "8") (pinfunction "4Y_8") (pintype "bidirectional"))
    )
    (net (code "549") (name "unconnected-(IC34-5A-Pad11)") (class "Default")
      (node (ref "IC34") (pin "11") (pinfunction "5A_11") (pintype "bidirectional"))
    )
    (net (code "550") (name "unconnected-(IC34-5Y-Pad10)") (class "Default")
      (node (ref "IC34") (pin "10") (pinfunction "5Y_10") (pintype "bidirectional"))
    )
    (net (code "551") (name "unconnected-(IC34-6A-Pad13)") (class "Default")
      (node (ref "IC34") (pin "13") (pinfunction "6A_13") (pintype "bidirectional"))
    )
    (net (code "552") (name "unconnected-(IC34-6Y-Pad12)") (class "Default")
      (node (ref "IC34") (pin "12") (pinfunction "6Y_12") (pintype "bidirectional"))
    )
    (net (code "553") (name "unconnected-(IC36-3A-Pad5)") (class "Default")
      (node (ref "IC36") (pin "5") (pinfunction "3A_5") (pintype "bidirectional"))
    )
    (net (code "554") (name "unconnected-(IC36-3Y-Pad6)") (class "Default")
      (node (ref "IC36") (pin "6") (pinfunction "3Y_6") (pintype "bidirectional"))
    )
    (net (code "555") (name "unconnected-(IC36-4A-Pad9)") (class "Default")
      (node (ref "IC36") (pin "9") (pinfunction "4A_9") (pintype "bidirectional"))
    )
    (net (code "556") (name "unconnected-(IC36-4Y-Pad8)") (class "Default")
      (node (ref "IC36") (pin "8") (pinfunction "4Y_8") (pintype "bidirectional"))
    )
    (net (code "557") (name "unconnected-(IC36-5A-Pad11)") (class "Default")
      (node (ref "IC36") (pin "11") (pinfunction "5A_11") (pintype "bidirectional"))
    )
    (net (code "558") (name "unconnected-(IC36-5Y-Pad10)") (class "Default")
      (node (ref "IC36") (pin "10") (pinfunction "5Y_10") (pintype "bidirectional"))
    )
    (net (code "559") (name "unconnected-(IC36-6A-Pad13)") (class "Default")
      (node (ref "IC36") (pin "13") (pinfunction "6A_13") (pintype "bidirectional"))
    )
    (net (code "560") (name "unconnected-(IC36-6Y-Pad12)") (class "Default")
      (node (ref "IC36") (pin "12") (pinfunction "6Y_12") (pintype "bidirectional"))
    )
    (net (code "561") (name "unconnected-(IC38-3A-Pad5)") (class "Default")
      (node (ref "IC38") (pin "5") (pinfunction "3A_5") (pintype "bidirectional"))
    )
    (net (code "562") (name "unconnected-(IC38-3Y-Pad6)") (class "Default")
      (node (ref "IC38") (pin "6") (pinfunction "3Y_6") (pintype "bidirectional"))
    )
    (net (code "563") (name "unconnected-(IC38-4A-Pad9)") (class "Default")
      (node (ref "IC38") (pin "9") (pinfunction "4A_9") (pintype "bidirectional"))
    )
    (net (code "564") (name "unconnected-(IC38-4Y-Pad8)") (class "Default")
      (node (ref "IC38") (pin "8") (pinfunction "4Y_8") (pintype "bidirectional"))
    )
    (net (code "565") (name "unconnected-(IC38-5A-Pad11)") (class "Default")
      (node (ref "IC38") (pin "11") (pinfunction "5A_11") (pintype "bidirectional"))
    )
    (net (code "566") (name "unconnected-(IC38-5Y-Pad10)") (class "Default")
      (node (ref "IC38") (pin "10") (pinfunction "5Y_10") (pintype "bidirectional"))
    )
    (net (code "567") (name "unconnected-(IC38-6A-Pad13)") (class "Default")
      (node (ref "IC38") (pin "13") (pinfunction "6A_13") (pintype "bidirectional"))
    )
    (net (code "568") (name "unconnected-(IC38-6Y-Pad12)") (class "Default")
      (node (ref "IC38") (pin "12") (pinfunction "6Y_12") (pintype "bidirectional"))
    )
    (net (code "569") (name "unconnected-(IC40-3A-Pad5)") (class "Default")
      (node (ref "IC40") (pin "5") (pinfunction "3A_5") (pintype "bidirectional"))
    )
    (net (code "570") (name "unconnected-(IC40-3Y-Pad6)") (class "Default")
      (node (ref "IC40") (pin "6") (pinfunction "3Y_6") (pintype "bidirectional"))
    )
    (net (code "571") (name "unconnected-(IC40-4A-Pad9)") (class "Default")
      (node (ref "IC40") (pin "9") (pinfunction "4A_9") (pintype "bidirectional"))
    )
    (net (code "572") (name "unconnected-(IC40-4Y-Pad8)") (class "Default")
      (node (ref "IC40") (pin "8") (pinfunction "4Y_8") (pintype "bidirectional"))
    )
    (net (code "573") (name "unconnected-(IC40-5A-Pad11)") (class "Default")
      (node (ref "IC40") (pin "11") (pinfunction "5A_11") (pintype "bidirectional"))
    )
    (net (code "574") (name "unconnected-(IC40-5Y-Pad10)") (class "Default")
      (node (ref "IC40") (pin "10") (pinfunction "5Y_10") (pintype "bidirectional"))
    )
    (net (code "575") (name "unconnected-(IC40-6A-Pad13)") (class "Default")
      (node (ref "IC40") (pin "13") (pinfunction "6A_13") (pintype "bidirectional"))
    )
    (net (code "576") (name "unconnected-(IC40-6Y-Pad12)") (class "Default")
      (node (ref "IC40") (pin "12") (pinfunction "6Y_12") (pintype "bidirectional"))
    )
    (net (code "577") (name "unconnected-(U1-CLK-Pad38)") (class "Default")
      (node (ref "U1") (pin "38") (pinfunction "CLK_38") (pintype "input"))
    )
    (net (code "578") (name "unconnected-(U1-CMD-Pad18)") (class "Default")
      (node (ref "U1") (pin "18") (pinfunction "CMD_18") (pintype "bidirectional"))
    )
    (net (code "579") (name "unconnected-(U1-EN-Pad2)") (class "Default")
      (node (ref "U1") (pin "2") (pinfunction "EN_2") (pintype "input"))
    )
    (net (code "580") (name "unconnected-(U1-IO35-Pad6)") (class "Default")
      (node (ref "U1") (pin "6") (pinfunction "IO35_6") (pintype "bidirectional"))
    )
    (net (code "581") (name "unconnected-(U1-RXD0-Pad24)") (class "Default")
      (node (ref "U1") (pin "24") (pinfunction "RXD0_24") (pintype "input"))
    )
    (net (code "582") (name "unconnected-(U1-SD0-Pad37)") (class "Default")
      (node (ref "U1") (pin "37") (pinfunction "SD0_37") (pintype "bidirectional"))
    )
    (net (code "583") (name "unconnected-(U1-SD1-Pad36)") (class "Default")
      (node (ref "U1") (pin "36") (pinfunction "SD1_36") (pintype "bidirectional"))
    )
    (net (code "584") (name "unconnected-(U1-SD2-Pad16)") (class "Default")
      (node (ref "U1") (pin "16") (pinfunction "SD2_16") (pintype "bidirectional"))
    )
    (net (code "585") (name "unconnected-(U1-SD3-Pad17)") (class "Default")
      (node (ref "U1") (pin "17") (pinfunction "SD3_17") (pintype "bidirectional"))
    )
    (net (code "586") (name "unconnected-(U1-SENSOR_VN-Pad4)") (class "Default")
      (node (ref "U1") (pin "4") (pinfunction "SENSOR_VN_4") (pintype "input"))
    )
    (net (code "587") (name "unconnected-(U1-SENSOR_VP-Pad3)") (class "Default")
      (node (ref "U1") (pin "3") (pinfunction "SENSOR_VP_3") (pintype "input"))
    )
    (net (code "588") (name "unconnected-(U1-TXD0-Pad23)") (class "Default")
      (node (ref "U1") (pin "23") (pinfunction "TXD0_23") (pintype "output"))
    )
    (net (code "589") (name "unconnected-(U3-~{O7}-Pad7)") (class "Default")
      (node (ref "U3") (pin "7") (pinfunction "~{O7}_7") (pintype "output"))
    )
    (net (code "590") (name "unconnected-(U11-~{O5}-Pad10)") (class "Default")
      (node (ref "U11") (pin "10") (pinfunction "~{O5}_10") (pintype "output"))
    )
    (net (code "591") (name "unconnected-(U11-~{O6}-Pad9)") (class "Default")
      (node (ref "U11") (pin "9") (pinfunction "~{O6}_9") (pintype "output"))
    )
    (net (code "592") (name "unconnected-(U11-~{O7}-Pad7)") (class "Default")
      (node (ref "U11") (pin "7") (pinfunction "~{O7}_7") (pintype "output"))
    )
    (net (code "593") (name "unconnected-(VOLTAGE_REG-N.C.-Pad4)") (class "Default")
      (node (ref "VOLTAGE_REG") (pin "4") (pinfunction "N.C._4") (pintype "no_connect"))
    )
  )
)
